# Main_Board.net
KiCad netlist of a schematic drawn in Altium Designer
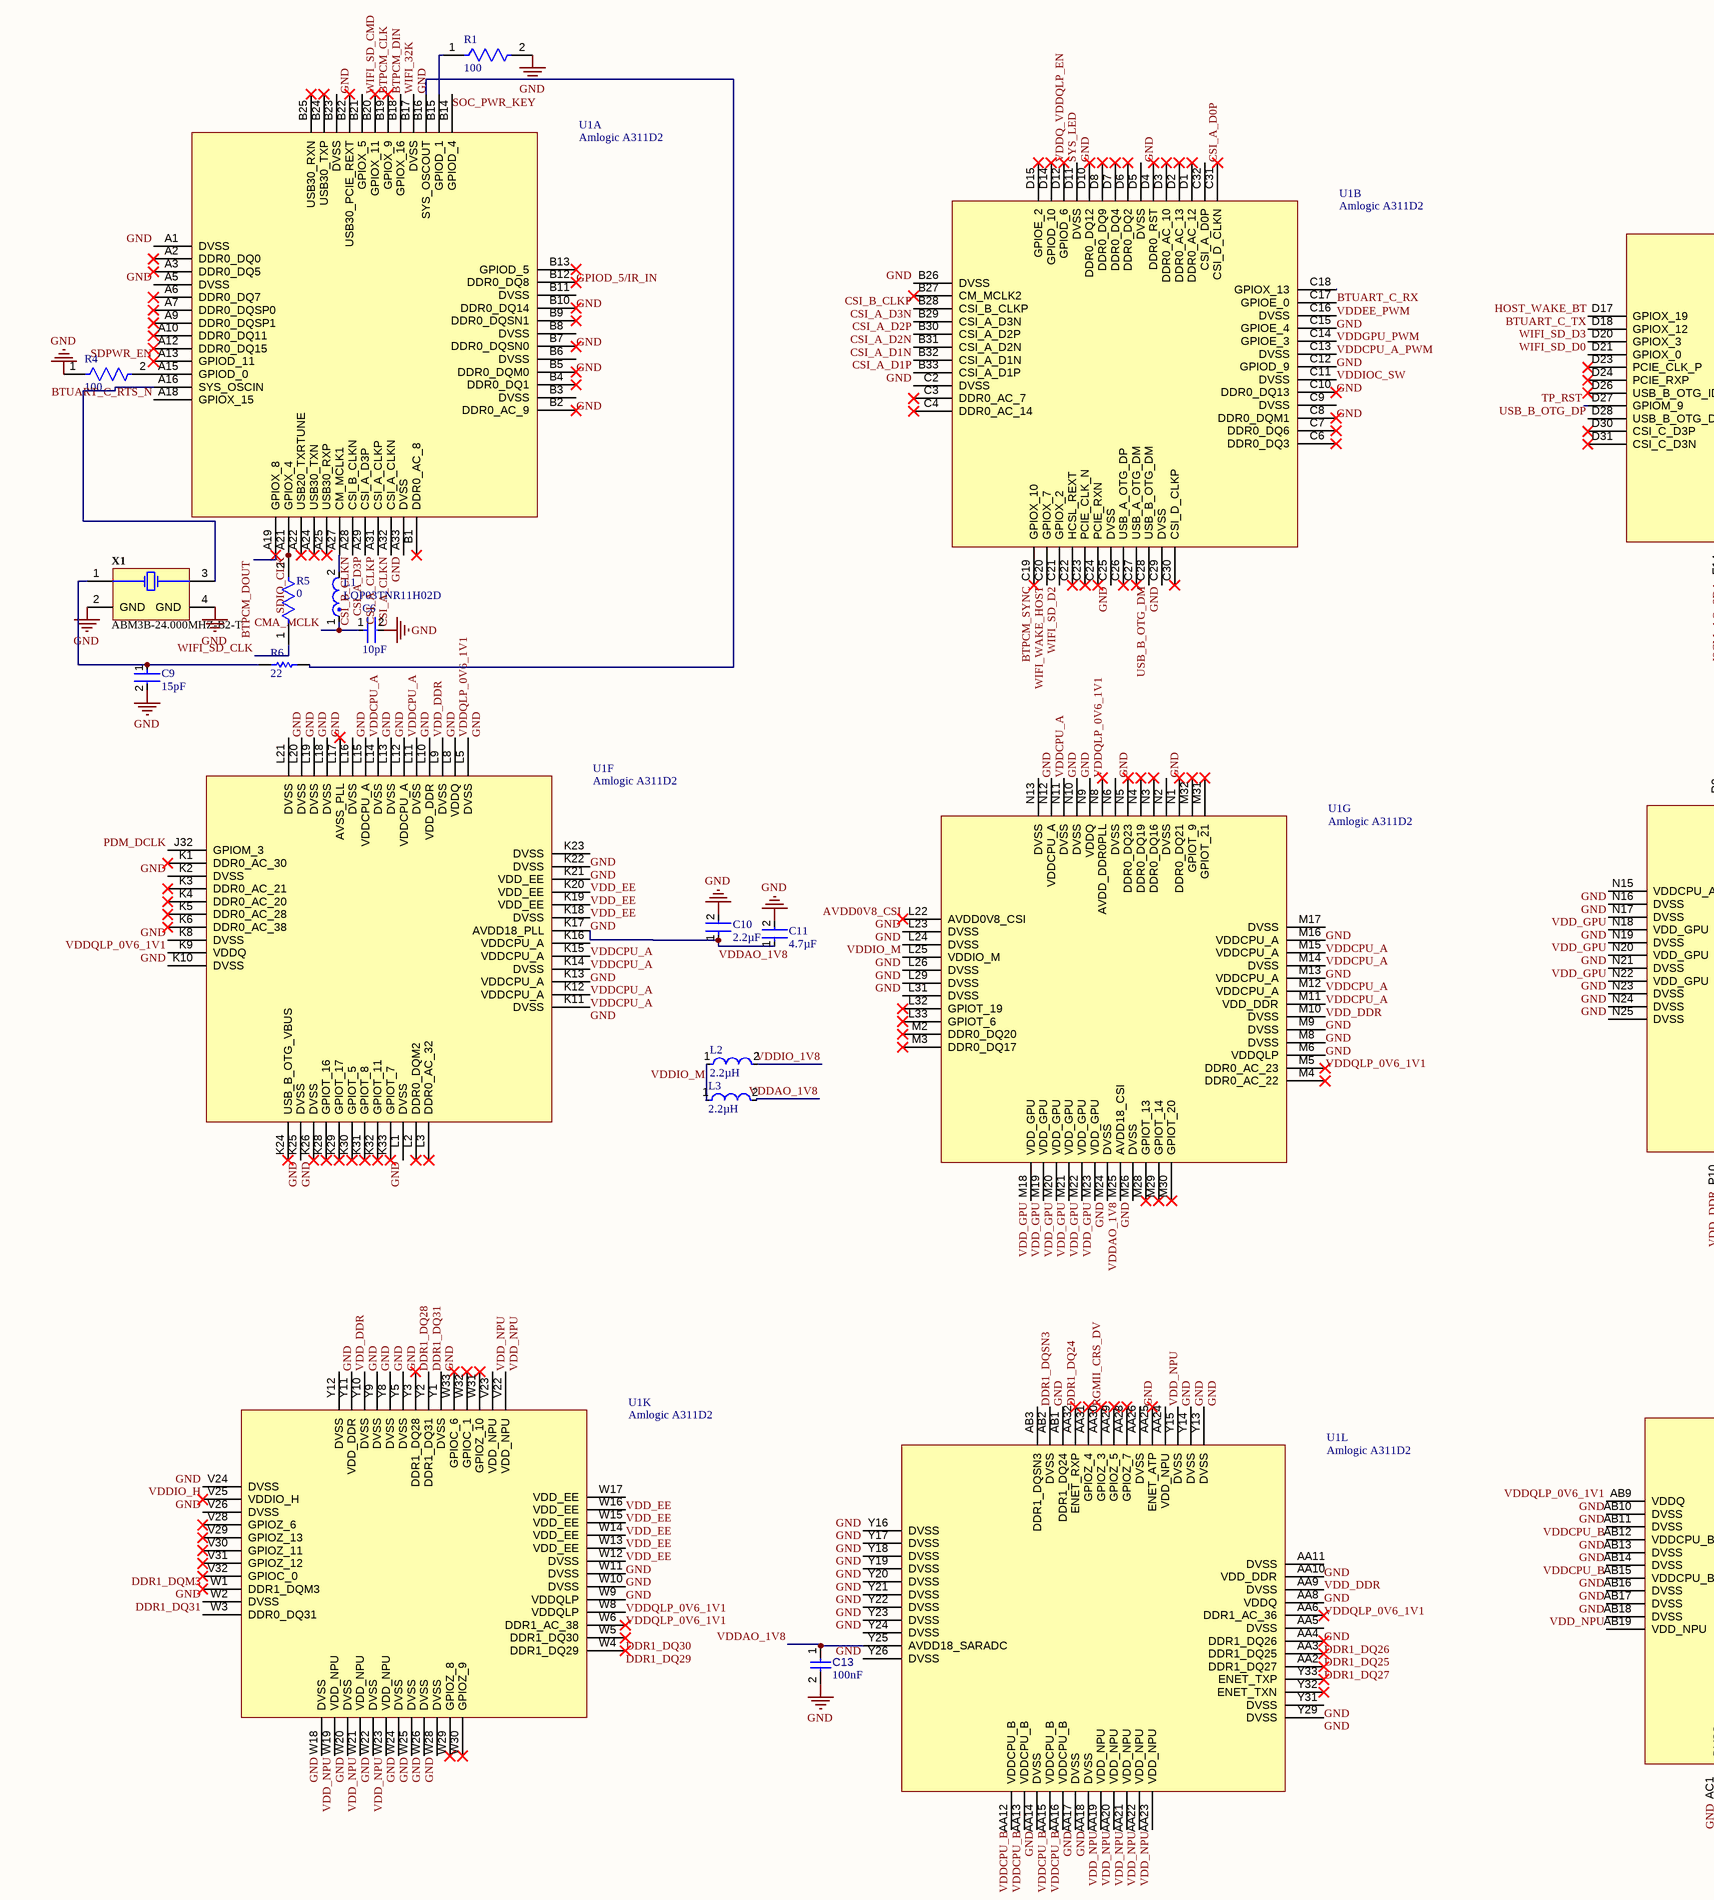
[diagram p0: Main_Board.SchDoc, top left]
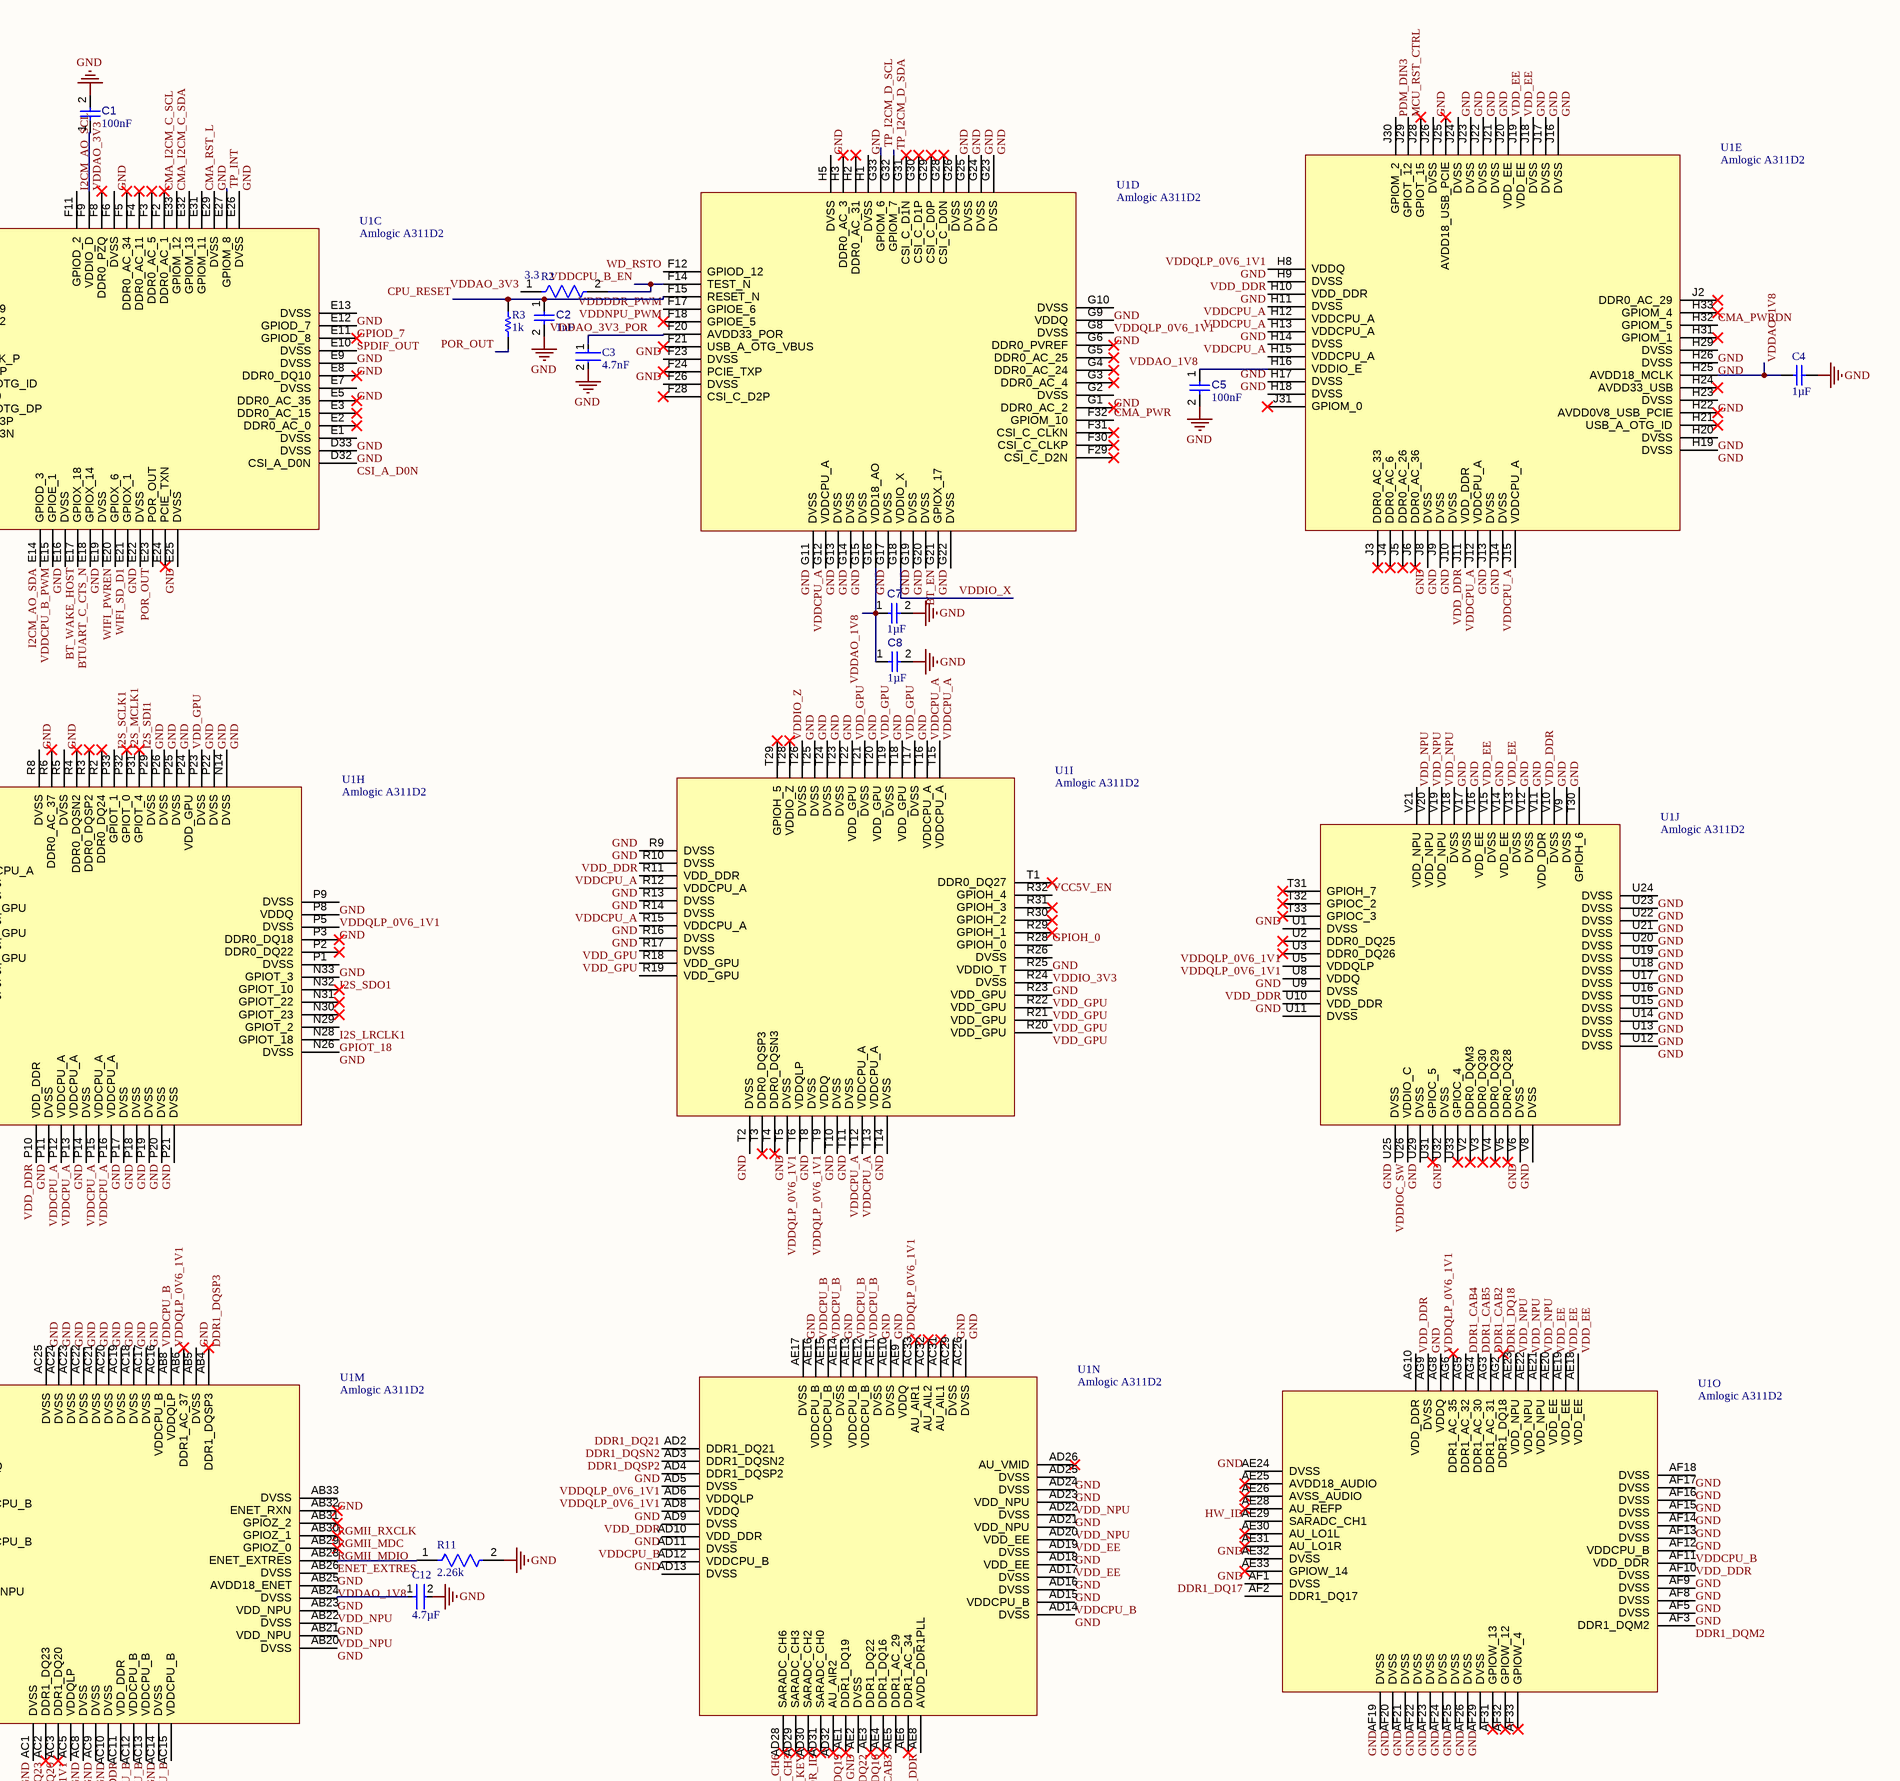
[diagram p1: Main_Board.SchDoc, top right]
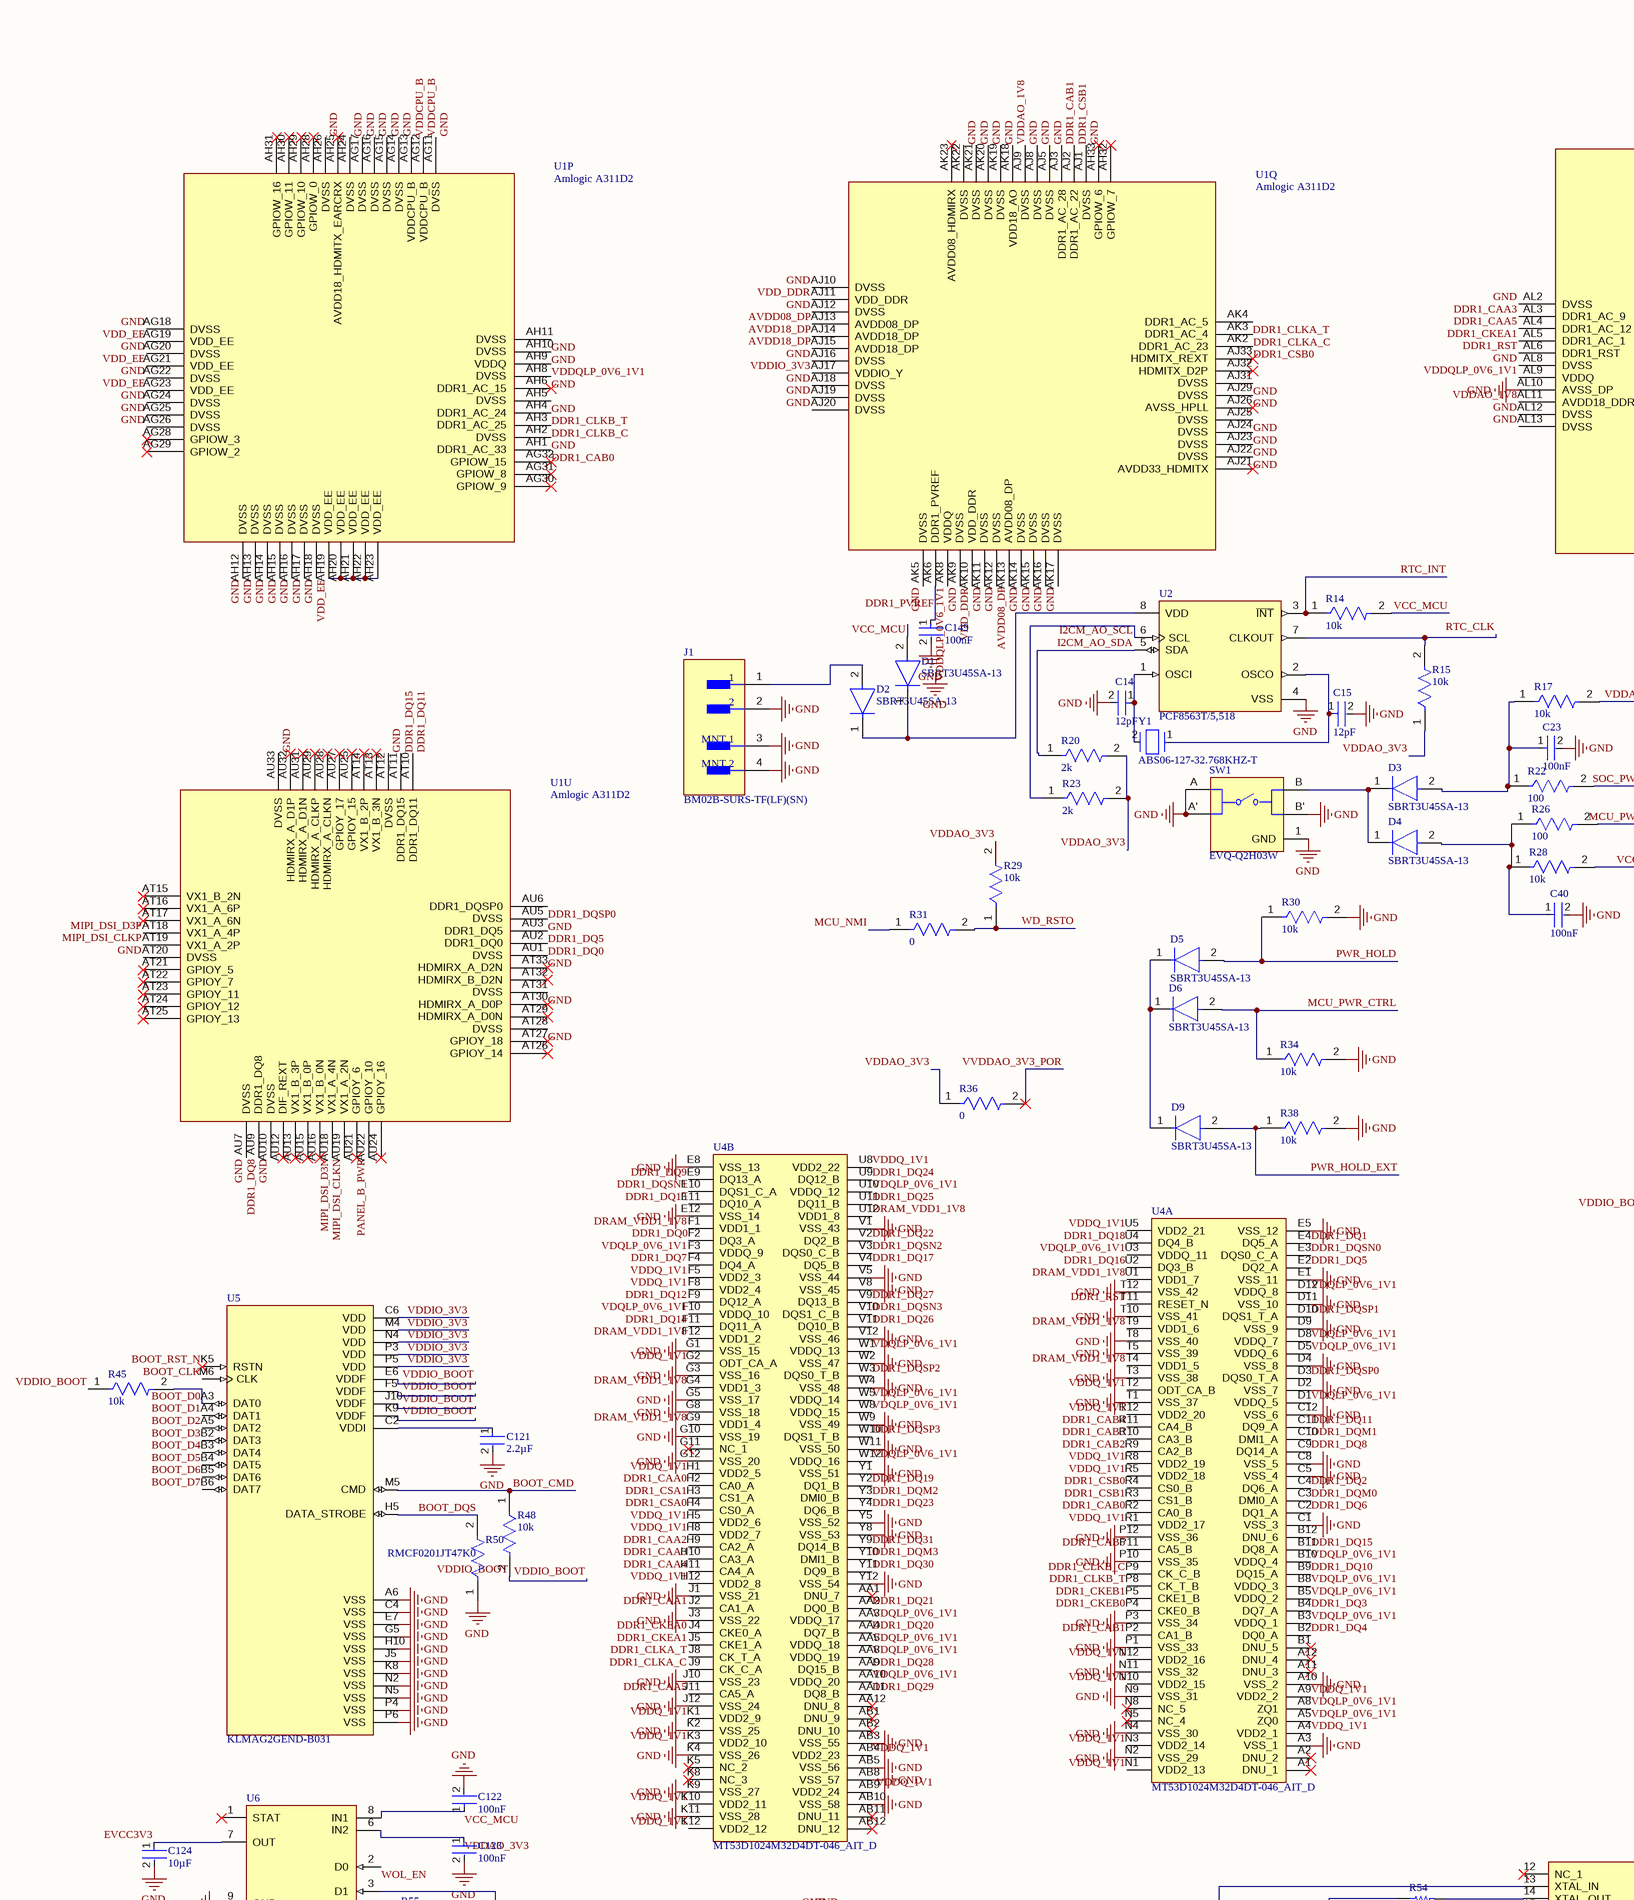
[diagram p2: Main_Board.SchDoc, centre left]
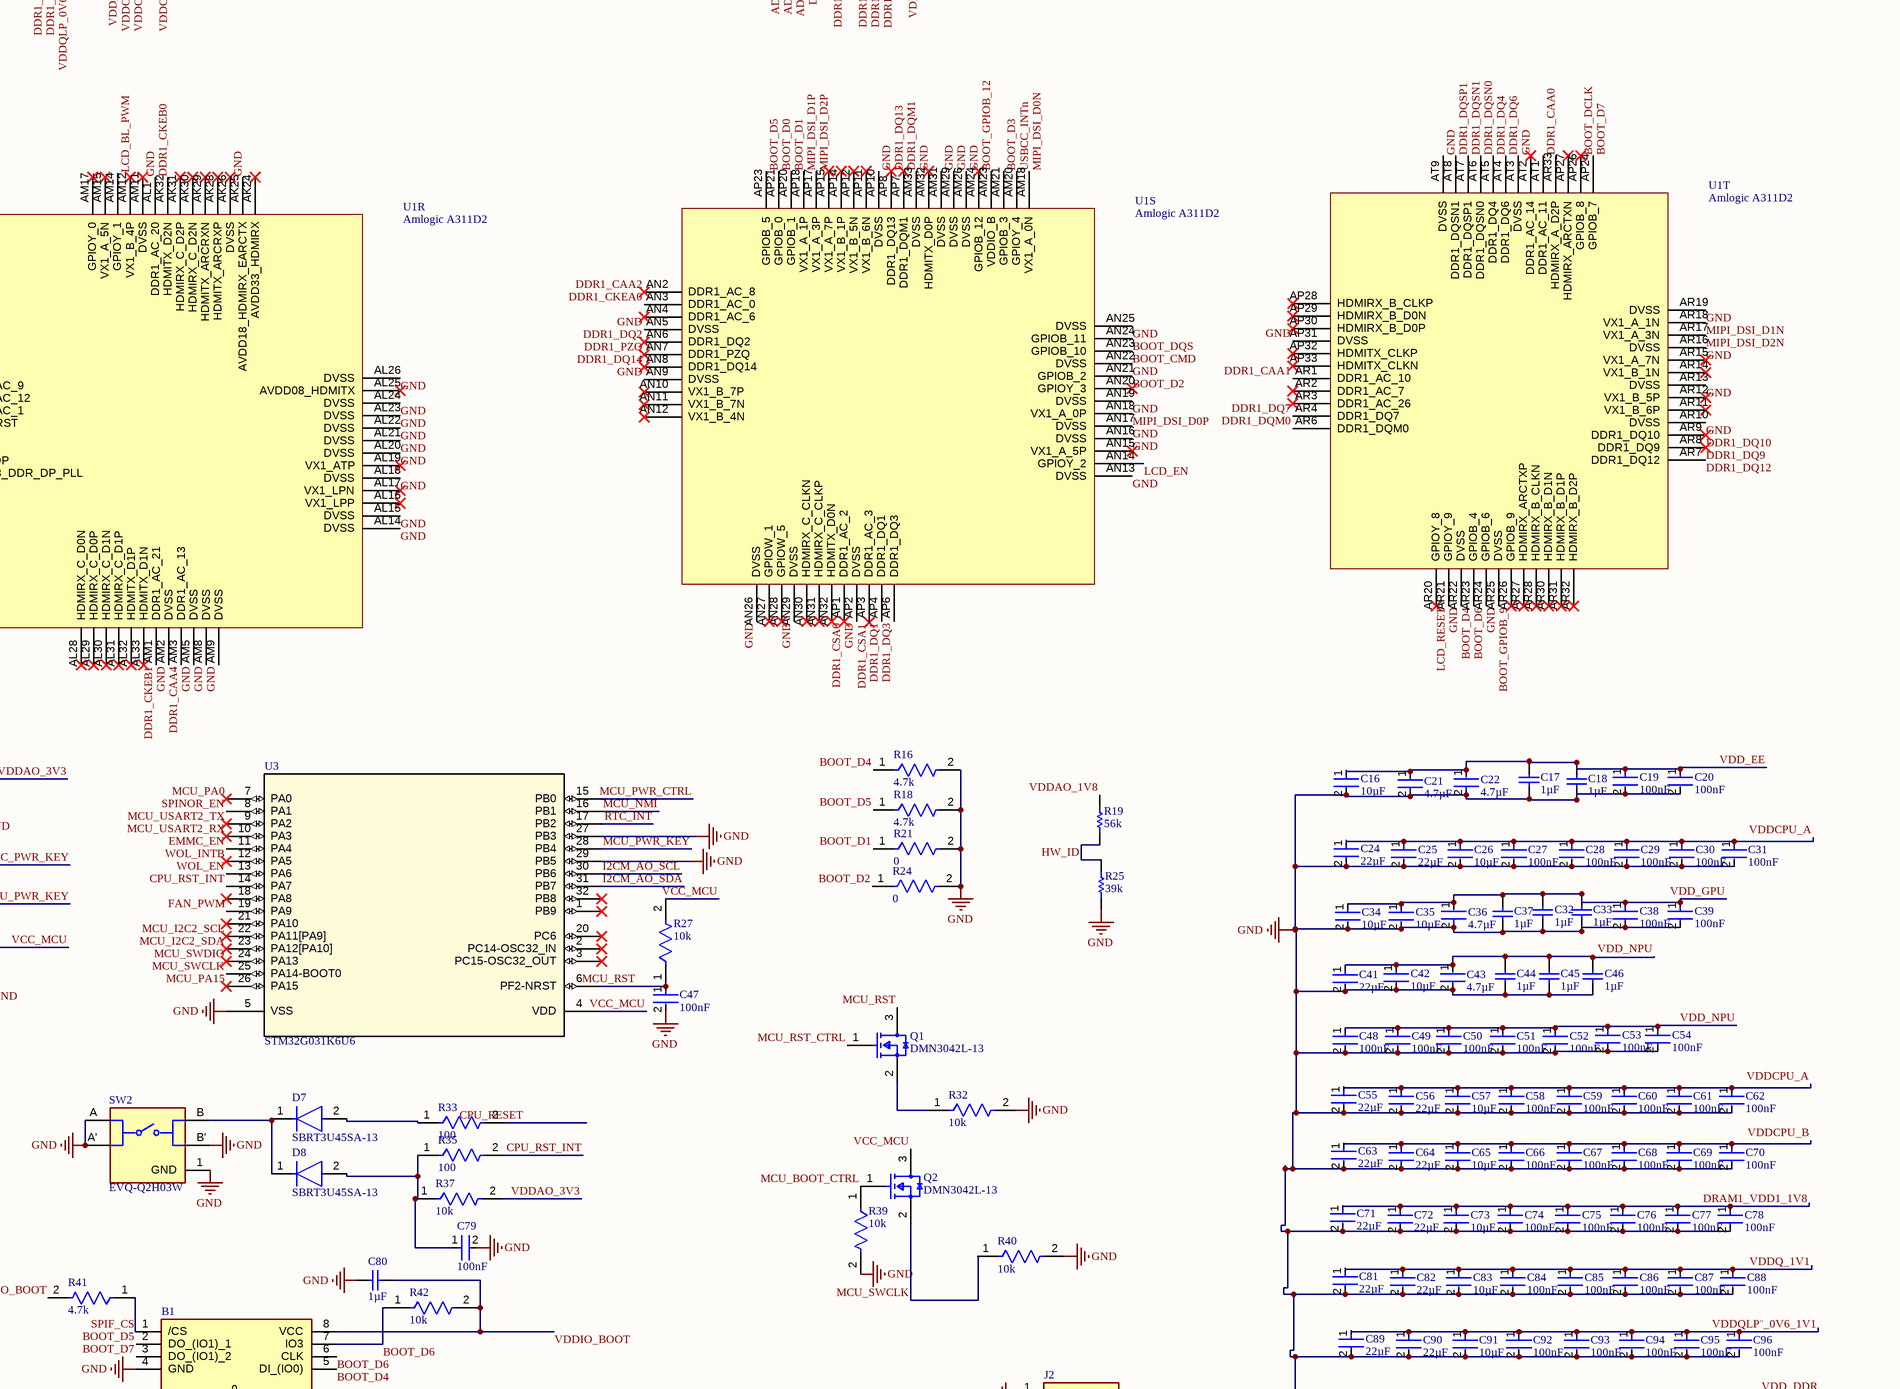
[diagram p3: Main_Board.SchDoc, centre right]
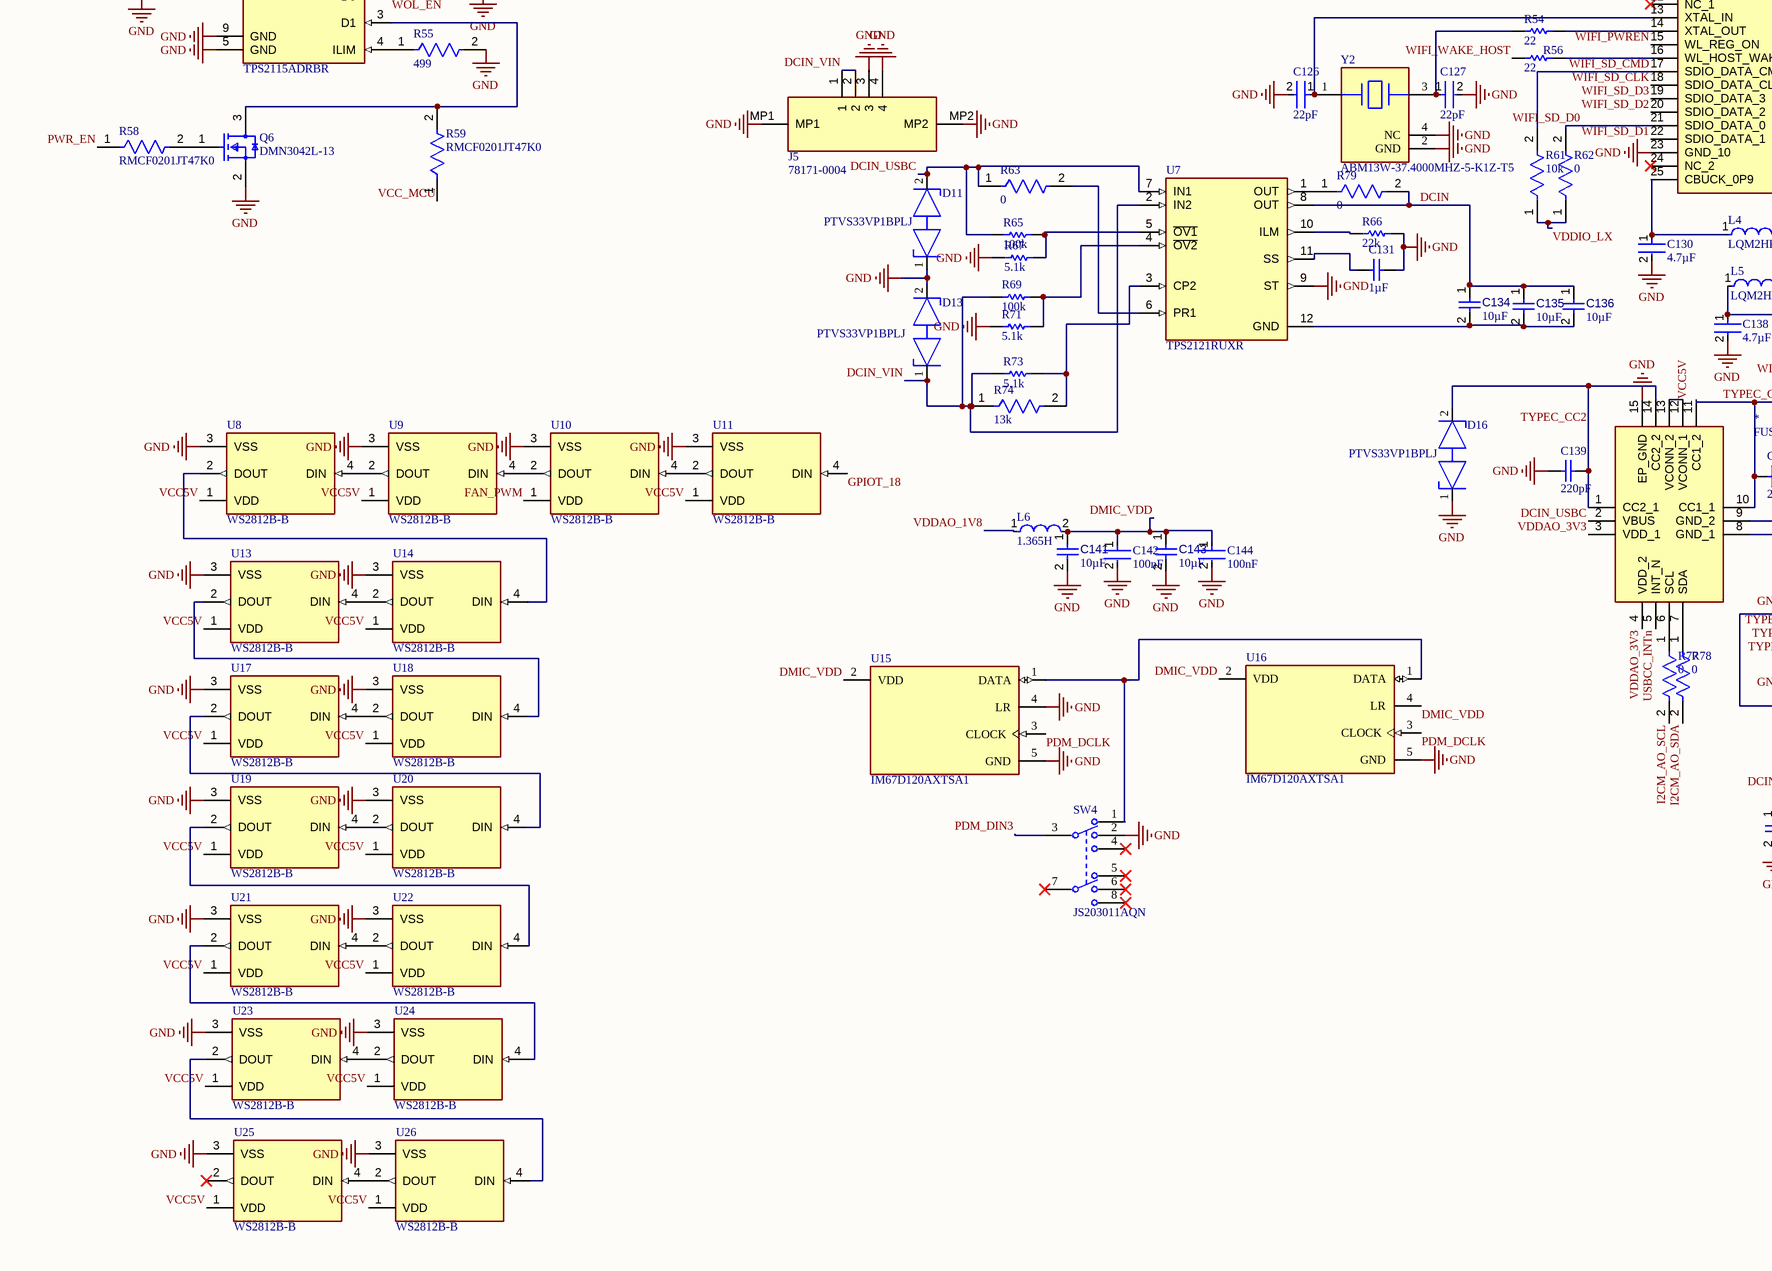
[diagram p4: Main_Board.SchDoc, bottom left]
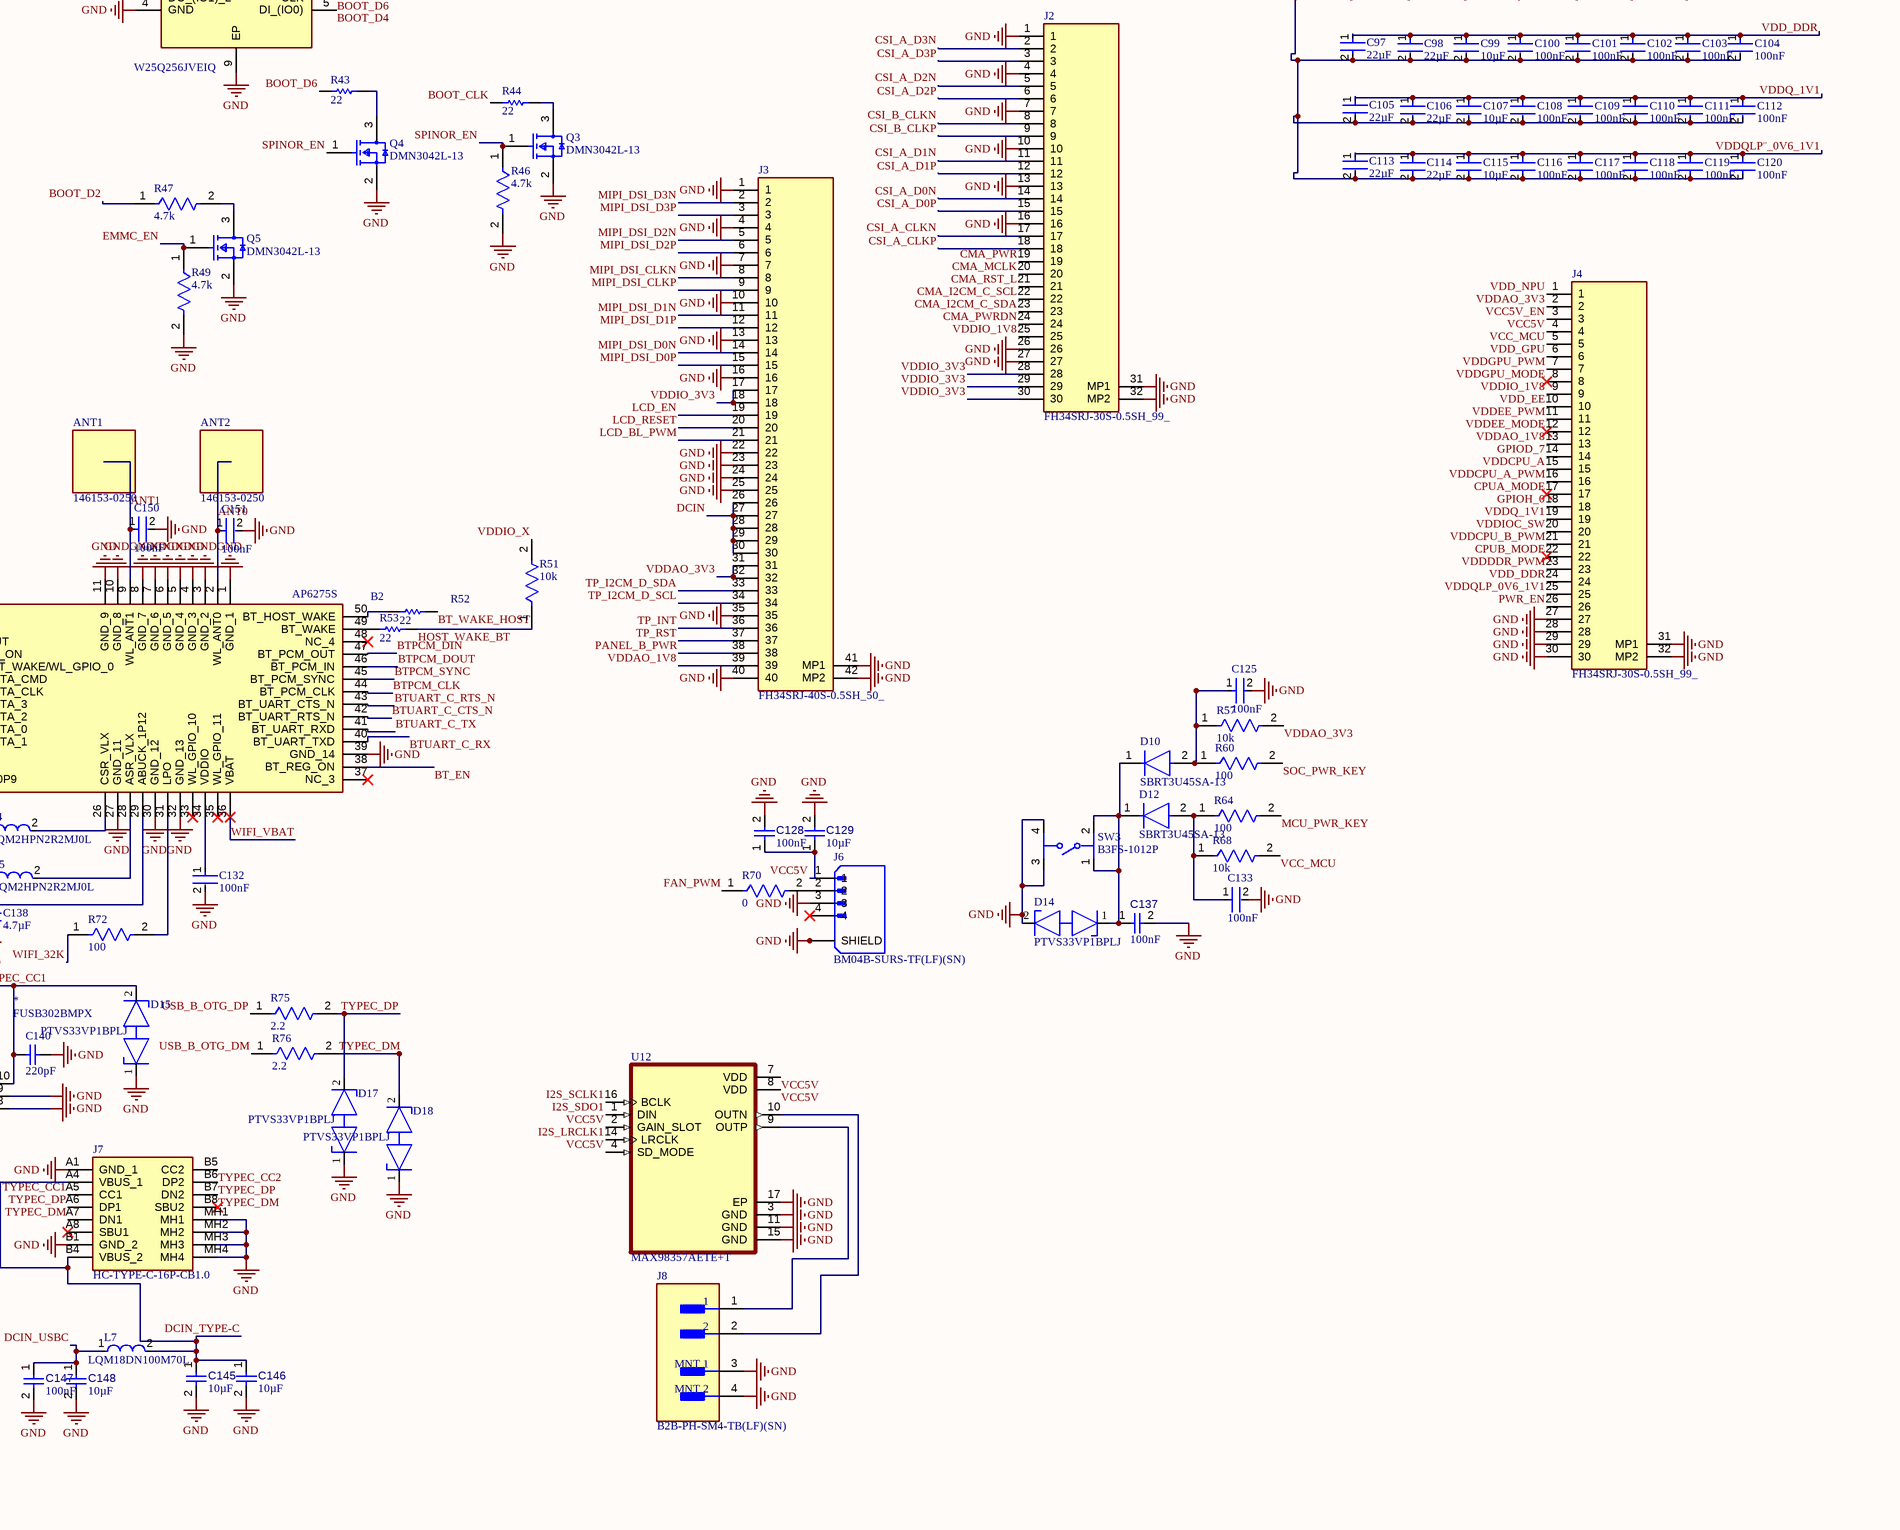
[diagram p5: Main_Board.SchDoc, bottom right]

(export (version "E")
  (design (tool "Eeschema 10.0.6"))
  (components
    (comp (ref "*")
      (value "FUSB302BMPX")
      (footprint "FUSB302BMPX-Footprint-1")
      (description "Full Speed Programmable USB Power Delivery Controller USB 3.1 3.3V T/R 14-Pin WQFN EP")
      (libsource (lib "MIGUEL ANGEL ALVAREZ GUZMAN") (part "FUSB302BMPX-Symbol-1"))
    )
    (comp (ref "ANT1")
      (value "146153-0250")
      (footprint "FP-146153-0250-MFG")
      (description "RF ANT 2.4/5GHZ FLAT PATCH 250MM")
      (fields
        (field (name "OCTOPART") "https://octopart.com/146153-0250-molex-65153393")
        (field (name "MANUFACTURER") "Molex")
      )
      (libsource (lib "Altium Content Vault") (part "87292ac8601c6cf2061292f5bede09e"))
    )
    (comp (ref "ANT2")
      (value "146153-0250")
      (footprint "FP-146153-0250-MFG")
      (description "RF ANT 2.4/5GHZ FLAT PATCH 250MM")
      (fields
        (field (name "OCTOPART") "https://octopart.com/146153-0250-molex-65153393")
        (field (name "MANUFACTURER") "Molex")
      )
      (libsource (lib "Altium Content Vault") (part "87292ac8601c6cf2061292f5bede09e"))
    )
    (comp (ref "B1")
      (value "W25Q256JVEIQ")
      (footprint "SON127P800X600X80-9N-D")
      (description "256M-bit Serial Flash Memory with uniform 4KB sectors and Dual/Quad SPI")
      (fields (field (name "MOUSER PART NUMBER") "454-W25Q256JVEIQ"))
      (libsource (lib "MIGUEL ANGEL ALVAREZ GUZMAN") (part "W25Q256JVEIQ"))
    )
    (comp (ref "B2")
      (value "AP6275S")
      (footprint "AP6275S")
      (description "IEEE 802.11ax/ac/a/b/g/n 2x2 WiFi with Bluetooth5.0 Combo Sip Module")
      (libsource (lib "MIGUEL ANGEL ALVAREZ GUZMAN") (part "AP6275S"))
    )
    (comp (ref "C1")
      (value "100nF")
      (footprint "CAPC0402(1005)60_L")
      (description "Chip Capacitor, 100nF +/-20%, 50V, 0402, Thickness 0.6 mm")
      (fields (field (name "TOLERANCE") "10%") (field (name "Comment") "Capacitor 100nF +/-20% 50V 0402"))
      (libsource (lib "MIGUEL ANGEL ALVAREZ GUZMAN") (part "CAP-NP-2"))
    )
    (comp (ref "C2")
      (value "1nF")
      (footprint "CAPC0402(1005)33_L")
      (description "Chip Capacitor, 1nF +/-20%, 50V, 0402, Thickness 0.33 mm")
      (fields (field (name "TOLERANCE") "10%") (field (name "Comment") "Capacitor 1nF +/-20% 50V 0402"))
      (libsource (lib "MIGUEL ANGEL ALVAREZ GUZMAN") (part "CAP-NP-2"))
    )
    (comp (ref "C3")
      (value "4.7nF")
      (footprint "FP-CC0201-BA-IPC_A")
      (description "Cap Ceramic 0.0047uF 10V X5R 10% Pad SMD 0201 85C Automotive T/R")
      (fields (field (name "TOLERANCE") "10%") (field (name "Comment") "CC0201KRX5R6BB472"))
      (libsource (lib "MIGUEL ANGEL ALVAREZ GUZMAN") (part "11868f565c42a9108669ba33697ecf6"))
    )
    (comp (ref "C4")
      (value "1µF")
      (footprint "CAPC0603X33X15LL03T05")
      (description "10V 1uF X5R ±20% 0201 Multilayer Ceramic Capacitors MLCC - SMD/SMT ROHS")
      (fields (field (name "TOLERANCE") "20%") (field (name "Comment") "0201ZD105MAT2A"))
      (libsource (lib "MIGUEL ANGEL ALVAREZ GUZMAN") (part "CAP"))
    )
    (comp (ref "C5")
      (value "100nF")
      (footprint "CAPC0402(1005)60_L")
      (description "Chip Capacitor, 100nF +/-20%, 10V, 0402, Thickness 0.6 mm")
      (fields (field (name "TOLERANCE") "20%") (field (name "Comment") "Capacitor 100nF +/-20% 10V 0402"))
      (libsource (lib "MIGUEL ANGEL ALVAREZ GUZMAN") (part "CAP-NP-2"))
    )
    (comp (ref "C6")
      (value "10pF")
      (footprint "FP-GRM033-0_03-MFG")
      (description "50V 10pF C0G ±1% 0201 Multilayer Ceramic Capacitors MLCC - SMD/SMT ROHS")
      (fields (field (name "TOLERANCE") "1%") (field (name "Comment") "GRM0335C1H100FA01D"))
      (libsource (lib "MIGUEL ANGEL ALVAREZ GUZMAN") (part "b4654b650e69147ec39a6b967a45e02"))
    )
    (comp (ref "C7")
      (value "1µF")
      (footprint "CAPC0402(1005)60_L")
      (description "Chip Capacitor, 1µF +/-20%, 10V, 0402, Thickness 0.6 mm")
      (fields (field (name "TOLERANCE") "10%") (field (name "Comment") "Capacitor 1µF +/-20% 10V 0402"))
      (libsource (lib "MIGUEL ANGEL ALVAREZ GUZMAN") (part "CAP-NP-2"))
    )
    (comp (ref "C8")
      (value "1µF")
      (footprint "CAPC0402(1005)60_L")
      (description "Chip Capacitor, 1µF +/-20%, 10V, 0402, Thickness 0.6 mm")
      (fields (field (name "TOLERANCE") "10%") (field (name "Comment") "Capacitor 1µF +/-20% 10V 0402"))
      (libsource (lib "MIGUEL ANGEL ALVAREZ GUZMAN") (part "CAP-NP-2"))
    )
    (comp (ref "C9")
      (value "15pF")
      (footprint "FP-C0201-AB-IPC_A")
      (description "0201 (0603METRIC) Ceramic Capacitor SMD Comm C0G 25V 15PF ±5% C0G NP0")
      (fields (field (name "TOLERANCE") "5%") (field (name "Comment") "C0201C150J3GACTU"))
      (libsource (lib "MIGUEL ANGEL ALVAREZ GUZMAN") (part "11868f565c42a9108669ba33697ecf6"))
    )
    (comp (ref "C10")
      (value "2.2µF")
      (footprint "FP-CC0201-BA-IPC_A")
      (description "10V 2.2uF X5R ±20% 0201 Multilayer Ceramic Capacitors MLCC - SMD/SMT ROHS")
      (fields (field (name "Comment") "CC0201MRX5R6BB225"))
      (libsource (lib "MIGUEL ANGEL ALVAREZ GUZMAN") (part "11868f565c42a9108669ba33697ecf6"))
    )
    (comp (ref "C11")
      (value "4.7µF")
      (footprint "FP-GRM035-0_09-IPC_B")
      (description "0201 4.7 uF 6.3 V ±10 % Tolerance X5R SMT Multilayer Ceramic Chip Capacitor")
      (fields (field (name "TOLERANCE") "20%") (field (name "Comment") "GRM035R60J475ME15J"))
      (libsource (lib "MIGUEL ANGEL ALVAREZ GUZMAN") (part "02cd4be3c70576c341d710602a673aa"))
    )
    (comp (ref "C12")
      (value "4.7µF")
      (footprint "FP-GRM035-0_09-IPC_B")
      (description "0201 4.7 uF 6.3 V ±10 % Tolerance X5R SMT Multilayer Ceramic Chip Capacitor")
      (fields (field (name "TOLERANCE") "20%") (field (name "Comment") "GRM035R60J475ME15J"))
      (libsource (lib "MIGUEL ANGEL ALVAREZ GUZMAN") (part "02cd4be3c70576c341d710602a673aa"))
    )
    (comp (ref "C13")
      (value "100nF")
      (footprint "CAPC0402(1005)60_L")
      (description "Chip Capacitor, 100nF +/-20%, 10V, 0402, Thickness 0.6 mm")
      (fields (field (name "TOLERANCE") "20%") (field (name "Comment") "Capacitor 100nF +/-20% 10V 0402"))
      (libsource (lib "MIGUEL ANGEL ALVAREZ GUZMAN") (part "CAP-NP-2"))
    )
    (comp (ref "C14")
      (value "12pF")
      (footprint "FP-GRM033-0_03-MFG")
      (description "CAP CER 12PF 50V C0G/NP0 0201 / 12 pF ±1% 50V Ceramic Capacitor C0G, NP0 0201 (0603 Metric)")
      (fields (field (name "TOLERANCE") "1%") (field (name "Comment") "GRM0335C1H120FA01D"))
      (libsource (lib "MIGUEL ANGEL ALVAREZ GUZMAN") (part "b4654b650e69147ec39a6b967a45e02"))
    )
    (comp (ref "C15")
      (value "12pF")
      (footprint "FP-GRM033-0_03-MFG")
      (description "CAP CER 12PF 50V C0G/NP0 0201 / 12 pF ±1% 50V Ceramic Capacitor C0G, NP0 0201 (0603 Metric)")
      (fields (field (name "TOLERANCE") "1%") (field (name "Comment") "GRM0335C1H120FA01D"))
      (libsource (lib "MIGUEL ANGEL ALVAREZ GUZMAN") (part "b4654b650e69147ec39a6b967a45e02"))
    )
    (comp (ref "C16")
      (value "10µF")
      (footprint "FP-GRM155-0_2-0_1-IPC_C")
      (description "CAP CER 10UF 4V X5R 0402 / 10 µF ±20% 4V Ceramic Capacitor X5R 0402 (1005 Metric)")
      (fields (field (name "TOLERANCE") "20%") (field (name "Comment") "GRM155R60G106ME47D"))
      (libsource (lib "MIGUEL ANGEL ALVAREZ GUZMAN") (part "b4654b650e69147ec39a6b967a45e02"))
    )
    (comp (ref "C17")
      (value "1µF")
      (footprint "CAPC0603X33X15LL03T05")
      (description "10V 1uF X5R ±20% 0201 Multilayer Ceramic Capacitors MLCC - SMD/SMT ROHS")
      (fields (field (name "TOLERANCE") "20%") (field (name "Comment") "0201ZD105MAT2A"))
      (libsource (lib "MIGUEL ANGEL ALVAREZ GUZMAN") (part "CAP"))
    )
    (comp (ref "C18")
      (value "1µF")
      (footprint "CAPC0603X33X15LL03T05")
      (description "10V 1uF X5R ±20% 0201 Multilayer Ceramic Capacitors MLCC - SMD/SMT ROHS")
      (fields (field (name "TOLERANCE") "20%") (field (name "Comment") "0201ZD105MAT2A"))
      (libsource (lib "MIGUEL ANGEL ALVAREZ GUZMAN") (part "CAP"))
    )
    (comp (ref "C19")
      (value "100nF")
      (footprint "FP-CC0201-BA-IPC_A")
      (description "16V 100nF X5R ±10% 0201 Multilayer Ceramic Capacitors MLCC - SMD/SMT ROHS")
      (fields (field (name "TOLERANCE") "10%") (field (name "Comment") "CC0201KRX5R7BB104"))
      (libsource (lib "MIGUEL ANGEL ALVAREZ GUZMAN") (part "11868f565c42a9108669ba33697ecf6"))
    )
    (comp (ref "C20")
      (value "100nF")
      (footprint "FP-CC0201-BA-IPC_A")
      (description "16V 100nF X5R ±10% 0201 Multilayer Ceramic Capacitors MLCC - SMD/SMT ROHS")
      (fields (field (name "TOLERANCE") "10%") (field (name "Comment") "CC0201KRX5R7BB104"))
      (libsource (lib "MIGUEL ANGEL ALVAREZ GUZMAN") (part "11868f565c42a9108669ba33697ecf6"))
    )
    (comp (ref "C21")
      (value "4.7µF")
      (footprint "FP-0402-L_1_0_0_15-W_0_5-IPC_B")
      (description "6.3V 4.7uF X5R ±20% 0402 Multilayer Ceramic Capacitors MLCC - SMD/SMT ROHS")
      (fields (field (name "TOLERANCE") "20%") (field (name "Comment") "JMK105BBJ475MVHF"))
      (libsource (lib "MIGUEL ANGEL ALVAREZ GUZMAN") (part "236180d848d6139a670b325ea6854c9"))
    )
    (comp (ref "C22")
      (value "4.7µF")
      (footprint "FP-0402-L_1_0_0_15-W_0_5-IPC_B")
      (description "6.3V 4.7uF X5R ±20% 0402 Multilayer Ceramic Capacitors MLCC - SMD/SMT ROHS")
      (fields (field (name "TOLERANCE") "20%") (field (name "Comment") "JMK105BBJ475MVHF"))
      (libsource (lib "MIGUEL ANGEL ALVAREZ GUZMAN") (part "236180d848d6139a670b325ea6854c9"))
    )
    (comp (ref "C23")
      (value "100nF")
      (footprint "FP-CC0201-BA-IPC_A")
      (description "16V 100nF X5R ±10% 0201 Multilayer Ceramic Capacitors MLCC - SMD/SMT ROHS")
      (fields (field (name "TOLERANCE") "10%") (field (name "Comment") "CC0201KRX5R7BB104"))
      (libsource (lib "MIGUEL ANGEL ALVAREZ GUZMAN") (part "11868f565c42a9108669ba33697ecf6"))
    )
    (comp (ref "C24")
      (value "22µF")
      (footprint "FP-GRM186-0_2-IPC_A")
      (description "6.3V 22uF X5R ±20% 0603 Multilayer Ceramic Capacitors MLCC - SMD/SMT ROHS")
      (fields (field (name "TOLERANCE") "20%") (field (name "Comment") "GRM186R60J226ME15D"))
      (libsource (lib "MIGUEL ANGEL ALVAREZ GUZMAN") (part "02cd4be3c70576c341d710602a673aa"))
    )
    (comp (ref "C25")
      (value "22µF")
      (footprint "FP-GRM186-0_2-IPC_A")
      (description "6.3V 22uF X5R ±20% 0603 Multilayer Ceramic Capacitors MLCC - SMD/SMT ROHS")
      (fields (field (name "TOLERANCE") "20%") (field (name "Comment") "GRM186R60J226ME15D"))
      (libsource (lib "MIGUEL ANGEL ALVAREZ GUZMAN") (part "02cd4be3c70576c341d710602a673aa"))
    )
    (comp (ref "C26")
      (value "10µF")
      (footprint "FP-GRM155-0_2-0_1-IPC_C")
      (description "CAP CER 10UF 4V X5R 0402 / 10 µF ±20% 4V Ceramic Capacitor X5R 0402 (1005 Metric)")
      (fields (field (name "TOLERANCE") "20%") (field (name "Comment") "GRM155R60G106ME47D"))
      (libsource (lib "MIGUEL ANGEL ALVAREZ GUZMAN") (part "b4654b650e69147ec39a6b967a45e02"))
    )
    (comp (ref "C27")
      (value "100nF")
      (footprint "FP-CC0201-BA-IPC_A")
      (description "16V 100nF X5R ±10% 0201 Multilayer Ceramic Capacitors MLCC - SMD/SMT ROHS")
      (fields (field (name "TOLERANCE") "10%") (field (name "Comment") "CC0201KRX5R7BB104"))
      (libsource (lib "MIGUEL ANGEL ALVAREZ GUZMAN") (part "11868f565c42a9108669ba33697ecf6"))
    )
    (comp (ref "C28")
      (value "100nF")
      (footprint "FP-CC0201-BA-IPC_A")
      (description "16V 100nF X5R ±10% 0201 Multilayer Ceramic Capacitors MLCC - SMD/SMT ROHS")
      (fields (field (name "TOLERANCE") "10%") (field (name "Comment") "CC0201KRX5R7BB104"))
      (libsource (lib "MIGUEL ANGEL ALVAREZ GUZMAN") (part "11868f565c42a9108669ba33697ecf6"))
    )
    (comp (ref "C29")
      (value "100nF")
      (footprint "FP-CC0201-BA-IPC_A")
      (description "16V 100nF X5R ±10% 0201 Multilayer Ceramic Capacitors MLCC - SMD/SMT ROHS")
      (fields (field (name "TOLERANCE") "10%") (field (name "Comment") "CC0201KRX5R7BB104"))
      (libsource (lib "MIGUEL ANGEL ALVAREZ GUZMAN") (part "11868f565c42a9108669ba33697ecf6"))
    )
    (comp (ref "C30")
      (value "100nF")
      (footprint "FP-CC0201-BA-IPC_A")
      (description "16V 100nF X5R ±10% 0201 Multilayer Ceramic Capacitors MLCC - SMD/SMT ROHS")
      (fields (field (name "TOLERANCE") "10%") (field (name "Comment") "CC0201KRX5R7BB104"))
      (libsource (lib "MIGUEL ANGEL ALVAREZ GUZMAN") (part "11868f565c42a9108669ba33697ecf6"))
    )
    (comp (ref "C31")
      (value "100nF")
      (footprint "FP-CC0201-BA-IPC_A")
      (description "16V 100nF X5R ±10% 0201 Multilayer Ceramic Capacitors MLCC - SMD/SMT ROHS")
      (fields (field (name "TOLERANCE") "10%") (field (name "Comment") "CC0201KRX5R7BB104"))
      (libsource (lib "MIGUEL ANGEL ALVAREZ GUZMAN") (part "11868f565c42a9108669ba33697ecf6"))
    )
    (comp (ref "C32")
      (value "1µF")
      (footprint "CAPC0603X33X15LL03T05")
      (description "10V 1uF X5R ±20% 0201 Multilayer Ceramic Capacitors MLCC - SMD/SMT ROHS")
      (fields (field (name "TOLERANCE") "20%") (field (name "Comment") "0201ZD105MAT2A"))
      (libsource (lib "MIGUEL ANGEL ALVAREZ GUZMAN") (part "CAP"))
    )
    (comp (ref "C33")
      (value "1µF")
      (footprint "CAPC0603X33X15LL03T05")
      (description "10V 1uF X5R ±20% 0201 Multilayer Ceramic Capacitors MLCC - SMD/SMT ROHS")
      (fields (field (name "TOLERANCE") "20%") (field (name "Comment") "0201ZD105MAT2A"))
      (libsource (lib "MIGUEL ANGEL ALVAREZ GUZMAN") (part "CAP"))
    )
    (comp (ref "C34")
      (value "10µF")
      (footprint "FP-GRM155-0_2-0_1-IPC_C")
      (description "CAP CER 10UF 4V X5R 0402 / 10 µF ±20% 4V Ceramic Capacitor X5R 0402 (1005 Metric)")
      (fields (field (name "TOLERANCE") "20%") (field (name "Comment") "GRM155R60G106ME47D"))
      (libsource (lib "MIGUEL ANGEL ALVAREZ GUZMAN") (part "b4654b650e69147ec39a6b967a45e02"))
    )
    (comp (ref "C35")
      (value "10µF")
      (footprint "FP-GRM155-0_2-0_1-IPC_C")
      (description "CAP CER 10UF 4V X5R 0402 / 10 µF ±20% 4V Ceramic Capacitor X5R 0402 (1005 Metric)")
      (fields (field (name "TOLERANCE") "20%") (field (name "Comment") "GRM155R60G106ME47D"))
      (libsource (lib "MIGUEL ANGEL ALVAREZ GUZMAN") (part "b4654b650e69147ec39a6b967a45e02"))
    )
    (comp (ref "C36")
      (value "4.7µF")
      (footprint "FP-0402-L_1_0_0_15-W_0_5-IPC_B")
      (description "6.3V 4.7uF X5R ±20% 0402 Multilayer Ceramic Capacitors MLCC - SMD/SMT ROHS")
      (fields (field (name "TOLERANCE") "20%") (field (name "Comment") "JMK105BBJ475MVHF"))
      (libsource (lib "MIGUEL ANGEL ALVAREZ GUZMAN") (part "236180d848d6139a670b325ea6854c9"))
    )
    (comp (ref "C37")
      (value "1µF")
      (footprint "CAPC0603X33X15LL03T05")
      (description "10V 1uF X5R ±20% 0201 Multilayer Ceramic Capacitors MLCC - SMD/SMT ROHS")
      (fields (field (name "TOLERANCE") "20%") (field (name "Comment") "0201ZD105MAT2A"))
      (libsource (lib "MIGUEL ANGEL ALVAREZ GUZMAN") (part "CAP"))
    )
    (comp (ref "C38")
      (value "100nF")
      (footprint "FP-CC0201-BA-IPC_A")
      (description "16V 100nF X5R ±10% 0201 Multilayer Ceramic Capacitors MLCC - SMD/SMT ROHS")
      (fields (field (name "TOLERANCE") "10%") (field (name "Comment") "CC0201KRX5R7BB104"))
      (libsource (lib "MIGUEL ANGEL ALVAREZ GUZMAN") (part "11868f565c42a9108669ba33697ecf6"))
    )
    (comp (ref "C39")
      (value "100nF")
      (footprint "FP-CC0201-BA-IPC_A")
      (description "16V 100nF X5R ±10% 0201 Multilayer Ceramic Capacitors MLCC - SMD/SMT ROHS")
      (fields (field (name "TOLERANCE") "10%") (field (name "Comment") "CC0201KRX5R7BB104"))
      (libsource (lib "MIGUEL ANGEL ALVAREZ GUZMAN") (part "11868f565c42a9108669ba33697ecf6"))
    )
    (comp (ref "C40")
      (value "100nF")
      (footprint "FP-CC0201-BA-IPC_A")
      (description "16V 100nF X5R ±10% 0201 Multilayer Ceramic Capacitors MLCC - SMD/SMT ROHS")
      (fields (field (name "TOLERANCE") "10%") (field (name "Comment") "CC0201KRX5R7BB104"))
      (libsource (lib "MIGUEL ANGEL ALVAREZ GUZMAN") (part "11868f565c42a9108669ba33697ecf6"))
    )
    (comp (ref "C41")
      (value "22µF")
      (footprint "FP-GRM186-0_2-IPC_A")
      (description "6.3V 22uF X5R ±20% 0603 Multilayer Ceramic Capacitors MLCC - SMD/SMT ROHS")
      (fields (field (name "TOLERANCE") "20%") (field (name "Comment") "GRM186R60J226ME15D"))
      (libsource (lib "MIGUEL ANGEL ALVAREZ GUZMAN") (part "02cd4be3c70576c341d710602a673aa"))
    )
    (comp (ref "C42")
      (value "10µF")
      (footprint "FP-GRM155-0_2-0_1-IPC_C")
      (description "CAP CER 10UF 4V X5R 0402 / 10 µF ±20% 4V Ceramic Capacitor X5R 0402 (1005 Metric)")
      (fields (field (name "TOLERANCE") "20%") (field (name "Comment") "GRM155R60G106ME47D"))
      (libsource (lib "MIGUEL ANGEL ALVAREZ GUZMAN") (part "b4654b650e69147ec39a6b967a45e02"))
    )
    (comp (ref "C43")
      (value "4.7µF")
      (footprint "FP-0402-L_1_0_0_15-W_0_5-IPC_B")
      (description "6.3V 4.7uF X5R ±20% 0402 Multilayer Ceramic Capacitors MLCC - SMD/SMT ROHS")
      (fields (field (name "TOLERANCE") "20%") (field (name "Comment") "JMK105BBJ475MVHF"))
      (libsource (lib "MIGUEL ANGEL ALVAREZ GUZMAN") (part "236180d848d6139a670b325ea6854c9"))
    )
    (comp (ref "C44")
      (value "1µF")
      (footprint "CAPC0603X33X15LL03T05")
      (description "10V 1uF X5R ±20% 0201 Multilayer Ceramic Capacitors MLCC - SMD/SMT ROHS")
      (fields (field (name "TOLERANCE") "20%") (field (name "Comment") "0201ZD105MAT2A"))
      (libsource (lib "MIGUEL ANGEL ALVAREZ GUZMAN") (part "CAP"))
    )
    (comp (ref "C45")
      (value "1µF")
      (footprint "CAPC0603X33X15LL03T05")
      (description "10V 1uF X5R ±20% 0201 Multilayer Ceramic Capacitors MLCC - SMD/SMT ROHS")
      (fields (field (name "TOLERANCE") "20%") (field (name "Comment") "0201ZD105MAT2A"))
      (libsource (lib "MIGUEL ANGEL ALVAREZ GUZMAN") (part "CAP"))
    )
    (comp (ref "C46")
      (value "1µF")
      (footprint "CAPC0603X33X15LL03T05")
      (description "10V 1uF X5R ±20% 0201 Multilayer Ceramic Capacitors MLCC - SMD/SMT ROHS")
      (fields (field (name "TOLERANCE") "20%") (field (name "Comment") "0201ZD105MAT2A"))
      (libsource (lib "MIGUEL ANGEL ALVAREZ GUZMAN") (part "CAP"))
    )
    (comp (ref "C47")
      (value "100nF")
      (footprint "FP-CC0201-BA-IPC_A")
      (description "16V 100nF X5R ±10% 0201 Multilayer Ceramic Capacitors MLCC - SMD/SMT ROHS")
      (fields (field (name "TOLERANCE") "10%") (field (name "Comment") "CC0201KRX5R7BB104"))
      (libsource (lib "MIGUEL ANGEL ALVAREZ GUZMAN") (part "11868f565c42a9108669ba33697ecf6"))
    )
    (comp (ref "C48")
      (value "100nF")
      (footprint "FP-CC0201-BA-IPC_A")
      (description "16V 100nF X5R ±10% 0201 Multilayer Ceramic Capacitors MLCC - SMD/SMT ROHS")
      (fields (field (name "TOLERANCE") "10%") (field (name "Comment") "CC0201KRX5R7BB104"))
      (libsource (lib "MIGUEL ANGEL ALVAREZ GUZMAN") (part "11868f565c42a9108669ba33697ecf6"))
    )
    (comp (ref "C49")
      (value "100nF")
      (footprint "FP-CC0201-BA-IPC_A")
      (description "16V 100nF X5R ±10% 0201 Multilayer Ceramic Capacitors MLCC - SMD/SMT ROHS")
      (fields (field (name "TOLERANCE") "10%") (field (name "Comment") "CC0201KRX5R7BB104"))
      (libsource (lib "MIGUEL ANGEL ALVAREZ GUZMAN") (part "11868f565c42a9108669ba33697ecf6"))
    )
    (comp (ref "C50")
      (value "100nF")
      (footprint "FP-CC0201-BA-IPC_A")
      (description "16V 100nF X5R ±10% 0201 Multilayer Ceramic Capacitors MLCC - SMD/SMT ROHS")
      (fields (field (name "TOLERANCE") "10%") (field (name "Comment") "CC0201KRX5R7BB104"))
      (libsource (lib "MIGUEL ANGEL ALVAREZ GUZMAN") (part "11868f565c42a9108669ba33697ecf6"))
    )
    (comp (ref "C51")
      (value "100nF")
      (footprint "FP-CC0201-BA-IPC_A")
      (description "16V 100nF X5R ±10% 0201 Multilayer Ceramic Capacitors MLCC - SMD/SMT ROHS")
      (fields (field (name "TOLERANCE") "10%") (field (name "Comment") "CC0201KRX5R7BB104"))
      (libsource (lib "MIGUEL ANGEL ALVAREZ GUZMAN") (part "11868f565c42a9108669ba33697ecf6"))
    )
    (comp (ref "C52")
      (value "100nF")
      (footprint "FP-CC0201-BA-IPC_A")
      (description "16V 100nF X5R ±10% 0201 Multilayer Ceramic Capacitors MLCC - SMD/SMT ROHS")
      (fields (field (name "TOLERANCE") "10%") (field (name "Comment") "CC0201KRX5R7BB104"))
      (libsource (lib "MIGUEL ANGEL ALVAREZ GUZMAN") (part "11868f565c42a9108669ba33697ecf6"))
    )
    (comp (ref "C53")
      (value "100nF")
      (footprint "FP-CC0201-BA-IPC_A")
      (description "16V 100nF X5R ±10% 0201 Multilayer Ceramic Capacitors MLCC - SMD/SMT ROHS")
      (fields (field (name "TOLERANCE") "10%") (field (name "Comment") "CC0201KRX5R7BB104"))
      (libsource (lib "MIGUEL ANGEL ALVAREZ GUZMAN") (part "11868f565c42a9108669ba33697ecf6"))
    )
    (comp (ref "C54")
      (value "100nF")
      (footprint "FP-CC0201-BA-IPC_A")
      (description "16V 100nF X5R ±10% 0201 Multilayer Ceramic Capacitors MLCC - SMD/SMT ROHS")
      (fields (field (name "TOLERANCE") "10%") (field (name "Comment") "CC0201KRX5R7BB104"))
      (libsource (lib "MIGUEL ANGEL ALVAREZ GUZMAN") (part "11868f565c42a9108669ba33697ecf6"))
    )
    (comp (ref "C55")
      (value "22µF")
      (footprint "FP-GRM186-0_2-IPC_A")
      (description "6.3V 22uF X5R ±20% 0603 Multilayer Ceramic Capacitors MLCC - SMD/SMT ROHS")
      (fields (field (name "TOLERANCE") "20%") (field (name "Comment") "GRM186R60J226ME15D"))
      (libsource (lib "MIGUEL ANGEL ALVAREZ GUZMAN") (part "02cd4be3c70576c341d710602a673aa"))
    )
    (comp (ref "C56")
      (value "22µF")
      (footprint "FP-GRM186-0_2-IPC_A")
      (description "6.3V 22uF X5R ±20% 0603 Multilayer Ceramic Capacitors MLCC - SMD/SMT ROHS")
      (fields (field (name "TOLERANCE") "20%") (field (name "Comment") "GRM186R60J226ME15D"))
      (libsource (lib "MIGUEL ANGEL ALVAREZ GUZMAN") (part "02cd4be3c70576c341d710602a673aa"))
    )
    (comp (ref "C57")
      (value "10µF")
      (footprint "FP-GRM155-0_2-0_1-IPC_C")
      (description "CAP CER 10UF 4V X5R 0402 / 10 µF ±20% 4V Ceramic Capacitor X5R 0402 (1005 Metric)")
      (fields (field (name "TOLERANCE") "20%") (field (name "Comment") "GRM155R60G106ME47D"))
      (libsource (lib "MIGUEL ANGEL ALVAREZ GUZMAN") (part "b4654b650e69147ec39a6b967a45e02"))
    )
    (comp (ref "C58")
      (value "100nF")
      (footprint "FP-CC0201-BA-IPC_A")
      (description "16V 100nF X5R ±10% 0201 Multilayer Ceramic Capacitors MLCC - SMD/SMT ROHS")
      (fields (field (name "TOLERANCE") "10%") (field (name "Comment") "CC0201KRX5R7BB104"))
      (libsource (lib "MIGUEL ANGEL ALVAREZ GUZMAN") (part "11868f565c42a9108669ba33697ecf6"))
    )
    (comp (ref "C59")
      (value "100nF")
      (footprint "FP-CC0201-BA-IPC_A")
      (description "16V 100nF X5R ±10% 0201 Multilayer Ceramic Capacitors MLCC - SMD/SMT ROHS")
      (fields (field (name "TOLERANCE") "10%") (field (name "Comment") "CC0201KRX5R7BB104"))
      (libsource (lib "MIGUEL ANGEL ALVAREZ GUZMAN") (part "11868f565c42a9108669ba33697ecf6"))
    )
    (comp (ref "C60")
      (value "100nF")
      (footprint "FP-CC0201-BA-IPC_A")
      (description "16V 100nF X5R ±10% 0201 Multilayer Ceramic Capacitors MLCC - SMD/SMT ROHS")
      (fields (field (name "TOLERANCE") "10%") (field (name "Comment") "CC0201KRX5R7BB104"))
      (libsource (lib "MIGUEL ANGEL ALVAREZ GUZMAN") (part "11868f565c42a9108669ba33697ecf6"))
    )
    (comp (ref "C61")
      (value "100nF")
      (footprint "FP-CC0201-BA-IPC_A")
      (description "16V 100nF X5R ±10% 0201 Multilayer Ceramic Capacitors MLCC - SMD/SMT ROHS")
      (fields (field (name "TOLERANCE") "10%") (field (name "Comment") "CC0201KRX5R7BB104"))
      (libsource (lib "MIGUEL ANGEL ALVAREZ GUZMAN") (part "11868f565c42a9108669ba33697ecf6"))
    )
    (comp (ref "C62")
      (value "100nF")
      (footprint "FP-CC0201-BA-IPC_A")
      (description "16V 100nF X5R ±10% 0201 Multilayer Ceramic Capacitors MLCC - SMD/SMT ROHS")
      (fields (field (name "TOLERANCE") "10%") (field (name "Comment") "CC0201KRX5R7BB104"))
      (libsource (lib "MIGUEL ANGEL ALVAREZ GUZMAN") (part "11868f565c42a9108669ba33697ecf6"))
    )
    (comp (ref "C63")
      (value "22µF")
      (footprint "FP-GRM186-0_2-IPC_A")
      (description "6.3V 22uF X5R ±20% 0603 Multilayer Ceramic Capacitors MLCC - SMD/SMT ROHS")
      (fields (field (name "TOLERANCE") "20%") (field (name "Comment") "GRM186R60J226ME15D"))
      (libsource (lib "MIGUEL ANGEL ALVAREZ GUZMAN") (part "02cd4be3c70576c341d710602a673aa"))
    )
    (comp (ref "C64")
      (value "22µF")
      (footprint "FP-GRM186-0_2-IPC_A")
      (description "6.3V 22uF X5R ±20% 0603 Multilayer Ceramic Capacitors MLCC - SMD/SMT ROHS")
      (fields (field (name "TOLERANCE") "20%") (field (name "Comment") "GRM186R60J226ME15D"))
      (libsource (lib "MIGUEL ANGEL ALVAREZ GUZMAN") (part "02cd4be3c70576c341d710602a673aa"))
    )
    (comp (ref "C65")
      (value "10µF")
      (footprint "FP-GRM155-0_2-0_1-IPC_C")
      (description "CAP CER 10UF 4V X5R 0402 / 10 µF ±20% 4V Ceramic Capacitor X5R 0402 (1005 Metric)")
      (fields (field (name "TOLERANCE") "20%") (field (name "Comment") "GRM155R60G106ME47D"))
      (libsource (lib "MIGUEL ANGEL ALVAREZ GUZMAN") (part "b4654b650e69147ec39a6b967a45e02"))
    )
    (comp (ref "C66")
      (value "100nF")
      (footprint "FP-CC0201-BA-IPC_A")
      (description "16V 100nF X5R ±10% 0201 Multilayer Ceramic Capacitors MLCC - SMD/SMT ROHS")
      (fields (field (name "TOLERANCE") "10%") (field (name "Comment") "CC0201KRX5R7BB104"))
      (libsource (lib "MIGUEL ANGEL ALVAREZ GUZMAN") (part "11868f565c42a9108669ba33697ecf6"))
    )
    (comp (ref "C67")
      (value "100nF")
      (footprint "FP-CC0201-BA-IPC_A")
      (description "16V 100nF X5R ±10% 0201 Multilayer Ceramic Capacitors MLCC - SMD/SMT ROHS")
      (fields (field (name "TOLERANCE") "10%") (field (name "Comment") "CC0201KRX5R7BB104"))
      (libsource (lib "MIGUEL ANGEL ALVAREZ GUZMAN") (part "11868f565c42a9108669ba33697ecf6"))
    )
    (comp (ref "C68")
      (value "100nF")
      (footprint "FP-CC0201-BA-IPC_A")
      (description "16V 100nF X5R ±10% 0201 Multilayer Ceramic Capacitors MLCC - SMD/SMT ROHS")
      (fields (field (name "TOLERANCE") "10%") (field (name "Comment") "CC0201KRX5R7BB104"))
      (libsource (lib "MIGUEL ANGEL ALVAREZ GUZMAN") (part "11868f565c42a9108669ba33697ecf6"))
    )
    (comp (ref "C69")
      (value "100nF")
      (footprint "FP-CC0201-BA-IPC_A")
      (description "16V 100nF X5R ±10% 0201 Multilayer Ceramic Capacitors MLCC - SMD/SMT ROHS")
      (fields (field (name "TOLERANCE") "10%") (field (name "Comment") "CC0201KRX5R7BB104"))
      (libsource (lib "MIGUEL ANGEL ALVAREZ GUZMAN") (part "11868f565c42a9108669ba33697ecf6"))
    )
    (comp (ref "C70")
      (value "100nF")
      (footprint "FP-CC0201-BA-IPC_A")
      (description "16V 100nF X5R ±10% 0201 Multilayer Ceramic Capacitors MLCC - SMD/SMT ROHS")
      (fields (field (name "TOLERANCE") "10%") (field (name "Comment") "CC0201KRX5R7BB104"))
      (libsource (lib "MIGUEL ANGEL ALVAREZ GUZMAN") (part "11868f565c42a9108669ba33697ecf6"))
    )
    (comp (ref "C71")
      (value "22µF")
      (footprint "FP-GRM186-0_2-IPC_A")
      (description "6.3V 22uF X5R ±20% 0603 Multilayer Ceramic Capacitors MLCC - SMD/SMT ROHS")
      (fields (field (name "TOLERANCE") "20%") (field (name "Comment") "GRM186R60J226ME15D"))
      (libsource (lib "MIGUEL ANGEL ALVAREZ GUZMAN") (part "02cd4be3c70576c341d710602a673aa"))
    )
    (comp (ref "C72")
      (value "22µF")
      (footprint "FP-GRM186-0_2-IPC_A")
      (description "6.3V 22uF X5R ±20% 0603 Multilayer Ceramic Capacitors MLCC - SMD/SMT ROHS")
      (fields (field (name "TOLERANCE") "20%") (field (name "Comment") "GRM186R60J226ME15D"))
      (libsource (lib "MIGUEL ANGEL ALVAREZ GUZMAN") (part "02cd4be3c70576c341d710602a673aa"))
    )
    (comp (ref "C73")
      (value "10µF")
      (footprint "FP-GRM155-0_2-0_1-IPC_C")
      (description "CAP CER 10UF 4V X5R 0402 / 10 µF ±20% 4V Ceramic Capacitor X5R 0402 (1005 Metric)")
      (fields (field (name "TOLERANCE") "20%") (field (name "Comment") "GRM155R60G106ME47D"))
      (libsource (lib "MIGUEL ANGEL ALVAREZ GUZMAN") (part "b4654b650e69147ec39a6b967a45e02"))
    )
    (comp (ref "C74")
      (value "100nF")
      (footprint "FP-CC0201-BA-IPC_A")
      (description "16V 100nF X5R ±10% 0201 Multilayer Ceramic Capacitors MLCC - SMD/SMT ROHS")
      (fields (field (name "TOLERANCE") "10%") (field (name "Comment") "CC0201KRX5R7BB104"))
      (libsource (lib "MIGUEL ANGEL ALVAREZ GUZMAN") (part "11868f565c42a9108669ba33697ecf6"))
    )
    (comp (ref "C75")
      (value "100nF")
      (footprint "FP-CC0201-BA-IPC_A")
      (description "16V 100nF X5R ±10% 0201 Multilayer Ceramic Capacitors MLCC - SMD/SMT ROHS")
      (fields (field (name "TOLERANCE") "10%") (field (name "Comment") "CC0201KRX5R7BB104"))
      (libsource (lib "MIGUEL ANGEL ALVAREZ GUZMAN") (part "11868f565c42a9108669ba33697ecf6"))
    )
    (comp (ref "C76")
      (value "100nF")
      (footprint "FP-CC0201-BA-IPC_A")
      (description "16V 100nF X5R ±10% 0201 Multilayer Ceramic Capacitors MLCC - SMD/SMT ROHS")
      (fields (field (name "TOLERANCE") "10%") (field (name "Comment") "CC0201KRX5R7BB104"))
      (libsource (lib "MIGUEL ANGEL ALVAREZ GUZMAN") (part "11868f565c42a9108669ba33697ecf6"))
    )
    (comp (ref "C77")
      (value "100nF")
      (footprint "FP-CC0201-BA-IPC_A")
      (description "16V 100nF X5R ±10% 0201 Multilayer Ceramic Capacitors MLCC - SMD/SMT ROHS")
      (fields (field (name "TOLERANCE") "10%") (field (name "Comment") "CC0201KRX5R7BB104"))
      (libsource (lib "MIGUEL ANGEL ALVAREZ GUZMAN") (part "11868f565c42a9108669ba33697ecf6"))
    )
    (comp (ref "C78")
      (value "100nF")
      (footprint "FP-CC0201-BA-IPC_A")
      (description "16V 100nF X5R ±10% 0201 Multilayer Ceramic Capacitors MLCC - SMD/SMT ROHS")
      (fields (field (name "TOLERANCE") "10%") (field (name "Comment") "CC0201KRX5R7BB104"))
      (libsource (lib "MIGUEL ANGEL ALVAREZ GUZMAN") (part "11868f565c42a9108669ba33697ecf6"))
    )
    (comp (ref "C79")
      (value "100nF")
      (footprint "FP-CC0201-BA-IPC_A")
      (description "16V 100nF X5R ±10% 0201 Multilayer Ceramic Capacitors MLCC - SMD/SMT ROHS")
      (fields (field (name "TOLERANCE") "10%") (field (name "Comment") "CC0201KRX5R7BB104"))
      (libsource (lib "MIGUEL ANGEL ALVAREZ GUZMAN") (part "11868f565c42a9108669ba33697ecf6"))
    )
    (comp (ref "C80")
      (value "1µF")
      (footprint "CAPC0603X33X15LL03T05")
      (description "10V 1uF X5R ±20% 0201 Multilayer Ceramic Capacitors MLCC - SMD/SMT ROHS")
      (fields (field (name "TOLERANCE") "20%") (field (name "Comment") "0201ZD105MAT2A"))
      (libsource (lib "MIGUEL ANGEL ALVAREZ GUZMAN") (part "CAP"))
    )
    (comp (ref "C81")
      (value "22µF")
      (footprint "FP-GRM186-0_2-IPC_A")
      (description "6.3V 22uF X5R ±20% 0603 Multilayer Ceramic Capacitors MLCC - SMD/SMT ROHS")
      (fields (field (name "TOLERANCE") "20%") (field (name "Comment") "GRM186R60J226ME15D"))
      (libsource (lib "MIGUEL ANGEL ALVAREZ GUZMAN") (part "02cd4be3c70576c341d710602a673aa"))
    )
    (comp (ref "C82")
      (value "22µF")
      (footprint "FP-GRM186-0_2-IPC_A")
      (description "6.3V 22uF X5R ±20% 0603 Multilayer Ceramic Capacitors MLCC - SMD/SMT ROHS")
      (fields (field (name "TOLERANCE") "20%") (field (name "Comment") "GRM186R60J226ME15D"))
      (libsource (lib "MIGUEL ANGEL ALVAREZ GUZMAN") (part "02cd4be3c70576c341d710602a673aa"))
    )
    (comp (ref "C83")
      (value "10µF")
      (footprint "FP-GRM155-0_2-0_1-IPC_C")
      (description "CAP CER 10UF 4V X5R 0402 / 10 µF ±20% 4V Ceramic Capacitor X5R 0402 (1005 Metric)")
      (fields (field (name "TOLERANCE") "20%") (field (name "Comment") "GRM155R60G106ME47D"))
      (libsource (lib "MIGUEL ANGEL ALVAREZ GUZMAN") (part "b4654b650e69147ec39a6b967a45e02"))
    )
    (comp (ref "C84")
      (value "100nF")
      (footprint "FP-CC0201-BA-IPC_A")
      (description "16V 100nF X5R ±10% 0201 Multilayer Ceramic Capacitors MLCC - SMD/SMT ROHS")
      (fields (field (name "TOLERANCE") "10%") (field (name "Comment") "CC0201KRX5R7BB104"))
      (libsource (lib "MIGUEL ANGEL ALVAREZ GUZMAN") (part "11868f565c42a9108669ba33697ecf6"))
    )
    (comp (ref "C85")
      (value "100nF")
      (footprint "FP-CC0201-BA-IPC_A")
      (description "16V 100nF X5R ±10% 0201 Multilayer Ceramic Capacitors MLCC - SMD/SMT ROHS")
      (fields (field (name "TOLERANCE") "10%") (field (name "Comment") "CC0201KRX5R7BB104"))
      (libsource (lib "MIGUEL ANGEL ALVAREZ GUZMAN") (part "11868f565c42a9108669ba33697ecf6"))
    )
    (comp (ref "C86")
      (value "100nF")
      (footprint "FP-CC0201-BA-IPC_A")
      (description "16V 100nF X5R ±10% 0201 Multilayer Ceramic Capacitors MLCC - SMD/SMT ROHS")
      (fields (field (name "TOLERANCE") "10%") (field (name "Comment") "CC0201KRX5R7BB104"))
      (libsource (lib "MIGUEL ANGEL ALVAREZ GUZMAN") (part "11868f565c42a9108669ba33697ecf6"))
    )
    (comp (ref "C87")
      (value "100nF")
      (footprint "FP-CC0201-BA-IPC_A")
      (description "16V 100nF X5R ±10% 0201 Multilayer Ceramic Capacitors MLCC - SMD/SMT ROHS")
      (fields (field (name "TOLERANCE") "10%") (field (name "Comment") "CC0201KRX5R7BB104"))
      (libsource (lib "MIGUEL ANGEL ALVAREZ GUZMAN") (part "11868f565c42a9108669ba33697ecf6"))
    )
    (comp (ref "C88")
      (value "100nF")
      (footprint "FP-CC0201-BA-IPC_A")
      (description "16V 100nF X5R ±10% 0201 Multilayer Ceramic Capacitors MLCC - SMD/SMT ROHS")
      (fields (field (name "TOLERANCE") "10%") (field (name "Comment") "CC0201KRX5R7BB104"))
      (libsource (lib "MIGUEL ANGEL ALVAREZ GUZMAN") (part "11868f565c42a9108669ba33697ecf6"))
    )
    (comp (ref "C89")
      (value "22µF")
      (footprint "FP-GRM186-0_2-IPC_A")
      (description "6.3V 22uF X5R ±20% 0603 Multilayer Ceramic Capacitors MLCC - SMD/SMT ROHS")
      (fields (field (name "TOLERANCE") "20%") (field (name "Comment") "GRM186R60J226ME15D"))
      (libsource (lib "MIGUEL ANGEL ALVAREZ GUZMAN") (part "02cd4be3c70576c341d710602a673aa"))
    )
    (comp (ref "C90")
      (value "22µF")
      (footprint "FP-GRM186-0_2-IPC_A")
      (description "6.3V 22uF X5R ±20% 0603 Multilayer Ceramic Capacitors MLCC - SMD/SMT ROHS")
      (fields (field (name "TOLERANCE") "20%") (field (name "Comment") "GRM186R60J226ME15D"))
      (libsource (lib "MIGUEL ANGEL ALVAREZ GUZMAN") (part "02cd4be3c70576c341d710602a673aa"))
    )
    (comp (ref "C91")
      (value "10µF")
      (footprint "FP-GRM155-0_2-0_1-IPC_C")
      (description "CAP CER 10UF 4V X5R 0402 / 10 µF ±20% 4V Ceramic Capacitor X5R 0402 (1005 Metric)")
      (fields (field (name "TOLERANCE") "20%") (field (name "Comment") "GRM155R60G106ME47D"))
      (libsource (lib "MIGUEL ANGEL ALVAREZ GUZMAN") (part "b4654b650e69147ec39a6b967a45e02"))
    )
    (comp (ref "C92")
      (value "100nF")
      (footprint "FP-CC0201-BA-IPC_A")
      (description "16V 100nF X5R ±10% 0201 Multilayer Ceramic Capacitors MLCC - SMD/SMT ROHS")
      (fields (field (name "TOLERANCE") "10%") (field (name "Comment") "CC0201KRX5R7BB104"))
      (libsource (lib "MIGUEL ANGEL ALVAREZ GUZMAN") (part "11868f565c42a9108669ba33697ecf6"))
    )
    (comp (ref "C93")
      (value "100nF")
      (footprint "FP-CC0201-BA-IPC_A")
      (description "16V 100nF X5R ±10% 0201 Multilayer Ceramic Capacitors MLCC - SMD/SMT ROHS")
      (fields (field (name "TOLERANCE") "10%") (field (name "Comment") "CC0201KRX5R7BB104"))
      (libsource (lib "MIGUEL ANGEL ALVAREZ GUZMAN") (part "11868f565c42a9108669ba33697ecf6"))
    )
    (comp (ref "C94")
      (value "100nF")
      (footprint "FP-CC0201-BA-IPC_A")
      (description "16V 100nF X5R ±10% 0201 Multilayer Ceramic Capacitors MLCC - SMD/SMT ROHS")
      (fields (field (name "TOLERANCE") "10%") (field (name "Comment") "CC0201KRX5R7BB104"))
      (libsource (lib "MIGUEL ANGEL ALVAREZ GUZMAN") (part "11868f565c42a9108669ba33697ecf6"))
    )
    (comp (ref "C95")
      (value "100nF")
      (footprint "FP-CC0201-BA-IPC_A")
      (description "16V 100nF X5R ±10% 0201 Multilayer Ceramic Capacitors MLCC - SMD/SMT ROHS")
      (fields (field (name "TOLERANCE") "10%") (field (name "Comment") "CC0201KRX5R7BB104"))
      (libsource (lib "MIGUEL ANGEL ALVAREZ GUZMAN") (part "11868f565c42a9108669ba33697ecf6"))
    )
    (comp (ref "C96")
      (value "100nF")
      (footprint "FP-CC0201-BA-IPC_A")
      (description "16V 100nF X5R ±10% 0201 Multilayer Ceramic Capacitors MLCC - SMD/SMT ROHS")
      (fields (field (name "TOLERANCE") "10%") (field (name "Comment") "CC0201KRX5R7BB104"))
      (libsource (lib "MIGUEL ANGEL ALVAREZ GUZMAN") (part "11868f565c42a9108669ba33697ecf6"))
    )
    (comp (ref "C97")
      (value "22µF")
      (footprint "FP-GRM186-0_2-IPC_A")
      (description "6.3V 22uF X5R ±20% 0603 Multilayer Ceramic Capacitors MLCC - SMD/SMT ROHS")
      (fields (field (name "TOLERANCE") "20%") (field (name "Comment") "GRM186R60J226ME15D"))
      (libsource (lib "MIGUEL ANGEL ALVAREZ GUZMAN") (part "02cd4be3c70576c341d710602a673aa"))
    )
    (comp (ref "C98")
      (value "22µF")
      (footprint "FP-GRM186-0_2-IPC_A")
      (description "6.3V 22uF X5R ±20% 0603 Multilayer Ceramic Capacitors MLCC - SMD/SMT ROHS")
      (fields (field (name "TOLERANCE") "20%") (field (name "Comment") "GRM186R60J226ME15D"))
      (libsource (lib "MIGUEL ANGEL ALVAREZ GUZMAN") (part "02cd4be3c70576c341d710602a673aa"))
    )
    (comp (ref "C99")
      (value "10µF")
      (footprint "FP-GRM155-0_2-0_1-IPC_C")
      (description "CAP CER 10UF 4V X5R 0402 / 10 µF ±20% 4V Ceramic Capacitor X5R 0402 (1005 Metric)")
      (fields (field (name "TOLERANCE") "20%") (field (name "Comment") "GRM155R60G106ME47D"))
      (libsource (lib "MIGUEL ANGEL ALVAREZ GUZMAN") (part "b4654b650e69147ec39a6b967a45e02"))
    )
    (comp (ref "C100")
      (value "100nF")
      (footprint "FP-CC0201-BA-IPC_A")
      (description "16V 100nF X5R ±10% 0201 Multilayer Ceramic Capacitors MLCC - SMD/SMT ROHS")
      (fields (field (name "TOLERANCE") "10%") (field (name "Comment") "CC0201KRX5R7BB104"))
      (libsource (lib "MIGUEL ANGEL ALVAREZ GUZMAN") (part "11868f565c42a9108669ba33697ecf6"))
    )
    (comp (ref "C101")
      (value "100nF")
      (footprint "FP-CC0201-BA-IPC_A")
      (description "16V 100nF X5R ±10% 0201 Multilayer Ceramic Capacitors MLCC - SMD/SMT ROHS")
      (fields (field (name "TOLERANCE") "10%") (field (name "Comment") "CC0201KRX5R7BB104"))
      (libsource (lib "MIGUEL ANGEL ALVAREZ GUZMAN") (part "11868f565c42a9108669ba33697ecf6"))
    )
    (comp (ref "C102")
      (value "100nF")
      (footprint "FP-CC0201-BA-IPC_A")
      (description "16V 100nF X5R ±10% 0201 Multilayer Ceramic Capacitors MLCC - SMD/SMT ROHS")
      (fields (field (name "TOLERANCE") "10%") (field (name "Comment") "CC0201KRX5R7BB104"))
      (libsource (lib "MIGUEL ANGEL ALVAREZ GUZMAN") (part "11868f565c42a9108669ba33697ecf6"))
    )
    (comp (ref "C103")
      (value "100nF")
      (footprint "FP-CC0201-BA-IPC_A")
      (description "16V 100nF X5R ±10% 0201 Multilayer Ceramic Capacitors MLCC - SMD/SMT ROHS")
      (fields (field (name "TOLERANCE") "10%") (field (name "Comment") "CC0201KRX5R7BB104"))
      (libsource (lib "MIGUEL ANGEL ALVAREZ GUZMAN") (part "11868f565c42a9108669ba33697ecf6"))
    )
    (comp (ref "C104")
      (value "100nF")
      (footprint "FP-CC0201-BA-IPC_A")
      (description "16V 100nF X5R ±10% 0201 Multilayer Ceramic Capacitors MLCC - SMD/SMT ROHS")
      (fields (field (name "TOLERANCE") "10%") (field (name "Comment") "CC0201KRX5R7BB104"))
      (libsource (lib "MIGUEL ANGEL ALVAREZ GUZMAN") (part "11868f565c42a9108669ba33697ecf6"))
    )
    (comp (ref "C105")
      (value "22µF")
      (footprint "FP-GRM186-0_2-IPC_A")
      (description "6.3V 22uF X5R ±20% 0603 Multilayer Ceramic Capacitors MLCC - SMD/SMT ROHS")
      (fields (field (name "TOLERANCE") "20%") (field (name "Comment") "GRM186R60J226ME15D"))
      (libsource (lib "MIGUEL ANGEL ALVAREZ GUZMAN") (part "02cd4be3c70576c341d710602a673aa"))
    )
    (comp (ref "C106")
      (value "22µF")
      (footprint "FP-GRM186-0_2-IPC_A")
      (description "6.3V 22uF X5R ±20% 0603 Multilayer Ceramic Capacitors MLCC - SMD/SMT ROHS")
      (fields (field (name "TOLERANCE") "20%") (field (name "Comment") "GRM186R60J226ME15D"))
      (libsource (lib "MIGUEL ANGEL ALVAREZ GUZMAN") (part "02cd4be3c70576c341d710602a673aa"))
    )
    (comp (ref "C107")
      (value "10µF")
      (footprint "FP-GRM155-0_2-0_1-IPC_C")
      (description "CAP CER 10UF 4V X5R 0402 / 10 µF ±20% 4V Ceramic Capacitor X5R 0402 (1005 Metric)")
      (fields (field (name "TOLERANCE") "20%") (field (name "Comment") "GRM155R60G106ME47D"))
      (libsource (lib "MIGUEL ANGEL ALVAREZ GUZMAN") (part "b4654b650e69147ec39a6b967a45e02"))
    )
    (comp (ref "C108")
      (value "100nF")
      (footprint "FP-CC0201-BA-IPC_A")
      (description "16V 100nF X5R ±10% 0201 Multilayer Ceramic Capacitors MLCC - SMD/SMT ROHS")
      (fields (field (name "TOLERANCE") "10%") (field (name "Comment") "CC0201KRX5R7BB104"))
      (libsource (lib "MIGUEL ANGEL ALVAREZ GUZMAN") (part "11868f565c42a9108669ba33697ecf6"))
    )
    (comp (ref "C109")
      (value "100nF")
      (footprint "FP-CC0201-BA-IPC_A")
      (description "16V 100nF X5R ±10% 0201 Multilayer Ceramic Capacitors MLCC - SMD/SMT ROHS")
      (fields (field (name "TOLERANCE") "10%") (field (name "Comment") "CC0201KRX5R7BB104"))
      (libsource (lib "MIGUEL ANGEL ALVAREZ GUZMAN") (part "11868f565c42a9108669ba33697ecf6"))
    )
    (comp (ref "C110")
      (value "100nF")
      (footprint "FP-CC0201-BA-IPC_A")
      (description "16V 100nF X5R ±10% 0201 Multilayer Ceramic Capacitors MLCC - SMD/SMT ROHS")
      (fields (field (name "TOLERANCE") "10%") (field (name "Comment") "CC0201KRX5R7BB104"))
      (libsource (lib "MIGUEL ANGEL ALVAREZ GUZMAN") (part "11868f565c42a9108669ba33697ecf6"))
    )
    (comp (ref "C111")
      (value "100nF")
      (footprint "FP-CC0201-BA-IPC_A")
      (description "16V 100nF X5R ±10% 0201 Multilayer Ceramic Capacitors MLCC - SMD/SMT ROHS")
      (fields (field (name "TOLERANCE") "10%") (field (name "Comment") "CC0201KRX5R7BB104"))
      (libsource (lib "MIGUEL ANGEL ALVAREZ GUZMAN") (part "11868f565c42a9108669ba33697ecf6"))
    )
    (comp (ref "C112")
      (value "100nF")
      (footprint "FP-CC0201-BA-IPC_A")
      (description "16V 100nF X5R ±10% 0201 Multilayer Ceramic Capacitors MLCC - SMD/SMT ROHS")
      (fields (field (name "TOLERANCE") "10%") (field (name "Comment") "CC0201KRX5R7BB104"))
      (libsource (lib "MIGUEL ANGEL ALVAREZ GUZMAN") (part "11868f565c42a9108669ba33697ecf6"))
    )
    (comp (ref "C113")
      (value "22µF")
      (footprint "FP-GRM186-0_2-IPC_A")
      (description "6.3V 22uF X5R ±20% 0603 Multilayer Ceramic Capacitors MLCC - SMD/SMT ROHS")
      (fields (field (name "TOLERANCE") "20%") (field (name "Comment") "GRM186R60J226ME15D"))
      (libsource (lib "MIGUEL ANGEL ALVAREZ GUZMAN") (part "02cd4be3c70576c341d710602a673aa"))
    )
    (comp (ref "C114")
      (value "22µF")
      (footprint "FP-GRM186-0_2-IPC_A")
      (description "6.3V 22uF X5R ±20% 0603 Multilayer Ceramic Capacitors MLCC - SMD/SMT ROHS")
      (fields (field (name "TOLERANCE") "20%") (field (name "Comment") "GRM186R60J226ME15D"))
      (libsource (lib "MIGUEL ANGEL ALVAREZ GUZMAN") (part "02cd4be3c70576c341d710602a673aa"))
    )
    (comp (ref "C115")
      (value "10µF")
      (footprint "FP-GRM155-0_2-0_1-IPC_C")
      (description "CAP CER 10UF 4V X5R 0402 / 10 µF ±20% 4V Ceramic Capacitor X5R 0402 (1005 Metric)")
      (fields (field (name "TOLERANCE") "20%") (field (name "Comment") "GRM155R60G106ME47D"))
      (libsource (lib "MIGUEL ANGEL ALVAREZ GUZMAN") (part "b4654b650e69147ec39a6b967a45e02"))
    )
    (comp (ref "C116")
      (value "100nF")
      (footprint "FP-CC0201-BA-IPC_A")
      (description "16V 100nF X5R ±10% 0201 Multilayer Ceramic Capacitors MLCC - SMD/SMT ROHS")
      (fields (field (name "TOLERANCE") "10%") (field (name "Comment") "CC0201KRX5R7BB104"))
      (libsource (lib "MIGUEL ANGEL ALVAREZ GUZMAN") (part "11868f565c42a9108669ba33697ecf6"))
    )
    (comp (ref "C117")
      (value "100nF")
      (footprint "FP-CC0201-BA-IPC_A")
      (description "16V 100nF X5R ±10% 0201 Multilayer Ceramic Capacitors MLCC - SMD/SMT ROHS")
      (fields (field (name "TOLERANCE") "10%") (field (name "Comment") "CC0201KRX5R7BB104"))
      (libsource (lib "MIGUEL ANGEL ALVAREZ GUZMAN") (part "11868f565c42a9108669ba33697ecf6"))
    )
    (comp (ref "C118")
      (value "100nF")
      (footprint "FP-CC0201-BA-IPC_A")
      (description "16V 100nF X5R ±10% 0201 Multilayer Ceramic Capacitors MLCC - SMD/SMT ROHS")
      (fields (field (name "TOLERANCE") "10%") (field (name "Comment") "CC0201KRX5R7BB104"))
      (libsource (lib "MIGUEL ANGEL ALVAREZ GUZMAN") (part "11868f565c42a9108669ba33697ecf6"))
    )
    (comp (ref "C119")
      (value "100nF")
      (footprint "FP-CC0201-BA-IPC_A")
      (description "16V 100nF X5R ±10% 0201 Multilayer Ceramic Capacitors MLCC - SMD/SMT ROHS")
      (fields (field (name "TOLERANCE") "10%") (field (name "Comment") "CC0201KRX5R7BB104"))
      (libsource (lib "MIGUEL ANGEL ALVAREZ GUZMAN") (part "11868f565c42a9108669ba33697ecf6"))
    )
    (comp (ref "C120")
      (value "100nF")
      (footprint "FP-CC0201-BA-IPC_A")
      (description "16V 100nF X5R ±10% 0201 Multilayer Ceramic Capacitors MLCC - SMD/SMT ROHS")
      (fields (field (name "TOLERANCE") "10%") (field (name "Comment") "CC0201KRX5R7BB104"))
      (libsource (lib "MIGUEL ANGEL ALVAREZ GUZMAN") (part "11868f565c42a9108669ba33697ecf6"))
    )
    (comp (ref "C121")
      (value "2.2µF")
      (footprint "FP-CC0201-BA-IPC_A")
      (description "10V 2.2uF X5R ±20% 0201 Multilayer Ceramic Capacitors MLCC - SMD/SMT ROHS")
      (fields (field (name "Comment") "CC0201MRX5R6BB225"))
      (libsource (lib "MIGUEL ANGEL ALVAREZ GUZMAN") (part "11868f565c42a9108669ba33697ecf6"))
    )
    (comp (ref "C122")
      (value "100nF")
      (footprint "FP-CC0201-BA-IPC_A")
      (description "16V 100nF X5R ±10% 0201 Multilayer Ceramic Capacitors MLCC - SMD/SMT ROHS")
      (fields (field (name "TOLERANCE") "10%") (field (name "Comment") "CC0201KRX5R7BB104"))
      (libsource (lib "MIGUEL ANGEL ALVAREZ GUZMAN") (part "11868f565c42a9108669ba33697ecf6"))
    )
    (comp (ref "C123")
      (value "100nF")
      (footprint "FP-CC0201-BA-IPC_A")
      (description "16V 100nF X5R ±10% 0201 Multilayer Ceramic Capacitors MLCC - SMD/SMT ROHS")
      (fields (field (name "TOLERANCE") "10%") (field (name "Comment") "CC0201KRX5R7BB104"))
      (libsource (lib "MIGUEL ANGEL ALVAREZ GUZMAN") (part "11868f565c42a9108669ba33697ecf6"))
    )
    (comp (ref "C124")
      (value "10µF")
      (footprint "FP-GRM155-0_2-0_1-IPC_C")
      (description "CAP CER 10UF 4V X5R 0402 / 10 µF ±20% 4V Ceramic Capacitor X5R 0402 (1005 Metric)")
      (fields (field (name "TOLERANCE") "20%") (field (name "Comment") "GRM155R60G106ME47D"))
      (libsource (lib "MIGUEL ANGEL ALVAREZ GUZMAN") (part "b4654b650e69147ec39a6b967a45e02"))
    )
    (comp (ref "C125")
      (value "100nF")
      (footprint "FP-CC0201-BA-IPC_A")
      (description "16V 100nF X5R ±10% 0201 Multilayer Ceramic Capacitors MLCC - SMD/SMT ROHS")
      (fields (field (name "TOLERANCE") "10%") (field (name "Comment") "CC0201KRX5R7BB104"))
      (libsource (lib "MIGUEL ANGEL ALVAREZ GUZMAN") (part "11868f565c42a9108669ba33697ecf6"))
    )
    (comp (ref "C126")
      (value "22pF")
      (footprint "FP-GRM033-0_03-MFG")
      (description "25V 22pF C0G ±1% 0201 Multilayer Ceramic Capacitors MLCC - SMD/SMT ROHS")
      (fields (field (name "TOLERANCE") "1%") (field (name "Comment") "GRM0335C1E220FA01D"))
      (libsource (lib "MIGUEL ANGEL ALVAREZ GUZMAN") (part "b4654b650e69147ec39a6b967a45e02"))
    )
    (comp (ref "C127")
      (value "22pF")
      (footprint "FP-GRM033-0_03-MFG")
      (description "25V 22pF C0G ±1% 0201 Multilayer Ceramic Capacitors MLCC - SMD/SMT ROHS")
      (fields (field (name "TOLERANCE") "1%") (field (name "Comment") "GRM0335C1E220FA01D"))
      (libsource (lib "MIGUEL ANGEL ALVAREZ GUZMAN") (part "b4654b650e69147ec39a6b967a45e02"))
    )
    (comp (ref "C128")
      (value "100nF")
      (footprint "CAPC0402(1005)60_L")
      (description "Chip Capacitor, 100nF +/-20%, 50V, 0402, Thickness 0.6 mm")
      (fields (field (name "TOLERANCE") "10%") (field (name "Comment") "Capacitor 100nF +/-20% 50V 0402"))
      (libsource (lib "MIGUEL ANGEL ALVAREZ GUZMAN") (part "CAP-NP-2"))
    )
    (comp (ref "C129")
      (value "10µF")
      (footprint "CAPC0402(1005)60_L")
      (description "Chip Capacitor, 10µF +/-40%, 6.3V, 0402, Thickness 0.6 mm")
      (fields (field (name "TOLERANCE") "10%") (field (name "Comment") "Capacitor 10µF +/-40% 6.3V 0402"))
      (libsource (lib "MIGUEL ANGEL ALVAREZ GUZMAN") (part "CAP-NP-2"))
    )
    (comp (ref "C130")
      (value "4.7µF")
      (footprint "FP-GRM035-0_09-IPC_B")
      (description "0201 4.7 uF 6.3 V ±10 % Tolerance X5R SMT Multilayer Ceramic Chip Capacitor")
      (fields (field (name "TOLERANCE") "20%") (field (name "Comment") "GRM035R60J475ME15J"))
      (libsource (lib "MIGUEL ANGEL ALVAREZ GUZMAN") (part "02cd4be3c70576c341d710602a673aa"))
    )
    (comp (ref "C131")
      (value "1µF")
      (footprint "CAPC0603X33X15LL03T05")
      (description "10V 1uF X5R ±20% 0201 Multilayer Ceramic Capacitors MLCC - SMD/SMT ROHS")
      (fields (field (name "TOLERANCE") "20%") (field (name "Comment") "0201ZD105MAT2A"))
      (libsource (lib "MIGUEL ANGEL ALVAREZ GUZMAN") (part "CAP"))
    )
    (comp (ref "C132")
      (value "100nF")
      (footprint "FP-CC0201-BA-IPC_A")
      (description "16V 100nF X5R ±10% 0201 Multilayer Ceramic Capacitors MLCC - SMD/SMT ROHS")
      (fields (field (name "TOLERANCE") "10%") (field (name "Comment") "CC0201KRX5R7BB104"))
      (libsource (lib "MIGUEL ANGEL ALVAREZ GUZMAN") (part "11868f565c42a9108669ba33697ecf6"))
    )
    (comp (ref "C133")
      (value "100nF")
      (footprint "FP-CC0201-BA-IPC_A")
      (description "16V 100nF X5R ±10% 0201 Multilayer Ceramic Capacitors MLCC - SMD/SMT ROHS")
      (fields (field (name "TOLERANCE") "10%") (field (name "Comment") "CC0201KRX5R7BB104"))
      (libsource (lib "MIGUEL ANGEL ALVAREZ GUZMAN") (part "11868f565c42a9108669ba33697ecf6"))
    )
    (comp (ref "C134")
      (value "10µF")
      (footprint "CAPC0603(1608)100_L")
      (description "Chip Capacitor, 10µF +/-20%, 10V, 0603, Thickness 1 mm")
      (fields (field (name "TOLERANCE") "10%") (field (name "Comment") "Capacitor 10µF +/-20% 10V 0603"))
      (libsource (lib "MIGUEL ANGEL ALVAREZ GUZMAN") (part "CAP-NP-2"))
    )
    (comp (ref "C135")
      (value "10µF")
      (footprint "CAPC0603(1608)100_L")
      (description "Chip Capacitor, 10µF +/-20%, 10V, 0603, Thickness 1 mm")
      (fields (field (name "TOLERANCE") "10%") (field (name "Comment") "Capacitor 10µF +/-20% 10V 0603"))
      (libsource (lib "MIGUEL ANGEL ALVAREZ GUZMAN") (part "CAP-NP-2"))
    )
    (comp (ref "C136")
      (value "10µF")
      (footprint "CAPC0603(1608)100_L")
      (description "Chip Capacitor, 10µF +/-20%, 10V, 0603, Thickness 1 mm")
      (fields (field (name "TOLERANCE") "10%") (field (name "Comment") "Capacitor 10µF +/-20% 10V 0603"))
      (libsource (lib "MIGUEL ANGEL ALVAREZ GUZMAN") (part "CAP-NP-2"))
    )
    (comp (ref "C137")
      (value "100nF")
      (footprint "CAPC0402(1005)60_L")
      (description "Chip Capacitor, 100nF +/-20%, 50V, 0402, Thickness 0.6 mm")
      (fields (field (name "TOLERANCE") "10%") (field (name "Comment") "Capacitor 100nF +/-20% 50V 0402"))
      (libsource (lib "MIGUEL ANGEL ALVAREZ GUZMAN") (part "CAP-NP-2"))
    )
    (comp (ref "C138")
      (value "4.7µF")
      (footprint "FP-GRM035-0_09-IPC_B")
      (description "0201 4.7 uF 6.3 V ±10 % Tolerance X5R SMT Multilayer Ceramic Chip Capacitor")
      (fields (field (name "TOLERANCE") "20%") (field (name "Comment") "GRM035R60J475ME15J"))
      (libsource (lib "MIGUEL ANGEL ALVAREZ GUZMAN") (part "02cd4be3c70576c341d710602a673aa"))
    )
    (comp (ref "C139")
      (value "220pF")
      (footprint "CAPC0603X33X15LL03T05")
      (description "0201 220 pF 16 V ±10 % Tolerance X7R Surface Mount Multilayer Ceramic Capacitor")
      (fields (field (name "TOLERANCE") "10%") (field (name "Comment") "0201YC221KAT2A"))
      (libsource (lib "MIGUEL ANGEL ALVAREZ GUZMAN") (part "CAP"))
    )
    (comp (ref "C140")
      (value "220pF")
      (footprint "CAPC0603X33X15LL03T05")
      (description "0201 220 pF 16 V ±10 % Tolerance X7R Surface Mount Multilayer Ceramic Capacitor")
      (fields (field (name "TOLERANCE") "10%") (field (name "Comment") "0201YC221KAT2A"))
      (libsource (lib "MIGUEL ANGEL ALVAREZ GUZMAN") (part "CAP"))
    )
    (comp (ref "C141")
      (value "10µF")
      (footprint "CAPC0402(1005)60_L")
      (description "Chip Capacitor, 10µF +/-40%, 6.3V, 0402, Thickness 0.6 mm")
      (fields (field (name "TOLERANCE") "10%") (field (name "Comment") "Capacitor 10µF +/-40% 6.3V 0402"))
      (libsource (lib "MIGUEL ANGEL ALVAREZ GUZMAN") (part "CAP-NP-2"))
    )
    (comp (ref "C142")
      (value "100nF")
      (footprint "FP-CC0201-BA-IPC_A")
      (description "16V 100nF X5R ±10% 0201 Multilayer Ceramic Capacitors MLCC - SMD/SMT ROHS")
      (fields (field (name "TOLERANCE") "10%") (field (name "Comment") "CC0201KRX5R7BB104"))
      (libsource (lib "MIGUEL ANGEL ALVAREZ GUZMAN") (part "11868f565c42a9108669ba33697ecf6"))
    )
    (comp (ref "C143")
      (value "10µF")
      (footprint "CAPC0402(1005)60_L")
      (description "Chip Capacitor, 10µF +/-40%, 6.3V, 0402, Thickness 0.6 mm")
      (fields (field (name "TOLERANCE") "10%") (field (name "Comment") "Capacitor 10µF +/-40% 6.3V 0402"))
      (libsource (lib "MIGUEL ANGEL ALVAREZ GUZMAN") (part "CAP-NP-2"))
    )
    (comp (ref "C144")
      (value "100nF")
      (footprint "FP-CC0201-BA-IPC_A")
      (description "16V 100nF X5R ±10% 0201 Multilayer Ceramic Capacitors MLCC - SMD/SMT ROHS")
      (fields (field (name "TOLERANCE") "10%") (field (name "Comment") "CC0201KRX5R7BB104"))
      (libsource (lib "MIGUEL ANGEL ALVAREZ GUZMAN") (part "11868f565c42a9108669ba33697ecf6"))
    )
    (comp (ref "C145")
      (value "10µF")
      (footprint "CAPC0603(1608)100_L")
      (description "Chip Capacitor, 10µF +/-20%, 10V, 0603, Thickness 1 mm")
      (fields (field (name "TOLERANCE") "10%") (field (name "Comment") "Capacitor 10µF +/-20% 10V 0603"))
      (libsource (lib "MIGUEL ANGEL ALVAREZ GUZMAN") (part "CAP-NP-2"))
    )
    (comp (ref "C146")
      (value "10µF")
      (footprint "CAPC0603(1608)100_L")
      (description "Chip Capacitor, 10µF +/-20%, 10V, 0603, Thickness 1 mm")
      (fields (field (name "TOLERANCE") "10%") (field (name "Comment") "Capacitor 10µF +/-20% 10V 0603"))
      (libsource (lib "MIGUEL ANGEL ALVAREZ GUZMAN") (part "CAP-NP-2"))
    )
    (comp (ref "C147")
      (value "100nF")
      (footprint "CAPC1005X56X25LL10T15")
      (description "Chip Capacitor, 0.1 uF, +/- 5%, 16 V, 0402 (1005 Metric)")
      (fields (field (name "TOLERANCE") "5%") (field (name "Comment") "Capacitor 0.1 uF +/- 5% 16 V 0402"))
      (libsource (lib "MIGUEL ANGEL ALVAREZ GUZMAN") (part "CAP-NP-2"))
    )
    (comp (ref "C148")
      (value "10µF")
      (footprint "CAPC0603(1608)100_L")
      (description "Chip Capacitor, 10µF +/-20%, 10V, 0603, Thickness 1 mm")
      (fields (field (name "TOLERANCE") "10%") (field (name "Comment") "Capacitor 10µF +/-20% 10V 0603"))
      (libsource (lib "MIGUEL ANGEL ALVAREZ GUZMAN") (part "CAP-NP-2"))
    )
    (comp (ref "C149")
      (value "100nF")
      (footprint "FP-CC0201-BA-IPC_A")
      (description "16V 100nF X5R ±10% 0201 Multilayer Ceramic Capacitors MLCC - SMD/SMT ROHS")
      (fields (field (name "TOLERANCE") "10%") (field (name "Comment") "CC0201KRX5R7BB104"))
      (libsource (lib "MIGUEL ANGEL ALVAREZ GUZMAN") (part "11868f565c42a9108669ba33697ecf6"))
    )
    (comp (ref "C150")
      (value "100nF")
      (footprint "FP-CC0201-BA-IPC_A")
      (description "16V 100nF X5R ±10% 0201 Multilayer Ceramic Capacitors MLCC - SMD/SMT ROHS")
      (fields (field (name "TOLERANCE") "10%") (field (name "Comment") "CC0201KRX5R7BB104"))
      (libsource (lib "MIGUEL ANGEL ALVAREZ GUZMAN") (part "11868f565c42a9108669ba33697ecf6"))
    )
    (comp (ref "C151")
      (value "100nF")
      (footprint "FP-CC0201-BA-IPC_A")
      (description "16V 100nF X5R ±10% 0201 Multilayer Ceramic Capacitors MLCC - SMD/SMT ROHS")
      (fields (field (name "TOLERANCE") "10%") (field (name "Comment") "CC0201KRX5R7BB104"))
      (libsource (lib "MIGUEL ANGEL ALVAREZ GUZMAN") (part "11868f565c42a9108669ba33697ecf6"))
    )
    (comp (ref "D1")
      (value "SBRT3U45SA-13")
      (footprint "FP-SMA-MFG")
      (description "DIODE SBR 45V 3A SMA")
      (libsource (lib "Altium Content Vault") (part "d7152d700b627762746794eb795d46e"))
    )
    (comp (ref "D2")
      (value "SBRT3U45SA-13")
      (footprint "FP-SMA-MFG")
      (description "DIODE SBR 45V 3A SMA")
      (libsource (lib "Altium Content Vault") (part "d7152d700b627762746794eb795d46e"))
    )
    (comp (ref "D3")
      (value "SBRT3U45SA-13")
      (footprint "FP-SMA-MFG")
      (description "DIODE SBR 45V 3A SMA")
      (libsource (lib "Altium Content Vault") (part "d7152d700b627762746794eb795d46e"))
    )
    (comp (ref "D4")
      (value "SBRT3U45SA-13")
      (footprint "FP-SMA-MFG")
      (description "DIODE SBR 45V 3A SMA")
      (libsource (lib "Altium Content Vault") (part "d7152d700b627762746794eb795d46e"))
    )
    (comp (ref "D5")
      (value "SBRT3U45SA-13")
      (footprint "FP-SMA-MFG")
      (description "DIODE SBR 45V 3A SMA")
      (libsource (lib "Altium Content Vault") (part "d7152d700b627762746794eb795d46e"))
    )
    (comp (ref "D6")
      (value "SBRT3U45SA-13")
      (footprint "FP-SMA-MFG")
      (description "DIODE SBR 45V 3A SMA")
      (libsource (lib "Altium Content Vault") (part "d7152d700b627762746794eb795d46e"))
    )
    (comp (ref "D7")
      (value "SBRT3U45SA-13")
      (footprint "FP-SMA-MFG")
      (description "DIODE SBR 45V 3A SMA")
      (libsource (lib "Altium Content Vault") (part "d7152d700b627762746794eb795d46e"))
    )
    (comp (ref "D8")
      (value "SBRT3U45SA-13")
      (footprint "FP-SMA-MFG")
      (description "DIODE SBR 45V 3A SMA")
      (libsource (lib "Altium Content Vault") (part "d7152d700b627762746794eb795d46e"))
    )
    (comp (ref "D9")
      (value "SBRT3U45SA-13")
      (footprint "FP-SMA-MFG")
      (description "DIODE SBR 45V 3A SMA")
      (libsource (lib "Altium Content Vault") (part "d7152d700b627762746794eb795d46e"))
    )
    (comp (ref "D10")
      (value "SBRT3U45SA-13")
      (footprint "FP-SMA-MFG")
      (description "DIODE SBR 45V 3A SMA")
      (libsource (lib "Altium Content Vault") (part "d7152d700b627762746794eb795d46e"))
    )
    (comp (ref "D11")
      (value "PTVS33VP1BPLJ")
      (footprint "FP-SOD128FL-1-CA_MFG")
      (description "600 W Transient Voltage Suppressor")
      (libsource (lib "Altium Content Vault") (part "f41379d69cb6a86da362523388cdb92"))
    )
    (comp (ref "D12")
      (value "SBRT3U45SA-13")
      (footprint "FP-SMA-MFG")
      (description "DIODE SBR 45V 3A SMA")
      (libsource (lib "Altium Content Vault") (part "d7152d700b627762746794eb795d46e"))
    )
    (comp (ref "D13")
      (value "PTVS33VP1BPLJ")
      (footprint "FP-SOD128FL-1-CA_MFG")
      (description "600 W Transient Voltage Suppressor")
      (libsource (lib "Altium Content Vault") (part "f41379d69cb6a86da362523388cdb92"))
    )
    (comp (ref "D14")
      (value "PTVS33VP1BPLJ")
      (footprint "FP-SOD128FL-1-CA_MFG")
      (description "600 W Transient Voltage Suppressor")
      (libsource (lib "Altium Content Vault") (part "f41379d69cb6a86da362523388cdb92"))
    )
    (comp (ref "D15")
      (value "PTVS33VP1BPLJ")
      (footprint "FP-SOD128FL-1-CA_MFG")
      (description "600 W Transient Voltage Suppressor")
      (libsource (lib "Altium Content Vault") (part "f41379d69cb6a86da362523388cdb92"))
    )
    (comp (ref "D16")
      (value "PTVS33VP1BPLJ")
      (footprint "FP-SOD128FL-1-CA_MFG")
      (description "600 W Transient Voltage Suppressor")
      (libsource (lib "Altium Content Vault") (part "f41379d69cb6a86da362523388cdb92"))
    )
    (comp (ref "D17")
      (value "PTVS33VP1BPLJ")
      (footprint "FP-SOD128FL-1-CA_MFG")
      (description "600 W Transient Voltage Suppressor")
      (libsource (lib "Altium Content Vault") (part "f41379d69cb6a86da362523388cdb92"))
    )
    (comp (ref "D18")
      (value "PTVS33VP1BPLJ")
      (footprint "FP-SOD128FL-1-CA_MFG")
      (description "600 W Transient Voltage Suppressor")
      (libsource (lib "Altium Content Vault") (part "f41379d69cb6a86da362523388cdb92"))
    )
    (comp (ref "J1")
      (value "BM02B-SURS-TF(LF)(SN)")
      (footprint "FP-BM02B-SURS-TF_LF_SN-MFG")
      (description "CONN HEADER SMD 2POS 0.8MM")
      (libsource (lib "Altium Content Vault") (part "56ec3178a87b3978bdc1b3682cd516a"))
    )
    (comp (ref "J2")
      (value "FH34SRJ-30S-0.5SH_99_")
      (footprint "FH34SRJ30S05SH99")
      (fields
        (field (name "MOUSER PART NUMBER") "798-FH34SRJ30S05SH99")
        (field (name "MANUFACTURER_PART_NUMBER") "FH34SRJ-30S-0.5SH(99)")
      )
      (libsource (lib "MIGUEL ANGEL ALVAREZ GUZMAN") (part "FH34SRJ-30S-0.5SH_99_"))
    )
    (comp (ref "J3")
      (value "FH34SRJ-40S-0.5SH_50_")
      (footprint "FH34SRJ40S05SH50")
      (fields
        (field (name "MANUFACTURER_PART_NUMBER") "FH34SRJ-40S-0.5SH(50)")
        (field (name "MOUSER PART NUMBER") "798-FH34SRJ40S05SH50")
      )
      (libsource (lib "MIGUEL ANGEL ALVAREZ GUZMAN") (part "FH34SRJ-40S-0.5SH_50_"))
    )
    (comp (ref "J4")
      (value "FH34SRJ-30S-0.5SH_99_")
      (footprint "FH34SRJ30S05SH99")
      (fields
        (field (name "MOUSER PART NUMBER") "798-FH34SRJ30S05SH99")
        (field (name "MANUFACTURER_PART_NUMBER") "FH34SRJ-30S-0.5SH(99)")
      )
      (libsource (lib "MIGUEL ANGEL ALVAREZ GUZMAN") (part "FH34SRJ-30S-0.5SH_99_"))
    )
    (comp (ref "J5")
      (value "78171-0004")
      (footprint "781710004")
      (description "Molex PICO-EZMATE 78171, 1.2mm Pitch, 4 Way, 1 Row, Straight PCB Header, Surface Mount")
      (fields (field (name "MOUSER PART NUMBER") "538-78171-0004"))
      (libsource (lib "MIGUEL ANGEL ALVAREZ GUZMAN") (part "78171-0004"))
    )
    (comp (ref "J6")
      (value "BM04B-SURS-TF(LF)(SN)")
      (footprint "JST_BM04B-SURS-TF(LF)(SN)")
      (description "Connector Header Surface Mount 4 position 0.031 (0.80mm)")
      (fields (field (name "MF") "JST Sales America Inc."))
      (libsource (lib "MIGUEL ANGEL ALVAREZ GUZMAN") (part "BM04B-SURS-TF(LF)(SN)"))
    )
    (comp (ref "J7")
      (value "HC-TYPE-C-16P-CB1.0")
      (footprint "HCTYPEC16PCB10")
      (description "3A 1 Sink panel 16P Female -25~+85 Type-C SMD USB Connectors ROHS")
      (libsource (lib "MIGUEL ANGEL ALVAREZ GUZMAN") (part "HC-TYPE-C-16P-CB1.0"))
    )
    (comp (ref "J8")
      (value "B2B-PH-SM4-TB(LF)(SN)")
      (footprint "FP-B2B-PH-SM4-TB_LF_SN-MFG")
      (description "CONN HEADER SMD 2POS 2MM")
      (libsource (lib "Altium Content Vault") (part "56ec3178a87b3978bdc1b3682cd516a"))
    )
    (comp (ref "L1")
      (value "LQP03TNR11H02D")
      (footprint "FP-LQP03PN_02-MFG")
      (description "Film type RF Inductor 110nH ±3% 80mA 12Ω 0201 (0603)")
      (fields (field (name "TOLERANCE") "3%"))
      (libsource (lib "Altium Content Vault") (part "ae3b6ca10b736fc74204ce580bf9b8e"))
    )
    (comp (ref "L2")
      (value "2.2µH")
      (footprint "FP-LQM2HPN_J0-IPC_A")
      (description "Inductor Power Chip Shielded Multi-Layer 2.2uH 20% 1MHz Ferrite 1A 0.15Ohm DCR 1008 T/R")
      (fields (field (name "TOLERANCE") "20%") (field (name "Comment") "LQM2HPN2R2MJ0L"))
      (libsource (lib "MIGUEL ANGEL ALVAREZ GUZMAN") (part "725321dda6339637d4d059423bc1c3c"))
    )
    (comp (ref "L3")
      (value "2.2µH")
      (footprint "FP-LQM2HPN_J0-IPC_A")
      (description "Inductor Power Chip Shielded Multi-Layer 2.2uH 20% 1MHz Ferrite 1A 0.15Ohm DCR 1008 T/R")
      (fields (field (name "TOLERANCE") "20%") (field (name "Comment") "LQM2HPN2R2MJ0L"))
      (libsource (lib "MIGUEL ANGEL ALVAREZ GUZMAN") (part "725321dda6339637d4d059423bc1c3c"))
    )
    (comp (ref "L4")
      (value "LQM2HPN2R2MJ0L")
      (footprint "FP-LQM2HPN_J0-IPC_A")
      (description "Multilayer Type Inductor for Power Lines, 1008 (2520), 2.2μH, 20%, 0.15Ω, 1000mA")
      (fields (field (name "TOLERANCE") "20%"))
      (libsource (lib "Altium Content Vault") (part "725321dda6339637d4d059423bc1c3c"))
    )
    (comp (ref "L5")
      (value "LQM2HPN2R2MJ0L")
      (footprint "FP-LQM2HPN_J0-IPC_A")
      (description "Multilayer Type Inductor for Power Lines, 1008 (2520), 2.2μH, 20%, 0.15Ω, 1000mA")
      (fields (field (name "TOLERANCE") "20%"))
      (libsource (lib "Altium Content Vault") (part "725321dda6339637d4d059423bc1c3c"))
    )
    (comp (ref "L6")
      (value "1.365H")
      (footprint "FP-LQM18DN_70-MFG")
      (description "General Purpose Inductor, 10uH, 20%, 1 Element, Ferrite-Core, Reflow soldering, , 1608/0603")
      (fields (field (name "TOLERANCE") "20%") (field (name "Comment") "LQM18DN100M70L"))
      (libsource (lib "MIGUEL ANGEL ALVAREZ GUZMAN") (part "725321dda6339637d4d059423bc1c3c"))
    )
    (comp (ref "L7")
      (value "LQM18DN100M70L")
      (footprint "FP-LQM18DN_70-IPC_B")
      (description "Multilayer type Inductor for Power Lines 10uH ±20% @1MHz, 300mA, Max DCR 1.365Ω, SRF 32MHz")
      (libsource (lib "Altium Content Vault") (part "725321dda6339637d4d059423bc1c3c"))
    )
    (comp (ref "Q1")
      (value "DMN3042L-13")
      (footprint "FP-SOT23-MFG")
      (description "MOSFET N-CH 30V 5.8A SOT23")
      (fields
        (field (name "OCTOPART") "https://octopart.com/dmn3042l-13-diodes+inc.-57605025")
        (field (name "MANUFACTURER") "Diodes")
      )
      (libsource (lib "Altium Content Vault") (part "3b9c635fedb024a5347a57b145af9cc"))
    )
    (comp (ref "Q2")
      (value "DMN3042L-13")
      (footprint "FP-SOT23-MFG")
      (description "MOSFET N-CH 30V 5.8A SOT23")
      (fields
        (field (name "OCTOPART") "https://octopart.com/dmn3042l-13-diodes+inc.-57605025")
        (field (name "MANUFACTURER") "Diodes")
      )
      (libsource (lib "Altium Content Vault") (part "3b9c635fedb024a5347a57b145af9cc"))
    )
    (comp (ref "Q3")
      (value "DMN3042L-13")
      (footprint "FP-SOT23-MFG")
      (description "720mW(Ta) 12V 1.4V@ 250μA 20nC@ 10 V 1N 30V 26.5mΩ@ 5.8A, 10V 5.8A 860pF@15V SOT-23-3")
      (libsource (lib "MIGUEL ANGEL ALVAREZ GUZMAN") (part "3b9c635fedb024a5347a57b145af9cc"))
    )
    (comp (ref "Q4")
      (value "DMN3042L-13")
      (footprint "FP-SOT23-MFG")
      (description "720mW(Ta) 12V 1.4V@ 250μA 20nC@ 10 V 1N 30V 26.5mΩ@ 5.8A, 10V 5.8A 860pF@15V SOT-23-3")
      (libsource (lib "MIGUEL ANGEL ALVAREZ GUZMAN") (part "3b9c635fedb024a5347a57b145af9cc"))
    )
    (comp (ref "Q5")
      (value "DMN3042L-13")
      (footprint "FP-SOT23-MFG")
      (description "720mW(Ta) 12V 1.4V@ 250μA 20nC@ 10 V 1N 30V 26.5mΩ@ 5.8A, 10V 5.8A 860pF@15V SOT-23-3")
      (libsource (lib "MIGUEL ANGEL ALVAREZ GUZMAN") (part "3b9c635fedb024a5347a57b145af9cc"))
    )
    (comp (ref "Q6")
      (value "DMN3042L-13")
      (footprint "FP-SOT23-MFG")
      (description "720mW(Ta) 12V 1.4V@ 250μA 20nC@ 10 V 1N 30V 26.5mΩ@ 5.8A, 10V 5.8A 860pF@15V SOT-23-3")
      (libsource (lib "MIGUEL ANGEL ALVAREZ GUZMAN") (part "3b9c635fedb024a5347a57b145af9cc"))
    )
    (comp (ref "R1")
      (value "100")
      (footprint "FP-RMCF0201-IPC_A")
      (description "Res Thick Film 0201 100 Ohm 5% 0.05W(1/20W) ±200ppm/C Pad SMD Automotive T/R")
      (fields (field (name "TOLERANCE") "5%") (field (name "Comment") "RMCF0201JT100R"))
      (libsource (lib "MIGUEL ANGEL ALVAREZ GUZMAN") (part "1029c3af85768c4190bb7ad29bc67b5"))
    )
    (comp (ref "R2")
      (value "3.3")
      (footprint "FP-RMCF0201-IPC_A")
      (fields (field (name "TOLERANCE") "5%") (field (name "Comment") "RMCF0201JT3R30"))
      (libsource (lib "MIGUEL ANGEL ALVAREZ GUZMAN") (part "1029c3af85768c4190bb7ad29bc67b5"))
    )
    (comp (ref "R3")
      (value "1k")
      (footprint "RESC0603X26X15NL03T05")
      (description "Res General Purpose Thick Film 0201 1k Ohm 1% 1/20W ±200ppm/°C Molded Paper T/R")
      (fields (field (name "TOLERANCE") "1%") (field (name "Comment") "MCRE000140"))
      (libsource (lib "MIGUEL ANGEL ALVAREZ GUZMAN") (part "RES"))
    )
    (comp (ref "R4")
      (value "100")
      (footprint "FP-RMCF0201-IPC_A")
      (description "Res Thick Film 0201 100 Ohm 5% 0.05W(1/20W) ±200ppm/C Pad SMD Automotive T/R")
      (fields (field (name "TOLERANCE") "5%") (field (name "Comment") "RMCF0201JT100R"))
      (libsource (lib "MIGUEL ANGEL ALVAREZ GUZMAN") (part "1029c3af85768c4190bb7ad29bc67b5"))
    )
    (comp (ref "R5")
      (value "0")
      (footprint "FP-HCJ0201-IPC_C")
      (description "Resistor Jumper Metal Plate 0201 0 Ohm Molded SMD Paper T/R")
      (fields (field (name "Comment") "HCJ0201ZT0R00"))
      (libsource (lib "MIGUEL ANGEL ALVAREZ GUZMAN") (part "1029c3af85768c4190bb7ad29bc67b5"))
    )
    (comp (ref "R6")
      (value "22")
      (footprint "RESC0603X28X15ML05T05")
      (description "Resistor Thick Film 0201 22 Ohm 5% 1/20W 200ppm/C Molded SMD Paper T/R")
      (fields (field (name "TOLERANCE") "5%") (field (name "Comment") "CRCW020122R0JNED"))
      (libsource (lib "MIGUEL ANGEL ALVAREZ GUZMAN") (part "RES"))
    )
    (comp (ref "R11")
      (value "2.26k")
      (footprint "FP-ERJ1GN-IPC_B")
      (description "Res Thick Film 0201 2.26K Ohm 1% 1/20W ±200ppm/°C Molded SMD SMD T/R")
      (fields (field (name "TOLERANCE") "1%") (field (name "Comment") "ERJ-1GNF2261C"))
      (libsource (lib "MIGUEL ANGEL ALVAREZ GUZMAN") (part "1029c3af85768c4190bb7ad29bc67b5"))
    )
    (comp (ref "R14")
      (value "10k")
      (footprint "FP-RT0201-IPC_C")
      (description "Fixed Resistor, Thin Film, 0.05W, 10000ohm, 25V, 0.1% +/-Tol, 50ppm/Cel, Surface Mount, 0201")
      (fields (field (name "TOLERANCE") "0.1%") (field (name "Comment") "RT0201BRE0710KL"))
      (libsource (lib "MIGUEL ANGEL ALVAREZ GUZMAN") (part "1029c3af85768c4190bb7ad29bc67b5"))
    )
    (comp (ref "R15")
      (value "10k")
      (footprint "FP-RT0201-IPC_C")
      (description "Fixed Resistor, Thin Film, 0.05W, 10000ohm, 25V, 0.1% +/-Tol, 50ppm/Cel, Surface Mount, 0201")
      (fields (field (name "TOLERANCE") "0.1%") (field (name "Comment") "RT0201BRE0710KL"))
      (libsource (lib "MIGUEL ANGEL ALVAREZ GUZMAN") (part "1029c3af85768c4190bb7ad29bc67b5"))
    )
    (comp (ref "R16")
      (value "4.7k")
      (footprint "FP-RMCF0201-IPC_A")
      (description "Res Thick Film 0201 4.7K Ohm 5% 0.05W(1/20W) ±200ppm/C Pad SMD Automotive T/R")
      (fields (field (name "TOLERANCE") "5%") (field (name "Comment") "RMCF0201JT4K70"))
      (libsource (lib "MIGUEL ANGEL ALVAREZ GUZMAN") (part "1029c3af85768c4190bb7ad29bc67b5"))
    )
    (comp (ref "R17")
      (value "10k")
      (footprint "FP-RT0201-IPC_C")
      (description "Fixed Resistor, Thin Film, 0.05W, 10000ohm, 25V, 0.1% +/-Tol, 50ppm/Cel, Surface Mount, 0201")
      (fields (field (name "TOLERANCE") "0.1%") (field (name "Comment") "RT0201BRE0710KL"))
      (libsource (lib "MIGUEL ANGEL ALVAREZ GUZMAN") (part "1029c3af85768c4190bb7ad29bc67b5"))
    )
    (comp (ref "R18")
      (value "4.7k")
      (footprint "FP-RMCF0201-IPC_A")
      (description "Res Thick Film 0201 4.7K Ohm 5% 0.05W(1/20W) ±200ppm/C Pad SMD Automotive T/R")
      (fields (field (name "TOLERANCE") "5%") (field (name "Comment") "RMCF0201JT4K70"))
      (libsource (lib "MIGUEL ANGEL ALVAREZ GUZMAN") (part "1029c3af85768c4190bb7ad29bc67b5"))
    )
    (comp (ref "R19")
      (value "56k")
      (footprint "RESC0603X28X15ML05T05")
      (description "CRCW FIXED RESISTOR 0201 (0603Metric) Chip Resistor ±5% ±200ppm/C 56kOhm 0.05W 1/20W")
      (fields (field (name "TOLERANCE") "5%") (field (name "Comment") "CRCW020156K0JNED"))
      (libsource (lib "MIGUEL ANGEL ALVAREZ GUZMAN") (part "RES"))
    )
    (comp (ref "R20")
      (value "2k")
      (footprint "FP-RMCF0201-IPC_A")
      (description "Res Thick Film 0201 2K Ohm 5% 0.05W(1/20W) ±200ppm/C Pad SMD Automotive T/R")
      (fields (field (name "TOLERANCE") "5%") (field (name "Comment") "RMCF0201JT2K00"))
      (libsource (lib "MIGUEL ANGEL ALVAREZ GUZMAN") (part "1029c3af85768c4190bb7ad29bc67b5"))
    )
    (comp (ref "R21")
      (value "0")
      (footprint "FP-HCJ0201-IPC_C")
      (description "Resistor Jumper Metal Plate 0201 0 Ohm Molded SMD Paper T/R")
      (fields (field (name "Comment") "HCJ0201ZT0R00"))
      (libsource (lib "MIGUEL ANGEL ALVAREZ GUZMAN") (part "1029c3af85768c4190bb7ad29bc67b5"))
    )
    (comp (ref "R22")
      (value "100")
      (footprint "FP-RMCF0201-IPC_A")
      (description "Res Thick Film 0201 100 Ohm 5% 0.05W(1/20W) ±200ppm/C Pad SMD Automotive T/R")
      (fields (field (name "TOLERANCE") "5%") (field (name "Comment") "RMCF0201JT100R"))
      (libsource (lib "MIGUEL ANGEL ALVAREZ GUZMAN") (part "1029c3af85768c4190bb7ad29bc67b5"))
    )
    (comp (ref "R23")
      (value "2k")
      (footprint "FP-RMCF0201-IPC_A")
      (description "Res Thick Film 0201 2K Ohm 5% 0.05W(1/20W) ±200ppm/C Pad SMD Automotive T/R")
      (fields (field (name "TOLERANCE") "5%") (field (name "Comment") "RMCF0201JT2K00"))
      (libsource (lib "MIGUEL ANGEL ALVAREZ GUZMAN") (part "1029c3af85768c4190bb7ad29bc67b5"))
    )
    (comp (ref "R24")
      (value "0")
      (footprint "FP-HCJ0201-IPC_C")
      (description "Resistor Jumper Metal Plate 0201 0 Ohm Molded SMD Paper T/R")
      (fields (field (name "Comment") "HCJ0201ZT0R00"))
      (libsource (lib "MIGUEL ANGEL ALVAREZ GUZMAN") (part "1029c3af85768c4190bb7ad29bc67b5"))
    )
    (comp (ref "R25")
      (value "39k")
      (footprint "RESC0603X28X15ML05T05")
      (description "CRCW FIXED RESISTOR 0201 (0603Metric) Chip Resistor ±5% ±200ppm/C 39kOhm 0.05W 1/20W")
      (fields (field (name "TOLERANCE") "5%") (field (name "Comment") "CRCW020139K0JNED"))
      (libsource (lib "MIGUEL ANGEL ALVAREZ GUZMAN") (part "RES"))
    )
    (comp (ref "R26")
      (value "100")
      (footprint "FP-RMCF0201-IPC_A")
      (description "Res Thick Film 0201 100 Ohm 5% 0.05W(1/20W) ±200ppm/C Pad SMD Automotive T/R")
      (fields (field (name "TOLERANCE") "5%") (field (name "Comment") "RMCF0201JT100R"))
      (libsource (lib "MIGUEL ANGEL ALVAREZ GUZMAN") (part "1029c3af85768c4190bb7ad29bc67b5"))
    )
    (comp (ref "R27")
      (value "10k")
      (footprint "FP-RT0201-IPC_C")
      (description "Fixed Resistor, Thin Film, 0.05W, 10000ohm, 25V, 0.1% +/-Tol, 50ppm/Cel, Surface Mount, 0201")
      (fields (field (name "TOLERANCE") "0.1%") (field (name "Comment") "RT0201BRE0710KL"))
      (libsource (lib "MIGUEL ANGEL ALVAREZ GUZMAN") (part "1029c3af85768c4190bb7ad29bc67b5"))
    )
    (comp (ref "R28")
      (value "10k")
      (footprint "FP-RT0201-IPC_C")
      (description "Fixed Resistor, Thin Film, 0.05W, 10000ohm, 25V, 0.1% +/-Tol, 50ppm/Cel, Surface Mount, 0201")
      (fields (field (name "TOLERANCE") "0.1%") (field (name "Comment") "RT0201BRE0710KL"))
      (libsource (lib "MIGUEL ANGEL ALVAREZ GUZMAN") (part "1029c3af85768c4190bb7ad29bc67b5"))
    )
    (comp (ref "R29")
      (value "10k")
      (footprint "FP-RT0201-IPC_C")
      (description "Fixed Resistor, Thin Film, 0.05W, 10000ohm, 25V, 0.1% +/-Tol, 50ppm/Cel, Surface Mount, 0201")
      (fields (field (name "TOLERANCE") "0.1%") (field (name "Comment") "RT0201BRE0710KL"))
      (libsource (lib "MIGUEL ANGEL ALVAREZ GUZMAN") (part "1029c3af85768c4190bb7ad29bc67b5"))
    )
    (comp (ref "R30")
      (value "10k")
      (footprint "FP-RT0201-IPC_C")
      (description "Fixed Resistor, Thin Film, 0.05W, 10000ohm, 25V, 0.1% +/-Tol, 50ppm/Cel, Surface Mount, 0201")
      (fields (field (name "TOLERANCE") "0.1%") (field (name "Comment") "RT0201BRE0710KL"))
      (libsource (lib "MIGUEL ANGEL ALVAREZ GUZMAN") (part "1029c3af85768c4190bb7ad29bc67b5"))
    )
    (comp (ref "R31")
      (value "0")
      (footprint "FP-HCJ0201-IPC_C")
      (description "Resistor Jumper Metal Plate 0201 0 Ohm Molded SMD Paper T/R")
      (fields (field (name "Comment") "HCJ0201ZT0R00"))
      (libsource (lib "MIGUEL ANGEL ALVAREZ GUZMAN") (part "1029c3af85768c4190bb7ad29bc67b5"))
    )
    (comp (ref "R32")
      (value "10k")
      (footprint "FP-RT0201-IPC_C")
      (description "Fixed Resistor, Thin Film, 0.05W, 10000ohm, 25V, 0.1% +/-Tol, 50ppm/Cel, Surface Mount, 0201")
      (fields (field (name "TOLERANCE") "0.1%") (field (name "Comment") "RT0201BRE0710KL"))
      (libsource (lib "MIGUEL ANGEL ALVAREZ GUZMAN") (part "1029c3af85768c4190bb7ad29bc67b5"))
    )
    (comp (ref "R33")
      (value "100")
      (footprint "FP-RMCF0201-IPC_A")
      (description "Res Thick Film 0201 100 Ohm 5% 0.05W(1/20W) ±200ppm/C Pad SMD Automotive T/R")
      (fields (field (name "TOLERANCE") "5%") (field (name "Comment") "RMCF0201JT100R"))
      (libsource (lib "MIGUEL ANGEL ALVAREZ GUZMAN") (part "1029c3af85768c4190bb7ad29bc67b5"))
    )
    (comp (ref "R34")
      (value "10k")
      (footprint "FP-RT0201-IPC_C")
      (description "Fixed Resistor, Thin Film, 0.05W, 10000ohm, 25V, 0.1% +/-Tol, 50ppm/Cel, Surface Mount, 0201")
      (fields (field (name "TOLERANCE") "0.1%") (field (name "Comment") "RT0201BRE0710KL"))
      (libsource (lib "MIGUEL ANGEL ALVAREZ GUZMAN") (part "1029c3af85768c4190bb7ad29bc67b5"))
    )
    (comp (ref "R35")
      (value "100")
      (footprint "FP-RMCF0201-IPC_A")
      (description "Res Thick Film 0201 100 Ohm 5% 0.05W(1/20W) ±200ppm/C Pad SMD Automotive T/R")
      (fields (field (name "TOLERANCE") "5%") (field (name "Comment") "RMCF0201JT100R"))
      (libsource (lib "MIGUEL ANGEL ALVAREZ GUZMAN") (part "1029c3af85768c4190bb7ad29bc67b5"))
    )
    (comp (ref "R36")
      (value "0")
      (footprint "FP-HCJ0201-IPC_C")
      (description "Resistor Jumper Metal Plate 0201 0 Ohm Molded SMD Paper T/R")
      (fields (field (name "Comment") "HCJ0201ZT0R00"))
      (libsource (lib "MIGUEL ANGEL ALVAREZ GUZMAN") (part "1029c3af85768c4190bb7ad29bc67b5"))
    )
    (comp (ref "R37")
      (value "10k")
      (footprint "FP-RT0201-IPC_C")
      (description "Fixed Resistor, Thin Film, 0.05W, 10000ohm, 25V, 0.1% +/-Tol, 50ppm/Cel, Surface Mount, 0201")
      (fields (field (name "TOLERANCE") "0.1%") (field (name "Comment") "RT0201BRE0710KL"))
      (libsource (lib "MIGUEL ANGEL ALVAREZ GUZMAN") (part "1029c3af85768c4190bb7ad29bc67b5"))
    )
    (comp (ref "R38")
      (value "10k")
      (footprint "FP-RT0201-IPC_C")
      (description "Fixed Resistor, Thin Film, 0.05W, 10000ohm, 25V, 0.1% +/-Tol, 50ppm/Cel, Surface Mount, 0201")
      (fields (field (name "TOLERANCE") "0.1%") (field (name "Comment") "RT0201BRE0710KL"))
      (libsource (lib "MIGUEL ANGEL ALVAREZ GUZMAN") (part "1029c3af85768c4190bb7ad29bc67b5"))
    )
    (comp (ref "R39")
      (value "10k")
      (footprint "FP-RT0201-IPC_C")
      (description "Fixed Resistor, Thin Film, 0.05W, 10000ohm, 25V, 0.1% +/-Tol, 50ppm/Cel, Surface Mount, 0201")
      (fields (field (name "TOLERANCE") "0.1%") (field (name "Comment") "RT0201BRE0710KL"))
      (libsource (lib "MIGUEL ANGEL ALVAREZ GUZMAN") (part "1029c3af85768c4190bb7ad29bc67b5"))
    )
    (comp (ref "R40")
      (value "10k")
      (footprint "FP-RT0201-IPC_C")
      (description "Fixed Resistor, Thin Film, 0.05W, 10000ohm, 25V, 0.1% +/-Tol, 50ppm/Cel, Surface Mount, 0201")
      (fields (field (name "TOLERANCE") "0.1%") (field (name "Comment") "RT0201BRE0710KL"))
      (libsource (lib "MIGUEL ANGEL ALVAREZ GUZMAN") (part "1029c3af85768c4190bb7ad29bc67b5"))
    )
    (comp (ref "R41")
      (value "4.7k")
      (footprint "FP-RMCF0201-IPC_A")
      (description "Res Thick Film 0201 4.7K Ohm 5% 0.05W(1/20W) ±200ppm/C Pad SMD Automotive T/R")
      (fields (field (name "TOLERANCE") "5%") (field (name "Comment") "RMCF0201JT4K70"))
      (libsource (lib "MIGUEL ANGEL ALVAREZ GUZMAN") (part "1029c3af85768c4190bb7ad29bc67b5"))
    )
    (comp (ref "R42")
      (value "10k")
      (footprint "FP-RT0201-IPC_C")
      (description "Fixed Resistor, Thin Film, 0.05W, 10000ohm, 25V, 0.1% +/-Tol, 50ppm/Cel, Surface Mount, 0201")
      (fields (field (name "TOLERANCE") "0.1%") (field (name "Comment") "RT0201BRE0710KL"))
      (libsource (lib "MIGUEL ANGEL ALVAREZ GUZMAN") (part "1029c3af85768c4190bb7ad29bc67b5"))
    )
    (comp (ref "R43")
      (value "22")
      (footprint "RESC0603X28X15ML05T05")
      (description "Resistor Thick Film 0201 22 Ohm 5% 1/20W 200ppm/C Molded SMD Paper T/R")
      (fields (field (name "TOLERANCE") "5%") (field (name "Comment") "CRCW020122R0JNED"))
      (libsource (lib "MIGUEL ANGEL ALVAREZ GUZMAN") (part "RES"))
    )
    (comp (ref "R44")
      (value "22")
      (footprint "RESC0603X28X15ML05T05")
      (description "Resistor Thick Film 0201 22 Ohm 5% 1/20W 200ppm/C Molded SMD Paper T/R")
      (fields (field (name "TOLERANCE") "5%") (field (name "Comment") "CRCW020122R0JNED"))
      (libsource (lib "MIGUEL ANGEL ALVAREZ GUZMAN") (part "RES"))
    )
    (comp (ref "R45")
      (value "10k")
      (footprint "FP-RT0201-IPC_C")
      (description "Fixed Resistor, Thin Film, 0.05W, 10000ohm, 25V, 0.1% +/-Tol, 50ppm/Cel, Surface Mount, 0201")
      (fields (field (name "TOLERANCE") "0.1%") (field (name "Comment") "RT0201BRE0710KL"))
      (libsource (lib "MIGUEL ANGEL ALVAREZ GUZMAN") (part "1029c3af85768c4190bb7ad29bc67b5"))
    )
    (comp (ref "R46")
      (value "4.7k")
      (footprint "FP-RMCF0201-IPC_A")
      (description "Res Thick Film 0201 4.7K Ohm 5% 0.05W(1/20W) ±200ppm/C Pad SMD Automotive T/R")
      (fields (field (name "TOLERANCE") "5%") (field (name "Comment") "RMCF0201JT4K70"))
      (libsource (lib "MIGUEL ANGEL ALVAREZ GUZMAN") (part "1029c3af85768c4190bb7ad29bc67b5"))
    )
    (comp (ref "R47")
      (value "4.7k")
      (footprint "FP-RMCF0201-IPC_A")
      (description "Res Thick Film 0201 4.7K Ohm 5% 0.05W(1/20W) ±200ppm/C Pad SMD Automotive T/R")
      (fields (field (name "TOLERANCE") "5%") (field (name "Comment") "RMCF0201JT4K70"))
      (libsource (lib "MIGUEL ANGEL ALVAREZ GUZMAN") (part "1029c3af85768c4190bb7ad29bc67b5"))
    )
    (comp (ref "R48")
      (value "10k")
      (footprint "FP-RT0201-IPC_C")
      (description "Fixed Resistor, Thin Film, 0.05W, 10000ohm, 25V, 0.1% +/-Tol, 50ppm/Cel, Surface Mount, 0201")
      (fields (field (name "TOLERANCE") "0.1%") (field (name "Comment") "RT0201BRE0710KL"))
      (libsource (lib "MIGUEL ANGEL ALVAREZ GUZMAN") (part "1029c3af85768c4190bb7ad29bc67b5"))
    )
    (comp (ref "R49")
      (value "4.7k")
      (footprint "FP-RMCF0201-IPC_A")
      (description "Res Thick Film 0201 4.7K Ohm 5% 0.05W(1/20W) ±200ppm/C Pad SMD Automotive T/R")
      (fields (field (name "TOLERANCE") "5%") (field (name "Comment") "RMCF0201JT4K70"))
      (libsource (lib "MIGUEL ANGEL ALVAREZ GUZMAN") (part "1029c3af85768c4190bb7ad29bc67b5"))
    )
    (comp (ref "R50")
      (value "RMCF0201JT47K0")
      (footprint "FP-RMCF0201-IPC_A")
      (description "Res Thick Film 0201 47K Ohm 5% 0.05W(1/20W) ±200ppm/C Pad SMD Automotive T/R")
      (libsource (lib "MIGUEL ANGEL ALVAREZ GUZMAN") (part "1029c3af85768c4190bb7ad29bc67b5"))
    )
    (comp (ref "R51")
      (value "10k")
      (footprint "FP-RT0201-IPC_C")
      (description "Fixed Resistor, Thin Film, 0.05W, 10000ohm, 25V, 0.1% +/-Tol, 50ppm/Cel, Surface Mount, 0201")
      (fields (field (name "TOLERANCE") "0.1%") (field (name "Comment") "RT0201BRE0710KL"))
      (libsource (lib "MIGUEL ANGEL ALVAREZ GUZMAN") (part "1029c3af85768c4190bb7ad29bc67b5"))
    )
    (comp (ref "R52")
      (value "22")
      (footprint "RESC0603X28X15ML05T05")
      (description "Resistor Thick Film 0201 22 Ohm 5% 1/20W 200ppm/C Molded SMD Paper T/R")
      (fields (field (name "TOLERANCE") "5%") (field (name "Comment") "CRCW020122R0JNED"))
      (libsource (lib "MIGUEL ANGEL ALVAREZ GUZMAN") (part "RES"))
    )
    (comp (ref "R53")
      (value "22")
      (footprint "RESC0603X28X15ML05T05")
      (description "Resistor Thick Film 0201 22 Ohm 5% 1/20W 200ppm/C Molded SMD Paper T/R")
      (fields (field (name "TOLERANCE") "5%") (field (name "Comment") "CRCW020122R0JNED"))
      (libsource (lib "MIGUEL ANGEL ALVAREZ GUZMAN") (part "RES"))
    )
    (comp (ref "R54")
      (value "22")
      (footprint "RESC0603X28X15ML05T05")
      (description "Resistor Thick Film 0201 22 Ohm 5% 1/20W 200ppm/C Molded SMD Paper T/R")
      (fields (field (name "TOLERANCE") "5%") (field (name "Comment") "CRCW020122R0JNED"))
      (libsource (lib "MIGUEL ANGEL ALVAREZ GUZMAN") (part "RES"))
    )
    (comp (ref "R55")
      (value "499")
      (footprint "FP-AF0201-IPC_B")
      (description "50mW Thick Film Resistors ±1% ±200ppm/℃ 499Ω 0201 Chip Resistor - Surface Mount ROHS")
      (fields (field (name "TOLERANCE") "1%") (field (name "Comment") "AF0201FR-07499RL"))
      (libsource (lib "MIGUEL ANGEL ALVAREZ GUZMAN") (part "1029c3af85768c4190bb7ad29bc67b5"))
    )
    (comp (ref "R56")
      (value "22")
      (footprint "RESC0603X28X15ML05T05")
      (description "Resistor Thick Film 0201 22 Ohm 5% 1/20W 200ppm/C Molded SMD Paper T/R")
      (fields (field (name "TOLERANCE") "5%") (field (name "Comment") "CRCW020122R0JNED"))
      (libsource (lib "MIGUEL ANGEL ALVAREZ GUZMAN") (part "RES"))
    )
    (comp (ref "R57")
      (value "10k")
      (footprint "FP-RT0201-IPC_C")
      (description "Fixed Resistor, Thin Film, 0.05W, 10000ohm, 25V, 0.1% +/-Tol, 50ppm/Cel, Surface Mount, 0201")
      (fields (field (name "TOLERANCE") "0.1%") (field (name "Comment") "RT0201BRE0710KL"))
      (libsource (lib "MIGUEL ANGEL ALVAREZ GUZMAN") (part "1029c3af85768c4190bb7ad29bc67b5"))
    )
    (comp (ref "R58")
      (value "RMCF0201JT47K0")
      (footprint "FP-RMCF0201-IPC_A")
      (description "Res Thick Film 0201 47K Ohm 5% 0.05W(1/20W) ±200ppm/C Pad SMD Automotive T/R")
      (libsource (lib "MIGUEL ANGEL ALVAREZ GUZMAN") (part "1029c3af85768c4190bb7ad29bc67b5"))
    )
    (comp (ref "R59")
      (value "RMCF0201JT47K0")
      (footprint "FP-RMCF0201-IPC_A")
      (description "Res Thick Film 0201 47K Ohm 5% 0.05W(1/20W) ±200ppm/C Pad SMD Automotive T/R")
      (libsource (lib "MIGUEL ANGEL ALVAREZ GUZMAN") (part "1029c3af85768c4190bb7ad29bc67b5"))
    )
    (comp (ref "R60")
      (value "100")
      (footprint "FP-RMCF0201-IPC_A")
      (description "Res Thick Film 0201 100 Ohm 5% 0.05W(1/20W) ±200ppm/C Pad SMD Automotive T/R")
      (fields (field (name "TOLERANCE") "5%") (field (name "Comment") "RMCF0201JT100R"))
      (libsource (lib "MIGUEL ANGEL ALVAREZ GUZMAN") (part "1029c3af85768c4190bb7ad29bc67b5"))
    )
    (comp (ref "R61")
      (value "10k")
      (footprint "FP-RT0201-IPC_C")
      (description "Fixed Resistor, Thin Film, 0.05W, 10000ohm, 25V, 0.1% +/-Tol, 50ppm/Cel, Surface Mount, 0201")
      (fields (field (name "TOLERANCE") "0.1%") (field (name "Comment") "RT0201BRE0710KL"))
      (libsource (lib "MIGUEL ANGEL ALVAREZ GUZMAN") (part "1029c3af85768c4190bb7ad29bc67b5"))
    )
    (comp (ref "R62")
      (value "0")
      (footprint "FP-HCJ0201-IPC_C")
      (description "Resistor Jumper Metal Plate 0201 0 Ohm Molded SMD Paper T/R")
      (fields (field (name "Comment") "HCJ0201ZT0R00"))
      (libsource (lib "MIGUEL ANGEL ALVAREZ GUZMAN") (part "1029c3af85768c4190bb7ad29bc67b5"))
    )
    (comp (ref "R63")
      (value "0")
      (footprint "FP-HCJ0201-IPC_C")
      (description "Resistor Jumper Metal Plate 0201 0 Ohm Molded SMD Paper T/R")
      (fields (field (name "Comment") "HCJ0201ZT0R00"))
      (libsource (lib "MIGUEL ANGEL ALVAREZ GUZMAN") (part "1029c3af85768c4190bb7ad29bc67b5"))
    )
    (comp (ref "R64")
      (value "100")
      (footprint "FP-RMCF0201-IPC_A")
      (description "Res Thick Film 0201 100 Ohm 5% 0.05W(1/20W) ±200ppm/C Pad SMD Automotive T/R")
      (fields (field (name "TOLERANCE") "5%") (field (name "Comment") "RMCF0201JT100R"))
      (libsource (lib "MIGUEL ANGEL ALVAREZ GUZMAN") (part "1029c3af85768c4190bb7ad29bc67b5"))
    )
    (comp (ref "R65")
      (value "100k")
      (footprint "RESC0603X26X15NL03T05")
      (description "Res General Purpose Thick Film 0201 100k Ohm 1% 1/20W ±200ppm/°C Molded Paper T/R")
      (fields (field (name "TOLERANCE") "1%") (field (name "Comment") "CRG0201F100K"))
      (libsource (lib "MIGUEL ANGEL ALVAREZ GUZMAN") (part "RES"))
    )
    (comp (ref "R66")
      (value "22k")
      (footprint "RESC0603X28X15ML05T05")
      (description "Res Thick Film 0201 22K Ohm 5% 0.05W(1/20W) ±200ppm/C Pad SMD T/R")
      (fields (field (name "TOLERANCE") "5%") (field (name "Comment") "CRCW020122K0JNED"))
      (libsource (lib "MIGUEL ANGEL ALVAREZ GUZMAN") (part "RES"))
    )
    (comp (ref "R67")
      (value "5.1k")
      (footprint "RESC0603X28X15ML05T05")
      (description "CRCW FIXED RESISTOR 0201 (0603Metric) Chip Resistor ±5% ±200ppm/C 5.1kOhm 0.05W 1/20W")
      (fields (field (name "TOLERANCE") "5%") (field (name "Comment") "CRCW02015K10JNED"))
      (libsource (lib "MIGUEL ANGEL ALVAREZ GUZMAN") (part "RES"))
    )
    (comp (ref "R68")
      (value "10k")
      (footprint "FP-RT0201-IPC_C")
      (description "Fixed Resistor, Thin Film, 0.05W, 10000ohm, 25V, 0.1% +/-Tol, 50ppm/Cel, Surface Mount, 0201")
      (fields (field (name "TOLERANCE") "0.1%") (field (name "Comment") "RT0201BRE0710KL"))
      (libsource (lib "MIGUEL ANGEL ALVAREZ GUZMAN") (part "1029c3af85768c4190bb7ad29bc67b5"))
    )
    (comp (ref "R69")
      (value "100k")
      (footprint "RESC0603X26X15NL03T05")
      (description "Res General Purpose Thick Film 0201 100k Ohm 1% 1/20W ±200ppm/°C Molded Paper T/R")
      (fields (field (name "TOLERANCE") "1%") (field (name "Comment") "CRG0201F100K"))
      (libsource (lib "MIGUEL ANGEL ALVAREZ GUZMAN") (part "RES"))
    )
    (comp (ref "R70")
      (value "0")
      (footprint "FP-HCJ0201-IPC_C")
      (description "Resistor Jumper Metal Plate 0201 0 Ohm Molded SMD Paper T/R")
      (fields (field (name "Comment") "HCJ0201ZT0R00"))
      (libsource (lib "MIGUEL ANGEL ALVAREZ GUZMAN") (part "1029c3af85768c4190bb7ad29bc67b5"))
    )
    (comp (ref "R71")
      (value "5.1k")
      (footprint "RESC0603X28X15ML05T05")
      (description "CRCW FIXED RESISTOR 0201 (0603Metric) Chip Resistor ±5% ±200ppm/C 5.1kOhm 0.05W 1/20W")
      (fields (field (name "TOLERANCE") "5%") (field (name "Comment") "CRCW02015K10JNED"))
      (libsource (lib "MIGUEL ANGEL ALVAREZ GUZMAN") (part "RES"))
    )
    (comp (ref "R72")
      (value "100")
      (footprint "FP-RMCF0201-IPC_A")
      (description "Res Thick Film 0201 100 Ohm 5% 0.05W(1/20W) ±200ppm/C Pad SMD Automotive T/R")
      (fields (field (name "TOLERANCE") "5%") (field (name "Comment") "RMCF0201JT100R"))
      (libsource (lib "MIGUEL ANGEL ALVAREZ GUZMAN") (part "1029c3af85768c4190bb7ad29bc67b5"))
    )
    (comp (ref "R73")
      (value "5.1k")
      (footprint "RESC0603X28X15ML05T05")
      (description "CRCW FIXED RESISTOR 0201 (0603Metric) Chip Resistor ±5% ±200ppm/C 5.1kOhm 0.05W 1/20W")
      (fields (field (name "TOLERANCE") "5%") (field (name "Comment") "CRCW02015K10JNED"))
      (libsource (lib "MIGUEL ANGEL ALVAREZ GUZMAN") (part "RES"))
    )
    (comp (ref "R74")
      (value "13k")
      (footprint "FP-RMCF0201-IPC_A")
      (description "Res Thick Film 0201 13K Ohm 5% 0.05W(1/20W) ±200ppm/C Pad SMD T/R")
      (fields (field (name "TOLERANCE") "5%") (field (name "Comment") "RMCF0201JT13K0"))
      (libsource (lib "MIGUEL ANGEL ALVAREZ GUZMAN") (part "1029c3af85768c4190bb7ad29bc67b5"))
    )
    (comp (ref "R75")
      (value "2.2")
      (footprint "FP-RMCF0201-IPC_A")
      (description "Res Thick Film 0201 2.2 Ohm 5% 0.05W(1/20W) ±400ppm/C Pad SMD T/R Automotive AEC-Q200")
      (fields (field (name "TOLERANCE") "5%") (field (name "Comment") "RMCF0201JT2R20"))
      (libsource (lib "MIGUEL ANGEL ALVAREZ GUZMAN") (part "1029c3af85768c4190bb7ad29bc67b5"))
    )
    (comp (ref "R76")
      (value "2.2")
      (footprint "FP-RMCF0201-IPC_A")
      (description "Res Thick Film 0201 2.2 Ohm 5% 0.05W(1/20W) ±400ppm/C Pad SMD T/R Automotive AEC-Q200")
      (fields (field (name "TOLERANCE") "5%") (field (name "Comment") "RMCF0201JT2R20"))
      (libsource (lib "MIGUEL ANGEL ALVAREZ GUZMAN") (part "1029c3af85768c4190bb7ad29bc67b5"))
    )
    (comp (ref "R77")
      (value "0")
      (footprint "FP-HCJ0201-IPC_C")
      (description "Resistor Jumper Metal Plate 0201 0 Ohm Molded SMD Paper T/R")
      (fields (field (name "Comment") "HCJ0201ZT0R00"))
      (libsource (lib "MIGUEL ANGEL ALVAREZ GUZMAN") (part "1029c3af85768c4190bb7ad29bc67b5"))
    )
    (comp (ref "R78")
      (value "0")
      (footprint "FP-HCJ0201-IPC_C")
      (description "Resistor Jumper Metal Plate 0201 0 Ohm Molded SMD Paper T/R")
      (fields (field (name "Comment") "HCJ0201ZT0R00"))
      (libsource (lib "MIGUEL ANGEL ALVAREZ GUZMAN") (part "1029c3af85768c4190bb7ad29bc67b5"))
    )
    (comp (ref "R79")
      (value "0")
      (footprint "FP-HCJ0201-IPC_C")
      (description "Resistor Jumper Metal Plate 0201 0 Ohm Molded SMD Paper T/R")
      (fields (field (name "Comment") "HCJ0201ZT0R00"))
      (libsource (lib "MIGUEL ANGEL ALVAREZ GUZMAN") (part "1029c3af85768c4190bb7ad29bc67b5"))
    )
    (comp (ref "SW1")
      (value "EVQ-Q2H03W")
      (footprint "FP-EVQ-Q2H03W-MFG")
      (description "SWITCH TACTILE SPST-NO 0.02A 15V")
      (fields
        (field (name "OCTOPART") "https://octopart.com/evq-q2h03w-panasonic-1368538")
        (field (name "MANUFACTURER") "Panasonic Electronic Components")
      )
      (libsource (lib "Altium Content Vault") (part "771f9546cad75bebae6a9b98152ef8d"))
    )
    (comp (ref "SW2")
      (value "EVQ-Q2H03W")
      (footprint "FP-EVQ-Q2H03W-MFG")
      (description "SWITCH TACTILE SPST-NO 0.02A 15V")
      (fields
        (field (name "OCTOPART") "https://octopart.com/evq-q2h03w-panasonic-1368538")
        (field (name "MANUFACTURER") "Panasonic Electronic Components")
      )
      (libsource (lib "Altium Content Vault") (part "771f9546cad75bebae6a9b98152ef8d"))
    )
    (comp (ref "SW3")
      (value "B3FS-1012P")
      (footprint "FP-B3FS-1012P-MFG")
      (description "SWITCH TACTILE SPST-NO 0.05A 24V")
      (libsource (lib "Altium Content Vault") (part "b8895f3f4cefb76e1819d2863dba89b"))
    )
    (comp (ref "SW4")
      (value "JS203011AQN")
      (footprint "FP-JS203011AQN-MFG")
      (description "SWITCH SLIDE DP3T 300MA 6V")
      (libsource (lib "Altium Content Vault") (part "712bc6c3d495507647c343f345dce47"))
    )
    (comp (ref "U1")
      (value "Amlogic A311D2")
      (footprint "BGA1058C40P33X37_1430X1610X110")
      (libsource (lib "MIGUEL ANGEL ALVAREZ GUZMAN") (part "Amlogic A311D2-Symbol-1"))
    )
    (comp (ref "U2")
      (value "PCF8563T/5,518")
      (footprint "FP-SOT96-1-MFG")
      (description "IC RTC CLK/CALENDAR I2C 8-SOIC")
      (fields
        (field (name "OCTOPART") "https://octopart.com/pcf8563t%2F5%2C518-nxp+semiconductors-19647995")
        (field (name "MANUFACTURER") "NXP")
      )
      (libsource (lib "Altium Content Vault") (part "a37bc7bf6ae0839037c7f5583b0f96f"))
    )
    (comp (ref "U3")
      (value "STM32G031K6U6")
      (footprint "UFQFPN-32")
      (fields (field (name "COPYRIGHT") "Copyright (C) 2026 Ultra Librarian. All rights reserved."))
      (libsource (lib "MIGUEL ANGEL ALVAREZ GUZMAN") (part "STM32G031K6U6"))
    )
    (comp (ref "U4")
      (value "MT53D1024M32D4DT-046_AIT_D")
      (footprint "BGA200C65P12X22_1000X1450X95")
      (description "IC DRAM 32GBIT 2133MHZ 200VFBGA")
      (fields
        (field (name "MANUFACTURER_PART_NUMBER") "MT53D1024M32D4DT-046 AIT:D")
        (field (name "MOUSER PART NUMBER") "340-343901-TRAY")
      )
      (libsource (lib "MIGUEL ANGEL ALVAREZ GUZMAN") (part "MT53D1024M32D4DT-046_AIT_D"))
    )
    (comp (ref "U5")
      (value "KLMAG2GEND-B031")
      (footprint "BGA153N50P14X14_1150X1300X80N")
      (description "SAMSUNG e路MMC is an embedded MMC solution designed in a BGA package form")
      (fields (field (name "MF") "Samsung"))
      (libsource (lib "MIGUEL ANGEL ALVAREZ GUZMAN") (part "KLMAG2GEND-B031"))
    )
    (comp (ref "U6")
      (value "TPS2115ADRBR")
      (footprint "FP-DRB0008B-IPC_B")
      (description "IC OR CTRLR SRC SELECT 8SON")
      (libsource (lib "Altium Content Vault") (part "3d7c2aab899432d139fb6cd2415b947"))
    )
    (comp (ref "U7")
      (value "TPS2121RUXR")
      (footprint "FP-RUX0012A-MFG")
      (description "PWR MGMT BATTERY MGMT")
      (fields
        (field (name "MANUFACTURER") "Texas Instruments")
        (field (name "OCTOPART") "https://octopart.com/tps2121ruxr-texas+instruments-95511053")
      )
      (libsource (lib "Altium Content Vault") (part "7e2eec2e55e3eba557c36dfb5d176d9"))
    )
    (comp (ref "U8")
      (value "WS2812B-B")
      (footprint "LED_WS2812B-B")
      (description "Intelligent control LED integrated light source")
      (libsource (lib "MIGUEL ANGEL ALVAREZ GUZMAN") (part "WS2812B-B"))
    )
    (comp (ref "U9")
      (value "WS2812B-B")
      (footprint "LED_WS2812B-B")
      (description "Intelligent control LED integrated light source")
      (libsource (lib "MIGUEL ANGEL ALVAREZ GUZMAN") (part "WS2812B-B"))
    )
    (comp (ref "U10")
      (value "WS2812B-B")
      (footprint "LED_WS2812B-B")
      (description "Intelligent control LED integrated light source")
      (libsource (lib "MIGUEL ANGEL ALVAREZ GUZMAN") (part "WS2812B-B"))
    )
    (comp (ref "U11")
      (value "WS2812B-B")
      (footprint "LED_WS2812B-B")
      (description "Intelligent control LED integrated light source")
      (libsource (lib "MIGUEL ANGEL ALVAREZ GUZMAN") (part "WS2812B-B"))
    )
    (comp (ref "U12")
      (value "MAX98357AETE+T")
      (footprint "QFN50P300X300X80-17N")
      (description "Tiny, Low-Cost, PCM Class D Amplifier with Class AB Performance")
      (fields (field (name "MF") "Analog Devices"))
      (libsource (lib "MIGUEL ANGEL ALVAREZ GUZMAN") (part "MAX98357AETE+T"))
    )
    (comp (ref "U13")
      (value "WS2812B-B")
      (footprint "LED_WS2812B-B")
      (description "Intelligent control LED integrated light source")
      (libsource (lib "MIGUEL ANGEL ALVAREZ GUZMAN") (part "WS2812B-B"))
    )
    (comp (ref "U14")
      (value "WS2812B-B")
      (footprint "LED_WS2812B-B")
      (description "Intelligent control LED integrated light source")
      (libsource (lib "MIGUEL ANGEL ALVAREZ GUZMAN") (part "WS2812B-B"))
    )
    (comp (ref "U15")
      (value "IM67D120AXTSA1")
      (footprint "FP-PG-LLGA-5-MFG")
      (description "IM67D120AXTSA1 MEMS Microphone Omni-Directional -26dB 1.62V to 3.6V 5-Pin LLGA-5-4 Solder Pad T/R")
      (libsource (lib "Altium Content Vault") (part "e59f635e26d4d5ddd5c8e36e97fd548"))
    )
    (comp (ref "U16")
      (value "IM67D120AXTSA1")
      (footprint "FP-PG-LLGA-5-MFG")
      (description "IM67D120AXTSA1 MEMS Microphone Omni-Directional -26dB 1.62V to 3.6V 5-Pin LLGA-5-4 Solder Pad T/R")
      (libsource (lib "Altium Content Vault") (part "e59f635e26d4d5ddd5c8e36e97fd548"))
    )
    (comp (ref "U17")
      (value "WS2812B-B")
      (footprint "LED_WS2812B-B")
      (description "Intelligent control LED integrated light source")
      (libsource (lib "MIGUEL ANGEL ALVAREZ GUZMAN") (part "WS2812B-B"))
    )
    (comp (ref "U18")
      (value "WS2812B-B")
      (footprint "LED_WS2812B-B")
      (description "Intelligent control LED integrated light source")
      (libsource (lib "MIGUEL ANGEL ALVAREZ GUZMAN") (part "WS2812B-B"))
    )
    (comp (ref "U19")
      (value "WS2812B-B")
      (footprint "LED_WS2812B-B")
      (description "Intelligent control LED integrated light source")
      (libsource (lib "MIGUEL ANGEL ALVAREZ GUZMAN") (part "WS2812B-B"))
    )
    (comp (ref "U20")
      (value "WS2812B-B")
      (footprint "LED_WS2812B-B")
      (description "Intelligent control LED integrated light source")
      (libsource (lib "MIGUEL ANGEL ALVAREZ GUZMAN") (part "WS2812B-B"))
    )
    (comp (ref "U21")
      (value "WS2812B-B")
      (footprint "LED_WS2812B-B")
      (description "Intelligent control LED integrated light source")
      (libsource (lib "MIGUEL ANGEL ALVAREZ GUZMAN") (part "WS2812B-B"))
    )
    (comp (ref "U22")
      (value "WS2812B-B")
      (footprint "LED_WS2812B-B")
      (description "Intelligent control LED integrated light source")
      (libsource (lib "MIGUEL ANGEL ALVAREZ GUZMAN") (part "WS2812B-B"))
    )
    (comp (ref "U23")
      (value "WS2812B-B")
      (footprint "LED_WS2812B-B")
      (description "Intelligent control LED integrated light source")
      (libsource (lib "MIGUEL ANGEL ALVAREZ GUZMAN") (part "WS2812B-B"))
    )
    (comp (ref "U24")
      (value "WS2812B-B")
      (footprint "LED_WS2812B-B")
      (description "Intelligent control LED integrated light source")
      (libsource (lib "MIGUEL ANGEL ALVAREZ GUZMAN") (part "WS2812B-B"))
    )
    (comp (ref "U25")
      (value "WS2812B-B")
      (footprint "LED_WS2812B-B")
      (description "Intelligent control LED integrated light source")
      (libsource (lib "MIGUEL ANGEL ALVAREZ GUZMAN") (part "WS2812B-B"))
    )
    (comp (ref "U26")
      (value "WS2812B-B")
      (footprint "LED_WS2812B-B")
      (description "Intelligent control LED integrated light source")
      (libsource (lib "MIGUEL ANGEL ALVAREZ GUZMAN") (part "WS2812B-B"))
    )
    (comp (ref "X1")
      (value "ABM3B-24.000MHZ-B2-T")
      (footprint "ABRA-ABM3B-4_V")
      (description "Ceramic SMD Crystal, 24 MHz, +/- 20 ppm, 18 pF, -20 to 70 degC, 4-Pin SMD, RoHS, Tape and Reel")
      (fields (field (name "TOLERANCE") "20ppm") (field (name "MANUFACTURER") "Abracon"))
      (libsource (lib "MIGUEL ANGEL ALVAREZ GUZMAN") (part "XTAL-1-3-4"))
    )
    (comp (ref "Y1")
      (value "ABS06-127-32.768KHZ-T")
      (footprint "FP-ABS06-MFG")
      (description "Crystal 32.768kHz ±20ppm (Tol) 12.5pF FUND 90kΩ 2-Pin Mini-CSMD T/R")
      (libsource (lib "Altium Content Vault") (part "c23a69dc6c9e2f18f2079038eb95dd1"))
    )
    (comp (ref "Y2")
      (value "ABM13W-37.4000MHZ-5-K1Z-T5")
      (footprint "FP-ABM13W-MFG")
      (description "Crystal 37.4MHz ±10ppm 5pF SMD-4 1.2mm x 1mm")
      (libsource (lib "Altium Content Vault") (part "72fe7d00fcb8bc033e1624bed3d881a"))
    )
  )
  (nets
    (net (code "1") (name "/ADC_CH3") (class "Default")
      (node (ref "U1") (pin "AD29") (pinfunction "SARADC_CH3_AD29") (pintype "passive+no_connect"))
    )
    (net (code "2") (name "/ADC_CH6") (class "Default")
      (node (ref "U1") (pin "AD28") (pinfunction "SARADC_CH6_AD28") (pintype "passive+no_connect"))
    )
    (net (code "3") (name "/ADC_KEY") (class "Default")
      (node (ref "U1") (pin "AD30") (pinfunction "SARADC_CH2_AD30") (pintype "passive+no_connect"))
    )
    (net (code "4") (name "/ANT0") (class "Default")
      (node (ref "B2") (pin "2") (pinfunction "WL_ANT0_2") (pintype "passive"))
      (node (ref "C151") (pin "1") (pinfunction "1_1") (pintype "passive"))
    )
    (net (code "5") (name "/ANT1") (class "Default")
      (node (ref "B2") (pin "9") (pinfunction "WL_ANT1_9") (pintype "passive"))
      (node (ref "C150") (pin "1") (pinfunction "1_1") (pintype "passive"))
    )
    (net (code "6") (name "/AVDD0V8_CSI") (class "Default")
      (node (ref "U1") (pin "L22") (pinfunction "AVDD0V8_CSI_L22") (pintype "passive+no_connect"))
    )
    (net (code "7") (name "/AVDD08_DP") (class "Default")
      (node (ref "U1") (pin "AJ13") (pinfunction "AVDD08_DP_AJ13") (pintype "passive"))
      (node (ref "U1") (pin "AK13") (pinfunction "AVDD08_DP_AK13") (pintype "passive"))
    )
    (net (code "8") (name "/AVDD18_DP") (class "Default")
      (node (ref "U1") (pin "AJ14") (pinfunction "AVDD18_DP_AJ14") (pintype "passive"))
      (node (ref "U1") (pin "AJ15") (pinfunction "AVDD18_DP_AJ15") (pintype "passive"))
    )
    (net (code "9") (name "/BOOT_CLK") (class "Default")
      (node (ref "R44") (pin "1") (pinfunction "1_1") (pintype "passive"))
      (node (ref "U5") (pin "M6") (pinfunction "CLK_M6") (pintype "input"))
    )
    (net (code "10") (name "/BOOT_CMD") (class "Default")
      (node (ref "R48") (pin "1") (pinfunction "1_1") (pintype "passive"))
      (node (ref "U1") (pin "AN23") (pinfunction "GPIOB_10_AN23") (pintype "passive"))
      (node (ref "U5") (pin "M5") (pinfunction "CMD_M5") (pintype "bidirectional"))
    )
    (net (code "11") (name "/BOOT_D0") (class "Default")
      (node (ref "R45") (pin "2") (pinfunction "2_2") (pintype "passive"))
      (node (ref "U1") (pin "AP21") (pinfunction "GPIOB_0_AP21") (pintype "passive"))
      (node (ref "U5") (pin "A3") (pinfunction "DAT0_A3") (pintype "bidirectional"))
    )
    (net (code "12") (name "/BOOT_D1") (class "Default")
      (node (ref "R21") (pin "1") (pinfunction "1_1") (pintype "passive"))
      (node (ref "U1") (pin "AP20") (pinfunction "GPIOB_1_AP20") (pintype "passive"))
      (node (ref "U5") (pin "A4") (pinfunction "DAT1_A4") (pintype "bidirectional"))
    )
    (net (code "13") (name "/BOOT_D2") (class "Default")
      (node (ref "R24") (pin "1") (pinfunction "1_1") (pintype "passive"))
      (node (ref "R47") (pin "1") (pinfunction "1_1") (pintype "passive"))
      (node (ref "U1") (pin "AN21") (pinfunction "GPIOB_2_AN21") (pintype "passive"))
      (node (ref "U5") (pin "A5") (pinfunction "DAT2_A5") (pintype "bidirectional"))
    )
    (net (code "14") (name "/BOOT_D3") (class "Default")
      (node (ref "U1") (pin "AM21") (pinfunction "GPIOB_3_AM21") (pintype "passive"))
      (node (ref "U5") (pin "B2") (pinfunction "DAT3_B2") (pintype "bidirectional"))
    )
    (net (code "15") (name "/BOOT_D4") (class "Default")
      (node (ref "B1") (pin "5") (pinfunction "DI_(IO0)_5") (pintype "passive"))
      (node (ref "R16") (pin "1") (pinfunction "1_1") (pintype "passive"))
      (node (ref "U1") (pin "AR23") (pinfunction "GPIOB_4_AR23") (pintype "passive"))
      (node (ref "U5") (pin "B3") (pinfunction "DAT4_B3") (pintype "bidirectional"))
    )
    (net (code "16") (name "/BOOT_D5") (class "Default")
      (node (ref "B1") (pin "2") (pinfunction "DO_(IO1)_1_2") (pintype "passive"))
      (node (ref "R18") (pin "1") (pinfunction "1_1") (pintype "passive"))
      (node (ref "U1") (pin "AP23") (pinfunction "GPIOB_5_AP23") (pintype "passive"))
      (node (ref "U5") (pin "B4") (pinfunction "DAT5_B4") (pintype "bidirectional"))
    )
    (net (code "17") (name "/BOOT_D6") (class "Default")
      (node (ref "B1") (pin "6") (pinfunction "CLK_6") (pintype "passive"))
      (node (ref "B1") (pin "7") (pinfunction "IO3_7") (pintype "passive"))
      (node (ref "R42") (pin "1") (pinfunction "1_1") (pintype "passive"))
      (node (ref "R43") (pin "1") (pinfunction "1_1") (pintype "passive"))
      (node (ref "U1") (pin "AR24") (pinfunction "GPIOB_6_AR24") (pintype "passive"))
      (node (ref "U5") (pin "B5") (pinfunction "DAT6_B5") (pintype "bidirectional"))
    )
    (net (code "18") (name "/BOOT_D7") (class "Default")
      (node (ref "B1") (pin "3") (pinfunction "DO_(IO1)_2_3") (pintype "passive"))
      (node (ref "U1") (pin "AP24") (pinfunction "GPIOB_7_AP24") (pintype "passive"))
      (node (ref "U5") (pin "B6") (pinfunction "DAT7_B6") (pintype "bidirectional"))
    )
    (net (code "19") (name "/BOOT_DCLK") (class "Default")
      (node (ref "U1") (pin "AP26") (pinfunction "GPIOB_8_AP26") (pintype "passive+no_connect"))
    )
    (net (code "20") (name "/BOOT_DQS") (class "Default")
      (node (ref "R50") (pin "2") (pinfunction "2_2") (pintype "passive"))
      (node (ref "U1") (pin "AN24") (pinfunction "GPIOB_11_AN24") (pintype "passive"))
      (node (ref "U5") (pin "H5") (pinfunction "DATA_STROBE_H5") (pintype "bidirectional"))
    )
    (net (code "21") (name "/BOOT_GPIOB_9") (class "Default")
      (node (ref "U1") (pin "AR26") (pinfunction "GPIOB_9_AR26") (pintype "passive+no_connect"))
    )
    (net (code "22") (name "/BOOT_GPIOB_12") (class "Default")
      (node (ref "U1") (pin "AM24") (pinfunction "GPIOB_12_AM24") (pintype "passive+no_connect"))
    )
    (net (code "23") (name "/BOOT_RST_N") (class "Default")
      (node (ref "U5") (pin "K5") (pinfunction "RSTN_K5") (pintype "input+no_connect"))
    )
    (net (code "24") (name "/BTPCM_CLK") (class "Default")
      (node (ref "B2") (pin "44") (pinfunction "BT_PCM_CLK_44") (pintype "passive"))
      (node (ref "U1") (pin "B20") (pinfunction "GPIOX_11_B20") (pintype "passive"))
    )
    (net (code "25") (name "/BTPCM_DIN") (class "Default")
      (node (ref "B2") (pin "47") (pinfunction "BT_PCM_OUT_47") (pintype "passive"))
      (node (ref "U1") (pin "B19") (pinfunction "GPIOX_9_B19") (pintype "passive"))
    )
    (net (code "26") (name "/BTPCM_DOUT") (class "Default")
      (node (ref "B2") (pin "46") (pinfunction "BT_PCM_IN_46") (pintype "passive"))
      (node (ref "U1") (pin "A19") (pinfunction "GPIOX_8_A19") (pintype "passive"))
    )
    (net (code "27") (name "/BTPCM_SYNC") (class "Default")
      (node (ref "B2") (pin "45") (pinfunction "BT_PCM_SYNC_45") (pintype "passive"))
      (node (ref "U1") (pin "C19") (pinfunction "GPIOX_10_C19") (pintype "passive"))
    )
    (net (code "28") (name "/BTUART_C_CTS_N") (class "Default")
      (node (ref "B2") (pin "42") (pinfunction "BT_UART_RTS_N_42") (pintype "passive"))
      (node (ref "U1") (pin "E18") (pinfunction "GPIOX_14_E18") (pintype "passive"))
    )
    (net (code "29") (name "/BTUART_C_RTS_N") (class "Default")
      (node (ref "B2") (pin "43") (pinfunction "BT_UART_CTS_N_43") (pintype "passive"))
      (node (ref "U1") (pin "A18") (pinfunction "GPIOX_15_A18") (pintype "passive"))
    )
    (net (code "30") (name "/BTUART_C_RX") (class "Default")
      (node (ref "B2") (pin "40") (pinfunction "BT_UART_TXD_40") (pintype "passive"))
      (node (ref "U1") (pin "C18") (pinfunction "GPIOX_13_C18") (pintype "passive"))
    )
    (net (code "31") (name "/BTUART_C_TX") (class "Default")
      (node (ref "B2") (pin "41") (pinfunction "BT_UART_RXD_41") (pintype "passive"))
      (node (ref "U1") (pin "D18") (pinfunction "GPIOX_12_D18") (pintype "passive"))
    )
    (net (code "32") (name "/BT_EN") (class "Default")
      (node (ref "B2") (pin "38") (pinfunction "BT_REG_ON_38") (pintype "passive"))
      (node (ref "U1") (pin "G21") (pinfunction "GPIOX_17_G21") (pintype "passive"))
    )
    (net (code "33") (name "/BT_WAKE_HOST") (class "Default")
      (node (ref "R52") (pin "2") (pinfunction "2_2") (pintype "passive"))
      (node (ref "U1") (pin "E17") (pinfunction "GPIOX_18_E17") (pintype "passive"))
    )
    (net (code "34") (name "/CMA_I2CM_C_SCL") (class "Default")
      (node (ref "J2") (pin "22") (pinfunction "22_22") (pintype "passive"))
      (node (ref "U1") (pin "E33") (pinfunction "GPIOM_12_E33") (pintype "passive"))
    )
    (net (code "35") (name "/CMA_I2CM_C_SDA") (class "Default")
      (node (ref "J2") (pin "23") (pinfunction "23_23") (pintype "passive"))
      (node (ref "U1") (pin "E32") (pinfunction "GPIOM_13_E32") (pintype "passive"))
    )
    (net (code "36") (name "/CMA_MCLK") (class "Default")
      (node (ref "C6") (pin "1") (pinfunction "1_1") (pintype "passive"))
      (node (ref "J2") (pin "20") (pinfunction "20_20") (pintype "passive"))
      (node (ref "L1") (pin "1") (pinfunction "1_1") (pintype "passive"))
    )
    (net (code "37") (name "/CMA_PWR") (class "Default")
      (node (ref "J2") (pin "19") (pinfunction "19_19") (pintype "passive"))
      (node (ref "U1") (pin "F32") (pinfunction "GPIOM_10_F32") (pintype "passive"))
    )
    (net (code "38") (name "/CMA_PWRDN") (class "Default")
      (node (ref "J2") (pin "24") (pinfunction "24_24") (pintype "passive"))
      (node (ref "U1") (pin "H32") (pinfunction "GPIOM_5_H32") (pintype "passive"))
    )
    (net (code "39") (name "/CMA_RST_L") (class "Default")
      (node (ref "J2") (pin "21") (pinfunction "21_21") (pintype "passive"))
      (node (ref "U1") (pin "E31") (pinfunction "GPIOM_11_E31") (pintype "passive"))
    )
    (net (code "40") (name "/CPUA_MODE") (class "Default")
      (node (ref "J4") (pin "17") (pinfunction "17_17") (pintype "passive+no_connect"))
    )
    (net (code "41") (name "/CPUB_MODE") (class "Default")
      (node (ref "J4") (pin "22") (pinfunction "22_22") (pintype "passive+no_connect"))
    )
    (net (code "42") (name "/CPU_RESET") (class "Default")
      (node (ref "C2") (pin "1") (pinfunction "1_1") (pintype "passive"))
      (node (ref "R3") (pin "2") (pinfunction "2_2") (pintype "passive"))
      (node (ref "R33") (pin "2") (pinfunction "2_2") (pintype "passive"))
      (node (ref "U1") (pin "F15") (pinfunction "RESET_N_F15") (pintype "passive"))
    )
    (net (code "43") (name "/CPU_RST_INT") (class "Default")
      (node (ref "R35") (pin "2") (pinfunction "2_2") (pintype "passive"))
      (node (ref "U3") (pin "14") (pinfunction "PA7_14") (pintype "bidirectional"))
    )
    (net (code "44") (name "/CSI_A_CLKN") (class "Default")
      (node (ref "J2") (pin "17") (pinfunction "17_17") (pintype "passive"))
      (node (ref "U1") (pin "A32") (pinfunction "CSI_A_CLKN_A32") (pintype "passive"))
    )
    (net (code "45") (name "/CSI_A_CLKP") (class "Default")
      (node (ref "J2") (pin "18") (pinfunction "18_18") (pintype "passive"))
      (node (ref "U1") (pin "A31") (pinfunction "CSI_A_CLKP_A31") (pintype "passive"))
    )
    (net (code "46") (name "/CSI_A_D0N") (class "Default")
      (node (ref "J2") (pin "14") (pinfunction "14_14") (pintype "passive"))
      (node (ref "U1") (pin "D32") (pinfunction "CSI_A_D0N_D32") (pintype "passive"))
    )
    (net (code "47") (name "/CSI_A_D0P") (class "Default")
      (node (ref "J2") (pin "15") (pinfunction "15_15") (pintype "passive"))
      (node (ref "U1") (pin "C32") (pinfunction "CSI_A_D0P_C32") (pintype "passive"))
    )
    (net (code "48") (name "/CSI_A_D1N") (class "Default")
      (node (ref "J2") (pin "11") (pinfunction "11_11") (pintype "passive"))
      (node (ref "U1") (pin "B32") (pinfunction "CSI_A_D1N_B32") (pintype "passive"))
    )
    (net (code "49") (name "/CSI_A_D1P") (class "Default")
      (node (ref "J2") (pin "12") (pinfunction "12_12") (pintype "passive"))
      (node (ref "U1") (pin "B33") (pinfunction "CSI_A_D1P_B33") (pintype "passive"))
    )
    (net (code "50") (name "/CSI_A_D2N") (class "Default")
      (node (ref "J2") (pin "5") (pinfunction "5_5") (pintype "passive"))
      (node (ref "U1") (pin "B31") (pinfunction "CSI_A_D2N_B31") (pintype "passive"))
    )
    (net (code "51") (name "/CSI_A_D2P") (class "Default")
      (node (ref "J2") (pin "6") (pinfunction "6_6") (pintype "passive"))
      (node (ref "U1") (pin "B30") (pinfunction "CSI_A_D2P_B30") (pintype "passive"))
    )
    (net (code "52") (name "/CSI_A_D3N") (class "Default")
      (node (ref "J2") (pin "2") (pinfunction "2_2") (pintype "passive"))
      (node (ref "U1") (pin "B29") (pinfunction "CSI_A_D3N_B29") (pintype "passive"))
    )
    (net (code "53") (name "/CSI_A_D3P") (class "Default")
      (node (ref "J2") (pin "3") (pinfunction "3_3") (pintype "passive"))
      (node (ref "U1") (pin "A29") (pinfunction "CSI_A_D3P_A29") (pintype "passive"))
    )
    (net (code "54") (name "/CSI_B_CLKN") (class "Default")
      (node (ref "J2") (pin "8") (pinfunction "8_8") (pintype "passive"))
      (node (ref "U1") (pin "A28") (pinfunction "CSI_B_CLKN_A28") (pintype "passive"))
    )
    (net (code "55") (name "/CSI_B_CLKP") (class "Default")
      (node (ref "J2") (pin "9") (pinfunction "9_9") (pintype "passive"))
      (node (ref "U1") (pin "B28") (pinfunction "CSI_B_CLKP_B28") (pintype "passive"))
    )
    (net (code "56") (name "/DCIN") (class "Default")
      (node (ref "C134") (pin "1") (pinfunction "1_1") (pintype "passive"))
      (node (ref "C135") (pin "1") (pinfunction "1_1") (pintype "passive"))
      (node (ref "C136") (pin "1") (pinfunction "1_1") (pintype "passive"))
      (node (ref "J3") (pin "26") (pinfunction "26_26") (pintype "passive"))
      (node (ref "J3") (pin "27") (pinfunction "27_27") (pintype "passive"))
      (node (ref "J3") (pin "28") (pinfunction "28_28") (pintype "passive"))
      (node (ref "J3") (pin "29") (pinfunction "29_29") (pintype "passive"))
      (node (ref "J3") (pin "30") (pinfunction "30_30") (pintype "passive"))
      (node (ref "R79") (pin "2") (pinfunction "2_2") (pintype "passive"))
      (node (ref "U7") (pin "8") (pinfunction "OUT_8") (pintype "output"))
    )
    (net (code "57") (name "/DCIN_TYPE-C") (class "Default")
      (node (ref "C145") (pin "1") (pinfunction "1_1") (pintype "passive"))
      (node (ref "C146") (pin "1") (pinfunction "1_1") (pintype "passive"))
      (node (ref "J7") (pin "A4") (pinfunction "VBUS_1_A4") (pintype "passive"))
      (node (ref "J7") (pin "B4") (pinfunction "VBUS_2_B4") (pintype "passive"))
      (node (ref "L7") (pin "2") (pinfunction "2_2") (pintype "passive"))
    )
    (net (code "58") (name "/DCIN_USBC") (class "Default")
      (node (ref "*") (pin "2") (pinfunction "VBUS_2") (pintype "passive"))
      (node (ref "C147") (pin "1") (pinfunction "1_1") (pintype "passive"))
      (node (ref "C148") (pin "1") (pinfunction "1_1") (pintype "passive"))
      (node (ref "D11") (pin "2") (pinfunction "2_2") (pintype "passive"))
      (node (ref "L7") (pin "1") (pinfunction "1_1") (pintype "passive"))
      (node (ref "R63") (pin "1") (pinfunction "1_1") (pintype "passive"))
      (node (ref "R65") (pin "1") (pinfunction "1_1") (pintype "passive"))
      (node (ref "U7") (pin "7") (pinfunction "IN1_7") (pintype "input"))
    )
    (net (code "59") (name "/DCIN_VIN") (class "Default")
      (node (ref "D13") (pin "1") (pinfunction "1_1") (pintype "passive"))
      (node (ref "J5") (pin "1") (pinfunction "1_1") (pintype "passive"))
      (node (ref "J5") (pin "2") (pinfunction "2_2") (pintype "passive"))
      (node (ref "R69") (pin "1") (pinfunction "1_1") (pintype "passive"))
      (node (ref "R73") (pin "1") (pinfunction "1_1") (pintype "passive"))
      (node (ref "R74") (pin "1") (pinfunction "1_1") (pintype "passive"))
      (node (ref "U7") (pin "2") (pinfunction "IN2_2") (pintype "input"))
    )
    (net (code "60") (name "/DDR1_CAA0") (class "Default")
      (node (ref "U1") (pin "AT1") (pinfunction "DDR1_AC_11_AT1") (pintype "passive"))
      (node (ref "U4") (pin "H2") (pinfunction "CA0_A_H2") (pintype "passive"))
    )
    (net (code "61") (name "/DDR1_CAA1") (class "Default")
      (node (ref "U1") (pin "AR1") (pinfunction "DDR1_AC_10_AR1") (pintype "passive"))
      (node (ref "U4") (pin "J2") (pinfunction "CA1_A_J2") (pintype "passive"))
    )
    (net (code "62") (name "/DDR1_CAA2") (class "Default")
      (node (ref "U1") (pin "AN2") (pinfunction "DDR1_AC_8_AN2") (pintype "passive"))
      (node (ref "U4") (pin "H9") (pinfunction "CA2_A_H9") (pintype "passive"))
    )
    (net (code "63") (name "/DDR1_CAA3") (class "Default")
      (node (ref "U1") (pin "AL3") (pinfunction "DDR1_AC_9_AL3") (pintype "passive"))
      (node (ref "U4") (pin "H10") (pinfunction "CA3_A_H10") (pintype "passive"))
    )
    (net (code "64") (name "/DDR1_CAA4") (class "Default")
      (node (ref "U1") (pin "AM3") (pinfunction "DDR1_AC_13_AM3") (pintype "passive"))
      (node (ref "U4") (pin "H11") (pinfunction "CA4_A_H11") (pintype "passive"))
    )
    (net (code "65") (name "/DDR1_CAA5") (class "Default")
      (node (ref "U1") (pin "AL4") (pinfunction "DDR1_AC_12_AL4") (pintype "passive"))
      (node (ref "U4") (pin "J11") (pinfunction "CA5_A_J11") (pintype "passive"))
    )
    (net (code "66") (name "/DDR1_CAB0") (class "Default")
      (node (ref "U1") (pin "AH1") (pinfunction "DDR1_AC_33_AH1") (pintype "passive"))
      (node (ref "U4") (pin "R2") (pinfunction "CA0_B_R2") (pintype "passive"))
    )
    (net (code "67") (name "/DDR1_CAB1") (class "Default")
      (node (ref "U1") (pin "AJ3") (pinfunction "DDR1_AC_28_AJ3") (pintype "passive"))
      (node (ref "U4") (pin "P2") (pinfunction "CA1_B_P2") (pintype "passive"))
    )
    (net (code "68") (name "/DDR1_CAB2") (class "Default")
      (node (ref "U1") (pin "AG3") (pinfunction "DDR1_AC_31_AG3") (pintype "passive"))
      (node (ref "U4") (pin "R9") (pinfunction "CA2_B_R9") (pintype "passive"))
    )
    (net (code "69") (name "/DDR1_CAB3") (class "Default")
      (node (ref "U1") (pin "AE5") (pinfunction "DDR1_AC_29_AE5") (pintype "passive"))
      (node (ref "U4") (pin "R10") (pinfunction "CA3_B_R10") (pintype "passive"))
    )
    (net (code "70") (name "/DDR1_CAB4") (class "Default")
      (node (ref "U1") (pin "AG5") (pinfunction "DDR1_AC_32_AG5") (pintype "passive"))
      (node (ref "U4") (pin "R11") (pinfunction "CA4_B_R11") (pintype "passive"))
    )
    (net (code "71") (name "/DDR1_CAB5") (class "Default")
      (node (ref "U1") (pin "AG4") (pinfunction "DDR1_AC_30_AG4") (pintype "passive"))
      (node (ref "U4") (pin "P11") (pinfunction "CA5_B_P11") (pintype "passive"))
    )
    (net (code "72") (name "/DDR1_CKEA0") (class "Default")
      (node (ref "U1") (pin "AN3") (pinfunction "DDR1_AC_0_AN3") (pintype "passive"))
      (node (ref "U4") (pin "J4") (pinfunction "CKE0_A_J4") (pintype "passive"))
    )
    (net (code "73") (name "/DDR1_CKEA1") (class "Default")
      (node (ref "U1") (pin "AL5") (pinfunction "DDR1_AC_1_AL5") (pintype "passive"))
      (node (ref "U4") (pin "J5") (pinfunction "CKE1_A_J5") (pintype "passive"))
    )
    (net (code "74") (name "/DDR1_CKEB0") (class "Default")
      (node (ref "U1") (pin "AL1") (pinfunction "DDR1_AC_20_AL1") (pintype "passive"))
      (node (ref "U4") (pin "P4") (pinfunction "CKE0_B_P4") (pintype "passive"))
    )
    (net (code "75") (name "/DDR1_CKEB1") (class "Default")
      (node (ref "U1") (pin "AM1") (pinfunction "DDR1_AC_21_AM1") (pintype "passive"))
      (node (ref "U4") (pin "P5") (pinfunction "CKE1_B_P5") (pintype "passive"))
    )
    (net (code "76") (name "/DDR1_CLKA_C") (class "Default")
      (node (ref "U1") (pin "AK3") (pinfunction "DDR1_AC_4_AK3") (pintype "passive"))
      (node (ref "U4") (pin "J9") (pinfunction "CK_C_A_J9") (pintype "passive"))
    )
    (net (code "77") (name "/DDR1_CLKA_T") (class "Default")
      (node (ref "U1") (pin "AK4") (pinfunction "DDR1_AC_5_AK4") (pintype "passive"))
      (node (ref "U4") (pin "J8") (pinfunction "CK_T_A_J8") (pintype "passive"))
    )
    (net (code "78") (name "/DDR1_CLKB_C") (class "Default")
      (node (ref "U1") (pin "AH3") (pinfunction "DDR1_AC_25_AH3") (pintype "passive"))
      (node (ref "U4") (pin "P9") (pinfunction "CK_C_B_P9") (pintype "passive"))
    )
    (net (code "79") (name "/DDR1_CLKB_T") (class "Default")
      (node (ref "U1") (pin "AH4") (pinfunction "DDR1_AC_24_AH4") (pintype "passive"))
      (node (ref "U4") (pin "P8") (pinfunction "CK_T_B_P8") (pintype "passive"))
    )
    (net (code "80") (name "/DDR1_CSA0") (class "Default")
      (node (ref "U1") (pin "AP1") (pinfunction "DDR1_AC_2_AP1") (pintype "passive"))
      (node (ref "U4") (pin "H4") (pinfunction "CS0_A_H4") (pintype "passive"))
    )
    (net (code "81") (name "/DDR1_CSA1") (class "Default")
      (node (ref "U1") (pin "AP3") (pinfunction "DDR1_AC_3_AP3") (pintype "passive"))
      (node (ref "U4") (pin "H3") (pinfunction "CS1_A_H3") (pintype "passive"))
    )
    (net (code "82") (name "/DDR1_CSB0") (class "Default")
      (node (ref "U1") (pin "AK2") (pinfunction "DDR1_AC_23_AK2") (pintype "passive"))
      (node (ref "U4") (pin "R4") (pinfunction "CS0_B_R4") (pintype "passive"))
    )
    (net (code "83") (name "/DDR1_CSB1") (class "Default")
      (node (ref "U1") (pin "AJ2") (pinfunction "DDR1_AC_22_AJ2") (pintype "passive"))
      (node (ref "U4") (pin "R3") (pinfunction "CS1_B_R3") (pintype "passive"))
    )
    (net (code "84") (name "/DDR1_DQ0") (class "Default")
      (node (ref "U1") (pin "AU2") (pinfunction "DDR1_DQ0_AU2") (pintype "passive"))
      (node (ref "U4") (pin "F2") (pinfunction "DQ3_A_F2") (pintype "passive"))
    )
    (net (code "85") (name "/DDR1_DQ1") (class "Default")
      (node (ref "U1") (pin "AP4") (pinfunction "DDR1_DQ1_AP4") (pintype "passive"))
      (node (ref "U4") (pin "E4") (pinfunction "DQ5_A_E4") (pintype "passive"))
    )
    (net (code "86") (name "/DDR1_DQ2") (class "Default")
      (node (ref "U1") (pin "AN6") (pinfunction "DDR1_DQ2_AN6") (pintype "passive"))
      (node (ref "U4") (pin "C4") (pinfunction "DQ6_A_C4") (pintype "passive"))
    )
    (net (code "87") (name "/DDR1_DQ3") (class "Default")
      (node (ref "U1") (pin "AP6") (pinfunction "DDR1_DQ3_AP6") (pintype "passive"))
      (node (ref "U4") (pin "B4") (pinfunction "DQ7_A_B4") (pintype "passive"))
    )
    (net (code "88") (name "/DDR1_DQ4") (class "Default")
      (node (ref "U1") (pin "AT5") (pinfunction "DDR1_DQ4_AT5") (pintype "passive"))
      (node (ref "U4") (pin "B2") (pinfunction "DQ0_A_B2") (pintype "passive"))
    )
    (net (code "89") (name "/DDR1_DQ5") (class "Default")
      (node (ref "U1") (pin "AU3") (pinfunction "DDR1_DQ5_AU3") (pintype "passive"))
      (node (ref "U4") (pin "E2") (pinfunction "DQ2_A_E2") (pintype "passive"))
    )
    (net (code "90") (name "/DDR1_DQ6") (class "Default")
      (node (ref "U1") (pin "AT4") (pinfunction "DDR1_DQ6_AT4") (pintype "passive"))
      (node (ref "U4") (pin "C2") (pinfunction "DQ1_A_C2") (pintype "passive"))
    )
    (net (code "91") (name "/DDR1_DQ7") (class "Default")
      (node (ref "U1") (pin "AR4") (pinfunction "DDR1_DQ7_AR4") (pintype "passive"))
      (node (ref "U4") (pin "F4") (pinfunction "DQ4_A_F4") (pintype "passive"))
    )
    (net (code "92") (name "/DDR1_DQ8") (class "Default")
      (node (ref "U1") (pin "AU9") (pinfunction "DDR1_DQ8_AU9") (pintype "passive"))
      (node (ref "U4") (pin "C9") (pinfunction "DQ14_A_C9") (pintype "passive"))
    )
    (net (code "93") (name "/DDR1_DQ9") (class "Default")
      (node (ref "U1") (pin "AR8") (pinfunction "DDR1_DQ9_AR8") (pintype "passive"))
      (node (ref "U4") (pin "E9") (pinfunction "DQ13_A_E9") (pintype "passive"))
    )
    (net (code "94") (name "/DDR1_DQ10") (class "Default")
      (node (ref "U1") (pin "AR9") (pinfunction "DDR1_DQ10_AR9") (pintype "passive"))
      (node (ref "U4") (pin "B9") (pinfunction "DQ15_A_B9") (pintype "passive"))
    )
    (net (code "95") (name "/DDR1_DQ11") (class "Default")
      (node (ref "U1") (pin "AT10") (pinfunction "DDR1_DQ11_AT10") (pintype "passive"))
      (node (ref "U4") (pin "C11") (pinfunction "DQ9_A_C11") (pintype "passive"))
    )
    (net (code "96") (name "/DDR1_DQ12") (class "Default")
      (node (ref "U1") (pin "AR7") (pinfunction "DDR1_DQ12_AR7") (pintype "passive"))
      (node (ref "U4") (pin "F9") (pinfunction "DQ12_A_F9") (pintype "passive"))
    )
    (net (code "97") (name "/DDR1_DQ13") (class "Default")
      (node (ref "U1") (pin "AP8") (pinfunction "DDR1_DQ13_AP8") (pintype "passive"))
      (node (ref "U4") (pin "E11") (pinfunction "DQ10_A_E11") (pintype "passive"))
    )
    (net (code "98") (name "/DDR1_DQ14") (class "Default")
      (node (ref "U1") (pin "AN8") (pinfunction "DDR1_DQ14_AN8") (pintype "passive"))
      (node (ref "U4") (pin "F11") (pinfunction "DQ11_A_F11") (pintype "passive"))
    )
    (net (code "99") (name "/DDR1_DQ15") (class "Default")
      (node (ref "U1") (pin "AT11") (pinfunction "DDR1_DQ15_AT11") (pintype "passive"))
      (node (ref "U4") (pin "B11") (pinfunction "DQ8_A_B11") (pintype "passive"))
    )
    (net (code "100") (name "/DDR1_DQ16") (class "Default")
      (node (ref "U1") (pin "AE4") (pinfunction "DDR1_DQ16_AE4") (pintype "passive"))
      (node (ref "U4") (pin "U2") (pinfunction "DQ3_B_U2") (pintype "passive"))
    )
    (net (code "101") (name "/DDR1_DQ17") (class "Default")
      (node (ref "U1") (pin "AF2") (pinfunction "DDR1_DQ17_AF2") (pintype "passive"))
      (node (ref "U4") (pin "V4") (pinfunction "DQ5_B_V4") (pintype "passive"))
    )
    (net (code "102") (name "/DDR1_DQ18") (class "Default")
      (node (ref "U1") (pin "AG2") (pinfunction "DDR1_DQ18_AG2") (pintype "passive"))
      (node (ref "U4") (pin "U4") (pinfunction "DQ4_B_U4") (pintype "passive"))
    )
    (net (code "103") (name "/DDR1_DQ19") (class "Default")
      (node (ref "U1") (pin "AE1") (pinfunction "DDR1_DQ19_AE1") (pintype "passive"))
      (node (ref "U4") (pin "Y2") (pinfunction "DQ1_B_Y2") (pintype "passive"))
    )
    (net (code "104") (name "/DDR1_DQ20") (class "Default")
      (node (ref "U1") (pin "AC3") (pinfunction "DDR1_DQ20_AC3") (pintype "passive"))
      (node (ref "U4") (pin "AA4") (pinfunction "DQ7_B_AA4") (pintype "passive"))
    )
    (net (code "105") (name "/DDR1_DQ21") (class "Default")
      (node (ref "U1") (pin "AD2") (pinfunction "DDR1_DQ21_AD2") (pintype "passive"))
      (node (ref "U4") (pin "AA2") (pinfunction "DQ0_B_AA2") (pintype "passive"))
    )
    (net (code "106") (name "/DDR1_DQ22") (class "Default")
      (node (ref "U1") (pin "AE3") (pinfunction "DDR1_DQ22_AE3") (pintype "passive"))
      (node (ref "U4") (pin "V2") (pinfunction "DQ2_B_V2") (pintype "passive"))
    )
    (net (code "107") (name "/DDR1_DQ23") (class "Default")
      (node (ref "U1") (pin "AC2") (pinfunction "DDR1_DQ23_AC2") (pintype "passive"))
      (node (ref "U4") (pin "Y4") (pinfunction "DQ6_B_Y4") (pintype "passive"))
    )
    (net (code "108") (name "/DDR1_DQ24") (class "Default")
      (node (ref "U1") (pin "AB1") (pinfunction "DDR1_DQ24_AB1") (pintype "passive"))
      (node (ref "U4") (pin "U9") (pinfunction "DQ12_B_U9") (pintype "passive"))
    )
    (net (code "109") (name "/DDR1_DQ25") (class "Default")
      (node (ref "U1") (pin "AA3") (pinfunction "DDR1_DQ25_AA3") (pintype "passive"))
      (node (ref "U4") (pin "U11") (pinfunction "DQ11_B_U11") (pintype "passive"))
    )
    (net (code "110") (name "/DDR1_DQ26") (class "Default")
      (node (ref "U1") (pin "AA4") (pinfunction "DDR1_DQ26_AA4") (pintype "passive"))
      (node (ref "U4") (pin "V11") (pinfunction "DQ10_B_V11") (pintype "passive"))
    )
    (net (code "111") (name "/DDR1_DQ27") (class "Default")
      (node (ref "U1") (pin "AA2") (pinfunction "DDR1_DQ27_AA2") (pintype "passive"))
      (node (ref "U4") (pin "V9") (pinfunction "DQ13_B_V9") (pintype "passive"))
    )
    (net (code "112") (name "/DDR1_DQ28") (class "Default")
      (node (ref "U1") (pin "Y3") (pinfunction "DDR1_DQ28_Y3") (pintype "passive"))
      (node (ref "U4") (pin "AA9") (pinfunction "DQ15_B_AA9") (pintype "passive"))
    )
    (net (code "113") (name "/DDR1_DQ29") (class "Default")
      (node (ref "U1") (pin "W4") (pinfunction "DDR1_DQ29_W4") (pintype "passive"))
      (node (ref "U4") (pin "AA11") (pinfunction "DQ8_B_AA11") (pintype "passive"))
    )
    (net (code "114") (name "/DDR1_DQ30") (class "Default")
      (node (ref "U1") (pin "W5") (pinfunction "DDR1_DQ30_W5") (pintype "passive"))
      (node (ref "U4") (pin "Y11") (pinfunction "DQ9_B_Y11") (pintype "passive"))
    )
    (net (code "115") (name "/DDR1_DQ31") (class "Default")
      (node (ref "U1") (pin "W3") (pinfunction "DDR0_DQ31_W3") (pintype "passive"))
      (node (ref "U1") (pin "Y2") (pinfunction "DDR1_DQ31_Y2") (pintype "passive"))
      (node (ref "U4") (pin "Y9") (pinfunction "DQ14_B_Y9") (pintype "passive"))
    )
    (net (code "116") (name "/DDR1_DQM0") (class "Default")
      (node (ref "U1") (pin "AR6") (pinfunction "DDR1_DQM0_AR6") (pintype "passive"))
      (node (ref "U4") (pin "C3") (pinfunction "DMI0_A_C3") (pintype "passive"))
    )
    (net (code "117") (name "/DDR1_DQM1") (class "Default")
      (node (ref "U1") (pin "AP7") (pinfunction "DDR1_DQM1_AP7") (pintype "passive"))
      (node (ref "U4") (pin "C10") (pinfunction "DMI1_A_C10") (pintype "passive"))
    )
    (net (code "118") (name "/DDR1_DQM2") (class "Default")
      (node (ref "U1") (pin "AF3") (pinfunction "DDR1_DQM2_AF3") (pintype "passive"))
      (node (ref "U4") (pin "Y3") (pinfunction "DMI0_B_Y3") (pintype "passive"))
    )
    (net (code "119") (name "/DDR1_DQM3") (class "Default")
      (node (ref "U1") (pin "W1") (pinfunction "DDR1_DQM3_W1") (pintype "passive"))
      (node (ref "U4") (pin "Y10") (pinfunction "DMI1_B_Y10") (pintype "passive"))
    )
    (net (code "120") (name "/DDR1_DQSN0") (class "Default")
      (node (ref "U1") (pin "AT6") (pinfunction "DDR1_DQSN0_AT6") (pintype "passive"))
      (node (ref "U4") (pin "E3") (pinfunction "DQS0_C_A_E3") (pintype "passive"))
    )
    (net (code "121") (name "/DDR1_DQSN1") (class "Default")
      (node (ref "U1") (pin "AT7") (pinfunction "DDR1_DQSP1_AT7") (pintype "passive"))
      (node (ref "U4") (pin "E10") (pinfunction "DQS1_C_A_E10") (pintype "passive"))
    )
    (net (code "122") (name "/DDR1_DQSN2") (class "Default")
      (node (ref "U1") (pin "AD3") (pinfunction "DDR1_DQSN2_AD3") (pintype "passive"))
      (node (ref "U4") (pin "V3") (pinfunction "DQS0_C_B_V3") (pintype "passive"))
    )
    (net (code "123") (name "/DDR1_DQSN3") (class "Default")
      (node (ref "U1") (pin "AB3") (pinfunction "DDR1_DQSN3_AB3") (pintype "passive"))
      (node (ref "U4") (pin "V10") (pinfunction "DQS1_C_B_V10") (pintype "passive"))
    )
    (net (code "124") (name "/DDR1_DQSP0") (class "Default")
      (node (ref "U1") (pin "AU6") (pinfunction "DDR1_DQSP0_AU6") (pintype "passive"))
      (node (ref "U4") (pin "D3") (pinfunction "DQS0_T_A_D3") (pintype "passive"))
    )
    (net (code "125") (name "/DDR1_DQSP1") (class "Default")
      (node (ref "U1") (pin "AT8") (pinfunction "DDR1_DQSN1_AT8") (pintype "passive"))
      (node (ref "U4") (pin "D10") (pinfunction "DQS1_T_A_D10") (pintype "passive"))
    )
    (net (code "126") (name "/DDR1_DQSP2") (class "Default")
      (node (ref "U1") (pin "AD4") (pinfunction "DDR1_DQSP2_AD4") (pintype "passive"))
      (node (ref "U4") (pin "W3") (pinfunction "DQS0_T_B_W3") (pintype "passive"))
    )
    (net (code "127") (name "/DDR1_DQSP3") (class "Default")
      (node (ref "U1") (pin "AB4") (pinfunction "DDR1_DQSP3_AB4") (pintype "passive"))
      (node (ref "U4") (pin "W10") (pinfunction "DQS1_T_B_W10") (pintype "passive"))
    )
    (net (code "128") (name "/DDR1_PVREF") (class "Default")
      (node (ref "C149") (pin "1") (pinfunction "1_1") (pintype "passive"))
      (node (ref "U1") (pin "AK6") (pinfunction "DDR1_PVREF_AK6") (pintype "passive"))
    )
    (net (code "129") (name "/DDR1_PZQ") (class "Default")
      (node (ref "U1") (pin "AN7") (pinfunction "DDR1_PZQ_AN7") (pintype "passive+no_connect"))
    )
    (net (code "130") (name "/DDR1_RST") (class "Default")
      (node (ref "U1") (pin "AL6") (pinfunction "DDR1_RST_AL6") (pintype "passive"))
      (node (ref "U4") (pin "T11") (pinfunction "RESET_N_T11") (pintype "passive"))
    )
    (net (code "131") (name "/DDR_ID") (class "Default")
      (node (ref "U1") (pin "AD31") (pinfunction "SARADC_CH0_AD31") (pintype "passive+no_connect"))
    )
    (net (code "132") (name "/DMIC_VDD") (class "Default")
      (node (ref "C141") (pin "1") (pinfunction "1_1") (pintype "passive"))
      (node (ref "C142") (pin "1") (pinfunction "1_1") (pintype "passive"))
      (node (ref "C143") (pin "1") (pinfunction "1_1") (pintype "passive"))
      (node (ref "C144") (pin "1") (pinfunction "1_1") (pintype "passive"))
      (node (ref "L6") (pin "2") (pinfunction "2_2") (pintype "passive"))
      (node (ref "U15") (pin "2") (pinfunction "VDD_2") (pintype "power_in"))
      (node (ref "U16") (pin "2") (pinfunction "VDD_2") (pintype "power_in"))
      (node (ref "U16") (pin "4") (pinfunction "LR_4") (pintype "passive"))
    )
    (net (code "133") (name "/DRAM1_VDD1_1V8") (class "Default")
      (node (ref "C71") (pin "1") (pinfunction "1_1") (pintype "passive"))
      (node (ref "C72") (pin "1") (pinfunction "1_1") (pintype "passive"))
      (node (ref "C73") (pin "1") (pinfunction "1_1") (pintype "passive"))
      (node (ref "C74") (pin "1") (pinfunction "1_1") (pintype "passive"))
      (node (ref "C75") (pin "1") (pinfunction "1_1") (pintype "passive"))
      (node (ref "C76") (pin "1") (pinfunction "1_1") (pintype "passive"))
      (node (ref "C77") (pin "1") (pinfunction "1_1") (pintype "passive"))
      (node (ref "C78") (pin "1") (pinfunction "1_1") (pintype "passive"))
    )
    (net (code "134") (name "/DRAM_VDD1_1V8") (class "Default")
      (node (ref "U4") (pin "F1") (pinfunction "VDD1_1_F1") (pintype "passive"))
      (node (ref "U4") (pin "F12") (pinfunction "VDD1_2_F12") (pintype "passive"))
      (node (ref "U4") (pin "G4") (pinfunction "VDD1_3_G4") (pintype "passive"))
      (node (ref "U4") (pin "G9") (pinfunction "VDD1_4_G9") (pintype "passive"))
      (node (ref "U4") (pin "T4") (pinfunction "VDD1_5_T4") (pintype "passive"))
      (node (ref "U4") (pin "T9") (pinfunction "VDD1_6_T9") (pintype "passive"))
      (node (ref "U4") (pin "U1") (pinfunction "VDD1_7_U1") (pintype "passive"))
      (node (ref "U4") (pin "U12") (pinfunction "VDD1_8_U12") (pintype "passive"))
    )
    (net (code "135") (name "/EMMC_EN") (class "Default")
      (node (ref "Q5") (pin "1") (pinfunction "G_1") (pintype "passive"))
      (node (ref "R49") (pin "1") (pinfunction "1_1") (pintype "passive"))
      (node (ref "U3") (pin "11") (pinfunction "PA4_11") (pintype "bidirectional"))
    )
    (net (code "136") (name "/ENET_EXTRES") (class "Default")
      (node (ref "R11") (pin "1") (pinfunction "1_1") (pintype "passive"))
      (node (ref "U1") (pin "AB28") (pinfunction "ENET_EXTRES_AB28") (pintype "passive"))
    )
    (net (code "137") (name "/EVCC3V3") (class "Default")
      (node (ref "C124") (pin "1") (pinfunction "1_1") (pintype "passive"))
      (node (ref "U6") (pin "7") (pinfunction "OUT_7") (pintype "power_in"))
    )
    (net (code "138") (name "/FAN_PWM") (class "Default")
      (node (ref "R70") (pin "1") (pinfunction "1_1") (pintype "passive"))
      (node (ref "U10") (pin "1") (pinfunction "VDD_1") (pintype "power_in"))
      (node (ref "U3") (pin "19") (pinfunction "PA9_19") (pintype "bidirectional"))
    )
    (net (code "139") (name "/GPIOD_5{slash}IR_IN") (class "Default")
      (node (ref "U1") (pin "B13") (pinfunction "GPIOD_5_B13") (pintype "passive+no_connect"))
    )
    (net (code "140") (name "/GPIOD_7") (class "Default")
      (node (ref "J4") (pin "14") (pinfunction "14_14") (pintype "passive"))
      (node (ref "U1") (pin "E12") (pinfunction "GPIOD_7_E12") (pintype "passive"))
    )
    (net (code "141") (name "/GPIOH_0") (class "Default")
      (node (ref "J4") (pin "18") (pinfunction "18_18") (pintype "passive"))
      (node (ref "U1") (pin "R28") (pinfunction "GPIOH_0_R28") (pintype "passive"))
    )
    (net (code "142") (name "/GPIOT_18") (class "Default")
      (node (ref "U1") (pin "N28") (pinfunction "GPIOT_18_N28") (pintype "passive"))
      (node (ref "U11") (pin "4") (pinfunction "DIN_4") (pintype "input"))
    )
    (net (code "143") (name "/HOST_WAKE_BT") (class "Default")
      (node (ref "R51") (pin "1") (pinfunction "1_1") (pintype "passive"))
      (node (ref "R53") (pin "2") (pinfunction "2_2") (pintype "passive"))
      (node (ref "U1") (pin "D17") (pinfunction "GPIOX_19_D17") (pintype "passive"))
    )
    (net (code "144") (name "/HW_ID") (class "Default")
      (node (ref "R19") (pin "1") (pinfunction "1_1") (pintype "passive"))
      (node (ref "R25") (pin "2") (pinfunction "2_2") (pintype "passive"))
      (node (ref "U1") (pin "AE29") (pinfunction "SARADC_CH1_AE29") (pintype "passive"))
    )
    (net (code "145") (name "/I2CM_AO_SCL") (class "Default")
      (node (ref "R23") (pin "1") (pinfunction "1_1") (pintype "passive"))
      (node (ref "R77") (pin "2") (pinfunction "2_2") (pintype "passive"))
      (node (ref "U1") (pin "F11") (pinfunction "GPIOD_2_F11") (pintype "passive"))
      (node (ref "U2") (pin "6") (pinfunction "SCL_6") (pintype "input"))
      (node (ref "U3") (pin "30") (pinfunction "PB6_30") (pintype "bidirectional"))
    )
    (net (code "146") (name "/I2CM_AO_SDA") (class "Default")
      (node (ref "R20") (pin "1") (pinfunction "1_1") (pintype "passive"))
      (node (ref "R78") (pin "2") (pinfunction "2_2") (pintype "passive"))
      (node (ref "U1") (pin "E14") (pinfunction "GPIOD_3_E14") (pintype "passive"))
      (node (ref "U2") (pin "5") (pinfunction "SDA_5") (pintype "bidirectional"))
      (node (ref "U3") (pin "31") (pinfunction "PB7_31") (pintype "bidirectional"))
    )
    (net (code "147") (name "/I2S_LRCLK1") (class "Default")
      (node (ref "U1") (pin "N29") (pinfunction "GPIOT_2_N29") (pintype "passive"))
      (node (ref "U12") (pin "14") (pinfunction "LRCLK_14") (pintype "input"))
    )
    (net (code "148") (name "/I2S_MCLK1") (class "Default")
      (node (ref "U1") (pin "P32") (pinfunction "GPIOT_0_P32") (pintype "passive+no_connect"))
    )
    (net (code "149") (name "/I2S_SCLK1") (class "Default")
      (node (ref "U1") (pin "P33") (pinfunction "GPIOT_1_P33") (pintype "passive"))
      (node (ref "U12") (pin "16") (pinfunction "BCLK_16") (pintype "input"))
    )
    (net (code "150") (name "/I2S_SDI1") (class "Default")
      (node (ref "U1") (pin "P31") (pinfunction "GPIOT_4_P31") (pintype "passive+no_connect"))
    )
    (net (code "151") (name "/I2S_SDO1") (class "Default")
      (node (ref "U1") (pin "N33") (pinfunction "GPIOT_3_N33") (pintype "passive"))
      (node (ref "U12") (pin "1") (pinfunction "DIN_1") (pintype "input"))
    )
    (net (code "152") (name "/LCD_BL_PWM") (class "Default")
      (node (ref "J3") (pin "21") (pinfunction "21_21") (pintype "passive"))
      (node (ref "U1") (pin "AM14") (pinfunction "GPIOY_1_AM14") (pintype "passive"))
    )
    (net (code "153") (name "/LCD_EN") (class "Default")
      (node (ref "J3") (pin "19") (pinfunction "19_19") (pintype "passive"))
      (node (ref "U1") (pin "AN14") (pinfunction "GPIOY_2_AN14") (pintype "passive"))
    )
    (net (code "154") (name "/LCD_RESET") (class "Default")
      (node (ref "J3") (pin "20") (pinfunction "20_20") (pintype "passive"))
      (node (ref "U1") (pin "AR21") (pinfunction "GPIOY_9_AR21") (pintype "passive"))
    )
    (net (code "155") (name "/MCU_BOOT_CTRL") (class "Default")
      (node (ref "Q2") (pin "1") (pinfunction "G_1") (pintype "passive"))
      (node (ref "R39") (pin "1") (pinfunction "1_1") (pintype "passive"))
    )
    (net (code "156") (name "/MCU_I2C2_SCL") (class "Default")
      (node (ref "U3") (pin "22") (pinfunction "PA11[PA9]_22") (pintype "bidirectional+no_connect"))
    )
    (net (code "157") (name "/MCU_I2C2_SDA") (class "Default")
      (node (ref "U3") (pin "23") (pinfunction "PA12[PA10]_23") (pintype "bidirectional+no_connect"))
    )
    (net (code "158") (name "/MCU_NMI") (class "Default")
      (node (ref "R31") (pin "1") (pinfunction "1_1") (pintype "passive"))
      (node (ref "U3") (pin "16") (pinfunction "PB1_16") (pintype "bidirectional"))
    )
    (net (code "159") (name "/MCU_PA0") (class "Default")
      (node (ref "U3") (pin "7") (pinfunction "PA0_7") (pintype "bidirectional+no_connect"))
    )
    (net (code "160") (name "/MCU_PA15") (class "Default")
      (node (ref "U3") (pin "26") (pinfunction "PA15_26") (pintype "bidirectional+no_connect"))
    )
    (net (code "161") (name "/MCU_PWR_CTRL") (class "Default")
      (node (ref "D6") (pin "2") (pinfunction "A_2") (pintype "passive"))
      (node (ref "R34") (pin "1") (pinfunction "1_1") (pintype "passive"))
      (node (ref "U3") (pin "15") (pinfunction "PB0_15") (pintype "bidirectional"))
    )
    (net (code "162") (name "/MCU_PWR_KEY") (class "Default")
      (node (ref "R26") (pin "2") (pinfunction "2_2") (pintype "passive"))
      (node (ref "R64") (pin "2") (pinfunction "2_2") (pintype "passive"))
      (node (ref "U3") (pin "28") (pinfunction "PB4_28") (pintype "bidirectional"))
    )
    (net (code "163") (name "/MCU_RST") (class "Default")
      (node (ref "C47") (pin "1") (pinfunction "1_1") (pintype "passive"))
      (node (ref "Q1") (pin "3") (pinfunction "D_3") (pintype "passive"))
      (node (ref "R27") (pin "1") (pinfunction "1_1") (pintype "passive"))
      (node (ref "U3") (pin "6") (pinfunction "PF2-NRST_6") (pintype "bidirectional"))
    )
    (net (code "164") (name "/MCU_RST_CTRL") (class "Default")
      (node (ref "Q1") (pin "1") (pinfunction "G_1") (pintype "passive"))
      (node (ref "U1") (pin "J29") (pinfunction "GPIOT_12_J29") (pintype "passive"))
    )
    (net (code "165") (name "/MCU_SWCLK") (class "Default")
      (node (ref "Q2") (pin "2") (pinfunction "S_2") (pintype "passive"))
      (node (ref "R40") (pin "1") (pinfunction "1_1") (pintype "passive"))
      (node (ref "U3") (pin "25") (pinfunction "PA14-BOOT0_25") (pintype "bidirectional"))
    )
    (net (code "166") (name "/MCU_SWDIO") (class "Default")
      (node (ref "U3") (pin "24") (pinfunction "PA13_24") (pintype "bidirectional+no_connect"))
    )
    (net (code "167") (name "/MCU_USART2_RX") (class "Default")
      (node (ref "U3") (pin "10") (pinfunction "PA3_10") (pintype "bidirectional+no_connect"))
    )
    (net (code "168") (name "/MCU_USART2_TX") (class "Default")
      (node (ref "U3") (pin "9") (pinfunction "PA2_9") (pintype "bidirectional+no_connect"))
    )
    (net (code "169") (name "/MIPI_DSI_CLKN") (class "Default")
      (node (ref "J3") (pin "8") (pinfunction "8_8") (pintype "passive"))
      (node (ref "U1") (pin "AU19") (pinfunction "VX1_A_2N_AU19") (pintype "passive"))
    )
    (net (code "170") (name "/MIPI_DSI_CLKP") (class "Default")
      (node (ref "J3") (pin "9") (pinfunction "9_9") (pintype "passive"))
      (node (ref "U1") (pin "AT19") (pinfunction "VX1_A_2P_AT19") (pintype "passive"))
    )
    (net (code "171") (name "/MIPI_DSI_D0N") (class "Default")
      (node (ref "J3") (pin "14") (pinfunction "14_14") (pintype "passive"))
      (node (ref "U1") (pin "AM18") (pinfunction "VX1_A_0N_AM18") (pintype "passive"))
    )
    (net (code "172") (name "/MIPI_DSI_D0P") (class "Default")
      (node (ref "J3") (pin "15") (pinfunction "15_15") (pintype "passive"))
      (node (ref "U1") (pin "AN18") (pinfunction "VX1_A_0P_AN18") (pintype "passive"))
    )
    (net (code "173") (name "/MIPI_DSI_D1N") (class "Default")
      (node (ref "J3") (pin "11") (pinfunction "11_11") (pintype "passive"))
      (node (ref "U1") (pin "AR18") (pinfunction "VX1_A_1N_AR18") (pintype "passive"))
    )
    (net (code "174") (name "/MIPI_DSI_D1P") (class "Default")
      (node (ref "J3") (pin "12") (pinfunction "12_12") (pintype "passive"))
      (node (ref "U1") (pin "AP18") (pinfunction "VX1_A_1P_AP18") (pintype "passive"))
    )
    (net (code "175") (name "/MIPI_DSI_D2N") (class "Default")
      (node (ref "J3") (pin "5") (pinfunction "5_5") (pintype "passive"))
      (node (ref "U1") (pin "AR17") (pinfunction "VX1_A_3N_AR17") (pintype "passive"))
    )
    (net (code "176") (name "/MIPI_DSI_D2P") (class "Default")
      (node (ref "J3") (pin "6") (pinfunction "6_6") (pintype "passive"))
      (node (ref "U1") (pin "AP17") (pinfunction "VX1_A_3P_AP17") (pintype "passive"))
    )
    (net (code "177") (name "/MIPI_DSI_D3N") (class "Default")
      (node (ref "J3") (pin "2") (pinfunction "2_2") (pintype "passive"))
      (node (ref "U1") (pin "AU18") (pinfunction "VX1_A_4N_AU18") (pintype "passive"))
    )
    (net (code "178") (name "/MIPI_DSI_D3P") (class "Default")
      (node (ref "J3") (pin "3") (pinfunction "3_3") (pintype "passive"))
      (node (ref "U1") (pin "AT18") (pinfunction "VX1_A_4P_AT18") (pintype "passive"))
    )
    (net (code "179") (name "/PANEL_B_PWR") (class "Default")
      (node (ref "J3") (pin "38") (pinfunction "38_38") (pintype "passive"))
      (node (ref "U1") (pin "AU22") (pinfunction "GPIOY_10_AU22") (pintype "passive"))
    )
    (net (code "180") (name "/PDM_DCLK") (class "Default")
      (node (ref "U1") (pin "J32") (pinfunction "GPIOM_3_J32") (pintype "passive"))
      (node (ref "U15") (pin "3") (pinfunction "CLOCK_3") (pintype "input"))
      (node (ref "U16") (pin "3") (pinfunction "CLOCK_3") (pintype "input"))
    )
    (net (code "181") (name "/PDM_DIN3") (class "Default")
      (node (ref "SW4") (pin "3") (pinfunction "1_C_3") (pintype "passive"))
      (node (ref "U1") (pin "J30") (pinfunction "GPIOM_2_J30") (pintype "passive"))
    )
    (net (code "182") (name "/POR_OUT") (class "Default")
      (node (ref "R3") (pin "1") (pinfunction "1_1") (pintype "passive"))
      (node (ref "U1") (pin "E23") (pinfunction "POR_OUT_E23") (pintype "passive"))
    )
    (net (code "183") (name "/PWR_EN") (class "Default")
      (node (ref "J4") (pin "26") (pinfunction "26_26") (pintype "passive"))
      (node (ref "R58") (pin "1") (pinfunction "1_1") (pintype "passive"))
    )
    (net (code "184") (name "/PWR_HOLD") (class "Default")
      (node (ref "D5") (pin "2") (pinfunction "A_2") (pintype "passive"))
      (node (ref "R30") (pin "1") (pinfunction "1_1") (pintype "passive"))
    )
    (net (code "185") (name "/PWR_HOLD_EXT") (class "Default")
      (node (ref "D9") (pin "2") (pinfunction "A_2") (pintype "passive"))
      (node (ref "R38") (pin "1") (pinfunction "1_1") (pintype "passive"))
    )
    (net (code "186") (name "/RGMII_CRS_DV") (class "Default")
      (node (ref "U1") (pin "AA31") (pinfunction "GPIOZ_4_AA31") (pintype "passive+no_connect"))
    )
    (net (code "187") (name "/RGMII_MDC") (class "Default")
      (node (ref "U1") (pin "AB30") (pinfunction "GPIOZ_1_AB30") (pintype "passive+no_connect"))
    )
    (net (code "188") (name "/RGMII_MDIO") (class "Default")
      (node (ref "U1") (pin "AB29") (pinfunction "GPIOZ_0_AB29") (pintype "passive+no_connect"))
    )
    (net (code "189") (name "/RGMII_RXCLK") (class "Default")
      (node (ref "U1") (pin "AB31") (pinfunction "GPIOZ_2_AB31") (pintype "passive+no_connect"))
    )
    (net (code "190") (name "/RTC_CLK") (class "Default")
      (node (ref "R15") (pin "2") (pinfunction "2_2") (pintype "passive"))
      (node (ref "U2") (pin "7") (pinfunction "CLKOUT_7") (pintype "output"))
    )
    (net (code "191") (name "/RTC_INT") (class "Default")
      (node (ref "R14") (pin "1") (pinfunction "1_1") (pintype "passive"))
      (node (ref "U2") (pin "3") (pinfunction "~{INT}_3") (pintype "output"))
      (node (ref "U3") (pin "17") (pinfunction "PB2_17") (pintype "bidirectional"))
    )
    (net (code "192") (name "/SDIO_CLK") (class "Default")
      (node (ref "R5") (pin "2") (pinfunction "2_2") (pintype "passive"))
      (node (ref "U1") (pin "A21") (pinfunction "GPIOX_4_A21") (pintype "passive"))
    )
    (net (code "193") (name "/SDPWR_EN") (class "Default")
      (node (ref "U1") (pin "A13") (pinfunction "GPIOD_11_A13") (pintype "passive+no_connect"))
    )
    (net (code "194") (name "/SOC_PWR_KEY") (class "Default")
      (node (ref "R22") (pin "2") (pinfunction "2_2") (pintype "passive"))
      (node (ref "R60") (pin "2") (pinfunction "2_2") (pintype "passive"))
      (node (ref "U1") (pin "B14") (pinfunction "GPIOD_4_B14") (pintype "passive"))
    )
    (net (code "195") (name "/SPDIF_OUT") (class "Default")
      (node (ref "U1") (pin "E11") (pinfunction "GPIOD_8_E11") (pintype "passive+no_connect"))
    )
    (net (code "196") (name "/SPIF_CS") (class "Default")
      (node (ref "B1") (pin "1") (pinfunction "/CS_1") (pintype "passive"))
      (node (ref "R41") (pin "1") (pinfunction "1_1") (pintype "passive"))
    )
    (net (code "197") (name "/SPINOR_EN") (class "Default")
      (node (ref "Q3") (pin "1") (pinfunction "G_1") (pintype "passive"))
      (node (ref "Q4") (pin "1") (pinfunction "G_1") (pintype "passive"))
      (node (ref "R46") (pin "1") (pinfunction "1_1") (pintype "passive"))
      (node (ref "U3") (pin "8") (pinfunction "PA1_8") (pintype "bidirectional"))
    )
    (net (code "198") (name "/SYS_LED") (class "Default")
      (node (ref "U1") (pin "D12") (pinfunction "GPIOD_6_D12") (pintype "passive+no_connect"))
    )
    (net (code "199") (name "/TP_I2CM_D_SCL") (class "Default")
      (node (ref "J3") (pin "34") (pinfunction "34_34") (pintype "passive"))
      (node (ref "U1") (pin "G33") (pinfunction "GPIOM_6_G33") (pintype "passive"))
    )
    (net (code "200") (name "/TP_I2CM_D_SDA") (class "Default")
      (node (ref "J3") (pin "33") (pinfunction "33_33") (pintype "passive"))
      (node (ref "U1") (pin "G32") (pinfunction "GPIOM_7_G32") (pintype "passive"))
    )
    (net (code "201") (name "/TP_INT") (class "Default")
      (node (ref "J3") (pin "36") (pinfunction "36_36") (pintype "passive"))
      (node (ref "U1") (pin "E27") (pinfunction "GPIOM_8_E27") (pintype "passive"))
    )
    (net (code "202") (name "/TP_RST") (class "Default")
      (node (ref "J3") (pin "37") (pinfunction "37_37") (pintype "passive"))
      (node (ref "U1") (pin "D27") (pinfunction "GPIOM_9_D27") (pintype "passive"))
    )
    (net (code "203") (name "/TYPEC_CC1") (class "Default")
      (node (ref "*") (pin "10") (pinfunction "CC1_1_10") (pintype "passive"))
      (node (ref "*") (pin "11") (pinfunction "CC1_2_11") (pintype "passive"))
      (node (ref "C140") (pin "1") (pinfunction "1_1") (pintype "passive"))
      (node (ref "D15") (pin "2") (pinfunction "2_2") (pintype "passive"))
      (node (ref "J7") (pin "A5") (pinfunction "CC1_A5") (pintype "passive"))
    )
    (net (code "204") (name "/TYPEC_CC2") (class "Default")
      (node (ref "*") (pin "1") (pinfunction "CC2_1_1") (pintype "passive"))
      (node (ref "*") (pin "14") (pinfunction "CC2_2_14") (pintype "passive"))
      (node (ref "C139") (pin "1") (pinfunction "1_1") (pintype "passive"))
      (node (ref "D16") (pin "2") (pinfunction "2_2") (pintype "passive"))
      (node (ref "J7") (pin "B5") (pinfunction "CC2_B5") (pintype "passive"))
    )
    (net (code "205") (name "/TYPEC_DM") (class "Default")
      (node (ref "D18") (pin "2") (pinfunction "2_2") (pintype "passive"))
      (node (ref "J7") (pin "A7") (pinfunction "DN1_A7") (pintype "passive"))
      (node (ref "J7") (pin "B7") (pinfunction "DN2_B7") (pintype "passive"))
      (node (ref "R76") (pin "2") (pinfunction "2_2") (pintype "passive"))
    )
    (net (code "206") (name "/TYPEC_DP") (class "Default")
      (node (ref "D17") (pin "2") (pinfunction "2_2") (pintype "passive"))
      (node (ref "J7") (pin "A6") (pinfunction "DP1_A6") (pintype "passive"))
      (node (ref "J7") (pin "B6") (pinfunction "DP2_B6") (pintype "passive"))
      (node (ref "R75") (pin "2") (pinfunction "2_2") (pintype "passive"))
    )
    (net (code "207") (name "/USBCC_INTn") (class "Default")
      (node (ref "*") (pin "5") (pinfunction "INT_N_5") (pintype "passive"))
      (node (ref "U1") (pin "AM20") (pinfunction "GPIOY_4_AM20") (pintype "passive"))
    )
    (net (code "208") (name "/USB_B_OTG_DM") (class "Default")
      (node (ref "R76") (pin "1") (pinfunction "1_1") (pintype "passive"))
      (node (ref "U1") (pin "C28") (pinfunction "USB_B_OTG_DM_C28") (pintype "passive"))
    )
    (net (code "209") (name "/USB_B_OTG_DP") (class "Default")
      (node (ref "R75") (pin "1") (pinfunction "1_1") (pintype "passive"))
      (node (ref "U1") (pin "D28") (pinfunction "USB_B_OTG_DP_D28") (pintype "passive"))
    )
    (net (code "210") (name "/VCC5V") (class "Default")
      (node (ref "*") (pin "12") (pinfunction "VCONN_1_12") (pintype "passive"))
      (node (ref "*") (pin "13") (pinfunction "VCONN_2_13") (pintype "passive"))
      (node (ref "C128") (pin "1") (pinfunction "1_1") (pintype "passive"))
      (node (ref "C129") (pin "1") (pinfunction "1_1") (pintype "passive"))
      (node (ref "J4") (pin "4") (pinfunction "4_4") (pintype "passive"))
      (node (ref "J6") (pin "1") (pinfunction "1_1") (pintype "passive"))
      (node (ref "U11") (pin "1") (pinfunction "VDD_1") (pintype "power_in"))
      (node (ref "U12") (pin "2") (pinfunction "GAIN_SLOT_2") (pintype "input"))
      (node (ref "U12") (pin "4") (pinfunction "SD_MODE_4") (pintype "input"))
      (node (ref "U12") (pin "7") (pinfunction "VDD_7") (pintype "power_in"))
      (node (ref "U12") (pin "8") (pinfunction "VDD_8") (pintype "power_in"))
      (node (ref "U13") (pin "1") (pinfunction "VDD_1") (pintype "power_in"))
      (node (ref "U14") (pin "1") (pinfunction "VDD_1") (pintype "power_in"))
      (node (ref "U17") (pin "1") (pinfunction "VDD_1") (pintype "power_in"))
      (node (ref "U18") (pin "1") (pinfunction "VDD_1") (pintype "power_in"))
      (node (ref "U19") (pin "1") (pinfunction "VDD_1") (pintype "power_in"))
      (node (ref "U20") (pin "1") (pinfunction "VDD_1") (pintype "power_in"))
      (node (ref "U21") (pin "1") (pinfunction "VDD_1") (pintype "power_in"))
      (node (ref "U22") (pin "1") (pinfunction "VDD_1") (pintype "power_in"))
      (node (ref "U23") (pin "1") (pinfunction "VDD_1") (pintype "power_in"))
      (node (ref "U24") (pin "1") (pinfunction "VDD_1") (pintype "power_in"))
      (node (ref "U25") (pin "1") (pinfunction "VDD_1") (pintype "power_in"))
      (node (ref "U26") (pin "1") (pinfunction "VDD_1") (pintype "power_in"))
      (node (ref "U8") (pin "1") (pinfunction "VDD_1") (pintype "power_in"))
      (node (ref "U9") (pin "1") (pinfunction "VDD_1") (pintype "power_in"))
    )
    (net (code "211") (name "/VCC5V_EN") (class "Default")
      (node (ref "J4") (pin "3") (pinfunction "3_3") (pintype "passive"))
      (node (ref "U1") (pin "R32") (pinfunction "GPIOH_4_R32") (pintype "passive"))
    )
    (net (code "212") (name "/VCC_MCU") (class "Default")
      (node (ref "C122") (pin "1") (pinfunction "1_1") (pintype "passive"))
      (node (ref "D1") (pin "2") (pinfunction "A_2") (pintype "passive"))
      (node (ref "J4") (pin "5") (pinfunction "5_5") (pintype "passive"))
      (node (ref "Q2") (pin "3") (pinfunction "D_3") (pintype "passive"))
      (node (ref "R14") (pin "2") (pinfunction "2_2") (pintype "passive"))
      (node (ref "R27") (pin "2") (pinfunction "2_2") (pintype "passive"))
      (node (ref "R28") (pin "2") (pinfunction "2_2") (pintype "passive"))
      (node (ref "R59") (pin "1") (pinfunction "1_1") (pintype "passive"))
      (node (ref "R68") (pin "2") (pinfunction "2_2") (pintype "passive"))
      (node (ref "U3") (pin "4") (pinfunction "VDD_4") (pintype "power_in"))
      (node (ref "U6") (pin "8") (pinfunction "IN1_8") (pintype "power_in"))
    )
    (net (code "213") (name "/VDDAO_1V8") (class "Default")
      (node (ref "C10") (pin "1") (pinfunction "1_1") (pintype "passive"))
      (node (ref "C11") (pin "1") (pinfunction "1_1") (pintype "passive"))
      (node (ref "C13") (pin "1") (pinfunction "1_1") (pintype "passive"))
      (node (ref "C4") (pin "1") (pinfunction "1_1") (pintype "passive"))
      (node (ref "C5") (pin "1") (pinfunction "1_1") (pintype "passive"))
      (node (ref "C7") (pin "1") (pinfunction "1_1") (pintype "passive"))
      (node (ref "C8") (pin "1") (pinfunction "1_1") (pintype "passive"))
      (node (ref "J3") (pin "39") (pinfunction "39_39") (pintype "passive"))
      (node (ref "J4") (pin "13") (pinfunction "13_13") (pintype "passive"))
      (node (ref "L3") (pin "2") (pinfunction "2_2") (pintype "passive"))
      (node (ref "L6") (pin "1") (pinfunction "1_1") (pintype "passive"))
      (node (ref "R19") (pin "2") (pinfunction "2_2") (pintype "passive"))
      (node (ref "U1") (pin "AB25") (pinfunction "AVDD18_ENET_AB25") (pintype "passive"))
      (node (ref "U1") (pin "AK18") (pinfunction "VDD18_AO_AK18") (pintype "passive"))
      (node (ref "U1") (pin "AL11") (pinfunction "AVDD18_DDR_DP_PLL_AL11") (pintype "passive"))
      (node (ref "U1") (pin "G16") (pinfunction "VDD18_AO_G16") (pintype "passive"))
      (node (ref "U1") (pin "H16") (pinfunction "VDDIO_E_H16") (pintype "passive"))
      (node (ref "U1") (pin "H25") (pinfunction "AVDD18_MCLK_H25") (pintype "passive"))
      (node (ref "U1") (pin "K17") (pinfunction "AVDD18_PLL_K17") (pintype "passive"))
      (node (ref "U1") (pin "M25") (pinfunction "AVDD18_CSI_M25") (pintype "passive"))
      (node (ref "U1") (pin "Y25") (pinfunction "AVDD18_SARADC_Y25") (pintype "passive"))
    )
    (net (code "214") (name "/VDDAO_3V3") (class "Default")
      (node (ref "*") (pin "3") (pinfunction "VDD_1_3") (pintype "passive"))
      (node (ref "*") (pin "4") (pinfunction "VDD_2_4") (pintype "passive"))
      (node (ref "C1") (pin "1") (pinfunction "1_1") (pintype "passive"))
      (node (ref "C123") (pin "1") (pinfunction "1_1") (pintype "passive"))
      (node (ref "J3") (pin "31") (pinfunction "31_31") (pintype "passive"))
      (node (ref "J3") (pin "32") (pinfunction "32_32") (pintype "passive"))
      (node (ref "J4") (pin "2") (pinfunction "2_2") (pintype "passive"))
      (node (ref "R15") (pin "1") (pinfunction "1_1") (pintype "passive"))
      (node (ref "R17") (pin "2") (pinfunction "2_2") (pintype "passive"))
      (node (ref "R2") (pin "1") (pinfunction "1_1") (pintype "passive"))
      (node (ref "R20") (pin "2") (pinfunction "2_2") (pintype "passive"))
      (node (ref "R23") (pin "2") (pinfunction "2_2") (pintype "passive"))
      (node (ref "R29") (pin "2") (pinfunction "2_2") (pintype "passive"))
      (node (ref "R36") (pin "1") (pinfunction "1_1") (pintype "passive"))
      (node (ref "R37") (pin "2") (pinfunction "2_2") (pintype "passive"))
      (node (ref "R57") (pin "2") (pinfunction "2_2") (pintype "passive"))
      (node (ref "U1") (pin "F9") (pinfunction "VDDIO_D_F9") (pintype "passive"))
      (node (ref "U6") (pin "6") (pinfunction "IN2_6") (pintype "power_in"))
    )
    (net (code "215") (name "/VDDAO_3V3_POR") (class "Default")
      (node (ref "C3") (pin "1") (pinfunction "1_1") (pintype "passive"))
      (node (ref "U1") (pin "F20") (pinfunction "AVDD33_POR_F20") (pintype "passive"))
    )
    (net (code "216") (name "/VDDCPU_A") (class "Default")
      (node (ref "C24") (pin "1") (pinfunction "1_1") (pintype "passive"))
      (node (ref "C25") (pin "1") (pinfunction "1_1") (pintype "passive"))
      (node (ref "C26") (pin "1") (pinfunction "1_1") (pintype "passive"))
      (node (ref "C27") (pin "1") (pinfunction "1_1") (pintype "passive"))
      (node (ref "C28") (pin "1") (pinfunction "1_1") (pintype "passive"))
      (node (ref "C29") (pin "1") (pinfunction "1_1") (pintype "passive"))
      (node (ref "C30") (pin "1") (pinfunction "1_1") (pintype "passive"))
      (node (ref "C31") (pin "1") (pinfunction "1_1") (pintype "passive"))
      (node (ref "C55") (pin "1") (pinfunction "1_1") (pintype "passive"))
      (node (ref "C56") (pin "1") (pinfunction "1_1") (pintype "passive"))
      (node (ref "C57") (pin "1") (pinfunction "1_1") (pintype "passive"))
      (node (ref "C58") (pin "1") (pinfunction "1_1") (pintype "passive"))
      (node (ref "C59") (pin "1") (pinfunction "1_1") (pintype "passive"))
      (node (ref "C60") (pin "1") (pinfunction "1_1") (pintype "passive"))
      (node (ref "C61") (pin "1") (pinfunction "1_1") (pintype "passive"))
      (node (ref "C62") (pin "1") (pinfunction "1_1") (pintype "passive"))
      (node (ref "J4") (pin "15") (pinfunction "15_15") (pintype "passive"))
      (node (ref "U1") (pin "G12") (pinfunction "VDDCPU_A_G12") (pintype "passive"))
      (node (ref "U1") (pin "H12") (pinfunction "VDDCPU_A_H12") (pintype "passive"))
      (node (ref "U1") (pin "H13") (pinfunction "VDDCPU_A_H13") (pintype "passive"))
      (node (ref "U1") (pin "H15") (pinfunction "VDDCPU_A_H15") (pintype "passive"))
      (node (ref "U1") (pin "J12") (pinfunction "VDDCPU_A_J12") (pintype "passive"))
      (node (ref "U1") (pin "J15") (pinfunction "VDDCPU_A_J15") (pintype "passive"))
      (node (ref "U1") (pin "K12") (pinfunction "VDDCPU_A_K12") (pintype "passive"))
      (node (ref "U1") (pin "K13") (pinfunction "VDDCPU_A_K13") (pintype "passive"))
      (node (ref "U1") (pin "K15") (pinfunction "VDDCPU_A_K15") (pintype "passive"))
      (node (ref "U1") (pin "K16") (pinfunction "VDDCPU_A_K16") (pintype "passive"))
      (node (ref "U1") (pin "L12") (pinfunction "VDDCPU_A_L12") (pintype "passive"))
      (node (ref "U1") (pin "L15") (pinfunction "VDDCPU_A_L15") (pintype "passive"))
      (node (ref "U1") (pin "M12") (pinfunction "VDDCPU_A_M12") (pintype "passive"))
      (node (ref "U1") (pin "M13") (pinfunction "VDDCPU_A_M13") (pintype "passive"))
      (node (ref "U1") (pin "M15") (pinfunction "VDDCPU_A_M15") (pintype "passive"))
      (node (ref "U1") (pin "M16") (pinfunction "VDDCPU_A_M16") (pintype "passive"))
      (node (ref "U1") (pin "N12") (pinfunction "VDDCPU_A_N12") (pintype "passive"))
      (node (ref "U1") (pin "P12") (pinfunction "VDDCPU_A_P12") (pintype "passive"))
      (node (ref "U1") (pin "P13") (pinfunction "VDDCPU_A_P13") (pintype "passive"))
      (node (ref "U1") (pin "P15") (pinfunction "VDDCPU_A_P15") (pintype "passive"))
      (node (ref "U1") (pin "P16") (pinfunction "VDDCPU_A_P16") (pintype "passive"))
      (node (ref "U1") (pin "R12") (pinfunction "VDDCPU_A_R12") (pintype "passive"))
      (node (ref "U1") (pin "R15") (pinfunction "VDDCPU_A_R15") (pintype "passive"))
      (node (ref "U1") (pin "T12") (pinfunction "VDDCPU_A_T12") (pintype "passive"))
      (node (ref "U1") (pin "T13") (pinfunction "VDDCPU_A_T13") (pintype "passive"))
      (node (ref "U1") (pin "T15") (pinfunction "VDDCPU_A_T15") (pintype "passive"))
      (node (ref "U1") (pin "T16") (pinfunction "VDDCPU_A_T16") (pintype "passive"))
    )
    (net (code "217") (name "/VDDCPU_A_PWM") (class "Default")
      (node (ref "J4") (pin "16") (pinfunction "16_16") (pintype "passive"))
      (node (ref "U1") (pin "C14") (pinfunction "GPIOE_3_C14") (pintype "passive"))
    )
    (net (code "218") (name "/VDDCPU_B") (class "Default")
      (node (ref "C63") (pin "1") (pinfunction "1_1") (pintype "passive"))
      (node (ref "C64") (pin "1") (pinfunction "1_1") (pintype "passive"))
      (node (ref "C65") (pin "1") (pinfunction "1_1") (pintype "passive"))
      (node (ref "C66") (pin "1") (pinfunction "1_1") (pintype "passive"))
      (node (ref "C67") (pin "1") (pinfunction "1_1") (pintype "passive"))
      (node (ref "C68") (pin "1") (pinfunction "1_1") (pintype "passive"))
      (node (ref "C69") (pin "1") (pinfunction "1_1") (pintype "passive"))
      (node (ref "C70") (pin "1") (pinfunction "1_1") (pintype "passive"))
      (node (ref "U1") (pin "AA12") (pinfunction "VDDCPU_B_AA12") (pintype "passive"))
      (node (ref "U1") (pin "AA13") (pinfunction "VDDCPU_B_AA13") (pintype "passive"))
      (node (ref "U1") (pin "AA15") (pinfunction "VDDCPU_B_AA15") (pintype "passive"))
      (node (ref "U1") (pin "AA16") (pinfunction "VDDCPU_B_AA16") (pintype "passive"))
      (node (ref "U1") (pin "AB12") (pinfunction "VDDCPU_B_AB12") (pintype "passive"))
      (node (ref "U1") (pin "AB15") (pinfunction "VDDCPU_B_AB15") (pintype "passive"))
      (node (ref "U1") (pin "AC12") (pinfunction "VDDCPU_B_AC12") (pintype "passive"))
      (node (ref "U1") (pin "AC13") (pinfunction "VDDCPU_B_AC13") (pintype "passive"))
      (node (ref "U1") (pin "AC15") (pinfunction "VDDCPU_B_AC15") (pintype "passive"))
      (node (ref "U1") (pin "AC16") (pinfunction "VDDCPU_B_AC16") (pintype "passive"))
      (node (ref "U1") (pin "AD12") (pinfunction "VDDCPU_B_AD12") (pintype "passive"))
      (node (ref "U1") (pin "AD15") (pinfunction "VDDCPU_B_AD15") (pintype "passive"))
      (node (ref "U1") (pin "AE12") (pinfunction "VDDCPU_B_AE12") (pintype "passive"))
      (node (ref "U1") (pin "AE13") (pinfunction "VDDCPU_B_AE13") (pintype "passive"))
      (node (ref "U1") (pin "AE15") (pinfunction "VDDCPU_B_AE15") (pintype "passive"))
      (node (ref "U1") (pin "AE16") (pinfunction "VDDCPU_B_AE16") (pintype "passive"))
      (node (ref "U1") (pin "AF12") (pinfunction "VDDCPU_B_AF12") (pintype "passive"))
      (node (ref "U1") (pin "AG12") (pinfunction "VDDCPU_B_AG12") (pintype "passive"))
      (node (ref "U1") (pin "AG13") (pinfunction "VDDCPU_B_AG13") (pintype "passive"))
    )
    (net (code "219") (name "/VDDCPU_B_EN") (class "Default")
      (node (ref "R2") (pin "2") (pinfunction "2_2") (pintype "passive"))
      (node (ref "U1") (pin "F14") (pinfunction "TEST_N_F14") (pintype "passive"))
    )
    (net (code "220") (name "/VDDCPU_B_PWM") (class "Default")
      (node (ref "J4") (pin "21") (pinfunction "21_21") (pintype "passive"))
      (node (ref "U1") (pin "E15") (pinfunction "GPIOE_1_E15") (pintype "passive"))
    )
    (net (code "221") (name "/VDDDDR_PWM") (class "Default")
      (node (ref "J4") (pin "23") (pinfunction "23_23") (pintype "passive"))
      (node (ref "U1") (pin "F17") (pinfunction "GPIOE_6_F17") (pintype "passive"))
    )
    (net (code "222") (name "/VDDEE_MODE") (class "Default")
      (node (ref "J4") (pin "12") (pinfunction "12_12") (pintype "passive+no_connect"))
    )
    (net (code "223") (name "/VDDEE_PWM") (class "Default")
      (node (ref "J4") (pin "11") (pinfunction "11_11") (pintype "passive"))
      (node (ref "U1") (pin "C17") (pinfunction "GPIOE_0_C17") (pintype "passive"))
    )
    (net (code "224") (name "/VDDGPU_MODE") (class "Default")
      (node (ref "J4") (pin "8") (pinfunction "8_8") (pintype "passive+no_connect"))
    )
    (net (code "225") (name "/VDDGPU_PWM") (class "Default")
      (node (ref "J4") (pin "7") (pinfunction "7_7") (pintype "passive"))
      (node (ref "U1") (pin "C15") (pinfunction "GPIOE_4_C15") (pintype "passive"))
    )
    (net (code "226") (name "/VDDIOC_SW") (class "Default")
      (node (ref "J4") (pin "20") (pinfunction "20_20") (pintype "passive"))
      (node (ref "U1") (pin "C12") (pinfunction "GPIOD_9_C12") (pintype "passive"))
      (node (ref "U1") (pin "U26") (pinfunction "VDDIO_C_U26") (pintype "passive"))
    )
    (net (code "227") (name "/VDDIO_1V8") (class "Default")
      (node (ref "J2") (pin "25") (pinfunction "25_25") (pintype "passive"))
      (node (ref "J4") (pin "9") (pinfunction "9_9") (pintype "passive"))
      (node (ref "L2") (pin "2") (pinfunction "2_2") (pintype "passive"))
    )
    (net (code "228") (name "/VDDIO_3V3") (class "Default")
      (node (ref "J2") (pin "28") (pinfunction "28_28") (pintype "passive"))
      (node (ref "J2") (pin "29") (pinfunction "29_29") (pintype "passive"))
      (node (ref "J2") (pin "30") (pinfunction "30_30") (pintype "passive"))
      (node (ref "J3") (pin "17") (pinfunction "17_17") (pintype "passive"))
      (node (ref "J3") (pin "18") (pinfunction "18_18") (pintype "passive"))
      (node (ref "U1") (pin "AJ17") (pinfunction "VDDIO_Y_AJ17") (pintype "passive"))
      (node (ref "U1") (pin "R25") (pinfunction "VDDIO_T_R25") (pintype "passive"))
      (node (ref "U5") (pin "C6") (pinfunction "VDD_C6") (pintype "power_in"))
      (node (ref "U5") (pin "M4") (pinfunction "VDD_M4") (pintype "power_in"))
      (node (ref "U5") (pin "N4") (pinfunction "VDD_N4") (pintype "power_in"))
      (node (ref "U5") (pin "P3") (pinfunction "VDD_P3") (pintype "power_in"))
      (node (ref "U5") (pin "P5") (pinfunction "VDD_P5") (pintype "power_in"))
    )
    (net (code "229") (name "/VDDIO_BOOT") (class "Default")
      (node (ref "B1") (pin "8") (pinfunction "VCC_8") (pintype "passive"))
      (node (ref "C80") (pin "2") (pinfunction "2_2") (pintype "passive"))
      (node (ref "R41") (pin "2") (pinfunction "2_2") (pintype "passive"))
      (node (ref "R42") (pin "2") (pinfunction "2_2") (pintype "passive"))
      (node (ref "R45") (pin "1") (pinfunction "1_1") (pintype "passive"))
      (node (ref "R48") (pin "2") (pinfunction "2_2") (pintype "passive"))
      (node (ref "U5") (pin "E6") (pinfunction "VDDF_E6") (pintype "power_in"))
      (node (ref "U5") (pin "F5") (pinfunction "VDDF_F5") (pintype "power_in"))
      (node (ref "U5") (pin "J10") (pinfunction "VDDF_J10") (pintype "power_in"))
      (node (ref "U5") (pin "K9") (pinfunction "VDDF_K9") (pintype "power_in"))
    )
    (net (code "230") (name "/VDDIO_H") (class "Default")
      (node (ref "U1") (pin "V25") (pinfunction "VDDIO_H_V25") (pintype "passive+no_connect"))
    )
    (net (code "231") (name "/VDDIO_LX") (class "Default")
      (node (ref "R61") (pin "1") (pinfunction "1_1") (pintype "passive"))
      (node (ref "R62") (pin "1") (pinfunction "1_1") (pintype "passive"))
    )
    (net (code "232") (name "/VDDIO_M") (class "Default")
      (node (ref "L2") (pin "1") (pinfunction "1_1") (pintype "passive"))
      (node (ref "L3") (pin "1") (pinfunction "1_1") (pintype "passive"))
      (node (ref "U1") (pin "L25") (pinfunction "VDDIO_M_L25") (pintype "passive"))
    )
    (net (code "233") (name "/VDDIO_X") (class "Default")
      (node (ref "R51") (pin "2") (pinfunction "2_2") (pintype "passive"))
      (node (ref "U1") (pin "G18") (pinfunction "VDDIO_X_G18") (pintype "passive"))
    )
    (net (code "234") (name "/VDDIO_Z") (class "Default")
      (node (ref "U1") (pin "T28") (pinfunction "VDDIO_Z_T28") (pintype "passive+no_connect"))
    )
    (net (code "235") (name "/VDDNPU_PWM") (class "Default")
      (node (ref "U1") (pin "F18") (pinfunction "GPIOE_5_F18") (pintype "passive+no_connect"))
    )
    (net (code "236") (name "/VDDQLP_0V6_1V1") (class "Default")
      (node (ref "J4") (pin "25") (pinfunction "25_25") (pintype "passive"))
      (node (ref "U1") (pin "AA8") (pinfunction "VDDQ_AA8") (pintype "passive"))
      (node (ref "U1") (pin "AB8") (pinfunction "VDDQLP_AB8") (pintype "passive"))
      (node (ref "U1") (pin "AB9") (pinfunction "VDDQ_AB9") (pintype "passive"))
      (node (ref "U1") (pin "AC5") (pinfunction "VDDQLP_AC5") (pintype "passive"))
      (node (ref "U1") (pin "AD6") (pinfunction "VDDQLP_AD6") (pintype "passive"))
      (node (ref "U1") (pin "AD8") (pinfunction "VDDQ_AD8") (pintype "passive"))
      (node (ref "U1") (pin "AE9") (pinfunction "VDDQ_AE9") (pintype "passive"))
      (node (ref "U1") (pin "AG8") (pinfunction "VDDQ_AG8") (pintype "passive"))
      (node (ref "U1") (pin "AH9") (pinfunction "VDDQ_AH9") (pintype "passive"))
      (node (ref "U1") (pin "AK8") (pinfunction "VDDQ_AK8") (pintype "passive"))
      (node (ref "U1") (pin "AL9") (pinfunction "VDDQ_AL9") (pintype "passive"))
      (node (ref "U1") (pin "G9") (pinfunction "VDDQ_G9") (pintype "passive"))
      (node (ref "U1") (pin "H8") (pinfunction "VDDQ_H8") (pintype "passive"))
      (node (ref "U1") (pin "K9") (pinfunction "VDDQ_K9") (pintype "passive"))
      (node (ref "U1") (pin "L8") (pinfunction "VDDQ_L8") (pintype "passive"))
      (node (ref "U1") (pin "M6") (pinfunction "VDDQLP_M6") (pintype "passive"))
      (node (ref "U1") (pin "N9") (pinfunction "VDDQ_N9") (pintype "passive"))
      (node (ref "U1") (pin "P8") (pinfunction "VDDQ_P8") (pintype "passive"))
      (node (ref "U1") (pin "T6") (pinfunction "VDDQLP_T6") (pintype "passive"))
      (node (ref "U1") (pin "T9") (pinfunction "VDDQ_T9") (pintype "passive"))
      (node (ref "U1") (pin "U5") (pinfunction "VDDQLP_U5") (pintype "passive"))
      (node (ref "U1") (pin "U8") (pinfunction "VDDQ_U8") (pintype "passive"))
      (node (ref "U1") (pin "W8") (pinfunction "VDDQLP_W8") (pintype "passive"))
      (node (ref "U1") (pin "W9") (pinfunction "VDDQLP_W9") (pintype "passive"))
    )
    (net (code "237") (name "/VDDQLP¨_0V6_1V1") (class "Default")
      (node (ref "C113") (pin "1") (pinfunction "1_1") (pintype "passive"))
      (node (ref "C114") (pin "1") (pinfunction "1_1") (pintype "passive"))
      (node (ref "C115") (pin "1") (pinfunction "1_1") (pintype "passive"))
      (node (ref "C116") (pin "1") (pinfunction "1_1") (pintype "passive"))
      (node (ref "C117") (pin "1") (pinfunction "1_1") (pintype "passive"))
      (node (ref "C118") (pin "1") (pinfunction "1_1") (pintype "passive"))
      (node (ref "C119") (pin "1") (pinfunction "1_1") (pintype "passive"))
      (node (ref "C120") (pin "1") (pinfunction "1_1") (pintype "passive"))
      (node (ref "C89") (pin "1") (pinfunction "1_1") (pintype "passive"))
      (node (ref "C90") (pin "1") (pinfunction "1_1") (pintype "passive"))
      (node (ref "C91") (pin "1") (pinfunction "1_1") (pintype "passive"))
      (node (ref "C92") (pin "1") (pinfunction "1_1") (pintype "passive"))
      (node (ref "C93") (pin "1") (pinfunction "1_1") (pintype "passive"))
      (node (ref "C94") (pin "1") (pinfunction "1_1") (pintype "passive"))
      (node (ref "C95") (pin "1") (pinfunction "1_1") (pintype "passive"))
      (node (ref "C96") (pin "1") (pinfunction "1_1") (pintype "passive"))
    )
    (net (code "238") (name "/VDDQ_1V1") (class "Default")
      (node (ref "C105") (pin "1") (pinfunction "1_1") (pintype "passive"))
      (node (ref "C106") (pin "1") (pinfunction "1_1") (pintype "passive"))
      (node (ref "C107") (pin "1") (pinfunction "1_1") (pintype "passive"))
      (node (ref "C108") (pin "1") (pinfunction "1_1") (pintype "passive"))
      (node (ref "C109") (pin "1") (pinfunction "1_1") (pintype "passive"))
      (node (ref "C110") (pin "1") (pinfunction "1_1") (pintype "passive"))
      (node (ref "C111") (pin "1") (pinfunction "1_1") (pintype "passive"))
      (node (ref "C112") (pin "1") (pinfunction "1_1") (pintype "passive"))
      (node (ref "C81") (pin "1") (pinfunction "1_1") (pintype "passive"))
      (node (ref "C82") (pin "1") (pinfunction "1_1") (pintype "passive"))
      (node (ref "C83") (pin "1") (pinfunction "1_1") (pintype "passive"))
      (node (ref "C84") (pin "1") (pinfunction "1_1") (pintype "passive"))
      (node (ref "C85") (pin "1") (pinfunction "1_1") (pintype "passive"))
      (node (ref "C86") (pin "1") (pinfunction "1_1") (pintype "passive"))
      (node (ref "C87") (pin "1") (pinfunction "1_1") (pintype "passive"))
      (node (ref "C88") (pin "1") (pinfunction "1_1") (pintype "passive"))
      (node (ref "J4") (pin "19") (pinfunction "19_19") (pintype "passive"))
      (node (ref "U4") (pin "A4") (pinfunction "VDD2_1_A4") (pintype "passive"))
      (node (ref "U4") (pin "A9") (pinfunction "VDD2_2_A9") (pintype "passive"))
      (node (ref "U4") (pin "AB4") (pinfunction "VDD2_23_AB4") (pintype "passive"))
      (node (ref "U4") (pin "F5") (pinfunction "VDD2_3_F5") (pintype "passive"))
      (node (ref "U4") (pin "F8") (pinfunction "VDD2_4_F8") (pintype "passive"))
      (node (ref "U4") (pin "G2") (pinfunction "ODT_CA_A_G2") (pintype "passive"))
      (node (ref "U4") (pin "H1") (pinfunction "VDD2_5_H1") (pintype "passive"))
      (node (ref "U4") (pin "H12") (pinfunction "VDD2_8_H12") (pintype "passive"))
      (node (ref "U4") (pin "H5") (pinfunction "VDD2_6_H5") (pintype "passive"))
      (node (ref "U4") (pin "H8") (pinfunction "VDD2_7_H8") (pintype "passive"))
      (node (ref "U4") (pin "K1") (pinfunction "VDD2_9_K1") (pintype "passive"))
      (node (ref "U4") (pin "K10") (pinfunction "VDD2_11_K10") (pintype "passive"))
      (node (ref "U4") (pin "K12") (pinfunction "VDD2_12_K12") (pintype "passive"))
      (node (ref "U4") (pin "K3") (pinfunction "VDD2_10_K3") (pintype "passive"))
      (node (ref "U4") (pin "N1") (pinfunction "VDD2_13_N1") (pintype "passive"))
      (node (ref "U4") (pin "N10") (pinfunction "VDD2_15_N10") (pintype "passive"))
      (node (ref "U4") (pin "N12") (pinfunction "VDD2_16_N12") (pintype "passive"))
      (node (ref "U4") (pin "N3") (pinfunction "VDD2_14_N3") (pintype "passive"))
      (node (ref "U4") (pin "R1") (pinfunction "VDD2_17_R1") (pintype "passive"))
      (node (ref "U4") (pin "R12") (pinfunction "VDD2_20_R12") (pintype "passive"))
      (node (ref "U4") (pin "R5") (pinfunction "VDD2_18_R5") (pintype "passive"))
      (node (ref "U4") (pin "R8") (pinfunction "VDD2_19_R8") (pintype "passive"))
      (node (ref "U4") (pin "T2") (pinfunction "ODT_CA_B_T2") (pintype "passive"))
      (node (ref "U4") (pin "U5") (pinfunction "VDD2_21_U5") (pintype "passive"))
      (node (ref "U4") (pin "U8") (pinfunction "VDD2_22_U8") (pintype "passive"))
    )
    (net (code "239") (name "/VDDQ_VDDQLP_EN") (class "Default")
      (node (ref "U1") (pin "D14") (pinfunction "GPIOD_10_D14") (pintype "passive+no_connect"))
    )
    (net (code "240") (name "/VDD_DDR") (class "Default")
      (node (ref "C100") (pin "1") (pinfunction "1_1") (pintype "passive"))
      (node (ref "C101") (pin "1") (pinfunction "1_1") (pintype "passive"))
      (node (ref "C102") (pin "1") (pinfunction "1_1") (pintype "passive"))
      (node (ref "C103") (pin "1") (pinfunction "1_1") (pintype "passive"))
      (node (ref "C104") (pin "1") (pinfunction "1_1") (pintype "passive"))
      (node (ref "C97") (pin "1") (pinfunction "1_1") (pintype "passive"))
      (node (ref "C98") (pin "1") (pinfunction "1_1") (pintype "passive"))
      (node (ref "C99") (pin "1") (pinfunction "1_1") (pintype "passive"))
      (node (ref "J4") (pin "24") (pinfunction "24_24") (pintype "passive"))
      (node (ref "U1") (pin "AA10") (pinfunction "VDD_DDR_AA10") (pintype "passive"))
      (node (ref "U1") (pin "AC11") (pinfunction "VDD_DDR_AC11") (pintype "passive"))
      (node (ref "U1") (pin "AD10") (pinfunction "VDD_DDR_AD10") (pintype "passive"))
      (node (ref "U1") (pin "AE8") (pinfunction "AVDD_DDR1PLL_AE8") (pintype "passive"))
      (node (ref "U1") (pin "AF11") (pinfunction "VDD_DDR_AF11") (pintype "passive"))
      (node (ref "U1") (pin "AG10") (pinfunction "VDD_DDR_AG10") (pintype "passive"))
      (node (ref "U1") (pin "AJ11") (pinfunction "VDD_DDR_AJ11") (pintype "passive"))
      (node (ref "U1") (pin "AK10") (pinfunction "VDD_DDR_AK10") (pintype "passive"))
      (node (ref "U1") (pin "H10") (pinfunction "VDD_DDR_H10") (pintype "passive"))
      (node (ref "U1") (pin "J11") (pinfunction "VDD_DDR_J11") (pintype "passive"))
      (node (ref "U1") (pin "L10") (pinfunction "VDD_DDR_L10") (pintype "passive"))
      (node (ref "U1") (pin "M11") (pinfunction "VDD_DDR_M11") (pintype "passive"))
      (node (ref "U1") (pin "P10") (pinfunction "VDD_DDR_P10") (pintype "passive"))
      (node (ref "U1") (pin "R11") (pinfunction "VDD_DDR_R11") (pintype "passive"))
      (node (ref "U1") (pin "U10") (pinfunction "VDD_DDR_U10") (pintype "passive"))
      (node (ref "U1") (pin "V11") (pinfunction "VDD_DDR_V11") (pintype "passive"))
      (node (ref "U1") (pin "Y11") (pinfunction "VDD_DDR_Y11") (pintype "passive"))
    )
    (net (code "241") (name "/VDD_EE") (class "Default")
      (node (ref "C16") (pin "1") (pinfunction "1_1") (pintype "passive"))
      (node (ref "C17") (pin "1") (pinfunction "1_1") (pintype "passive"))
      (node (ref "C18") (pin "1") (pinfunction "1_1") (pintype "passive"))
      (node (ref "C19") (pin "1") (pinfunction "1_1") (pintype "passive"))
      (node (ref "C20") (pin "1") (pinfunction "1_1") (pintype "passive"))
      (node (ref "C21") (pin "1") (pinfunction "1_1") (pintype "passive"))
      (node (ref "C22") (pin "1") (pinfunction "1_1") (pintype "passive"))
      (node (ref "J4") (pin "10") (pinfunction "10_10") (pintype "passive"))
      (node (ref "U1") (pin "AD18") (pinfunction "VDD_EE_AD18") (pintype "passive"))
      (node (ref "U1") (pin "AD20") (pinfunction "VDD_EE_AD20") (pintype "passive"))
      (node (ref "U1") (pin "AE18") (pinfunction "VDD_EE_AE18") (pintype "passive"))
      (node (ref "U1") (pin "AE19") (pinfunction "VDD_EE_AE19") (pintype "passive"))
      (node (ref "U1") (pin "AE20") (pinfunction "VDD_EE_AE20") (pintype "passive"))
      (node (ref "U1") (pin "AG19") (pinfunction "VDD_EE_AG19") (pintype "passive"))
      (node (ref "U1") (pin "AG21") (pinfunction "VDD_EE_AG21") (pintype "passive"))
      (node (ref "U1") (pin "AG23") (pinfunction "VDD_EE_AG23") (pintype "passive"))
      (node (ref "U1") (pin "AH19") (pinfunction "VDD_EE_AH19") (pintype "passive"))
      (node (ref "U1") (pin "AH20") (pinfunction "VDD_EE_AH20") (pintype "passive"))
      (node (ref "U1") (pin "AH21") (pinfunction "VDD_EE_AH21") (pintype "passive"))
      (node (ref "U1") (pin "AH22") (pinfunction "VDD_EE_AH22") (pintype "passive"))
      (node (ref "U1") (pin "AH23") (pinfunction "VDD_EE_AH23") (pintype "passive"))
      (node (ref "U1") (pin "J19") (pinfunction "VDD_EE_J19") (pintype "passive"))
      (node (ref "U1") (pin "J20") (pinfunction "VDD_EE_J20") (pintype "passive"))
      (node (ref "U1") (pin "K19") (pinfunction "VDD_EE_K19") (pintype "passive"))
      (node (ref "U1") (pin "K20") (pinfunction "VDD_EE_K20") (pintype "passive"))
      (node (ref "U1") (pin "K21") (pinfunction "VDD_EE_K21") (pintype "passive"))
      (node (ref "U1") (pin "V14") (pinfunction "VDD_EE_V14") (pintype "passive"))
      (node (ref "U1") (pin "V16") (pinfunction "VDD_EE_V16") (pintype "passive"))
      (node (ref "U1") (pin "W13") (pinfunction "VDD_EE_W13") (pintype "passive"))
      (node (ref "U1") (pin "W14") (pinfunction "VDD_EE_W14") (pintype "passive"))
      (node (ref "U1") (pin "W15") (pinfunction "VDD_EE_W15") (pintype "passive"))
      (node (ref "U1") (pin "W16") (pinfunction "VDD_EE_W16") (pintype "passive"))
      (node (ref "U1") (pin "W17") (pinfunction "VDD_EE_W17") (pintype "passive"))
    )
    (net (code "242") (name "/VDD_GPU") (class "Default")
      (node (ref "C32") (pin "1") (pinfunction "1_1") (pintype "passive"))
      (node (ref "C33") (pin "1") (pinfunction "1_1") (pintype "passive"))
      (node (ref "C34") (pin "1") (pinfunction "1_1") (pintype "passive"))
      (node (ref "C35") (pin "1") (pinfunction "1_1") (pintype "passive"))
      (node (ref "C36") (pin "1") (pinfunction "1_1") (pintype "passive"))
      (node (ref "C37") (pin "1") (pinfunction "1_1") (pintype "passive"))
      (node (ref "C38") (pin "1") (pinfunction "1_1") (pintype "passive"))
      (node (ref "C39") (pin "1") (pinfunction "1_1") (pintype "passive"))
      (node (ref "J4") (pin "6") (pinfunction "6_6") (pintype "passive"))
      (node (ref "U1") (pin "M18") (pinfunction "VDD_GPU_M18") (pintype "passive"))
      (node (ref "U1") (pin "M19") (pinfunction "VDD_GPU_M19") (pintype "passive"))
      (node (ref "U1") (pin "M20") (pinfunction "VDD_GPU_M20") (pintype "passive"))
      (node (ref "U1") (pin "M21") (pinfunction "VDD_GPU_M21") (pintype "passive"))
      (node (ref "U1") (pin "M22") (pinfunction "VDD_GPU_M22") (pintype "passive"))
      (node (ref "U1") (pin "M23") (pinfunction "VDD_GPU_M23") (pintype "passive"))
      (node (ref "U1") (pin "N18") (pinfunction "VDD_GPU_N18") (pintype "passive"))
      (node (ref "U1") (pin "N20") (pinfunction "VDD_GPU_N20") (pintype "passive"))
      (node (ref "U1") (pin "N22") (pinfunction "VDD_GPU_N22") (pintype "passive"))
      (node (ref "U1") (pin "P24") (pinfunction "VDD_GPU_P24") (pintype "passive"))
      (node (ref "U1") (pin "R18") (pinfunction "VDD_GPU_R18") (pintype "passive"))
      (node (ref "U1") (pin "R19") (pinfunction "VDD_GPU_R19") (pintype "passive"))
      (node (ref "U1") (pin "R20") (pinfunction "VDD_GPU_R20") (pintype "passive"))
      (node (ref "U1") (pin "R21") (pinfunction "VDD_GPU_R21") (pintype "passive"))
      (node (ref "U1") (pin "R22") (pinfunction "VDD_GPU_R22") (pintype "passive"))
      (node (ref "U1") (pin "R23") (pinfunction "VDD_GPU_R23") (pintype "passive"))
      (node (ref "U1") (pin "T18") (pinfunction "VDD_GPU_T18") (pintype "passive"))
      (node (ref "U1") (pin "T20") (pinfunction "VDD_GPU_T20") (pintype "passive"))
      (node (ref "U1") (pin "T22") (pinfunction "VDD_GPU_T22") (pintype "passive"))
    )
    (net (code "243") (name "/VDD_NPU") (class "Default")
      (node (ref "C41") (pin "1") (pinfunction "1_1") (pintype "passive"))
      (node (ref "C42") (pin "1") (pinfunction "1_1") (pintype "passive"))
      (node (ref "C43") (pin "1") (pinfunction "1_1") (pintype "passive"))
      (node (ref "C44") (pin "1") (pinfunction "1_1") (pintype "passive"))
      (node (ref "C45") (pin "1") (pinfunction "1_1") (pintype "passive"))
      (node (ref "C46") (pin "1") (pinfunction "1_1") (pintype "passive"))
      (node (ref "C48") (pin "1") (pinfunction "1_1") (pintype "passive"))
      (node (ref "C49") (pin "1") (pinfunction "1_1") (pintype "passive"))
      (node (ref "C50") (pin "1") (pinfunction "1_1") (pintype "passive"))
      (node (ref "C51") (pin "1") (pinfunction "1_1") (pintype "passive"))
      (node (ref "C52") (pin "1") (pinfunction "1_1") (pintype "passive"))
      (node (ref "C53") (pin "1") (pinfunction "1_1") (pintype "passive"))
      (node (ref "C54") (pin "1") (pinfunction "1_1") (pintype "passive"))
      (node (ref "J4") (pin "1") (pinfunction "1_1") (pintype "passive"))
      (node (ref "U1") (pin "AA19") (pinfunction "VDD_NPU_AA19") (pintype "passive"))
      (node (ref "U1") (pin "AA20") (pinfunction "VDD_NPU_AA20") (pintype "passive"))
      (node (ref "U1") (pin "AA21") (pinfunction "VDD_NPU_AA21") (pintype "passive"))
      (node (ref "U1") (pin "AA22") (pinfunction "VDD_NPU_AA22") (pintype "passive"))
      (node (ref "U1") (pin "AA23") (pinfunction "VDD_NPU_AA23") (pintype "passive"))
      (node (ref "U1") (pin "AA24") (pinfunction "VDD_NPU_AA24") (pintype "passive"))
      (node (ref "U1") (pin "AB19") (pinfunction "VDD_NPU_AB19") (pintype "passive"))
      (node (ref "U1") (pin "AB21") (pinfunction "VDD_NPU_AB21") (pintype "passive"))
      (node (ref "U1") (pin "AB23") (pinfunction "VDD_NPU_AB23") (pintype "passive"))
      (node (ref "U1") (pin "AD21") (pinfunction "VDD_NPU_AD21") (pintype "passive"))
      (node (ref "U1") (pin "AD23") (pinfunction "VDD_NPU_AD23") (pintype "passive"))
      (node (ref "U1") (pin "AE21") (pinfunction "VDD_NPU_AE21") (pintype "passive"))
      (node (ref "U1") (pin "AE22") (pinfunction "VDD_NPU_AE22") (pintype "passive"))
      (node (ref "U1") (pin "AE23") (pinfunction "VDD_NPU_AE23") (pintype "passive"))
      (node (ref "U1") (pin "V19") (pinfunction "VDD_NPU_V19") (pintype "passive"))
      (node (ref "U1") (pin "V20") (pinfunction "VDD_NPU_V20") (pintype "passive"))
      (node (ref "U1") (pin "V21") (pinfunction "VDD_NPU_V21") (pintype "passive"))
      (node (ref "U1") (pin "V22") (pinfunction "VDD_NPU_V22") (pintype "passive"))
      (node (ref "U1") (pin "V23") (pinfunction "VDD_NPU_V23") (pintype "passive"))
      (node (ref "U1") (pin "W19") (pinfunction "VDD_NPU_W19") (pintype "passive"))
      (node (ref "U1") (pin "W21") (pinfunction "VDD_NPU_W21") (pintype "passive"))
      (node (ref "U1") (pin "W23") (pinfunction "VDD_NPU_W23") (pintype "passive"))
    )
    (net (code "244") (name "/VDQLP_0V6_1V1") (class "Default")
      (node (ref "U4") (pin "A5") (pinfunction "ZQ0_A5") (pintype "passive"))
      (node (ref "U4") (pin "A8") (pinfunction "ZQ1_A8") (pintype "passive"))
      (node (ref "U4") (pin "AA10") (pinfunction "VDDQ_20_AA10") (pintype "passive"))
      (node (ref "U4") (pin "AA3") (pinfunction "VDDQ_17_AA3") (pintype "passive"))
      (node (ref "U4") (pin "AA5") (pinfunction "VDDQ_18_AA5") (pintype "passive"))
      (node (ref "U4") (pin "AA8") (pinfunction "VDDQ_19_AA8") (pintype "passive"))
      (node (ref "U4") (pin "B10") (pinfunction "VDDQ_4_B10") (pintype "passive"))
      (node (ref "U4") (pin "B3") (pinfunction "VDDQ_1_B3") (pintype "passive"))
      (node (ref "U4") (pin "B5") (pinfunction "VDDQ_2_B5") (pintype "passive"))
      (node (ref "U4") (pin "B8") (pinfunction "VDDQ_3_B8") (pintype "passive"))
      (node (ref "U4") (pin "D1") (pinfunction "VDDQ_5_D1") (pintype "passive"))
      (node (ref "U4") (pin "D12") (pinfunction "VDDQ_8_D12") (pintype "passive"))
      (node (ref "U4") (pin "D5") (pinfunction "VDDQ_6_D5") (pintype "passive"))
      (node (ref "U4") (pin "D8") (pinfunction "VDDQ_7_D8") (pintype "passive"))
      (node (ref "U4") (pin "F10") (pinfunction "VDDQ_10_F10") (pintype "passive"))
      (node (ref "U4") (pin "F3") (pinfunction "VDDQ_9_F3") (pintype "passive"))
      (node (ref "U4") (pin "U10") (pinfunction "VDDQ_12_U10") (pintype "passive"))
      (node (ref "U4") (pin "U3") (pinfunction "VDDQ_11_U3") (pintype "passive"))
      (node (ref "U4") (pin "W1") (pinfunction "VDDQ_13_W1") (pintype "passive"))
      (node (ref "U4") (pin "W12") (pinfunction "VDDQ_16_W12") (pintype "passive"))
      (node (ref "U4") (pin "W5") (pinfunction "VDDQ_14_W5") (pintype "passive"))
      (node (ref "U4") (pin "W8") (pinfunction "VDDQ_15_W8") (pintype "passive"))
    )
    (net (code "245") (name "/VVDDAO_3V3_POR") (class "Default")
      (node (ref "R36") (pin "2") (pinfunction "2_2") (pintype "passive+no_connect"))
    )
    (net (code "246") (name "/WD_RSTO") (class "Default")
      (node (ref "R29") (pin "1") (pinfunction "1_1") (pintype "passive"))
      (node (ref "R31") (pin "2") (pinfunction "2_2") (pintype "passive"))
      (node (ref "U1") (pin "F12") (pinfunction "GPIOD_12_F12") (pintype "passive"))
    )
    (net (code "247") (name "/WIFI_32K") (class "Default")
      (node (ref "R72") (pin "1") (pinfunction "1_1") (pintype "passive"))
      (node (ref "U1") (pin "B18") (pinfunction "GPIOX_16_B18") (pintype "passive"))
    )
    (net (code "248") (name "/WIFI_PWREN") (class "Default")
      (node (ref "B2") (pin "15") (pinfunction "WL_REG_ON_15") (pintype "passive"))
      (node (ref "U1") (pin "E20") (pinfunction "GPIOX_6_E20") (pintype "passive"))
    )
    (net (code "249") (name "/WIFI_SD_CLK") (class "Default")
      (node (ref "B2") (pin "18") (pinfunction "SDIO_DATA_CLK_18") (pintype "passive"))
      (node (ref "R5") (pin "1") (pinfunction "1_1") (pintype "passive"))
    )
    (net (code "250") (name "/WIFI_SD_CMD") (class "Default")
      (node (ref "B2") (pin "17") (pinfunction "SDIO_DATA_CMD_17") (pintype "passive"))
      (node (ref "R61") (pin "2") (pinfunction "2_2") (pintype "passive"))
      (node (ref "U1") (pin "B21") (pinfunction "GPIOX_5_B21") (pintype "passive"))
    )
    (net (code "251") (name "/WIFI_SD_D0") (class "Default")
      (node (ref "B2") (pin "21") (pinfunction "SDIO_DATA_0_21") (pintype "passive"))
      (node (ref "R62") (pin "2") (pinfunction "2_2") (pintype "passive"))
      (node (ref "U1") (pin "D21") (pinfunction "GPIOX_0_D21") (pintype "passive"))
    )
    (net (code "252") (name "/WIFI_SD_D1") (class "Default")
      (node (ref "B2") (pin "22") (pinfunction "SDIO_DATA_1_22") (pintype "passive"))
      (node (ref "U1") (pin "E21") (pinfunction "GPIOX_1_E21") (pintype "passive"))
    )
    (net (code "253") (name "/WIFI_SD_D2") (class "Default")
      (node (ref "B2") (pin "20") (pinfunction "SDIO_DATA_2_20") (pintype "passive"))
      (node (ref "U1") (pin "C21") (pinfunction "GPIOX_2_C21") (pintype "passive"))
    )
    (net (code "254") (name "/WIFI_SD_D3") (class "Default")
      (node (ref "B2") (pin "19") (pinfunction "SDIO_DATA_3_19") (pintype "passive"))
      (node (ref "U1") (pin "D20") (pinfunction "GPIOX_3_D20") (pintype "passive"))
    )
    (net (code "255") (name "/WIFI_VBAT") (class "Default")
      (node (ref "B2") (pin "36") (pinfunction "VBAT_36") (pintype "passive+no_connect"))
    )
    (net (code "256") (name "/WIFI_WAKE_HOST") (class "Default")
      (node (ref "R56") (pin "1") (pinfunction "1_1") (pintype "passive"))
      (node (ref "U1") (pin "C20") (pinfunction "GPIOX_7_C20") (pintype "passive"))
    )
    (net (code "257") (name "/WOL_EN") (class "Default")
      (node (ref "U3") (pin "13") (pinfunction "PA6_13") (pintype "bidirectional"))
      (node (ref "U6") (pin "2") (pinfunction "D0_2") (pintype "input"))
    )
    (net (code "258") (name "/WOL_INTB") (class "Default")
      (node (ref "U3") (pin "12") (pinfunction "PA5_12") (pintype "bidirectional+no_connect"))
    )
    (net (code "259") (name "GND") (class "Default")
      (node (ref "*") (pin "15") (pinfunction "EP_GND_15") (pintype "passive"))
      (node (ref "*") (pin "8") (pinfunction "GND_1_8") (pintype "passive"))
      (node (ref "*") (pin "9") (pinfunction "GND_2_9") (pintype "passive"))
      (node (ref "B1") (pin "4") (pinfunction "GND_4") (pintype "passive"))
      (node (ref "B1") (pin "9") (pinfunction "EP_9") (pintype "passive"))
      (node (ref "B2") (pin "1") (pinfunction "GND_1_1") (pintype "passive"))
      (node (ref "B2") (pin "10") (pinfunction "GND_8_10") (pintype "passive"))
      (node (ref "B2") (pin "11") (pinfunction "GND_9_11") (pintype "passive"))
      (node (ref "B2") (pin "23") (pinfunction "GND_10_23") (pintype "passive"))
      (node (ref "B2") (pin "27") (pinfunction "GND_11_27") (pintype "passive"))
      (node (ref "B2") (pin "3") (pinfunction "GND_2_3") (pintype "passive"))
      (node (ref "B2") (pin "30") (pinfunction "GND_12_30") (pintype "passive"))
      (node (ref "B2") (pin "32") (pinfunction "GND_13_32") (pintype "passive"))
      (node (ref "B2") (pin "39") (pinfunction "GND_14_39") (pintype "passive"))
      (node (ref "B2") (pin "4") (pinfunction "GND_3_4") (pintype "passive"))
      (node (ref "B2") (pin "5") (pinfunction "GND_4_5") (pintype "passive"))
      (node (ref "B2") (pin "6") (pinfunction "GND_5_6") (pintype "passive"))
      (node (ref "B2") (pin "7") (pinfunction "GND_6_7") (pintype "passive"))
      (node (ref "B2") (pin "8") (pinfunction "GND_7_8") (pintype "passive"))
      (node (ref "C1") (pin "2") (pinfunction "2_2") (pintype "passive"))
      (node (ref "C10") (pin "2") (pinfunction "2_2") (pintype "passive"))
      (node (ref "C100") (pin "2") (pinfunction "2_2") (pintype "passive"))
      (node (ref "C101") (pin "2") (pinfunction "2_2") (pintype "passive"))
      (node (ref "C102") (pin "2") (pinfunction "2_2") (pintype "passive"))
      (node (ref "C103") (pin "2") (pinfunction "2_2") (pintype "passive"))
      (node (ref "C104") (pin "2") (pinfunction "2_2") (pintype "passive"))
      (node (ref "C105") (pin "2") (pinfunction "2_2") (pintype "passive"))
      (node (ref "C106") (pin "2") (pinfunction "2_2") (pintype "passive"))
      (node (ref "C107") (pin "2") (pinfunction "2_2") (pintype "passive"))
      (node (ref "C108") (pin "2") (pinfunction "2_2") (pintype "passive"))
      (node (ref "C109") (pin "2") (pinfunction "2_2") (pintype "passive"))
      (node (ref "C11") (pin "2") (pinfunction "2_2") (pintype "passive"))
      (node (ref "C110") (pin "2") (pinfunction "2_2") (pintype "passive"))
      (node (ref "C111") (pin "2") (pinfunction "2_2") (pintype "passive"))
      (node (ref "C112") (pin "2") (pinfunction "2_2") (pintype "passive"))
      (node (ref "C113") (pin "2") (pinfunction "2_2") (pintype "passive"))
      (node (ref "C114") (pin "2") (pinfunction "2_2") (pintype "passive"))
      (node (ref "C115") (pin "2") (pinfunction "2_2") (pintype "passive"))
      (node (ref "C116") (pin "2") (pinfunction "2_2") (pintype "passive"))
      (node (ref "C117") (pin "2") (pinfunction "2_2") (pintype "passive"))
      (node (ref "C118") (pin "2") (pinfunction "2_2") (pintype "passive"))
      (node (ref "C119") (pin "2") (pinfunction "2_2") (pintype "passive"))
      (node (ref "C12") (pin "1") (pinfunction "1_1") (pintype "passive"))
      (node (ref "C12") (pin "2") (pinfunction "2_2") (pintype "passive"))
      (node (ref "C120") (pin "2") (pinfunction "2_2") (pintype "passive"))
      (node (ref "C121") (pin "2") (pinfunction "2_2") (pintype "passive"))
      (node (ref "C122") (pin "2") (pinfunction "2_2") (pintype "passive"))
      (node (ref "C123") (pin "2") (pinfunction "2_2") (pintype "passive"))
      (node (ref "C124") (pin "2") (pinfunction "2_2") (pintype "passive"))
      (node (ref "C125") (pin "2") (pinfunction "2_2") (pintype "passive"))
      (node (ref "C126") (pin "2") (pinfunction "2_2") (pintype "passive"))
      (node (ref "C127") (pin "2") (pinfunction "2_2") (pintype "passive"))
      (node (ref "C128") (pin "2") (pinfunction "2_2") (pintype "passive"))
      (node (ref "C129") (pin "2") (pinfunction "2_2") (pintype "passive"))
      (node (ref "C13") (pin "2") (pinfunction "2_2") (pintype "passive"))
      (node (ref "C130") (pin "2") (pinfunction "2_2") (pintype "passive"))
      (node (ref "C131") (pin "2") (pinfunction "2_2") (pintype "passive"))
      (node (ref "C132") (pin "2") (pinfunction "2_2") (pintype "passive"))
      (node (ref "C133") (pin "2") (pinfunction "2_2") (pintype "passive"))
      (node (ref "C137") (pin "2") (pinfunction "2_2") (pintype "passive"))
      (node (ref "C138") (pin "2") (pinfunction "2_2") (pintype "passive"))
      (node (ref "C139") (pin "2") (pinfunction "2_2") (pintype "passive"))
      (node (ref "C14") (pin "2") (pinfunction "2_2") (pintype "passive"))
      (node (ref "C140") (pin "2") (pinfunction "2_2") (pintype "passive"))
      (node (ref "C141") (pin "2") (pinfunction "2_2") (pintype "passive"))
      (node (ref "C142") (pin "2") (pinfunction "2_2") (pintype "passive"))
      (node (ref "C143") (pin "2") (pinfunction "2_2") (pintype "passive"))
      (node (ref "C144") (pin "2") (pinfunction "2_2") (pintype "passive"))
      (node (ref "C145") (pin "2") (pinfunction "2_2") (pintype "passive"))
      (node (ref "C146") (pin "2") (pinfunction "2_2") (pintype "passive"))
      (node (ref "C147") (pin "2") (pinfunction "2_2") (pintype "passive"))
      (node (ref "C148") (pin "2") (pinfunction "2_2") (pintype "passive"))
      (node (ref "C149") (pin "2") (pinfunction "2_2") (pintype "passive"))
      (node (ref "C15") (pin "2") (pinfunction "2_2") (pintype "passive"))
      (node (ref "C150") (pin "2") (pinfunction "2_2") (pintype "passive"))
      (node (ref "C151") (pin "2") (pinfunction "2_2") (pintype "passive"))
      (node (ref "C16") (pin "2") (pinfunction "2_2") (pintype "passive"))
      (node (ref "C17") (pin "2") (pinfunction "2_2") (pintype "passive"))
      (node (ref "C18") (pin "2") (pinfunction "2_2") (pintype "passive"))
      (node (ref "C19") (pin "2") (pinfunction "2_2") (pintype "passive"))
      (node (ref "C2") (pin "2") (pinfunction "2_2") (pintype "passive"))
      (node (ref "C20") (pin "2") (pinfunction "2_2") (pintype "passive"))
      (node (ref "C21") (pin "2") (pinfunction "2_2") (pintype "passive"))
      (node (ref "C22") (pin "2") (pinfunction "2_2") (pintype "passive"))
      (node (ref "C23") (pin "2") (pinfunction "2_2") (pintype "passive"))
      (node (ref "C24") (pin "2") (pinfunction "2_2") (pintype "passive"))
      (node (ref "C25") (pin "2") (pinfunction "2_2") (pintype "passive"))
      (node (ref "C26") (pin "2") (pinfunction "2_2") (pintype "passive"))
      (node (ref "C27") (pin "2") (pinfunction "2_2") (pintype "passive"))
      (node (ref "C28") (pin "2") (pinfunction "2_2") (pintype "passive"))
      (node (ref "C29") (pin "2") (pinfunction "2_2") (pintype "passive"))
      (node (ref "C3") (pin "2") (pinfunction "2_2") (pintype "passive"))
      (node (ref "C30") (pin "2") (pinfunction "2_2") (pintype "passive"))
      (node (ref "C31") (pin "2") (pinfunction "2_2") (pintype "passive"))
      (node (ref "C32") (pin "2") (pinfunction "2_2") (pintype "passive"))
      (node (ref "C33") (pin "2") (pinfunction "2_2") (pintype "passive"))
      (node (ref "C34") (pin "2") (pinfunction "2_2") (pintype "passive"))
      (node (ref "C35") (pin "2") (pinfunction "2_2") (pintype "passive"))
      (node (ref "C36") (pin "2") (pinfunction "2_2") (pintype "passive"))
      (node (ref "C37") (pin "2") (pinfunction "2_2") (pintype "passive"))
      (node (ref "C38") (pin "2") (pinfunction "2_2") (pintype "passive"))
      (node (ref "C39") (pin "2") (pinfunction "2_2") (pintype "passive"))
      (node (ref "C4") (pin "2") (pinfunction "2_2") (pintype "passive"))
      (node (ref "C40") (pin "2") (pinfunction "2_2") (pintype "passive"))
      (node (ref "C41") (pin "2") (pinfunction "2_2") (pintype "passive"))
      (node (ref "C42") (pin "2") (pinfunction "2_2") (pintype "passive"))
      (node (ref "C43") (pin "2") (pinfunction "2_2") (pintype "passive"))
      (node (ref "C44") (pin "2") (pinfunction "2_2") (pintype "passive"))
      (node (ref "C45") (pin "2") (pinfunction "2_2") (pintype "passive"))
      (node (ref "C46") (pin "2") (pinfunction "2_2") (pintype "passive"))
      (node (ref "C47") (pin "2") (pinfunction "2_2") (pintype "passive"))
      (node (ref "C48") (pin "2") (pinfunction "2_2") (pintype "passive"))
      (node (ref "C49") (pin "2") (pinfunction "2_2") (pintype "passive"))
      (node (ref "C5") (pin "2") (pinfunction "2_2") (pintype "passive"))
      (node (ref "C50") (pin "2") (pinfunction "2_2") (pintype "passive"))
      (node (ref "C51") (pin "2") (pinfunction "2_2") (pintype "passive"))
      (node (ref "C52") (pin "2") (pinfunction "2_2") (pintype "passive"))
      (node (ref "C53") (pin "2") (pinfunction "2_2") (pintype "passive"))
      (node (ref "C54") (pin "2") (pinfunction "2_2") (pintype "passive"))
      (node (ref "C55") (pin "2") (pinfunction "2_2") (pintype "passive"))
      (node (ref "C56") (pin "2") (pinfunction "2_2") (pintype "passive"))
      (node (ref "C57") (pin "2") (pinfunction "2_2") (pintype "passive"))
      (node (ref "C58") (pin "2") (pinfunction "2_2") (pintype "passive"))
      (node (ref "C59") (pin "2") (pinfunction "2_2") (pintype "passive"))
      (node (ref "C6") (pin "2") (pinfunction "2_2") (pintype "passive"))
      (node (ref "C60") (pin "2") (pinfunction "2_2") (pintype "passive"))
      (node (ref "C61") (pin "2") (pinfunction "2_2") (pintype "passive"))
      (node (ref "C62") (pin "2") (pinfunction "2_2") (pintype "passive"))
      (node (ref "C63") (pin "2") (pinfunction "2_2") (pintype "passive"))
      (node (ref "C64") (pin "2") (pinfunction "2_2") (pintype "passive"))
      (node (ref "C65") (pin "2") (pinfunction "2_2") (pintype "passive"))
      (node (ref "C66") (pin "2") (pinfunction "2_2") (pintype "passive"))
      (node (ref "C67") (pin "2") (pinfunction "2_2") (pintype "passive"))
      (node (ref "C68") (pin "2") (pinfunction "2_2") (pintype "passive"))
      (node (ref "C69") (pin "2") (pinfunction "2_2") (pintype "passive"))
      (node (ref "C7") (pin "2") (pinfunction "2_2") (pintype "passive"))
      (node (ref "C70") (pin "2") (pinfunction "2_2") (pintype "passive"))
      (node (ref "C71") (pin "2") (pinfunction "2_2") (pintype "passive"))
      (node (ref "C72") (pin "2") (pinfunction "2_2") (pintype "passive"))
      (node (ref "C73") (pin "2") (pinfunction "2_2") (pintype "passive"))
      (node (ref "C74") (pin "2") (pinfunction "2_2") (pintype "passive"))
      (node (ref "C75") (pin "2") (pinfunction "2_2") (pintype "passive"))
      (node (ref "C76") (pin "2") (pinfunction "2_2") (pintype "passive"))
      (node (ref "C77") (pin "2") (pinfunction "2_2") (pintype "passive"))
      (node (ref "C78") (pin "2") (pinfunction "2_2") (pintype "passive"))
      (node (ref "C79") (pin "2") (pinfunction "2_2") (pintype "passive"))
      (node (ref "C8") (pin "2") (pinfunction "2_2") (pintype "passive"))
      (node (ref "C80") (pin "1") (pinfunction "1_1") (pintype "passive"))
      (node (ref "C81") (pin "2") (pinfunction "2_2") (pintype "passive"))
      (node (ref "C82") (pin "2") (pinfunction "2_2") (pintype "passive"))
      (node (ref "C83") (pin "2") (pinfunction "2_2") (pintype "passive"))
      (node (ref "C84") (pin "2") (pinfunction "2_2") (pintype "passive"))
      (node (ref "C85") (pin "2") (pinfunction "2_2") (pintype "passive"))
      (node (ref "C86") (pin "2") (pinfunction "2_2") (pintype "passive"))
      (node (ref "C87") (pin "2") (pinfunction "2_2") (pintype "passive"))
      (node (ref "C88") (pin "2") (pinfunction "2_2") (pintype "passive"))
      (node (ref "C89") (pin "2") (pinfunction "2_2") (pintype "passive"))
      (node (ref "C9") (pin "2") (pinfunction "2_2") (pintype "passive"))
      (node (ref "C90") (pin "2") (pinfunction "2_2") (pintype "passive"))
      (node (ref "C91") (pin "2") (pinfunction "2_2") (pintype "passive"))
      (node (ref "C92") (pin "2") (pinfunction "2_2") (pintype "passive"))
      (node (ref "C93") (pin "2") (pinfunction "2_2") (pintype "passive"))
      (node (ref "C94") (pin "2") (pinfunction "2_2") (pintype "passive"))
      (node (ref "C95") (pin "2") (pinfunction "2_2") (pintype "passive"))
      (node (ref "C96") (pin "2") (pinfunction "2_2") (pintype "passive"))
      (node (ref "C97") (pin "2") (pinfunction "2_2") (pintype "passive"))
      (node (ref "C98") (pin "2") (pinfunction "2_2") (pintype "passive"))
      (node (ref "C99") (pin "2") (pinfunction "2_2") (pintype "passive"))
      (node (ref "D11") (pin "1") (pinfunction "1_1") (pintype "passive"))
      (node (ref "D13") (pin "2") (pinfunction "2_2") (pintype "passive"))
      (node (ref "D14") (pin "2") (pinfunction "2_2") (pintype "passive"))
      (node (ref "D15") (pin "1") (pinfunction "1_1") (pintype "passive"))
      (node (ref "D16") (pin "1") (pinfunction "1_1") (pintype "passive"))
      (node (ref "D17") (pin "1") (pinfunction "1_1") (pintype "passive"))
      (node (ref "D18") (pin "1") (pinfunction "1_1") (pintype "passive"))
      (node (ref "J1") (pin "2") (pinfunction "2_2") (pintype "passive"))
      (node (ref "J1") (pin "3") (pinfunction "MNT_1_3") (pintype "passive"))
      (node (ref "J1") (pin "4") (pinfunction "MNT_2_4") (pintype "passive"))
      (node (ref "J2") (pin "1") (pinfunction "1_1") (pintype "passive"))
      (node (ref "J2") (pin "10") (pinfunction "10_10") (pintype "passive"))
      (node (ref "J2") (pin "13") (pinfunction "13_13") (pintype "passive"))
      (node (ref "J2") (pin "16") (pinfunction "16_16") (pintype "passive"))
      (node (ref "J2") (pin "26") (pinfunction "26_26") (pintype "passive"))
      (node (ref "J2") (pin "27") (pinfunction "27_27") (pintype "passive"))
      (node (ref "J2") (pin "31") (pinfunction "MP1_31") (pintype "passive"))
      (node (ref "J2") (pin "32") (pinfunction "MP2_32") (pintype "passive"))
      (node (ref "J2") (pin "4") (pinfunction "4_4") (pintype "passive"))
      (node (ref "J2") (pin "7") (pinfunction "7_7") (pintype "passive"))
      (node (ref "J3") (pin "1") (pinfunction "1_1") (pintype "passive"))
      (node (ref "J3") (pin "10") (pinfunction "10_10") (pintype "passive"))
      (node (ref "J3") (pin "13") (pinfunction "13_13") (pintype "passive"))
      (node (ref "J3") (pin "16") (pinfunction "16_16") (pintype "passive"))
      (node (ref "J3") (pin "22") (pinfunction "22_22") (pintype "passive"))
      (node (ref "J3") (pin "23") (pinfunction "23_23") (pintype "passive"))
      (node (ref "J3") (pin "24") (pinfunction "24_24") (pintype "passive"))
      (node (ref "J3") (pin "25") (pinfunction "25_25") (pintype "passive"))
      (node (ref "J3") (pin "35") (pinfunction "35_35") (pintype "passive"))
      (node (ref "J3") (pin "4") (pinfunction "4_4") (pintype "passive"))
      (node (ref "J3") (pin "40") (pinfunction "40_40") (pintype "passive"))
      (node (ref "J3") (pin "41") (pinfunction "MP1_41") (pintype "passive"))
      (node (ref "J3") (pin "42") (pinfunction "MP2_42") (pintype "passive"))
      (node (ref "J3") (pin "7") (pinfunction "7_7") (pintype "passive"))
      (node (ref "J4") (pin "27") (pinfunction "27_27") (pintype "passive"))
      (node (ref "J4") (pin "28") (pinfunction "28_28") (pintype "passive"))
      (node (ref "J4") (pin "29") (pinfunction "29_29") (pintype "passive"))
      (node (ref "J4") (pin "30") (pinfunction "30_30") (pintype "passive"))
      (node (ref "J4") (pin "31") (pinfunction "MP1_31") (pintype "passive"))
      (node (ref "J4") (pin "32") (pinfunction "MP2_32") (pintype "passive"))
      (node (ref "J5") (pin "3") (pinfunction "3_3") (pintype "passive"))
      (node (ref "J5") (pin "4") (pinfunction "4_4") (pintype "passive"))
      (node (ref "J5") (pin "MP1") (pinfunction "MP1_MP1") (pintype "passive"))
      (node (ref "J5") (pin "MP2") (pinfunction "MP2_MP2") (pintype "passive"))
      (node (ref "J6") (pin "3") (pinfunction "3_3") (pintype "passive"))
      (node (ref "J6") (pin "S1") (pinfunction "SHIELD_S1") (pintype "passive"))
      (node (ref "J6") (pin "S2") (pinfunction "SHIELD_S2") (pintype "passive"))
      (node (ref "J7") (pin "A1") (pinfunction "GND_1_A1") (pintype "passive"))
      (node (ref "J7") (pin "B1") (pinfunction "GND_2_B1") (pintype "passive"))
      (node (ref "J7") (pin "MH1") (pinfunction "MH1_MH1") (pintype "passive"))
      (node (ref "J7") (pin "MH2") (pinfunction "MH2_MH2") (pintype "passive"))
      (node (ref "J7") (pin "MH3") (pinfunction "MH3_MH3") (pintype "passive"))
      (node (ref "J7") (pin "MH4") (pinfunction "MH4_MH4") (pintype "passive"))
      (node (ref "J8") (pin "3") (pinfunction "MNT_1_3") (pintype "passive"))
      (node (ref "J8") (pin "4") (pinfunction "MNT_2_4") (pintype "passive"))
      (node (ref "Q3") (pin "2") (pinfunction "S_2") (pintype "passive"))
      (node (ref "Q4") (pin "2") (pinfunction "S_2") (pintype "passive"))
      (node (ref "Q5") (pin "2") (pinfunction "S_2") (pintype "passive"))
      (node (ref "Q6") (pin "2") (pinfunction "S_2") (pintype "passive"))
      (node (ref "R1") (pin "2") (pinfunction "2_2") (pintype "passive"))
      (node (ref "R11") (pin "2") (pinfunction "2_2") (pintype "passive"))
      (node (ref "R16") (pin "2") (pinfunction "2_2") (pintype "passive"))
      (node (ref "R18") (pin "2") (pinfunction "2_2") (pintype "passive"))
      (node (ref "R21") (pin "2") (pinfunction "2_2") (pintype "passive"))
      (node (ref "R24") (pin "2") (pinfunction "2_2") (pintype "passive"))
      (node (ref "R25") (pin "1") (pinfunction "1_1") (pintype "passive"))
      (node (ref "R30") (pin "2") (pinfunction "2_2") (pintype "passive"))
      (node (ref "R32") (pin "2") (pinfunction "2_2") (pintype "passive"))
      (node (ref "R34") (pin "2") (pinfunction "2_2") (pintype "passive"))
      (node (ref "R38") (pin "2") (pinfunction "2_2") (pintype "passive"))
      (node (ref "R39") (pin "2") (pinfunction "2_2") (pintype "passive"))
      (node (ref "R4") (pin "1") (pinfunction "1_1") (pintype "passive"))
      (node (ref "R40") (pin "2") (pinfunction "2_2") (pintype "passive"))
      (node (ref "R46") (pin "2") (pinfunction "2_2") (pintype "passive"))
      (node (ref "R49") (pin "2") (pinfunction "2_2") (pintype "passive"))
      (node (ref "R50") (pin "1") (pinfunction "1_1") (pintype "passive"))
      (node (ref "R55") (pin "2") (pinfunction "2_2") (pintype "passive"))
      (node (ref "R66") (pin "2") (pinfunction "2_2") (pintype "passive"))
      (node (ref "R67") (pin "1") (pinfunction "1_1") (pintype "passive"))
      (node (ref "R71") (pin "1") (pinfunction "1_1") (pintype "passive"))
      (node (ref "SW1") (pin "1") (pinfunction "GND_1") (pintype "power_in"))
      (node (ref "SW1") (pin "A") (pinfunction "A_A") (pintype "passive"))
      (node (ref "SW1") (pin "A'") (pinfunction "A'_A'") (pintype "passive"))
      (node (ref "SW1") (pin "B'") (pinfunction "B'_B'") (pintype "passive"))
      (node (ref "SW2") (pin "1") (pinfunction "GND_1") (pintype "power_in"))
      (node (ref "SW2") (pin "A") (pinfunction "A_A") (pintype "passive"))
      (node (ref "SW2") (pin "A'") (pinfunction "A'_A'") (pintype "passive"))
      (node (ref "SW2") (pin "B'") (pinfunction "B'_B'") (pintype "passive"))
      (node (ref "SW3") (pin "3") (pinfunction "3_3") (pintype "passive"))
      (node (ref "SW3") (pin "4") (pinfunction "4_4") (pintype "passive"))
      (node (ref "SW4") (pin "2") (pinfunction "2_2") (pintype "passive"))
      (node (ref "U1") (pin "A1") (pinfunction "DVSS_A1") (pintype "passive"))
      (node (ref "U1") (pin "A33") (pinfunction "DVSS_A33") (pintype "passive"))
      (node (ref "U1") (pin "A5") (pinfunction "DVSS_A5") (pintype "passive"))
      (node (ref "U1") (pin "AA11") (pinfunction "DVSS_AA11") (pintype "passive"))
      (node (ref "U1") (pin "AA14") (pinfunction "DVSS_AA14") (pintype "passive"))
      (node (ref "U1") (pin "AA17") (pinfunction "DVSS_AA17") (pintype "passive"))
      (node (ref "U1") (pin "AA18") (pinfunction "DVSS_AA18") (pintype "passive"))
      (node (ref "U1") (pin "AA26") (pinfunction "DVSS_AA26") (pintype "passive"))
      (node (ref "U1") (pin "AA5") (pinfunction "DVSS_AA5") (pintype "passive"))
      (node (ref "U1") (pin "AA9") (pinfunction "DVSS_AA9") (pintype "passive"))
      (node (ref "U1") (pin "AB10") (pinfunction "DVSS_AB10") (pintype "passive"))
      (node (ref "U1") (pin "AB11") (pinfunction "DVSS_AB11") (pintype "passive"))
      (node (ref "U1") (pin "AB13") (pinfunction "DVSS_AB13") (pintype "passive"))
      (node (ref "U1") (pin "AB14") (pinfunction "DVSS_AB14") (pintype "passive"))
      (node (ref "U1") (pin "AB16") (pinfunction "DVSS_AB16") (pintype "passive"))
      (node (ref "U1") (pin "AB17") (pinfunction "DVSS_AB17") (pintype "passive"))
      (node (ref "U1") (pin "AB18") (pinfunction "DVSS_AB18") (pintype "passive"))
      (node (ref "U1") (pin "AB2") (pinfunction "DVSS_AB2") (pintype "passive"))
      (node (ref "U1") (pin "AB20") (pinfunction "DVSS_AB20") (pintype "passive"))
      (node (ref "U1") (pin "AB22") (pinfunction "DVSS_AB22") (pintype "passive"))
      (node (ref "U1") (pin "AB24") (pinfunction "DVSS_AB24") (pintype "passive"))
      (node (ref "U1") (pin "AB26") (pinfunction "DVSS_AB26") (pintype "passive"))
      (node (ref "U1") (pin "AB33") (pinfunction "DVSS_AB33") (pintype "passive"))
      (node (ref "U1") (pin "AB5") (pinfunction "DVSS_AB5") (pintype "passive"))
      (node (ref "U1") (pin "AC1") (pinfunction "DVSS_AC1") (pintype "passive"))
      (node (ref "U1") (pin "AC10") (pinfunction "DVSS_AC10") (pintype "passive"))
      (node (ref "U1") (pin "AC14") (pinfunction "DVSS_AC14") (pintype "passive"))
      (node (ref "U1") (pin "AC17") (pinfunction "DVSS_AC17") (pintype "passive"))
      (node (ref "U1") (pin "AC18") (pinfunction "DVSS_AC18") (pintype "passive"))
      (node (ref "U1") (pin "AC19") (pinfunction "DVSS_AC19") (pintype "passive"))
      (node (ref "U1") (pin "AC20") (pinfunction "DVSS_AC20") (pintype "passive"))
      (node (ref "U1") (pin "AC21") (pinfunction "DVSS_AC21") (pintype "passive"))
      (node (ref "U1") (pin "AC22") (pinfunction "DVSS_AC22") (pintype "passive"))
      (node (ref "U1") (pin "AC23") (pinfunction "DVSS_AC23") (pintype "passive"))
      (node (ref "U1") (pin "AC24") (pinfunction "DVSS_AC24") (pintype "passive"))
      (node (ref "U1") (pin "AC25") (pinfunction "DVSS_AC25") (pintype "passive"))
      (node (ref "U1") (pin "AC26") (pinfunction "DVSS_AC26") (pintype "passive"))
      (node (ref "U1") (pin "AC29") (pinfunction "DVSS_AC29") (pintype "passive"))
      (node (ref "U1") (pin "AC8") (pinfunction "DVSS_AC8") (pintype "passive"))
      (node (ref "U1") (pin "AC9") (pinfunction "DVSS_AC9") (pintype "passive"))
      (node (ref "U1") (pin "AD11") (pinfunction "DVSS_AD11") (pintype "passive"))
      (node (ref "U1") (pin "AD13") (pinfunction "DVSS_AD13") (pintype "passive"))
      (node (ref "U1") (pin "AD14") (pinfunction "DVSS_AD14") (pintype "passive"))
      (node (ref "U1") (pin "AD16") (pinfunction "DVSS_AD16") (pintype "passive"))
      (node (ref "U1") (pin "AD17") (pinfunction "DVSS_AD17") (pintype "passive"))
      (node (ref "U1") (pin "AD19") (pinfunction "DVSS_AD19") (pintype "passive"))
      (node (ref "U1") (pin "AD22") (pinfunction "DVSS_AD22") (pintype "passive"))
      (node (ref "U1") (pin "AD24") (pinfunction "DVSS_AD24") (pintype "passive"))
      (node (ref "U1") (pin "AD25") (pinfunction "DVSS_AD25") (pintype "passive"))
      (node (ref "U1") (pin "AD5") (pinfunction "DVSS_AD5") (pintype "passive"))
      (node (ref "U1") (pin "AD9") (pinfunction "DVSS_AD9") (pintype "passive"))
      (node (ref "U1") (pin "AE10") (pinfunction "DVSS_AE10") (pintype "passive"))
      (node (ref "U1") (pin "AE11") (pinfunction "DVSS_AE11") (pintype "passive"))
      (node (ref "U1") (pin "AE14") (pinfunction "DVSS_AE14") (pintype "passive"))
      (node (ref "U1") (pin "AE17") (pinfunction "DVSS_AE17") (pintype "passive"))
      (node (ref "U1") (pin "AE2") (pinfunction "DVSS_AE2") (pintype "passive"))
      (node (ref "U1") (pin "AE24") (pinfunction "DVSS_AE24") (pintype "passive"))
      (node (ref "U1") (pin "AE32") (pinfunction "DVSS_AE32") (pintype "passive"))
      (node (ref "U1") (pin "AF1") (pinfunction "DVSS_AF1") (pintype "passive"))
      (node (ref "U1") (pin "AF10") (pinfunction "DVSS_AF10") (pintype "passive"))
      (node (ref "U1") (pin "AF13") (pinfunction "DVSS_AF13") (pintype "passive"))
      (node (ref "U1") (pin "AF14") (pinfunction "DVSS_AF14") (pintype "passive"))
      (node (ref "U1") (pin "AF15") (pinfunction "DVSS_AF15") (pintype "passive"))
      (node (ref "U1") (pin "AF16") (pinfunction "DVSS_AF16") (pintype "passive"))
      (node (ref "U1") (pin "AF17") (pinfunction "DVSS_AF17") (pintype "passive"))
      (node (ref "U1") (pin "AF18") (pinfunction "DVSS_AF18") (pintype "passive"))
      (node (ref "U1") (pin "AF19") (pinfunction "DVSS_AF19") (pintype "passive"))
      (node (ref "U1") (pin "AF20") (pinfunction "DVSS_AF20") (pintype "passive"))
      (node (ref "U1") (pin "AF21") (pinfunction "DVSS_AF21") (pintype "passive"))
      (node (ref "U1") (pin "AF22") (pinfunction "DVSS_AF22") (pintype "passive"))
      (node (ref "U1") (pin "AF23") (pinfunction "DVSS_AF23") (pintype "passive"))
      (node (ref "U1") (pin "AF24") (pinfunction "DVSS_AF24") (pintype "passive"))
      (node (ref "U1") (pin "AF25") (pinfunction "DVSS_AF25") (pintype "passive"))
      (node (ref "U1") (pin "AF26") (pinfunction "DVSS_AF26") (pintype "passive"))
      (node (ref "U1") (pin "AF29") (pinfunction "DVSS_AF29") (pintype "passive"))
      (node (ref "U1") (pin "AF5") (pinfunction "DVSS_AF5") (pintype "passive"))
      (node (ref "U1") (pin "AF8") (pinfunction "DVSS_AF8") (pintype "passive"))
      (node (ref "U1") (pin "AF9") (pinfunction "DVSS_AF9") (pintype "passive"))
      (node (ref "U1") (pin "AG11") (pinfunction "DVSS_AG11") (pintype "passive"))
      (node (ref "U1") (pin "AG14") (pinfunction "DVSS_AG14") (pintype "passive"))
      (node (ref "U1") (pin "AG15") (pinfunction "DVSS_AG15") (pintype "passive"))
      (node (ref "U1") (pin "AG16") (pinfunction "DVSS_AG16") (pintype "passive"))
      (node (ref "U1") (pin "AG17") (pinfunction "DVSS_AG17") (pintype "passive"))
      (node (ref "U1") (pin "AG18") (pinfunction "DVSS_AG18") (pintype "passive"))
      (node (ref "U1") (pin "AG20") (pinfunction "DVSS_AG20") (pintype "passive"))
      (node (ref "U1") (pin "AG22") (pinfunction "DVSS_AG22") (pintype "passive"))
      (node (ref "U1") (pin "AG24") (pinfunction "DVSS_AG24") (pintype "passive"))
      (node (ref "U1") (pin "AG25") (pinfunction "DVSS_AG25") (pintype "passive"))
      (node (ref "U1") (pin "AG26") (pinfunction "DVSS_AG26") (pintype "passive"))
      (node (ref "U1") (pin "AG9") (pinfunction "DVSS_AG9") (pintype "passive"))
      (node (ref "U1") (pin "AH10") (pinfunction "DVSS_AH10") (pintype "passive"))
      (node (ref "U1") (pin "AH11") (pinfunction "DVSS_AH11") (pintype "passive"))
      (node (ref "U1") (pin "AH12") (pinfunction "DVSS_AH12") (pintype "passive"))
      (node (ref "U1") (pin "AH13") (pinfunction "DVSS_AH13") (pintype "passive"))
      (node (ref "U1") (pin "AH14") (pinfunction "DVSS_AH14") (pintype "passive"))
      (node (ref "U1") (pin "AH15") (pinfunction "DVSS_AH15") (pintype "passive"))
      (node (ref "U1") (pin "AH16") (pinfunction "DVSS_AH16") (pintype "passive"))
      (node (ref "U1") (pin "AH17") (pinfunction "DVSS_AH17") (pintype "passive"))
      (node (ref "U1") (pin "AH18") (pinfunction "DVSS_AH18") (pintype "passive"))
      (node (ref "U1") (pin "AH2") (pinfunction "DVSS_AH2") (pintype "passive"))
      (node (ref "U1") (pin "AH24") (pinfunction "DVSS_AH24") (pintype "passive"))
      (node (ref "U1") (pin "AH26") (pinfunction "DVSS_AH26") (pintype "passive"))
      (node (ref "U1") (pin "AH5") (pinfunction "DVSS_AH5") (pintype "passive"))
      (node (ref "U1") (pin "AH8") (pinfunction "DVSS_AH8") (pintype "passive"))
      (node (ref "U1") (pin "AJ1") (pinfunction "DVSS_AJ1") (pintype "passive"))
      (node (ref "U1") (pin "AJ10") (pinfunction "DVSS_AJ10") (pintype "passive"))
      (node (ref "U1") (pin "AJ12") (pinfunction "DVSS_AJ12") (pintype "passive"))
      (node (ref "U1") (pin "AJ16") (pinfunction "DVSS_AJ16") (pintype "passive"))
      (node (ref "U1") (pin "AJ18") (pinfunction "DVSS_AJ18") (pintype "passive"))
      (node (ref "U1") (pin "AJ19") (pinfunction "DVSS_AJ19") (pintype "passive"))
      (node (ref "U1") (pin "AJ20") (pinfunction "DVSS_AJ20") (pintype "passive"))
      (node (ref "U1") (pin "AJ22") (pinfunction "DVSS_AJ22") (pintype "passive"))
      (node (ref "U1") (pin "AJ23") (pinfunction "DVSS_AJ23") (pintype "passive"))
      (node (ref "U1") (pin "AJ24") (pinfunction "DVSS_AJ24") (pintype "passive"))
      (node (ref "U1") (pin "AJ25") (pinfunction "DVSS_AJ25") (pintype "passive"))
      (node (ref "U1") (pin "AJ29") (pinfunction "DVSS_AJ29") (pintype "passive"))
      (node (ref "U1") (pin "AJ31") (pinfunction "DVSS_AJ31") (pintype "passive"))
      (node (ref "U1") (pin "AJ5") (pinfunction "DVSS_AJ5") (pintype "passive"))
      (node (ref "U1") (pin "AJ8") (pinfunction "DVSS_AJ8") (pintype "passive"))
      (node (ref "U1") (pin "AJ9") (pinfunction "DVSS_AJ9") (pintype "passive"))
      (node (ref "U1") (pin "AK11") (pinfunction "DVSS_AK11") (pintype "passive"))
      (node (ref "U1") (pin "AK12") (pinfunction "DVSS_AK12") (pintype "passive"))
      (node (ref "U1") (pin "AK14") (pinfunction "DVSS_AK14") (pintype "passive"))
      (node (ref "U1") (pin "AK15") (pinfunction "DVSS_AK15") (pintype "passive"))
      (node (ref "U1") (pin "AK16") (pinfunction "DVSS_AK16") (pintype "passive"))
      (node (ref "U1") (pin "AK17") (pinfunction "DVSS_AK17") (pintype "passive"))
      (node (ref "U1") (pin "AK19") (pinfunction "DVSS_AK19") (pintype "passive"))
      (node (ref "U1") (pin "AK20") (pinfunction "DVSS_AK20") (pintype "passive"))
      (node (ref "U1") (pin "AK21") (pinfunction "DVSS_AK21") (pintype "passive"))
      (node (ref "U1") (pin "AK22") (pinfunction "DVSS_AK22") (pintype "passive"))
      (node (ref "U1") (pin "AK26") (pinfunction "DVSS_AK26") (pintype "passive"))
      (node (ref "U1") (pin "AK5") (pinfunction "DVSS_AK5") (pintype "passive"))
      (node (ref "U1") (pin "AK9") (pinfunction "DVSS_AK9") (pintype "passive"))
      (node (ref "U1") (pin "AL10") (pinfunction "AVSS_DP_AL10") (pintype "passive"))
      (node (ref "U1") (pin "AL12") (pinfunction "DVSS_AL12") (pintype "passive"))
      (node (ref "U1") (pin "AL13") (pinfunction "DVSS_AL13") (pintype "passive"))
      (node (ref "U1") (pin "AL14") (pinfunction "DVSS_AL14") (pintype "passive"))
      (node (ref "U1") (pin "AL15") (pinfunction "DVSS_AL15") (pintype "passive"))
      (node (ref "U1") (pin "AL18") (pinfunction "DVSS_AL18") (pintype "passive"))
      (node (ref "U1") (pin "AL2") (pinfunction "DVSS_AL2") (pintype "passive"))
      (node (ref "U1") (pin "AL20") (pinfunction "DVSS_AL20") (pintype "passive"))
      (node (ref "U1") (pin "AL21") (pinfunction "DVSS_AL21") (pintype "passive"))
      (node (ref "U1") (pin "AL22") (pinfunction "DVSS_AL22") (pintype "passive"))
      (node (ref "U1") (pin "AL23") (pinfunction "DVSS_AL23") (pintype "passive"))
      (node (ref "U1") (pin "AL24") (pinfunction "DVSS_AL24") (pintype "passive"))
      (node (ref "U1") (pin "AL26") (pinfunction "DVSS_AL26") (pintype "passive"))
      (node (ref "U1") (pin "AL8") (pinfunction "DVSS_AL8") (pintype "passive"))
      (node (ref "U1") (pin "AM11") (pinfunction "DVSS_AM11") (pintype "passive"))
      (node (ref "U1") (pin "AM2") (pinfunction "DVSS_AM2") (pintype "passive"))
      (node (ref "U1") (pin "AM26") (pinfunction "DVSS_AM26") (pintype "passive"))
      (node (ref "U1") (pin "AM29") (pinfunction "DVSS_AM29") (pintype "passive"))
      (node (ref "U1") (pin "AM31") (pinfunction "DVSS_AM31") (pintype "passive"))
      (node (ref "U1") (pin "AM33") (pinfunction "DVSS_AM33") (pintype "passive"))
      (node (ref "U1") (pin "AM5") (pinfunction "DVSS_AM5") (pintype "passive"))
      (node (ref "U1") (pin "AM8") (pinfunction "DVSS_AM8") (pintype "passive"))
      (node (ref "U1") (pin "AM9") (pinfunction "DVSS_AM9") (pintype "passive"))
      (node (ref "U1") (pin "AN13") (pinfunction "DVSS_AN13") (pintype "passive"))
      (node (ref "U1") (pin "AN16") (pinfunction "DVSS_AN16") (pintype "passive"))
      (node (ref "U1") (pin "AN17") (pinfunction "DVSS_AN17") (pintype "passive"))
      (node (ref "U1") (pin "AN19") (pinfunction "DVSS_AN19") (pintype "passive"))
      (node (ref "U1") (pin "AN22") (pinfunction "DVSS_AN22") (pintype "passive"))
      (node (ref "U1") (pin "AN25") (pinfunction "DVSS_AN25") (pintype "passive"))
      (node (ref "U1") (pin "AN26") (pinfunction "DVSS_AN26") (pintype "passive"))
      (node (ref "U1") (pin "AN29") (pinfunction "DVSS_AN29") (pintype "passive"))
      (node (ref "U1") (pin "AN5") (pinfunction "DVSS_AN5") (pintype "passive"))
      (node (ref "U1") (pin "AN9") (pinfunction "DVSS_AN9") (pintype "passive"))
      (node (ref "U1") (pin "AP10") (pinfunction "DVSS_AP10") (pintype "passive"))
      (node (ref "U1") (pin "AP2") (pinfunction "DVSS_AP2") (pintype "passive"))
      (node (ref "U1") (pin "AP31") (pinfunction "DVSS_AP31") (pintype "passive"))
      (node (ref "U1") (pin "AR10") (pinfunction "DVSS_AR10") (pintype "passive"))
      (node (ref "U1") (pin "AR13") (pinfunction "DVSS_AR13") (pintype "passive"))
      (node (ref "U1") (pin "AR16") (pinfunction "DVSS_AR16") (pintype "passive"))
      (node (ref "U1") (pin "AR19") (pinfunction "DVSS_AR19") (pintype "passive"))
      (node (ref "U1") (pin "AR22") (pinfunction "DVSS_AR22") (pintype "passive"))
      (node (ref "U1") (pin "AR25") (pinfunction "DVSS_AR25") (pintype "passive"))
      (node (ref "U1") (pin "AT12") (pinfunction "DVSS_AT12") (pintype "passive"))
      (node (ref "U1") (pin "AT20") (pinfunction "DVSS_AT20") (pintype "passive"))
      (node (ref "U1") (pin "AT28") (pinfunction "DVSS_AT28") (pintype "passive"))
      (node (ref "U1") (pin "AT3") (pinfunction "DVSS_AT3") (pintype "passive"))
      (node (ref "U1") (pin "AT31") (pinfunction "DVSS_AT31") (pintype "passive"))
      (node (ref "U1") (pin "AT9") (pinfunction "DVSS_AT9") (pintype "passive"))
      (node (ref "U1") (pin "AU1") (pinfunction "DVSS_AU1") (pintype "passive"))
      (node (ref "U1") (pin "AU10") (pinfunction "DVSS_AU10") (pintype "passive"))
      (node (ref "U1") (pin "AU33") (pinfunction "DVSS_AU33") (pintype "passive"))
      (node (ref "U1") (pin "AU5") (pinfunction "DVSS_AU5") (pintype "passive"))
      (node (ref "U1") (pin "AU7") (pinfunction "DVSS_AU7") (pintype "passive"))
      (node (ref "U1") (pin "B11") (pinfunction "DVSS_B11") (pintype "passive"))
      (node (ref "U1") (pin "B17") (pinfunction "DVSS_B17") (pintype "passive"))
      (node (ref "U1") (pin "B23") (pinfunction "DVSS_B23") (pintype "passive"))
      (node (ref "U1") (pin "B26") (pinfunction "DVSS_B26") (pintype "passive"))
      (node (ref "U1") (pin "B3") (pinfunction "DVSS_B3") (pintype "passive"))
      (node (ref "U1") (pin "B6") (pinfunction "DVSS_B6") (pintype "passive"))
      (node (ref "U1") (pin "B8") (pinfunction "DVSS_B8") (pintype "passive"))
      (node (ref "U1") (pin "C11") (pinfunction "DVSS_C11") (pintype "passive"))
      (node (ref "U1") (pin "C13") (pinfunction "DVSS_C13") (pintype "passive"))
      (node (ref "U1") (pin "C16") (pinfunction "DVSS_C16") (pintype "passive"))
      (node (ref "U1") (pin "C2") (pinfunction "DVSS_C2") (pintype "passive"))
      (node (ref "U1") (pin "C25") (pinfunction "DVSS_C25") (pintype "passive"))
      (node (ref "U1") (pin "C29") (pinfunction "DVSS_C29") (pintype "passive"))
      (node (ref "U1") (pin "C9") (pinfunction "DVSS_C9") (pintype "passive"))
      (node (ref "U1") (pin "D11") (pinfunction "DVSS_D11") (pintype "passive"))
      (node (ref "U1") (pin "D33") (pinfunction "DVSS_D33") (pintype "passive"))
      (node (ref "U1") (pin "D5") (pinfunction "DVSS_D5") (pintype "passive"))
      (node (ref "U1") (pin "E1") (pinfunction "DVSS_E1") (pintype "passive"))
      (node (ref "U1") (pin "E10") (pinfunction "DVSS_E10") (pintype "passive"))
      (node (ref "U1") (pin "E13") (pinfunction "DVSS_E13") (pintype "passive"))
      (node (ref "U1") (pin "E16") (pinfunction "DVSS_E16") (pintype "passive"))
      (node (ref "U1") (pin "E19") (pinfunction "DVSS_E19") (pintype "passive"))
      (node (ref "U1") (pin "E22") (pinfunction "DVSS_E22") (pintype "passive"))
      (node (ref "U1") (pin "E25") (pinfunction "DVSS_E25") (pintype "passive"))
      (node (ref "U1") (pin "E26") (pinfunction "DVSS_E26") (pintype "passive"))
      (node (ref "U1") (pin "E29") (pinfunction "DVSS_E29") (pintype "passive"))
      (node (ref "U1") (pin "E7") (pinfunction "DVSS_E7") (pintype "passive"))
      (node (ref "U1") (pin "E9") (pinfunction "DVSS_E9") (pintype "passive"))
      (node (ref "U1") (pin "F23") (pinfunction "DVSS_F23") (pintype "passive"))
      (node (ref "U1") (pin "F26") (pinfunction "DVSS_F26") (pintype "passive"))
      (node (ref "U1") (pin "F6") (pinfunction "DVSS_F6") (pintype "passive"))
      (node (ref "U1") (pin "G10") (pinfunction "DVSS_G10") (pintype "passive"))
      (node (ref "U1") (pin "G11") (pinfunction "DVSS_G11") (pintype "passive"))
      (node (ref "U1") (pin "G13") (pinfunction "DVSS_G13") (pintype "passive"))
      (node (ref "U1") (pin "G14") (pinfunction "DVSS_G14") (pintype "passive"))
      (node (ref "U1") (pin "G15") (pinfunction "DVSS_G15") (pintype "passive"))
      (node (ref "U1") (pin "G17") (pinfunction "DVSS_G17") (pintype "passive"))
      (node (ref "U1") (pin "G19") (pinfunction "DVSS_G19") (pintype "passive"))
      (node (ref "U1") (pin "G2") (pinfunction "DVSS_G2") (pintype "passive"))
      (node (ref "U1") (pin "G20") (pinfunction "DVSS_G20") (pintype "passive"))
      (node (ref "U1") (pin "G22") (pinfunction "DVSS_G22") (pintype "passive"))
      (node (ref "U1") (pin "G23") (pinfunction "DVSS_G23") (pintype "passive"))
      (node (ref "U1") (pin "G24") (pinfunction "DVSS_G24") (pintype "passive"))
      (node (ref "U1") (pin "G25") (pinfunction "DVSS_G25") (pintype "passive"))
      (node (ref "U1") (pin "G26") (pinfunction "DVSS_G26") (pintype "passive"))
      (node (ref "U1") (pin "G8") (pinfunction "DVSS_G8") (pintype "passive"))
      (node (ref "U1") (pin "H1") (pinfunction "DVSS_H1") (pintype "passive"))
      (node (ref "U1") (pin "H11") (pinfunction "DVSS_H11") (pintype "passive"))
      (node (ref "U1") (pin "H14") (pinfunction "DVSS_H14") (pintype "passive"))
      (node (ref "U1") (pin "H17") (pinfunction "DVSS_H17") (pintype "passive"))
      (node (ref "U1") (pin "H18") (pinfunction "DVSS_H18") (pintype "passive"))
      (node (ref "U1") (pin "H19") (pinfunction "DVSS_H19") (pintype "passive"))
      (node (ref "U1") (pin "H20") (pinfunction "DVSS_H20") (pintype "passive"))
      (node (ref "U1") (pin "H23") (pinfunction "DVSS_H23") (pintype "passive"))
      (node (ref "U1") (pin "H26") (pinfunction "DVSS_H26") (pintype "passive"))
      (node (ref "U1") (pin "H29") (pinfunction "DVSS_H29") (pintype "passive"))
      (node (ref "U1") (pin "H5") (pinfunction "DVSS_H5") (pintype "passive"))
      (node (ref "U1") (pin "H9") (pinfunction "DVSS_H9") (pintype "passive"))
      (node (ref "U1") (pin "J10") (pinfunction "DVSS_J10") (pintype "passive"))
      (node (ref "U1") (pin "J13") (pinfunction "DVSS_J13") (pintype "passive"))
      (node (ref "U1") (pin "J14") (pinfunction "DVSS_J14") (pintype "passive"))
      (node (ref "U1") (pin "J16") (pinfunction "DVSS_J16") (pintype "passive"))
      (node (ref "U1") (pin "J17") (pinfunction "DVSS_J17") (pintype "passive"))
      (node (ref "U1") (pin "J18") (pinfunction "DVSS_J18") (pintype "passive"))
      (node (ref "U1") (pin "J21") (pinfunction "DVSS_J21") (pintype "passive"))
      (node (ref "U1") (pin "J22") (pinfunction "DVSS_J22") (pintype "passive"))
      (node (ref "U1") (pin "J23") (pinfunction "DVSS_J23") (pintype "passive"))
      (node (ref "U1") (pin "J24") (pinfunction "DVSS_J24") (pintype "passive"))
      (node (ref "U1") (pin "J26") (pinfunction "DVSS_J26") (pintype "passive"))
      (node (ref "U1") (pin "J8") (pinfunction "DVSS_J8") (pintype "passive"))
      (node (ref "U1") (pin "J9") (pinfunction "DVSS_J9") (pintype "passive"))
      (node (ref "U1") (pin "K10") (pinfunction "DVSS_K10") (pintype "passive"))
      (node (ref "U1") (pin "K11") (pinfunction "DVSS_K11") (pintype "passive"))
      (node (ref "U1") (pin "K14") (pinfunction "DVSS_K14") (pintype "passive"))
      (node (ref "U1") (pin "K18") (pinfunction "DVSS_K18") (pintype "passive"))
      (node (ref "U1") (pin "K2") (pinfunction "DVSS_K2") (pintype "passive"))
      (node (ref "U1") (pin "K22") (pinfunction "DVSS_K22") (pintype "passive"))
      (node (ref "U1") (pin "K23") (pinfunction "DVSS_K23") (pintype "passive"))
      (node (ref "U1") (pin "K25") (pinfunction "DVSS_K25") (pintype "passive"))
      (node (ref "U1") (pin "K26") (pinfunction "DVSS_K26") (pintype "passive"))
      (node (ref "U1") (pin "K8") (pinfunction "DVSS_K8") (pintype "passive"))
      (node (ref "U1") (pin "L1") (pinfunction "DVSS_L1") (pintype "passive"))
      (node (ref "U1") (pin "L11") (pinfunction "DVSS_L11") (pintype "passive"))
      (node (ref "U1") (pin "L13") (pinfunction "DVSS_L13") (pintype "passive"))
      (node (ref "U1") (pin "L14") (pinfunction "DVSS_L14") (pintype "passive"))
      (node (ref "U1") (pin "L16") (pinfunction "DVSS_L16") (pintype "passive"))
      (node (ref "U1") (pin "L18") (pinfunction "DVSS_L18") (pintype "passive"))
      (node (ref "U1") (pin "L19") (pinfunction "DVSS_L19") (pintype "passive"))
      (node (ref "U1") (pin "L20") (pinfunction "DVSS_L20") (pintype "passive"))
      (node (ref "U1") (pin "L21") (pinfunction "DVSS_L21") (pintype "passive"))
      (node (ref "U1") (pin "L23") (pinfunction "DVSS_L23") (pintype "passive"))
      (node (ref "U1") (pin "L24") (pinfunction "DVSS_L24") (pintype "passive"))
      (node (ref "U1") (pin "L26") (pinfunction "DVSS_L26") (pintype "passive"))
      (node (ref "U1") (pin "L29") (pinfunction "DVSS_L29") (pintype "passive"))
      (node (ref "U1") (pin "L31") (pinfunction "DVSS_L31") (pintype "passive"))
      (node (ref "U1") (pin "L5") (pinfunction "DVSS_L5") (pintype "passive"))
      (node (ref "U1") (pin "L9") (pinfunction "DVSS_L9") (pintype "passive"))
      (node (ref "U1") (pin "M10") (pinfunction "DVSS_M10") (pintype "passive"))
      (node (ref "U1") (pin "M14") (pinfunction "DVSS_M14") (pintype "passive"))
      (node (ref "U1") (pin "M17") (pinfunction "DVSS_M17") (pintype "passive"))
      (node (ref "U1") (pin "M24") (pinfunction "DVSS_M24") (pintype "passive"))
      (node (ref "U1") (pin "M26") (pinfunction "DVSS_M26") (pintype "passive"))
      (node (ref "U1") (pin "M8") (pinfunction "DVSS_M8") (pintype "passive"))
      (node (ref "U1") (pin "M9") (pinfunction "DVSS_M9") (pintype "passive"))
      (node (ref "U1") (pin "N10") (pinfunction "DVSS_N10") (pintype "passive"))
      (node (ref "U1") (pin "N11") (pinfunction "DVSS_N11") (pintype "passive"))
      (node (ref "U1") (pin "N13") (pinfunction "DVSS_N13") (pintype "passive"))
      (node (ref "U1") (pin "N14") (pinfunction "DVSS_N14") (pintype "passive"))
      (node (ref "U1") (pin "N16") (pinfunction "DVSS_N16") (pintype "passive"))
      (node (ref "U1") (pin "N17") (pinfunction "DVSS_N17") (pintype "passive"))
      (node (ref "U1") (pin "N19") (pinfunction "DVSS_N19") (pintype "passive"))
      (node (ref "U1") (pin "N2") (pinfunction "DVSS_N2") (pintype "passive"))
      (node (ref "U1") (pin "N21") (pinfunction "DVSS_N21") (pintype "passive"))
      (node (ref "U1") (pin "N23") (pinfunction "DVSS_N23") (pintype "passive"))
      (node (ref "U1") (pin "N24") (pinfunction "DVSS_N24") (pintype "passive"))
      (node (ref "U1") (pin "N25") (pinfunction "DVSS_N25") (pintype "passive"))
      (node (ref "U1") (pin "N26") (pinfunction "DVSS_N26") (pintype "passive"))
      (node (ref "U1") (pin "N6") (pinfunction "DVSS_N6") (pintype "passive"))
      (node (ref "U1") (pin "P1") (pinfunction "DVSS_P1") (pintype "passive"))
      (node (ref "U1") (pin "P11") (pinfunction "DVSS_P11") (pintype "passive"))
      (node (ref "U1") (pin "P14") (pinfunction "DVSS_P14") (pintype "passive"))
      (node (ref "U1") (pin "P17") (pinfunction "DVSS_P17") (pintype "passive"))
      (node (ref "U1") (pin "P18") (pinfunction "DVSS_P18") (pintype "passive"))
      (node (ref "U1") (pin "P19") (pinfunction "DVSS_P19") (pintype "passive"))
      (node (ref "U1") (pin "P20") (pinfunction "DVSS_P20") (pintype "passive"))
      (node (ref "U1") (pin "P21") (pinfunction "DVSS_P21") (pintype "passive"))
      (node (ref "U1") (pin "P22") (pinfunction "DVSS_P22") (pintype "passive"))
      (node (ref "U1") (pin "P23") (pinfunction "DVSS_P23") (pintype "passive"))
      (node (ref "U1") (pin "P25") (pinfunction "DVSS_P25") (pintype "passive"))
      (node (ref "U1") (pin "P26") (pinfunction "DVSS_P26") (pintype "passive"))
      (node (ref "U1") (pin "P29") (pinfunction "DVSS_P29") (pintype "passive"))
      (node (ref "U1") (pin "P5") (pinfunction "DVSS_P5") (pintype "passive"))
      (node (ref "U1") (pin "P9") (pinfunction "DVSS_P9") (pintype "passive"))
      (node (ref "U1") (pin "R10") (pinfunction "DVSS_R10") (pintype "passive"))
      (node (ref "U1") (pin "R13") (pinfunction "DVSS_R13") (pintype "passive"))
      (node (ref "U1") (pin "R14") (pinfunction "DVSS_R14") (pintype "passive"))
      (node (ref "U1") (pin "R16") (pinfunction "DVSS_R16") (pintype "passive"))
      (node (ref "U1") (pin "R17") (pinfunction "DVSS_R17") (pintype "passive"))
      (node (ref "U1") (pin "R24") (pinfunction "DVSS_R24") (pintype "passive"))
      (node (ref "U1") (pin "R26") (pinfunction "DVSS_R26") (pintype "passive"))
      (node (ref "U1") (pin "R5") (pinfunction "DVSS_R5") (pintype "passive"))
      (node (ref "U1") (pin "R8") (pinfunction "DVSS_R8") (pintype "passive"))
      (node (ref "U1") (pin "R9") (pinfunction "DVSS_R9") (pintype "passive"))
      (node (ref "U1") (pin "T10") (pinfunction "DVSS_T10") (pintype "passive"))
      (node (ref "U1") (pin "T11") (pinfunction "DVSS_T11") (pintype "passive"))
      (node (ref "U1") (pin "T14") (pinfunction "DVSS_T14") (pintype "passive"))
      (node (ref "U1") (pin "T17") (pinfunction "DVSS_T17") (pintype "passive"))
      (node (ref "U1") (pin "T19") (pinfunction "DVSS_T19") (pintype "passive"))
      (node (ref "U1") (pin "T2") (pinfunction "DVSS_T2") (pintype "passive"))
      (node (ref "U1") (pin "T21") (pinfunction "DVSS_T21") (pintype "passive"))
      (node (ref "U1") (pin "T23") (pinfunction "DVSS_T23") (pintype "passive"))
      (node (ref "U1") (pin "T24") (pinfunction "DVSS_T24") (pintype "passive"))
      (node (ref "U1") (pin "T25") (pinfunction "DVSS_T25") (pintype "passive"))
      (node (ref "U1") (pin "T26") (pinfunction "DVSS_T26") (pintype "passive"))
      (node (ref "U1") (pin "T5") (pinfunction "DVSS_T5") (pintype "passive"))
      (node (ref "U1") (pin "T8") (pinfunction "DVSS_T8") (pintype "passive"))
      (node (ref "U1") (pin "U1") (pinfunction "DVSS_U1") (pintype "passive"))
      (node (ref "U1") (pin "U11") (pinfunction "DVSS_U11") (pintype "passive"))
      (node (ref "U1") (pin "U12") (pinfunction "DVSS_U12") (pintype "passive"))
      (node (ref "U1") (pin "U13") (pinfunction "DVSS_U13") (pintype "passive"))
      (node (ref "U1") (pin "U14") (pinfunction "DVSS_U14") (pintype "passive"))
      (node (ref "U1") (pin "U15") (pinfunction "DVSS_U15") (pintype "passive"))
      (node (ref "U1") (pin "U16") (pinfunction "DVSS_U16") (pintype "passive"))
      (node (ref "U1") (pin "U17") (pinfunction "DVSS_U17") (pintype "passive"))
      (node (ref "U1") (pin "U18") (pinfunction "DVSS_U18") (pintype "passive"))
      (node (ref "U1") (pin "U19") (pinfunction "DVSS_U19") (pintype "passive"))
      (node (ref "U1") (pin "U20") (pinfunction "DVSS_U20") (pintype "passive"))
      (node (ref "U1") (pin "U21") (pinfunction "DVSS_U21") (pintype "passive"))
      (node (ref "U1") (pin "U22") (pinfunction "DVSS_U22") (pintype "passive"))
      (node (ref "U1") (pin "U23") (pinfunction "DVSS_U23") (pintype "passive"))
      (node (ref "U1") (pin "U24") (pinfunction "DVSS_U24") (pintype "passive"))
      (node (ref "U1") (pin "U25") (pinfunction "DVSS_U25") (pintype "passive"))
      (node (ref "U1") (pin "U29") (pinfunction "DVSS_U29") (pintype "passive"))
      (node (ref "U1") (pin "U32") (pinfunction "DVSS_U32") (pintype "passive"))
      (node (ref "U1") (pin "U9") (pinfunction "DVSS_U9") (pintype "passive"))
      (node (ref "U1") (pin "V10") (pinfunction "DVSS_V10") (pintype "passive"))
      (node (ref "U1") (pin "V12") (pinfunction "DVSS_V12") (pintype "passive"))
      (node (ref "U1") (pin "V13") (pinfunction "DVSS_V13") (pintype "passive"))
      (node (ref "U1") (pin "V15") (pinfunction "DVSS_V15") (pintype "passive"))
      (node (ref "U1") (pin "V17") (pinfunction "DVSS_V17") (pintype "passive"))
      (node (ref "U1") (pin "V18") (pinfunction "DVSS_V18") (pintype "passive"))
      (node (ref "U1") (pin "V24") (pinfunction "DVSS_V24") (pintype "passive"))
      (node (ref "U1") (pin "V26") (pinfunction "DVSS_V26") (pintype "passive"))
      (node (ref "U1") (pin "V6") (pinfunction "DVSS_V6") (pintype "passive"))
      (node (ref "U1") (pin "V8") (pinfunction "DVSS_V8") (pintype "passive"))
      (node (ref "U1") (pin "V9") (pinfunction "DVSS_V9") (pintype "passive"))
      (node (ref "U1") (pin "W10") (pinfunction "DVSS_W10") (pintype "passive"))
      (node (ref "U1") (pin "W11") (pinfunction "DVSS_W11") (pintype "passive"))
      (node (ref "U1") (pin "W12") (pinfunction "DVSS_W12") (pintype "passive"))
      (node (ref "U1") (pin "W18") (pinfunction "DVSS_W18") (pintype "passive"))
      (node (ref "U1") (pin "W2") (pinfunction "DVSS_W2") (pintype "passive"))
      (node (ref "U1") (pin "W20") (pinfunction "DVSS_W20") (pintype "passive"))
      (node (ref "U1") (pin "W22") (pinfunction "DVSS_W22") (pintype "passive"))
      (node (ref "U1") (pin "W24") (pinfunction "DVSS_W24") (pintype "passive"))
      (node (ref "U1") (pin "W25") (pinfunction "DVSS_W25") (pintype "passive"))
      (node (ref "U1") (pin "W26") (pinfunction "DVSS_W26") (pintype "passive"))
      (node (ref "U1") (pin "W28") (pinfunction "DVSS_W28") (pintype "passive"))
      (node (ref "U1") (pin "Y1") (pinfunction "DVSS_Y1") (pintype "passive"))
      (node (ref "U1") (pin "Y10") (pinfunction "DVSS_Y10") (pintype "passive"))
      (node (ref "U1") (pin "Y12") (pinfunction "DVSS_Y12") (pintype "passive"))
      (node (ref "U1") (pin "Y13") (pinfunction "DVSS_Y13") (pintype "passive"))
      (node (ref "U1") (pin "Y14") (pinfunction "DVSS_Y14") (pintype "passive"))
      (node (ref "U1") (pin "Y15") (pinfunction "DVSS_Y15") (pintype "passive"))
      (node (ref "U1") (pin "Y16") (pinfunction "DVSS_Y16") (pintype "passive"))
      (node (ref "U1") (pin "Y17") (pinfunction "DVSS_Y17") (pintype "passive"))
      (node (ref "U1") (pin "Y18") (pinfunction "DVSS_Y18") (pintype "passive"))
      (node (ref "U1") (pin "Y19") (pinfunction "DVSS_Y19") (pintype "passive"))
      (node (ref "U1") (pin "Y20") (pinfunction "DVSS_Y20") (pintype "passive"))
      (node (ref "U1") (pin "Y21") (pinfunction "DVSS_Y21") (pintype "passive"))
      (node (ref "U1") (pin "Y22") (pinfunction "DVSS_Y22") (pintype "passive"))
      (node (ref "U1") (pin "Y23") (pinfunction "DVSS_Y23") (pintype "passive"))
      (node (ref "U1") (pin "Y24") (pinfunction "DVSS_Y24") (pintype "passive"))
      (node (ref "U1") (pin "Y26") (pinfunction "DVSS_Y26") (pintype "passive"))
      (node (ref "U1") (pin "Y29") (pinfunction "DVSS_Y29") (pintype "passive"))
      (node (ref "U1") (pin "Y31") (pinfunction "DVSS_Y31") (pintype "passive"))
      (node (ref "U1") (pin "Y5") (pinfunction "DVSS_Y5") (pintype "passive"))
      (node (ref "U1") (pin "Y8") (pinfunction "DVSS_Y8") (pintype "passive"))
      (node (ref "U1") (pin "Y9") (pinfunction "DVSS_Y9") (pintype "passive"))
      (node (ref "U10") (pin "3") (pinfunction "VSS_3") (pintype "power_in"))
      (node (ref "U11") (pin "3") (pinfunction "VSS_3") (pintype "power_in"))
      (node (ref "U12") (pin "11") (pinfunction "GND_11") (pintype "power_in"))
      (node (ref "U12") (pin "15") (pinfunction "GND_15") (pintype "power_in"))
      (node (ref "U12") (pin "17") (pinfunction "EP_17") (pintype "power_in"))
      (node (ref "U12") (pin "3") (pinfunction "GND_3") (pintype "power_in"))
      (node (ref "U13") (pin "3") (pinfunction "VSS_3") (pintype "power_in"))
      (node (ref "U14") (pin "3") (pinfunction "VSS_3") (pintype "power_in"))
      (node (ref "U15") (pin "4") (pinfunction "LR_4") (pintype "passive"))
      (node (ref "U15") (pin "5") (pinfunction "GND_5") (pintype "power_in"))
      (node (ref "U16") (pin "5") (pinfunction "GND_5") (pintype "power_in"))
      (node (ref "U17") (pin "3") (pinfunction "VSS_3") (pintype "power_in"))
      (node (ref "U18") (pin "3") (pinfunction "VSS_3") (pintype "power_in"))
      (node (ref "U19") (pin "3") (pinfunction "VSS_3") (pintype "power_in"))
      (node (ref "U2") (pin "4") (pinfunction "VSS_4") (pintype "power_in"))
      (node (ref "U20") (pin "3") (pinfunction "VSS_3") (pintype "power_in"))
      (node (ref "U21") (pin "3") (pinfunction "VSS_3") (pintype "power_in"))
      (node (ref "U22") (pin "3") (pinfunction "VSS_3") (pintype "power_in"))
      (node (ref "U23") (pin "3") (pinfunction "VSS_3") (pintype "power_in"))
      (node (ref "U24") (pin "3") (pinfunction "VSS_3") (pintype "power_in"))
      (node (ref "U25") (pin "3") (pinfunction "VSS_3") (pintype "power_in"))
      (node (ref "U26") (pin "3") (pinfunction "VSS_3") (pintype "power_in"))
      (node (ref "U3") (pin "27") (pinfunction "PB3_27") (pintype "bidirectional"))
      (node (ref "U3") (pin "29") (pinfunction "PB5_29") (pintype "bidirectional"))
      (node (ref "U3") (pin "5") (pinfunction "VSS_5") (pintype "power_in"))
      (node (ref "U4") (pin "A10") (pinfunction "VSS_2_A10") (pintype "passive"))
      (node (ref "U4") (pin "A3") (pinfunction "VSS_1_A3") (pintype "passive"))
      (node (ref "U4") (pin "AB10") (pinfunction "VSS_58_AB10") (pintype "passive"))
      (node (ref "U4") (pin "AB3") (pinfunction "VSS_55_AB3") (pintype "passive"))
      (node (ref "U4") (pin "AB5") (pinfunction "VSS_56_AB5") (pintype "passive"))
      (node (ref "U4") (pin "AB8") (pinfunction "VSS_57_AB8") (pintype "passive"))
      (node (ref "U4") (pin "C1") (pinfunction "VSS_3_C1") (pintype "passive"))
      (node (ref "U4") (pin "C12") (pinfunction "VSS_6_C12") (pintype "passive"))
      (node (ref "U4") (pin "C5") (pinfunction "VSS_4_C5") (pintype "passive"))
      (node (ref "U4") (pin "C8") (pinfunction "VSS_5_C8") (pintype "passive"))
      (node (ref "U4") (pin "D11") (pinfunction "VSS_10_D11") (pintype "passive"))
      (node (ref "U4") (pin "D2") (pinfunction "VSS_7_D2") (pintype "passive"))
      (node (ref "U4") (pin "D4") (pinfunction "VSS_8_D4") (pintype "passive"))
      (node (ref "U4") (pin "D9") (pinfunction "VSS_9_D9") (pintype "passive"))
      (node (ref "U4") (pin "E1") (pinfunction "VSS_11_E1") (pintype "passive"))
      (node (ref "U4") (pin "E12") (pinfunction "VSS_14_E12") (pintype "passive"))
      (node (ref "U4") (pin "E5") (pinfunction "VSS_12_E5") (pintype "passive"))
      (node (ref "U4") (pin "E8") (pinfunction "VSS_13_E8") (pintype "passive"))
      (node (ref "U4") (pin "G1") (pinfunction "VSS_15_G1") (pintype "passive"))
      (node (ref "U4") (pin "G10") (pinfunction "VSS_19_G10") (pintype "passive"))
      (node (ref "U4") (pin "G12") (pinfunction "VSS_20_G12") (pintype "passive"))
      (node (ref "U4") (pin "G3") (pinfunction "VSS_16_G3") (pintype "passive"))
      (node (ref "U4") (pin "G5") (pinfunction "VSS_17_G5") (pintype "passive"))
      (node (ref "U4") (pin "G8") (pinfunction "VSS_18_G8") (pintype "passive"))
      (node (ref "U4") (pin "J1") (pinfunction "VSS_21_J1") (pintype "passive"))
      (node (ref "U4") (pin "J10") (pinfunction "VSS_23_J10") (pintype "passive"))
      (node (ref "U4") (pin "J12") (pinfunction "VSS_24_J12") (pintype "passive"))
      (node (ref "U4") (pin "J3") (pinfunction "VSS_22_J3") (pintype "passive"))
      (node (ref "U4") (pin "K11") (pinfunction "VSS_28_K11") (pintype "passive"))
      (node (ref "U4") (pin "K2") (pinfunction "VSS_25_K2") (pintype "passive"))
      (node (ref "U4") (pin "K4") (pinfunction "VSS_26_K4") (pintype "passive"))
      (node (ref "U4") (pin "K9") (pinfunction "VSS_27_K9") (pintype "passive"))
      (node (ref "U4") (pin "N11") (pinfunction "VSS_32_N11") (pintype "passive"))
      (node (ref "U4") (pin "N2") (pinfunction "VSS_29_N2") (pintype "passive"))
      (node (ref "U4") (pin "N4") (pinfunction "VSS_30_N4") (pintype "passive"))
      (node (ref "U4") (pin "N9") (pinfunction "VSS_31_N9") (pintype "passive"))
      (node (ref "U4") (pin "P1") (pinfunction "VSS_33_P1") (pintype "passive"))
      (node (ref "U4") (pin "P10") (pinfunction "VSS_35_P10") (pintype "passive"))
      (node (ref "U4") (pin "P12") (pinfunction "VSS_36_P12") (pintype "passive"))
      (node (ref "U4") (pin "P3") (pinfunction "VSS_34_P3") (pintype "passive"))
      (node (ref "U4") (pin "T1") (pinfunction "VSS_37_T1") (pintype "passive"))
      (node (ref "U4") (pin "T10") (pinfunction "VSS_41_T10") (pintype "passive"))
      (node (ref "U4") (pin "T12") (pinfunction "VSS_42_T12") (pintype "passive"))
      (node (ref "U4") (pin "T3") (pinfunction "VSS_38_T3") (pintype "passive"))
      (node (ref "U4") (pin "T5") (pinfunction "VSS_39_T5") (pintype "passive"))
      (node (ref "U4") (pin "T8") (pinfunction "VSS_40_T8") (pintype "passive"))
      (node (ref "U4") (pin "V1") (pinfunction "VSS_43_V1") (pintype "passive"))
      (node (ref "U4") (pin "V12") (pinfunction "VSS_46_V12") (pintype "passive"))
      (node (ref "U4") (pin "V5") (pinfunction "VSS_44_V5") (pintype "passive"))
      (node (ref "U4") (pin "V8") (pinfunction "VSS_45_V8") (pintype "passive"))
      (node (ref "U4") (pin "W11") (pinfunction "VSS_50_W11") (pintype "passive"))
      (node (ref "U4") (pin "W2") (pinfunction "VSS_47_W2") (pintype "passive"))
      (node (ref "U4") (pin "W4") (pinfunction "VSS_48_W4") (pintype "passive"))
      (node (ref "U4") (pin "W9") (pinfunction "VSS_49_W9") (pintype "passive"))
      (node (ref "U4") (pin "Y1") (pinfunction "VSS_51_Y1") (pintype "passive"))
      (node (ref "U4") (pin "Y12") (pinfunction "VSS_54_Y12") (pintype "passive"))
      (node (ref "U4") (pin "Y5") (pinfunction "VSS_52_Y5") (pintype "passive"))
      (node (ref "U4") (pin "Y8") (pinfunction "VSS_53_Y8") (pintype "passive"))
      (node (ref "U5") (pin "A6") (pinfunction "VSS_A6") (pintype "power_in"))
      (node (ref "U5") (pin "C4") (pinfunction "VSS_C4") (pintype "power_in"))
      (node (ref "U5") (pin "E7") (pinfunction "VSS_E7") (pintype "power_in"))
      (node (ref "U5") (pin "G5") (pinfunction "VSS_G5") (pintype "power_in"))
      (node (ref "U5") (pin "H10") (pinfunction "VSS_H10") (pintype "power_in"))
      (node (ref "U5") (pin "J5") (pinfunction "VSS_J5") (pintype "power_in"))
      (node (ref "U5") (pin "K8") (pinfunction "VSS_K8") (pintype "power_in"))
      (node (ref "U5") (pin "N2") (pinfunction "VSS_N2") (pintype "power_in"))
      (node (ref "U5") (pin "N5") (pinfunction "VSS_N5") (pintype "power_in"))
      (node (ref "U5") (pin "P4") (pinfunction "VSS_P4") (pintype "power_in"))
      (node (ref "U5") (pin "P6") (pinfunction "VSS_P6") (pintype "power_in"))
      (node (ref "U6") (pin "5") (pinfunction "GND_5") (pintype "power_in"))
      (node (ref "U6") (pin "9") (pinfunction "GND_9") (pintype "power_in"))
      (node (ref "U7") (pin "9") (pinfunction "ST_9") (pintype "output"))
      (node (ref "U8") (pin "3") (pinfunction "VSS_3") (pintype "power_in"))
      (node (ref "U9") (pin "3") (pinfunction "VSS_3") (pintype "power_in"))
      (node (ref "X1") (pin "2") (pinfunction "GND_2") (pintype "power_in"))
      (node (ref "X1") (pin "4") (pinfunction "GND_4") (pintype "power_in"))
      (node (ref "Y2") (pin "2") (pinfunction "GND_2") (pintype "power_in"))
      (node (ref "Y2") (pin "4") (pinfunction "NC_4") (pintype "passive"))
    )
    (net (code "260") (name "Net-(*-SCL)") (class "Default")
      (node (ref "*") (pin "6") (pinfunction "SCL_6") (pintype "passive"))
      (node (ref "R77") (pin "1") (pinfunction "1_1") (pintype "passive"))
    )
    (net (code "261") (name "Net-(*-SDA)") (class "Default")
      (node (ref "*") (pin "7") (pinfunction "SDA_7") (pintype "passive"))
      (node (ref "R78") (pin "1") (pinfunction "1_1") (pintype "passive"))
    )
    (net (code "262") (name "Net-(B2-ABUCK_1P12)") (class "Default")
      (node (ref "B2") (pin "29") (pinfunction "ABUCK_1P12_29") (pintype "passive"))
      (node (ref "C138") (pin "1") (pinfunction "1_1") (pintype "passive"))
      (node (ref "L5") (pin "1") (pinfunction "1_1") (pintype "passive"))
    )
    (net (code "263") (name "Net-(B2-ASR_VLX)") (class "Default")
      (node (ref "B2") (pin "28") (pinfunction "ASR_VLX_28") (pintype "passive"))
      (node (ref "L5") (pin "2") (pinfunction "2_2") (pintype "passive"))
    )
    (net (code "264") (name "Net-(B2-BT_HOST_WAKE)") (class "Default")
      (node (ref "B2") (pin "50") (pinfunction "BT_HOST_WAKE_50") (pintype "passive"))
      (node (ref "R52") (pin "1") (pinfunction "1_1") (pintype "passive"))
    )
    (net (code "265") (name "Net-(B2-BT_WAKE)") (class "Default")
      (node (ref "B2") (pin "49") (pinfunction "BT_WAKE_49") (pintype "passive"))
      (node (ref "R53") (pin "1") (pinfunction "1_1") (pintype "passive"))
    )
    (net (code "266") (name "Net-(B2-CBUCK_0P9)") (class "Default")
      (node (ref "B2") (pin "25") (pinfunction "CBUCK_0P9_25") (pintype "passive"))
      (node (ref "C130") (pin "1") (pinfunction "1_1") (pintype "passive"))
      (node (ref "L4") (pin "1") (pinfunction "1_1") (pintype "passive"))
    )
    (net (code "267") (name "Net-(B2-CSR_VLX)") (class "Default")
      (node (ref "B2") (pin "26") (pinfunction "CSR_VLX_26") (pintype "passive"))
      (node (ref "L4") (pin "2") (pinfunction "2_2") (pintype "passive"))
    )
    (net (code "268") (name "Net-(B2-LPO)") (class "Default")
      (node (ref "B2") (pin "31") (pinfunction "LPO_31") (pintype "passive"))
      (node (ref "R72") (pin "2") (pinfunction "2_2") (pintype "passive"))
    )
    (net (code "269") (name "Net-(B2-VDDIO)") (class "Default")
      (node (ref "B2") (pin "34") (pinfunction "VDDIO_34") (pintype "passive"))
      (node (ref "C132") (pin "1") (pinfunction "1_1") (pintype "passive"))
    )
    (net (code "270") (name "Net-(B2-WL_HOST_WAKE{slash}WL_GPIO_0)") (class "Default")
      (node (ref "B2") (pin "16") (pinfunction "WL_HOST_WAKE/WL_GPIO_0_16") (pintype "passive"))
      (node (ref "R56") (pin "2") (pinfunction "2_2") (pintype "passive"))
    )
    (net (code "271") (name "Net-(B2-XTAL_IN)") (class "Default")
      (node (ref "B2") (pin "13") (pinfunction "XTAL_IN_13") (pintype "passive"))
      (node (ref "C126") (pin "1") (pinfunction "1_1") (pintype "passive"))
      (node (ref "Y2") (pin "1") (pinfunction "1_1") (pintype "passive"))
    )
    (net (code "272") (name "Net-(B2-XTAL_OUT)") (class "Default")
      (node (ref "B2") (pin "14") (pinfunction "XTAL_OUT_14") (pintype "passive"))
      (node (ref "R54") (pin "2") (pinfunction "2_2") (pintype "passive"))
    )
    (net (code "273") (name "Net-(C127-Pad1)") (class "Default")
      (node (ref "C127") (pin "1") (pinfunction "1_1") (pintype "passive"))
      (node (ref "R54") (pin "1") (pinfunction "1_1") (pintype "passive"))
      (node (ref "Y2") (pin "3") (pinfunction "3_3") (pintype "passive"))
    )
    (net (code "274") (name "Net-(D1-C)") (class "Default")
      (node (ref "D1") (pin "1") (pinfunction "C_1") (pintype "passive"))
      (node (ref "D2") (pin "1") (pinfunction "C_1") (pintype "passive"))
      (node (ref "U2") (pin "8") (pinfunction "VDD_8") (pintype "power_in"))
    )
    (net (code "275") (name "Net-(D2-A)") (class "Default")
      (node (ref "D2") (pin "2") (pinfunction "A_2") (pintype "passive"))
      (node (ref "J1") (pin "1") (pinfunction "1_1") (pintype "passive"))
    )
    (net (code "276") (name "Net-(D3-A)") (class "Default")
      (node (ref "C23") (pin "1") (pinfunction "1_1") (pintype "passive"))
      (node (ref "D3") (pin "2") (pinfunction "A_2") (pintype "passive"))
      (node (ref "R17") (pin "1") (pinfunction "1_1") (pintype "passive"))
      (node (ref "R22") (pin "1") (pinfunction "1_1") (pintype "passive"))
    )
    (net (code "277") (name "Net-(D3-C)") (class "Default")
      (node (ref "D3") (pin "1") (pinfunction "C_1") (pintype "passive"))
      (node (ref "D4") (pin "1") (pinfunction "C_1") (pintype "passive"))
      (node (ref "SW1") (pin "B") (pinfunction "B_B") (pintype "passive"))
    )
    (net (code "278") (name "Net-(D4-A)") (class "Default")
      (node (ref "C40") (pin "1") (pinfunction "1_1") (pintype "passive"))
      (node (ref "D4") (pin "2") (pinfunction "A_2") (pintype "passive"))
      (node (ref "R26") (pin "1") (pinfunction "1_1") (pintype "passive"))
      (node (ref "R28") (pin "1") (pinfunction "1_1") (pintype "passive"))
    )
    (net (code "279") (name "Net-(D5-C)") (class "Default")
      (node (ref "D5") (pin "1") (pinfunction "C_1") (pintype "passive"))
      (node (ref "D6") (pin "1") (pinfunction "C_1") (pintype "passive"))
      (node (ref "D9") (pin "1") (pinfunction "C_1") (pintype "passive"))
    )
    (net (code "280") (name "Net-(D7-A)") (class "Default")
      (node (ref "D7") (pin "2") (pinfunction "A_2") (pintype "passive"))
      (node (ref "R33") (pin "1") (pinfunction "1_1") (pintype "passive"))
    )
    (net (code "281") (name "Net-(D7-C)") (class "Default")
      (node (ref "D7") (pin "1") (pinfunction "C_1") (pintype "passive"))
      (node (ref "D8") (pin "1") (pinfunction "C_1") (pintype "passive"))
      (node (ref "SW2") (pin "B") (pinfunction "B_B") (pintype "passive"))
    )
    (net (code "282") (name "Net-(D8-A)") (class "Default")
      (node (ref "C79") (pin "1") (pinfunction "1_1") (pintype "passive"))
      (node (ref "D8") (pin "2") (pinfunction "A_2") (pintype "passive"))
      (node (ref "R35") (pin "1") (pinfunction "1_1") (pintype "passive"))
      (node (ref "R37") (pin "1") (pinfunction "1_1") (pintype "passive"))
    )
    (net (code "283") (name "Net-(D10-A)") (class "Default")
      (node (ref "C125") (pin "1") (pinfunction "1_1") (pintype "passive"))
      (node (ref "D10") (pin "2") (pinfunction "A_2") (pintype "passive"))
      (node (ref "R57") (pin "1") (pinfunction "1_1") (pintype "passive"))
      (node (ref "R60") (pin "1") (pinfunction "1_1") (pintype "passive"))
    )
    (net (code "284") (name "Net-(D10-C)") (class "Default")
      (node (ref "C137") (pin "1") (pinfunction "1_1") (pintype "passive"))
      (node (ref "D10") (pin "1") (pinfunction "C_1") (pintype "passive"))
      (node (ref "D12") (pin "1") (pinfunction "C_1") (pintype "passive"))
      (node (ref "D14") (pin "1") (pinfunction "1_1") (pintype "passive"))
      (node (ref "SW3") (pin "1") (pinfunction "1_1") (pintype "passive"))
      (node (ref "SW3") (pin "2") (pinfunction "2_2") (pintype "passive"))
    )
    (net (code "285") (name "Net-(D12-A)") (class "Default")
      (node (ref "C133") (pin "1") (pinfunction "1_1") (pintype "passive"))
      (node (ref "D12") (pin "2") (pinfunction "A_2") (pintype "passive"))
      (node (ref "R64") (pin "1") (pinfunction "1_1") (pintype "passive"))
      (node (ref "R68") (pin "1") (pinfunction "1_1") (pintype "passive"))
    )
    (net (code "286") (name "Net-(J6-Pad2)") (class "Default")
      (node (ref "J6") (pin "2") (pinfunction "2_2") (pintype "passive"))
      (node (ref "R70") (pin "2") (pinfunction "2_2") (pintype "passive"))
    )
    (net (code "287") (name "Net-(Q1-S)") (class "Default")
      (node (ref "Q1") (pin "2") (pinfunction "S_2") (pintype "passive"))
      (node (ref "R32") (pin "1") (pinfunction "1_1") (pintype "passive"))
    )
    (net (code "288") (name "Net-(Q3-D)") (class "Default")
      (node (ref "Q3") (pin "3") (pinfunction "D_3") (pintype "passive"))
      (node (ref "R44") (pin "2") (pinfunction "2_2") (pintype "passive"))
    )
    (net (code "289") (name "Net-(Q4-D)") (class "Default")
      (node (ref "Q4") (pin "3") (pinfunction "D_3") (pintype "passive"))
      (node (ref "R43") (pin "2") (pinfunction "2_2") (pintype "passive"))
    )
    (net (code "290") (name "Net-(Q5-D)") (class "Default")
      (node (ref "Q5") (pin "3") (pinfunction "D_3") (pintype "passive"))
      (node (ref "R47") (pin "2") (pinfunction "2_2") (pintype "passive"))
    )
    (net (code "291") (name "Net-(Q6-D)") (class "Default")
      (node (ref "Q6") (pin "3") (pinfunction "D_3") (pintype "passive"))
      (node (ref "R59") (pin "2") (pinfunction "2_2") (pintype "passive"))
      (node (ref "U6") (pin "3") (pinfunction "D1_3") (pintype "input"))
    )
    (net (code "292") (name "Net-(Q6-G)") (class "Default")
      (node (ref "Q6") (pin "1") (pinfunction "G_1") (pintype "passive"))
      (node (ref "R58") (pin "2") (pinfunction "2_2") (pintype "passive"))
    )
    (net (code "293") (name "Net-(R79-Pad1)") (class "Default")
      (node (ref "R79") (pin "1") (pinfunction "1_1") (pintype "passive"))
      (node (ref "U7") (pin "1") (pinfunction "OUT_1") (pintype "output"))
    )
    (net (code "294") (name "Net-(U1A-CM_MCLK1)") (class "Default")
      (node (ref "L1") (pin "2") (pinfunction "2_2") (pintype "passive"))
      (node (ref "U1") (pin "A27") (pinfunction "CM_MCLK1_A27") (pintype "passive"))
    )
    (net (code "295") (name "Net-(U1A-GPIOD_0)") (class "Default")
      (node (ref "R4") (pin "2") (pinfunction "2_2") (pintype "passive"))
      (node (ref "U1") (pin "A15") (pinfunction "GPIOD_0_A15") (pintype "passive"))
    )
    (net (code "296") (name "Net-(U1A-GPIOD_1)") (class "Default")
      (node (ref "R1") (pin "1") (pinfunction "1_1") (pintype "passive"))
      (node (ref "U1") (pin "B15") (pinfunction "GPIOD_1_B15") (pintype "passive"))
    )
    (net (code "297") (name "Net-(U1A-SYS_OSCIN)") (class "Default")
      (node (ref "U1") (pin "A16") (pinfunction "SYS_OSCIN_A16") (pintype "passive"))
      (node (ref "X1") (pin "3") (pinfunction "X2_3") (pintype "passive"))
    )
    (net (code "298") (name "Net-(U1A-SYS_OSCOUT)") (class "Default")
      (node (ref "R6") (pin "2") (pinfunction "2_2") (pintype "passive"))
      (node (ref "U1") (pin "B16") (pinfunction "SYS_OSCOUT_B16") (pintype "passive"))
    )
    (net (code "299") (name "Net-(U2-OSCI)") (class "Default")
      (node (ref "C14") (pin "1") (pinfunction "1_1") (pintype "passive"))
      (node (ref "U2") (pin "1") (pinfunction "OSCI_1") (pintype "input"))
      (node (ref "Y1") (pin "2") (pinfunction "2_2") (pintype "passive"))
    )
    (net (code "300") (name "Net-(U2-OSCO)") (class "Default")
      (node (ref "C15") (pin "1") (pinfunction "1_1") (pintype "passive"))
      (node (ref "U2") (pin "2") (pinfunction "OSCO_2") (pintype "output"))
      (node (ref "Y1") (pin "1") (pinfunction "1_1") (pintype "passive"))
    )
    (net (code "301") (name "Net-(U5-VDDI)") (class "Default")
      (node (ref "C121") (pin "1") (pinfunction "1_1") (pintype "passive"))
      (node (ref "U5") (pin "C2") (pinfunction "VDDI_C2") (pintype "power_in"))
    )
    (net (code "302") (name "Net-(U6-ILIM)") (class "Default")
      (node (ref "R55") (pin "1") (pinfunction "1_1") (pintype "passive"))
      (node (ref "U6") (pin "4") (pinfunction "ILIM_4") (pintype "input"))
    )
    (net (code "303") (name "Net-(U7-CP2)") (class "Default")
      (node (ref "R73") (pin "2") (pinfunction "2_2") (pintype "passive"))
      (node (ref "R74") (pin "2") (pinfunction "2_2") (pintype "passive"))
      (node (ref "U7") (pin "3") (pinfunction "CP2_3") (pintype "input"))
    )
    (net (code "304") (name "Net-(U7-GND)") (class "Default")
      (node (ref "C134") (pin "2") (pinfunction "2_2") (pintype "passive"))
      (node (ref "C135") (pin "2") (pinfunction "2_2") (pintype "passive"))
      (node (ref "C136") (pin "2") (pinfunction "2_2") (pintype "passive"))
      (node (ref "U7") (pin "12") (pinfunction "GND_12") (pintype "power_in"))
    )
    (net (code "305") (name "Net-(U7-ILM)") (class "Default")
      (node (ref "R66") (pin "1") (pinfunction "1_1") (pintype "passive"))
      (node (ref "U7") (pin "10") (pinfunction "ILM_10") (pintype "output"))
    )
    (net (code "306") (name "Net-(U7-PR1)") (class "Default")
      (node (ref "R63") (pin "2") (pinfunction "2_2") (pintype "passive"))
      (node (ref "U7") (pin "6") (pinfunction "PR1_6") (pintype "input"))
    )
    (net (code "307") (name "Net-(U7-SS)") (class "Default")
      (node (ref "C131") (pin "1") (pinfunction "1_1") (pintype "passive"))
      (node (ref "U7") (pin "11") (pinfunction "SS_11") (pintype "output"))
    )
    (net (code "308") (name "Net-(U7-~{OV1})") (class "Default")
      (node (ref "R65") (pin "2") (pinfunction "2_2") (pintype "passive"))
      (node (ref "R67") (pin "2") (pinfunction "2_2") (pintype "passive"))
      (node (ref "U7") (pin "5") (pinfunction "~{OV1}_5") (pintype "input"))
    )
    (net (code "309") (name "Net-(U7-~{OV2})") (class "Default")
      (node (ref "R69") (pin "2") (pinfunction "2_2") (pintype "passive"))
      (node (ref "R71") (pin "2") (pinfunction "2_2") (pintype "passive"))
      (node (ref "U7") (pin "4") (pinfunction "~{OV2}_4") (pintype "input"))
    )
    (net (code "310") (name "Net-(U8-DIN)") (class "Default")
      (node (ref "U8") (pin "4") (pinfunction "DIN_4") (pintype "input"))
      (node (ref "U9") (pin "2") (pinfunction "DOUT_2") (pintype "output"))
    )
    (net (code "311") (name "Net-(U10-DIN)") (class "Default")
      (node (ref "U10") (pin "4") (pinfunction "DIN_4") (pintype "input"))
      (node (ref "U11") (pin "2") (pinfunction "DOUT_2") (pintype "output"))
    )
    (net (code "312") (name "Net-(U10-DOUT)") (class "Default")
      (node (ref "U10") (pin "2") (pinfunction "DOUT_2") (pintype "output"))
      (node (ref "U9") (pin "4") (pinfunction "DIN_4") (pintype "input"))
    )
    (net (code "313") (name "Net-(U12-OUTN)") (class "Default")
      (node (ref "J8") (pin "2") (pinfunction "2_2") (pintype "passive"))
      (node (ref "U12") (pin "10") (pinfunction "OUTN_10") (pintype "output"))
    )
    (net (code "314") (name "Net-(U12-OUTP)") (class "Default")
      (node (ref "J8") (pin "1") (pinfunction "1_1") (pintype "passive"))
      (node (ref "U12") (pin "9") (pinfunction "OUTP_9") (pintype "output"))
    )
    (net (code "315") (name "Net-(U13-DIN)") (class "Default")
      (node (ref "U13") (pin "4") (pinfunction "DIN_4") (pintype "input"))
      (node (ref "U14") (pin "2") (pinfunction "DOUT_2") (pintype "output"))
    )
    (net (code "316") (name "Net-(U13-DOUT)") (class "Default")
      (node (ref "U13") (pin "2") (pinfunction "DOUT_2") (pintype "output"))
      (node (ref "U18") (pin "4") (pinfunction "DIN_4") (pintype "input"))
    )
    (net (code "317") (name "Net-(U14-DIN)") (class "Default")
      (node (ref "U14") (pin "4") (pinfunction "DIN_4") (pintype "input"))
      (node (ref "U8") (pin "2") (pinfunction "DOUT_2") (pintype "output"))
    )
    (net (code "318") (name "Net-(U15-DATA)") (class "Default")
      (node (ref "SW4") (pin "1") (pinfunction "1_1") (pintype "passive"))
      (node (ref "U15") (pin "1") (pinfunction "DATA_1") (pintype "bidirectional"))
      (node (ref "U16") (pin "1") (pinfunction "DATA_1") (pintype "bidirectional"))
    )
    (net (code "319") (name "Net-(U17-DIN)") (class "Default")
      (node (ref "U17") (pin "4") (pinfunction "DIN_4") (pintype "input"))
      (node (ref "U18") (pin "2") (pinfunction "DOUT_2") (pintype "output"))
    )
    (net (code "320") (name "Net-(U17-DOUT)") (class "Default")
      (node (ref "U17") (pin "2") (pinfunction "DOUT_2") (pintype "output"))
      (node (ref "U20") (pin "4") (pinfunction "DIN_4") (pintype "input"))
    )
    (net (code "321") (name "Net-(U19-DIN)") (class "Default")
      (node (ref "U19") (pin "4") (pinfunction "DIN_4") (pintype "input"))
      (node (ref "U20") (pin "2") (pinfunction "DOUT_2") (pintype "output"))
    )
    (net (code "322") (name "Net-(U19-DOUT)") (class "Default")
      (node (ref "U19") (pin "2") (pinfunction "DOUT_2") (pintype "output"))
      (node (ref "U22") (pin "4") (pinfunction "DIN_4") (pintype "input"))
    )
    (net (code "323") (name "Net-(U21-DIN)") (class "Default")
      (node (ref "U21") (pin "4") (pinfunction "DIN_4") (pintype "input"))
      (node (ref "U22") (pin "2") (pinfunction "DOUT_2") (pintype "output"))
    )
    (net (code "324") (name "Net-(U21-DOUT)") (class "Default")
      (node (ref "U21") (pin "2") (pinfunction "DOUT_2") (pintype "output"))
      (node (ref "U24") (pin "4") (pinfunction "DIN_4") (pintype "input"))
    )
    (net (code "325") (name "Net-(U23-DIN)") (class "Default")
      (node (ref "U23") (pin "4") (pinfunction "DIN_4") (pintype "input"))
      (node (ref "U24") (pin "2") (pinfunction "DOUT_2") (pintype "output"))
    )
    (net (code "326") (name "Net-(U23-DOUT)") (class "Default")
      (node (ref "U23") (pin "2") (pinfunction "DOUT_2") (pintype "output"))
      (node (ref "U26") (pin "4") (pinfunction "DIN_4") (pintype "input"))
    )
    (net (code "327") (name "Net-(U25-DIN)") (class "Default")
      (node (ref "U25") (pin "4") (pinfunction "DIN_4") (pintype "input"))
      (node (ref "U26") (pin "2") (pinfunction "DOUT_2") (pintype "output"))
    )
    (net (code "328") (name "Net-(X1-X1)") (class "Default")
      (node (ref "C9") (pin "1") (pinfunction "1_1") (pintype "passive"))
      (node (ref "R6") (pin "1") (pinfunction "1_1") (pintype "passive"))
      (node (ref "X1") (pin "1") (pinfunction "X1_1") (pintype "passive"))
    )
    (net (code "329") (name "unconnected-(B2-NC_1-Pad12)") (class "Default")
      (node (ref "B2") (pin "12") (pinfunction "NC_1_12") (pintype "passive+no_connect"))
    )
    (net (code "330") (name "unconnected-(B2-NC_2-Pad24)") (class "Default")
      (node (ref "B2") (pin "24") (pinfunction "NC_2_24") (pintype "passive+no_connect"))
    )
    (net (code "331") (name "unconnected-(B2-NC_3-Pad37)") (class "Default")
      (node (ref "B2") (pin "37") (pinfunction "NC_3_37") (pintype "passive+no_connect"))
    )
    (net (code "332") (name "unconnected-(B2-NC_4-Pad48)") (class "Default")
      (node (ref "B2") (pin "48") (pinfunction "NC_4_48") (pintype "passive+no_connect"))
    )
    (net (code "333") (name "unconnected-(B2-WL_GPIO_10-Pad33)") (class "Default")
      (node (ref "B2") (pin "33") (pinfunction "WL_GPIO_10_33") (pintype "passive+no_connect"))
    )
    (net (code "334") (name "unconnected-(B2-WL_GPIO_11-Pad35)") (class "Default")
      (node (ref "B2") (pin "35") (pinfunction "WL_GPIO_11_35") (pintype "passive+no_connect"))
    )
    (net (code "335") (name "unconnected-(J6-Pad4)") (class "Default")
      (node (ref "J6") (pin "4") (pinfunction "4_4") (pintype "passive+no_connect"))
    )
    (net (code "336") (name "unconnected-(J7-SBU1-PadA8)") (class "Default")
      (node (ref "J7") (pin "A8") (pinfunction "SBU1_A8") (pintype "passive+no_connect"))
    )
    (net (code "337") (name "unconnected-(J7-SBU2-PadB8)") (class "Default")
      (node (ref "J7") (pin "B8") (pinfunction "SBU2_B8") (pintype "passive+no_connect"))
    )
    (net (code "338") (name "unconnected-(SW4-2_C-Pad7)") (class "Default")
      (node (ref "SW4") (pin "7") (pinfunction "2_C_7") (pintype "passive+no_connect"))
    )
    (net (code "339") (name "unconnected-(SW4-Pad4)") (class "Default")
      (node (ref "SW4") (pin "4") (pinfunction "4_4") (pintype "passive+no_connect"))
    )
    (net (code "340") (name "unconnected-(SW4-Pad5)") (class "Default")
      (node (ref "SW4") (pin "5") (pinfunction "5_5") (pintype "passive+no_connect"))
    )
    (net (code "341") (name "unconnected-(SW4-Pad6)") (class "Default")
      (node (ref "SW4") (pin "6") (pinfunction "6_6") (pintype "passive+no_connect"))
    )
    (net (code "342") (name "unconnected-(SW4-Pad8)") (class "Default")
      (node (ref "SW4") (pin "8") (pinfunction "8_8") (pintype "passive+no_connect"))
    )
    (net (code "343") (name "unconnected-(U1A-DDR0_AC_8-PadB1)") (class "Default")
      (node (ref "U1") (pin "B1") (pinfunction "DDR0_AC_8_B1") (pintype "passive+no_connect"))
    )
    (net (code "344") (name "unconnected-(U1A-DDR0_AC_9-PadB2)") (class "Default")
      (node (ref "U1") (pin "B2") (pinfunction "DDR0_AC_9_B2") (pintype "passive+no_connect"))
    )
    (net (code "345") (name "unconnected-(U1A-DDR0_DQ0-PadA2)") (class "Default")
      (node (ref "U1") (pin "A2") (pinfunction "DDR0_DQ0_A2") (pintype "passive+no_connect"))
    )
    (net (code "346") (name "unconnected-(U1A-DDR0_DQ1-PadB4)") (class "Default")
      (node (ref "U1") (pin "B4") (pinfunction "DDR0_DQ1_B4") (pintype "passive+no_connect"))
    )
    (net (code "347") (name "unconnected-(U1A-DDR0_DQ5-PadA3)") (class "Default")
      (node (ref "U1") (pin "A3") (pinfunction "DDR0_DQ5_A3") (pintype "passive+no_connect"))
    )
    (net (code "348") (name "unconnected-(U1A-DDR0_DQ7-PadA6)") (class "Default")
      (node (ref "U1") (pin "A6") (pinfunction "DDR0_DQ7_A6") (pintype "passive+no_connect"))
    )
    (net (code "349") (name "unconnected-(U1A-DDR0_DQ8-PadB12)") (class "Default")
      (node (ref "U1") (pin "B12") (pinfunction "DDR0_DQ8_B12") (pintype "passive+no_connect"))
    )
    (net (code "350") (name "unconnected-(U1A-DDR0_DQ11-PadA10)") (class "Default")
      (node (ref "U1") (pin "A10") (pinfunction "DDR0_DQ11_A10") (pintype "passive+no_connect"))
    )
    (net (code "351") (name "unconnected-(U1A-DDR0_DQ14-PadB10)") (class "Default")
      (node (ref "U1") (pin "B10") (pinfunction "DDR0_DQ14_B10") (pintype "passive+no_connect"))
    )
    (net (code "352") (name "unconnected-(U1A-DDR0_DQ15-PadA12)") (class "Default")
      (node (ref "U1") (pin "A12") (pinfunction "DDR0_DQ15_A12") (pintype "passive+no_connect"))
    )
    (net (code "353") (name "unconnected-(U1A-DDR0_DQM0-PadB5)") (class "Default")
      (node (ref "U1") (pin "B5") (pinfunction "DDR0_DQM0_B5") (pintype "passive+no_connect"))
    )
    (net (code "354") (name "unconnected-(U1A-DDR0_DQSN0-PadB7)") (class "Default")
      (node (ref "U1") (pin "B7") (pinfunction "DDR0_DQSN0_B7") (pintype "passive+no_connect"))
    )
    (net (code "355") (name "unconnected-(U1A-DDR0_DQSN1-PadB9)") (class "Default")
      (node (ref "U1") (pin "B9") (pinfunction "DDR0_DQSN1_B9") (pintype "passive+no_connect"))
    )
    (net (code "356") (name "unconnected-(U1A-DDR0_DQSP0-PadA7)") (class "Default")
      (node (ref "U1") (pin "A7") (pinfunction "DDR0_DQSP0_A7") (pintype "passive+no_connect"))
    )
    (net (code "357") (name "unconnected-(U1A-DDR0_DQSP1-PadA9)") (class "Default")
      (node (ref "U1") (pin "A9") (pinfunction "DDR0_DQSP1_A9") (pintype "passive+no_connect"))
    )
    (net (code "358") (name "unconnected-(U1A-USB20_TXRTUNE-PadA22)") (class "Default")
      (node (ref "U1") (pin "A22") (pinfunction "USB20_TXRTUNE_A22") (pintype "passive+no_connect"))
    )
    (net (code "359") (name "unconnected-(U1A-USB30_PCIE_REXT-PadB22)") (class "Default")
      (node (ref "U1") (pin "B22") (pinfunction "USB30_PCIE_REXT_B22") (pintype "passive+no_connect"))
    )
    (net (code "360") (name "unconnected-(U1A-USB30_RXN-PadB25)") (class "Default")
      (node (ref "U1") (pin "B25") (pinfunction "USB30_RXN_B25") (pintype "passive+no_connect"))
    )
    (net (code "361") (name "unconnected-(U1A-USB30_RXP-PadA25)") (class "Default")
      (node (ref "U1") (pin "A25") (pinfunction "USB30_RXP_A25") (pintype "passive+no_connect"))
    )
    (net (code "362") (name "unconnected-(U1A-USB30_TXN-PadA24)") (class "Default")
      (node (ref "U1") (pin "A24") (pinfunction "USB30_TXN_A24") (pintype "passive+no_connect"))
    )
    (net (code "363") (name "unconnected-(U1A-USB30_TXP-PadB24)") (class "Default")
      (node (ref "U1") (pin "B24") (pinfunction "USB30_TXP_B24") (pintype "passive+no_connect"))
    )
    (net (code "364") (name "unconnected-(U1B-CM_MCLK2-PadB27)") (class "Default")
      (node (ref "U1") (pin "B27") (pinfunction "CM_MCLK2_B27") (pintype "passive+no_connect"))
    )
    (net (code "365") (name "unconnected-(U1B-CSI_D_CLKN-PadC31)") (class "Default")
      (node (ref "U1") (pin "C31") (pinfunction "CSI_D_CLKN_C31") (pintype "passive+no_connect"))
    )
    (net (code "366") (name "unconnected-(U1B-CSI_D_CLKP-PadC30)") (class "Default")
      (node (ref "U1") (pin "C30") (pinfunction "CSI_D_CLKP_C30") (pintype "passive+no_connect"))
    )
    (net (code "367") (name "unconnected-(U1B-DDR0_AC_7-PadC3)") (class "Default")
      (node (ref "U1") (pin "C3") (pinfunction "DDR0_AC_7_C3") (pintype "passive+no_connect"))
    )
    (net (code "368") (name "unconnected-(U1B-DDR0_AC_10-PadD3)") (class "Default")
      (node (ref "U1") (pin "D3") (pinfunction "DDR0_AC_10_D3") (pintype "passive+no_connect"))
    )
    (net (code "369") (name "unconnected-(U1B-DDR0_AC_12-PadD1)") (class "Default")
      (node (ref "U1") (pin "D1") (pinfunction "DDR0_AC_12_D1") (pintype "passive+no_connect"))
    )
    (net (code "370") (name "unconnected-(U1B-DDR0_AC_13-PadD2)") (class "Default")
      (node (ref "U1") (pin "D2") (pinfunction "DDR0_AC_13_D2") (pintype "passive+no_connect"))
    )
    (net (code "371") (name "unconnected-(U1B-DDR0_AC_14-PadC4)") (class "Default")
      (node (ref "U1") (pin "C4") (pinfunction "DDR0_AC_14_C4") (pintype "passive+no_connect"))
    )
    (net (code "372") (name "unconnected-(U1B-DDR0_DQ2-PadD6)") (class "Default")
      (node (ref "U1") (pin "D6") (pinfunction "DDR0_DQ2_D6") (pintype "passive+no_connect"))
    )
    (net (code "373") (name "unconnected-(U1B-DDR0_DQ3-PadC6)") (class "Default")
      (node (ref "U1") (pin "C6") (pinfunction "DDR0_DQ3_C6") (pintype "passive+no_connect"))
    )
    (net (code "374") (name "unconnected-(U1B-DDR0_DQ4-PadD7)") (class "Default")
      (node (ref "U1") (pin "D7") (pinfunction "DDR0_DQ4_D7") (pintype "passive+no_connect"))
    )
    (net (code "375") (name "unconnected-(U1B-DDR0_DQ6-PadC7)") (class "Default")
      (node (ref "U1") (pin "C7") (pinfunction "DDR0_DQ6_C7") (pintype "passive+no_connect"))
    )
    (net (code "376") (name "unconnected-(U1B-DDR0_DQ9-PadD8)") (class "Default")
      (node (ref "U1") (pin "D8") (pinfunction "DDR0_DQ9_D8") (pintype "passive+no_connect"))
    )
    (net (code "377") (name "unconnected-(U1B-DDR0_DQ12-PadD10)") (class "Default")
      (node (ref "U1") (pin "D10") (pinfunction "DDR0_DQ12_D10") (pintype "passive+no_connect"))
    )
    (net (code "378") (name "unconnected-(U1B-DDR0_DQ13-PadC10)") (class "Default")
      (node (ref "U1") (pin "C10") (pinfunction "DDR0_DQ13_C10") (pintype "passive+no_connect"))
    )
    (net (code "379") (name "unconnected-(U1B-DDR0_DQM1-PadC8)") (class "Default")
      (node (ref "U1") (pin "C8") (pinfunction "DDR0_DQM1_C8") (pintype "passive+no_connect"))
    )
    (net (code "380") (name "unconnected-(U1B-DDR0_RST-PadD4)") (class "Default")
      (node (ref "U1") (pin "D4") (pinfunction "DDR0_RST_D4") (pintype "passive+no_connect"))
    )
    (net (code "381") (name "unconnected-(U1B-GPIOE_2-PadD15)") (class "Default")
      (node (ref "U1") (pin "D15") (pinfunction "GPIOE_2_D15") (pintype "passive+no_connect"))
    )
    (net (code "382") (name "unconnected-(U1B-HCSL_REXT-PadC22)") (class "Default")
      (node (ref "U1") (pin "C22") (pinfunction "HCSL_REXT_C22") (pintype "passive+no_connect"))
    )
    (net (code "383") (name "unconnected-(U1B-PCIE_CLK_N-PadC23)") (class "Default")
      (node (ref "U1") (pin "C23") (pinfunction "PCIE_CLK_N_C23") (pintype "passive+no_connect"))
    )
    (net (code "384") (name "unconnected-(U1B-PCIE_RXN-PadC24)") (class "Default")
      (node (ref "U1") (pin "C24") (pinfunction "PCIE_RXN_C24") (pintype "passive+no_connect"))
    )
    (net (code "385") (name "unconnected-(U1B-USB_A_OTG_DM-PadC27)") (class "Default")
      (node (ref "U1") (pin "C27") (pinfunction "USB_A_OTG_DM_C27") (pintype "passive+no_connect"))
    )
    (net (code "386") (name "unconnected-(U1B-USB_A_OTG_DP-PadC26)") (class "Default")
      (node (ref "U1") (pin "C26") (pinfunction "USB_A_OTG_DP_C26") (pintype "passive+no_connect"))
    )
    (net (code "387") (name "unconnected-(U1C-CSI_C_D3N-PadD31)") (class "Default")
      (node (ref "U1") (pin "D31") (pinfunction "CSI_C_D3N_D31") (pintype "passive+no_connect"))
    )
    (net (code "388") (name "unconnected-(U1C-CSI_C_D3P-PadD30)") (class "Default")
      (node (ref "U1") (pin "D30") (pinfunction "CSI_C_D3P_D30") (pintype "passive+no_connect"))
    )
    (net (code "389") (name "unconnected-(U1C-DDR0_AC_0-PadE2)") (class "Default")
      (node (ref "U1") (pin "E2") (pinfunction "DDR0_AC_0_E2") (pintype "passive+no_connect"))
    )
    (net (code "390") (name "unconnected-(U1C-DDR0_AC_1-PadF2)") (class "Default")
      (node (ref "U1") (pin "F2") (pinfunction "DDR0_AC_1_F2") (pintype "passive+no_connect"))
    )
    (net (code "391") (name "unconnected-(U1C-DDR0_AC_5-PadF3)") (class "Default")
      (node (ref "U1") (pin "F3") (pinfunction "DDR0_AC_5_F3") (pintype "passive+no_connect"))
    )
    (net (code "392") (name "unconnected-(U1C-DDR0_AC_11-PadF4)") (class "Default")
      (node (ref "U1") (pin "F4") (pinfunction "DDR0_AC_11_F4") (pintype "passive+no_connect"))
    )
    (net (code "393") (name "unconnected-(U1C-DDR0_AC_15-PadE3)") (class "Default")
      (node (ref "U1") (pin "E3") (pinfunction "DDR0_AC_15_E3") (pintype "passive+no_connect"))
    )
    (net (code "394") (name "unconnected-(U1C-DDR0_AC_34-PadF5)") (class "Default")
      (node (ref "U1") (pin "F5") (pinfunction "DDR0_AC_34_F5") (pintype "passive+no_connect"))
    )
    (net (code "395") (name "unconnected-(U1C-DDR0_AC_35-PadE5)") (class "Default")
      (node (ref "U1") (pin "E5") (pinfunction "DDR0_AC_35_E5") (pintype "passive+no_connect"))
    )
    (net (code "396") (name "unconnected-(U1C-DDR0_DQ10-PadE8)") (class "Default")
      (node (ref "U1") (pin "E8") (pinfunction "DDR0_DQ10_E8") (pintype "passive+no_connect"))
    )
    (net (code "397") (name "unconnected-(U1C-DDR0_PZQ-PadF8)") (class "Default")
      (node (ref "U1") (pin "F8") (pinfunction "DDR0_PZQ_F8") (pintype "passive+no_connect"))
    )
    (net (code "398") (name "unconnected-(U1C-PCIE_CLK_P-PadD23)") (class "Default")
      (node (ref "U1") (pin "D23") (pinfunction "PCIE_CLK_P_D23") (pintype "passive+no_connect"))
    )
    (net (code "399") (name "unconnected-(U1C-PCIE_RXP-PadD24)") (class "Default")
      (node (ref "U1") (pin "D24") (pinfunction "PCIE_RXP_D24") (pintype "passive+no_connect"))
    )
    (net (code "400") (name "unconnected-(U1C-PCIE_TXN-PadE24)") (class "Default")
      (node (ref "U1") (pin "E24") (pinfunction "PCIE_TXN_E24") (pintype "passive+no_connect"))
    )
    (net (code "401") (name "unconnected-(U1C-USB_B_OTG_ID-PadD26)") (class "Default")
      (node (ref "U1") (pin "D26") (pinfunction "USB_B_OTG_ID_D26") (pintype "passive+no_connect"))
    )
    (net (code "402") (name "unconnected-(U1D-CSI_C_CLKN-PadF31)") (class "Default")
      (node (ref "U1") (pin "F31") (pinfunction "CSI_C_CLKN_F31") (pintype "passive+no_connect"))
    )
    (net (code "403") (name "unconnected-(U1D-CSI_C_CLKP-PadF30)") (class "Default")
      (node (ref "U1") (pin "F30") (pinfunction "CSI_C_CLKP_F30") (pintype "passive+no_connect"))
    )
    (net (code "404") (name "unconnected-(U1D-CSI_C_D0N-PadG28)") (class "Default")
      (node (ref "U1") (pin "G28") (pinfunction "CSI_C_D0N_G28") (pintype "passive+no_connect"))
    )
    (net (code "405") (name "unconnected-(U1D-CSI_C_D0P-PadG29)") (class "Default")
      (node (ref "U1") (pin "G29") (pinfunction "CSI_C_D0P_G29") (pintype "passive+no_connect"))
    )
    (net (code "406") (name "unconnected-(U1D-CSI_C_D1N-PadG31)") (class "Default")
      (node (ref "U1") (pin "G31") (pinfunction "CSI_C_D1N_G31") (pintype "passive+no_connect"))
    )
    (net (code "407") (name "unconnected-(U1D-CSI_C_D1P-PadG30)") (class "Default")
      (node (ref "U1") (pin "G30") (pinfunction "CSI_C_D1P_G30") (pintype "passive+no_connect"))
    )
    (net (code "408") (name "unconnected-(U1D-CSI_C_D2N-PadF29)") (class "Default")
      (node (ref "U1") (pin "F29") (pinfunction "CSI_C_D2N_F29") (pintype "passive+no_connect"))
    )
    (net (code "409") (name "unconnected-(U1D-CSI_C_D2P-PadF28)") (class "Default")
      (node (ref "U1") (pin "F28") (pinfunction "CSI_C_D2P_F28") (pintype "passive+no_connect"))
    )
    (net (code "410") (name "unconnected-(U1D-DDR0_AC_2-PadG1)") (class "Default")
      (node (ref "U1") (pin "G1") (pinfunction "DDR0_AC_2_G1") (pintype "passive+no_connect"))
    )
    (net (code "411") (name "unconnected-(U1D-DDR0_AC_3-PadH3)") (class "Default")
      (node (ref "U1") (pin "H3") (pinfunction "DDR0_AC_3_H3") (pintype "passive+no_connect"))
    )
    (net (code "412") (name "unconnected-(U1D-DDR0_AC_4-PadG3)") (class "Default")
      (node (ref "U1") (pin "G3") (pinfunction "DDR0_AC_4_G3") (pintype "passive+no_connect"))
    )
    (net (code "413") (name "unconnected-(U1D-DDR0_AC_24-PadG4)") (class "Default")
      (node (ref "U1") (pin "G4") (pinfunction "DDR0_AC_24_G4") (pintype "passive+no_connect"))
    )
    (net (code "414") (name "unconnected-(U1D-DDR0_AC_25-PadG5)") (class "Default")
      (node (ref "U1") (pin "G5") (pinfunction "DDR0_AC_25_G5") (pintype "passive+no_connect"))
    )
    (net (code "415") (name "unconnected-(U1D-DDR0_AC_31-PadH2)") (class "Default")
      (node (ref "U1") (pin "H2") (pinfunction "DDR0_AC_31_H2") (pintype "passive+no_connect"))
    )
    (net (code "416") (name "unconnected-(U1D-DDR0_PVREF-PadG6)") (class "Default")
      (node (ref "U1") (pin "G6") (pinfunction "DDR0_PVREF_G6") (pintype "passive+no_connect"))
    )
    (net (code "417") (name "unconnected-(U1D-PCIE_TXP-PadF24)") (class "Default")
      (node (ref "U1") (pin "F24") (pinfunction "PCIE_TXP_F24") (pintype "passive+no_connect"))
    )
    (net (code "418") (name "unconnected-(U1D-USB_A_OTG_VBUS-PadF21)") (class "Default")
      (node (ref "U1") (pin "F21") (pinfunction "USB_A_OTG_VBUS_F21") (pintype "passive+no_connect"))
    )
    (net (code "419") (name "unconnected-(U1E-AVDD0V8_USB_PCIE-PadH22)") (class "Default")
      (node (ref "U1") (pin "H22") (pinfunction "AVDD0V8_USB_PCIE_H22") (pintype "passive+no_connect"))
    )
    (net (code "420") (name "unconnected-(U1E-AVDD18_USB_PCIE-PadJ25)") (class "Default")
      (node (ref "U1") (pin "J25") (pinfunction "AVDD18_USB_PCIE_J25") (pintype "passive+no_connect"))
    )
    (net (code "421") (name "unconnected-(U1E-AVDD33_USB-PadH24)") (class "Default")
      (node (ref "U1") (pin "H24") (pinfunction "AVDD33_USB_H24") (pintype "passive+no_connect"))
    )
    (net (code "422") (name "unconnected-(U1E-DDR0_AC_6-PadJ4)") (class "Default")
      (node (ref "U1") (pin "J4") (pinfunction "DDR0_AC_6_J4") (pintype "passive+no_connect"))
    )
    (net (code "423") (name "unconnected-(U1E-DDR0_AC_26-PadJ5)") (class "Default")
      (node (ref "U1") (pin "J5") (pinfunction "DDR0_AC_26_J5") (pintype "passive+no_connect"))
    )
    (net (code "424") (name "unconnected-(U1E-DDR0_AC_29-PadJ2)") (class "Default")
      (node (ref "U1") (pin "J2") (pinfunction "DDR0_AC_29_J2") (pintype "passive+no_connect"))
    )
    (net (code "425") (name "unconnected-(U1E-DDR0_AC_33-PadJ3)") (class "Default")
      (node (ref "U1") (pin "J3") (pinfunction "DDR0_AC_33_J3") (pintype "passive+no_connect"))
    )
    (net (code "426") (name "unconnected-(U1E-DDR0_AC_36-PadJ6)") (class "Default")
      (node (ref "U1") (pin "J6") (pinfunction "DDR0_AC_36_J6") (pintype "passive+no_connect"))
    )
    (net (code "427") (name "unconnected-(U1E-GPIOM_0-PadJ31)") (class "Default")
      (node (ref "U1") (pin "J31") (pinfunction "GPIOM_0_J31") (pintype "passive+no_connect"))
    )
    (net (code "428") (name "unconnected-(U1E-GPIOM_1-PadH31)") (class "Default")
      (node (ref "U1") (pin "H31") (pinfunction "GPIOM_1_H31") (pintype "passive+no_connect"))
    )
    (net (code "429") (name "unconnected-(U1E-GPIOM_4-PadH33)") (class "Default")
      (node (ref "U1") (pin "H33") (pinfunction "GPIOM_4_H33") (pintype "passive+no_connect"))
    )
    (net (code "430") (name "unconnected-(U1E-GPIOT_15-PadJ28)") (class "Default")
      (node (ref "U1") (pin "J28") (pinfunction "GPIOT_15_J28") (pintype "passive+no_connect"))
    )
    (net (code "431") (name "unconnected-(U1E-USB_A_OTG_ID-PadH21)") (class "Default")
      (node (ref "U1") (pin "H21") (pinfunction "USB_A_OTG_ID_H21") (pintype "passive+no_connect"))
    )
    (net (code "432") (name "unconnected-(U1F-AVSS_PLL-PadL17)") (class "Default")
      (node (ref "U1") (pin "L17") (pinfunction "AVSS_PLL_L17") (pintype "passive+no_connect"))
    )
    (net (code "433") (name "unconnected-(U1F-DDR0_AC_20-PadK4)") (class "Default")
      (node (ref "U1") (pin "K4") (pinfunction "DDR0_AC_20_K4") (pintype "passive+no_connect"))
    )
    (net (code "434") (name "unconnected-(U1F-DDR0_AC_21-PadK3)") (class "Default")
      (node (ref "U1") (pin "K3") (pinfunction "DDR0_AC_21_K3") (pintype "passive+no_connect"))
    )
    (net (code "435") (name "unconnected-(U1F-DDR0_AC_28-PadK5)") (class "Default")
      (node (ref "U1") (pin "K5") (pinfunction "DDR0_AC_28_K5") (pintype "passive+no_connect"))
    )
    (net (code "436") (name "unconnected-(U1F-DDR0_AC_30-PadK1)") (class "Default")
      (node (ref "U1") (pin "K1") (pinfunction "DDR0_AC_30_K1") (pintype "passive+no_connect"))
    )
    (net (code "437") (name "unconnected-(U1F-DDR0_AC_32-PadL3)") (class "Default")
      (node (ref "U1") (pin "L3") (pinfunction "DDR0_AC_32_L3") (pintype "passive+no_connect"))
    )
    (net (code "438") (name "unconnected-(U1F-DDR0_AC_38-PadK6)") (class "Default")
      (node (ref "U1") (pin "K6") (pinfunction "DDR0_AC_38_K6") (pintype "passive+no_connect"))
    )
    (net (code "439") (name "unconnected-(U1F-DDR0_DQM2-PadL2)") (class "Default")
      (node (ref "U1") (pin "L2") (pinfunction "DDR0_DQM2_L2") (pintype "passive+no_connect"))
    )
    (net (code "440") (name "unconnected-(U1F-GPIOT_5-PadK30)") (class "Default")
      (node (ref "U1") (pin "K30") (pinfunction "GPIOT_5_K30") (pintype "passive+no_connect"))
    )
    (net (code "441") (name "unconnected-(U1F-GPIOT_7-PadK33)") (class "Default")
      (node (ref "U1") (pin "K33") (pinfunction "GPIOT_7_K33") (pintype "passive+no_connect"))
    )
    (net (code "442") (name "unconnected-(U1F-GPIOT_8-PadK31)") (class "Default")
      (node (ref "U1") (pin "K31") (pinfunction "GPIOT_8_K31") (pintype "passive+no_connect"))
    )
    (net (code "443") (name "unconnected-(U1F-GPIOT_11-PadK32)") (class "Default")
      (node (ref "U1") (pin "K32") (pinfunction "GPIOT_11_K32") (pintype "passive+no_connect"))
    )
    (net (code "444") (name "unconnected-(U1F-GPIOT_16-PadK28)") (class "Default")
      (node (ref "U1") (pin "K28") (pinfunction "GPIOT_16_K28") (pintype "passive+no_connect"))
    )
    (net (code "445") (name "unconnected-(U1F-GPIOT_17-PadK29)") (class "Default")
      (node (ref "U1") (pin "K29") (pinfunction "GPIOT_17_K29") (pintype "passive+no_connect"))
    )
    (net (code "446") (name "unconnected-(U1F-USB_B_OTG_VBUS-PadK24)") (class "Default")
      (node (ref "U1") (pin "K24") (pinfunction "USB_B_OTG_VBUS_K24") (pintype "passive+no_connect"))
    )
    (net (code "447") (name "unconnected-(U1G-AVDD_DDR0PLL-PadN8)") (class "Default")
      (node (ref "U1") (pin "N8") (pinfunction "AVDD_DDR0PLL_N8") (pintype "passive+no_connect"))
    )
    (net (code "448") (name "unconnected-(U1G-DDR0_AC_22-PadM4)") (class "Default")
      (node (ref "U1") (pin "M4") (pinfunction "DDR0_AC_22_M4") (pintype "passive+no_connect"))
    )
    (net (code "449") (name "unconnected-(U1G-DDR0_AC_23-PadM5)") (class "Default")
      (node (ref "U1") (pin "M5") (pinfunction "DDR0_AC_23_M5") (pintype "passive+no_connect"))
    )
    (net (code "450") (name "unconnected-(U1G-DDR0_DQ16-PadN3)") (class "Default")
      (node (ref "U1") (pin "N3") (pinfunction "DDR0_DQ16_N3") (pintype "passive+no_connect"))
    )
    (net (code "451") (name "unconnected-(U1G-DDR0_DQ17-PadM3)") (class "Default")
      (node (ref "U1") (pin "M3") (pinfunction "DDR0_DQ17_M3") (pintype "passive+no_connect"))
    )
    (net (code "452") (name "unconnected-(U1G-DDR0_DQ19-PadN4)") (class "Default")
      (node (ref "U1") (pin "N4") (pinfunction "DDR0_DQ19_N4") (pintype "passive+no_connect"))
    )
    (net (code "453") (name "unconnected-(U1G-DDR0_DQ20-PadM2)") (class "Default")
      (node (ref "U1") (pin "M2") (pinfunction "DDR0_DQ20_M2") (pintype "passive+no_connect"))
    )
    (net (code "454") (name "unconnected-(U1G-DDR0_DQ21-PadN1)") (class "Default")
      (node (ref "U1") (pin "N1") (pinfunction "DDR0_DQ21_N1") (pintype "passive+no_connect"))
    )
    (net (code "455") (name "unconnected-(U1G-DDR0_DQ23-PadN5)") (class "Default")
      (node (ref "U1") (pin "N5") (pinfunction "DDR0_DQ23_N5") (pintype "passive+no_connect"))
    )
    (net (code "456") (name "unconnected-(U1G-GPIOT_6-PadL33)") (class "Default")
      (node (ref "U1") (pin "L33") (pinfunction "GPIOT_6_L33") (pintype "passive+no_connect"))
    )
    (net (code "457") (name "unconnected-(U1G-GPIOT_9-PadM32)") (class "Default")
      (node (ref "U1") (pin "M32") (pinfunction "GPIOT_9_M32") (pintype "passive+no_connect"))
    )
    (net (code "458") (name "unconnected-(U1G-GPIOT_13-PadM28)") (class "Default")
      (node (ref "U1") (pin "M28") (pinfunction "GPIOT_13_M28") (pintype "passive+no_connect"))
    )
    (net (code "459") (name "unconnected-(U1G-GPIOT_14-PadM29)") (class "Default")
      (node (ref "U1") (pin "M29") (pinfunction "GPIOT_14_M29") (pintype "passive+no_connect"))
    )
    (net (code "460") (name "unconnected-(U1G-GPIOT_19-PadL32)") (class "Default")
      (node (ref "U1") (pin "L32") (pinfunction "GPIOT_19_L32") (pintype "passive+no_connect"))
    )
    (net (code "461") (name "unconnected-(U1G-GPIOT_20-PadM30)") (class "Default")
      (node (ref "U1") (pin "M30") (pinfunction "GPIOT_20_M30") (pintype "passive+no_connect"))
    )
    (net (code "462") (name "unconnected-(U1G-GPIOT_21-PadM31)") (class "Default")
      (node (ref "U1") (pin "M31") (pinfunction "GPIOT_21_M31") (pintype "passive+no_connect"))
    )
    (net (code "463") (name "unconnected-(U1H-DDR0_AC_37-PadR6)") (class "Default")
      (node (ref "U1") (pin "R6") (pinfunction "DDR0_AC_37_R6") (pintype "passive+no_connect"))
    )
    (net (code "464") (name "unconnected-(U1H-DDR0_DQ18-PadP3)") (class "Default")
      (node (ref "U1") (pin "P3") (pinfunction "DDR0_DQ18_P3") (pintype "passive+no_connect"))
    )
    (net (code "465") (name "unconnected-(U1H-DDR0_DQ22-PadP2)") (class "Default")
      (node (ref "U1") (pin "P2") (pinfunction "DDR0_DQ22_P2") (pintype "passive+no_connect"))
    )
    (net (code "466") (name "unconnected-(U1H-DDR0_DQ24-PadR2)") (class "Default")
      (node (ref "U1") (pin "R2") (pinfunction "DDR0_DQ24_R2") (pintype "passive+no_connect"))
    )
    (net (code "467") (name "unconnected-(U1H-DDR0_DQSN2-PadR4)") (class "Default")
      (node (ref "U1") (pin "R4") (pinfunction "DDR0_DQSN2_R4") (pintype "passive+no_connect"))
    )
    (net (code "468") (name "unconnected-(U1H-DDR0_DQSP2-PadR3)") (class "Default")
      (node (ref "U1") (pin "R3") (pinfunction "DDR0_DQSP2_R3") (pintype "passive+no_connect"))
    )
    (net (code "469") (name "unconnected-(U1H-GPIOT_10-PadN32)") (class "Default")
      (node (ref "U1") (pin "N32") (pinfunction "GPIOT_10_N32") (pintype "passive+no_connect"))
    )
    (net (code "470") (name "unconnected-(U1H-GPIOT_22-PadN31)") (class "Default")
      (node (ref "U1") (pin "N31") (pinfunction "GPIOT_22_N31") (pintype "passive+no_connect"))
    )
    (net (code "471") (name "unconnected-(U1H-GPIOT_23-PadN30)") (class "Default")
      (node (ref "U1") (pin "N30") (pinfunction "GPIOT_23_N30") (pintype "passive+no_connect"))
    )
    (net (code "472") (name "unconnected-(U1H-VDDCPU_A-PadN15)") (class "Default")
      (node (ref "U1") (pin "N15") (pinfunction "VDDCPU_A_N15") (pintype "passive"))
    )
    (net (code "473") (name "unconnected-(U1I-DDR0_DQ27-PadT1)") (class "Default")
      (node (ref "U1") (pin "T1") (pinfunction "DDR0_DQ27_T1") (pintype "passive+no_connect"))
    )
    (net (code "474") (name "unconnected-(U1I-DDR0_DQSN3-PadT4)") (class "Default")
      (node (ref "U1") (pin "T4") (pinfunction "DDR0_DQSN3_T4") (pintype "passive+no_connect"))
    )
    (net (code "475") (name "unconnected-(U1I-DDR0_DQSP3-PadT3)") (class "Default")
      (node (ref "U1") (pin "T3") (pinfunction "DDR0_DQSP3_T3") (pintype "passive+no_connect"))
    )
    (net (code "476") (name "unconnected-(U1I-GPIOH_1-PadR29)") (class "Default")
      (node (ref "U1") (pin "R29") (pinfunction "GPIOH_1_R29") (pintype "passive+no_connect"))
    )
    (net (code "477") (name "unconnected-(U1I-GPIOH_2-PadR30)") (class "Default")
      (node (ref "U1") (pin "R30") (pinfunction "GPIOH_2_R30") (pintype "passive+no_connect"))
    )
    (net (code "478") (name "unconnected-(U1I-GPIOH_3-PadR31)") (class "Default")
      (node (ref "U1") (pin "R31") (pinfunction "GPIOH_3_R31") (pintype "passive+no_connect"))
    )
    (net (code "479") (name "unconnected-(U1I-GPIOH_5-PadT29)") (class "Default")
      (node (ref "U1") (pin "T29") (pinfunction "GPIOH_5_T29") (pintype "passive+no_connect"))
    )
    (net (code "480") (name "unconnected-(U1J-DDR0_DQ25-PadU2)") (class "Default")
      (node (ref "U1") (pin "U2") (pinfunction "DDR0_DQ25_U2") (pintype "passive+no_connect"))
    )
    (net (code "481") (name "unconnected-(U1J-DDR0_DQ26-PadU3)") (class "Default")
      (node (ref "U1") (pin "U3") (pinfunction "DDR0_DQ26_U3") (pintype "passive+no_connect"))
    )
    (net (code "482") (name "unconnected-(U1J-DDR0_DQ28-PadV5)") (class "Default")
      (node (ref "U1") (pin "V5") (pinfunction "DDR0_DQ28_V5") (pintype "passive+no_connect"))
    )
    (net (code "483") (name "unconnected-(U1J-DDR0_DQ29-PadV4)") (class "Default")
      (node (ref "U1") (pin "V4") (pinfunction "DDR0_DQ29_V4") (pintype "passive+no_connect"))
    )
    (net (code "484") (name "unconnected-(U1J-DDR0_DQ30-PadV3)") (class "Default")
      (node (ref "U1") (pin "V3") (pinfunction "DDR0_DQ30_V3") (pintype "passive+no_connect"))
    )
    (net (code "485") (name "unconnected-(U1J-DDR0_DQM3-PadV2)") (class "Default")
      (node (ref "U1") (pin "V2") (pinfunction "DDR0_DQM3_V2") (pintype "passive+no_connect"))
    )
    (net (code "486") (name "unconnected-(U1J-GPIOC_2-PadT32)") (class "Default")
      (node (ref "U1") (pin "T32") (pinfunction "GPIOC_2_T32") (pintype "passive+no_connect"))
    )
    (net (code "487") (name "unconnected-(U1J-GPIOC_3-PadT33)") (class "Default")
      (node (ref "U1") (pin "T33") (pinfunction "GPIOC_3_T33") (pintype "passive+no_connect"))
    )
    (net (code "488") (name "unconnected-(U1J-GPIOC_4-PadU33)") (class "Default")
      (node (ref "U1") (pin "U33") (pinfunction "GPIOC_4_U33") (pintype "passive+no_connect"))
    )
    (net (code "489") (name "unconnected-(U1J-GPIOC_5-PadU31)") (class "Default")
      (node (ref "U1") (pin "U31") (pinfunction "GPIOC_5_U31") (pintype "passive+no_connect"))
    )
    (net (code "490") (name "unconnected-(U1J-GPIOH_6-PadT30)") (class "Default")
      (node (ref "U1") (pin "T30") (pinfunction "GPIOH_6_T30") (pintype "passive"))
    )
    (net (code "491") (name "unconnected-(U1J-GPIOH_7-PadT31)") (class "Default")
      (node (ref "U1") (pin "T31") (pinfunction "GPIOH_7_T31") (pintype "passive+no_connect"))
    )
    (net (code "492") (name "unconnected-(U1K-DDR1_AC_38-PadW6)") (class "Default")
      (node (ref "U1") (pin "W6") (pinfunction "DDR1_AC_38_W6") (pintype "passive+no_connect"))
    )
    (net (code "493") (name "unconnected-(U1K-GPIOC_0-PadV32)") (class "Default")
      (node (ref "U1") (pin "V32") (pinfunction "GPIOC_0_V32") (pintype "passive+no_connect"))
    )
    (net (code "494") (name "unconnected-(U1K-GPIOC_1-PadW32)") (class "Default")
      (node (ref "U1") (pin "W32") (pinfunction "GPIOC_1_W32") (pintype "passive+no_connect"))
    )
    (net (code "495") (name "unconnected-(U1K-GPIOC_6-PadW33)") (class "Default")
      (node (ref "U1") (pin "W33") (pinfunction "GPIOC_6_W33") (pintype "passive+no_connect"))
    )
    (net (code "496") (name "unconnected-(U1K-GPIOZ_6-PadV28)") (class "Default")
      (node (ref "U1") (pin "V28") (pinfunction "GPIOZ_6_V28") (pintype "passive+no_connect"))
    )
    (net (code "497") (name "unconnected-(U1K-GPIOZ_8-PadW29)") (class "Default")
      (node (ref "U1") (pin "W29") (pinfunction "GPIOZ_8_W29") (pintype "passive+no_connect"))
    )
    (net (code "498") (name "unconnected-(U1K-GPIOZ_9-PadW30)") (class "Default")
      (node (ref "U1") (pin "W30") (pinfunction "GPIOZ_9_W30") (pintype "passive+no_connect"))
    )
    (net (code "499") (name "unconnected-(U1K-GPIOZ_10-PadW31)") (class "Default")
      (node (ref "U1") (pin "W31") (pinfunction "GPIOZ_10_W31") (pintype "passive+no_connect"))
    )
    (net (code "500") (name "unconnected-(U1K-GPIOZ_11-PadV30)") (class "Default")
      (node (ref "U1") (pin "V30") (pinfunction "GPIOZ_11_V30") (pintype "passive+no_connect"))
    )
    (net (code "501") (name "unconnected-(U1K-GPIOZ_12-PadV31)") (class "Default")
      (node (ref "U1") (pin "V31") (pinfunction "GPIOZ_12_V31") (pintype "passive+no_connect"))
    )
    (net (code "502") (name "unconnected-(U1K-GPIOZ_13-PadV29)") (class "Default")
      (node (ref "U1") (pin "V29") (pinfunction "GPIOZ_13_V29") (pintype "passive+no_connect"))
    )
    (net (code "503") (name "unconnected-(U1L-DDR1_AC_36-PadAA6)") (class "Default")
      (node (ref "U1") (pin "AA6") (pinfunction "DDR1_AC_36_AA6") (pintype "passive+no_connect"))
    )
    (net (code "504") (name "unconnected-(U1L-ENET_ATP-PadAA25)") (class "Default")
      (node (ref "U1") (pin "AA25") (pinfunction "ENET_ATP_AA25") (pintype "passive+no_connect"))
    )
    (net (code "505") (name "unconnected-(U1L-ENET_RXP-PadAA32)") (class "Default")
      (node (ref "U1") (pin "AA32") (pinfunction "ENET_RXP_AA32") (pintype "passive+no_connect"))
    )
    (net (code "506") (name "unconnected-(U1L-ENET_TXN-PadY32)") (class "Default")
      (node (ref "U1") (pin "Y32") (pinfunction "ENET_TXN_Y32") (pintype "passive+no_connect"))
    )
    (net (code "507") (name "unconnected-(U1L-ENET_TXP-PadY33)") (class "Default")
      (node (ref "U1") (pin "Y33") (pinfunction "ENET_TXP_Y33") (pintype "passive+no_connect"))
    )
    (net (code "508") (name "unconnected-(U1L-GPIOZ_3-PadAA30)") (class "Default")
      (node (ref "U1") (pin "AA30") (pinfunction "GPIOZ_3_AA30") (pintype "passive+no_connect"))
    )
    (net (code "509") (name "unconnected-(U1L-GPIOZ_5-PadAA29)") (class "Default")
      (node (ref "U1") (pin "AA29") (pinfunction "GPIOZ_5_AA29") (pintype "passive+no_connect"))
    )
    (net (code "510") (name "unconnected-(U1L-GPIOZ_7-PadAA28)") (class "Default")
      (node (ref "U1") (pin "AA28") (pinfunction "GPIOZ_7_AA28") (pintype "passive+no_connect"))
    )
    (net (code "511") (name "unconnected-(U1M-DDR1_AC_37-PadAB6)") (class "Default")
      (node (ref "U1") (pin "AB6") (pinfunction "DDR1_AC_37_AB6") (pintype "passive+no_connect"))
    )
    (net (code "512") (name "unconnected-(U1M-ENET_RXN-PadAB32)") (class "Default")
      (node (ref "U1") (pin "AB32") (pinfunction "ENET_RXN_AB32") (pintype "passive+no_connect"))
    )
    (net (code "513") (name "unconnected-(U1N-AU_AIL1-PadAC31)") (class "Default")
      (node (ref "U1") (pin "AC31") (pinfunction "AU_AIL1_AC31") (pintype "passive+no_connect"))
    )
    (net (code "514") (name "unconnected-(U1N-AU_AIL2-PadAC32)") (class "Default")
      (node (ref "U1") (pin "AC32") (pinfunction "AU_AIL2_AC32") (pintype "passive+no_connect"))
    )
    (net (code "515") (name "unconnected-(U1N-AU_AIR1-PadAC33)") (class "Default")
      (node (ref "U1") (pin "AC33") (pinfunction "AU_AIR1_AC33") (pintype "passive+no_connect"))
    )
    (net (code "516") (name "unconnected-(U1N-AU_AIR2-PadAD32)") (class "Default")
      (node (ref "U1") (pin "AD32") (pinfunction "AU_AIR2_AD32") (pintype "passive+no_connect"))
    )
    (net (code "517") (name "unconnected-(U1N-AU_VMID-PadAD26)") (class "Default")
      (node (ref "U1") (pin "AD26") (pinfunction "AU_VMID_AD26") (pintype "passive+no_connect"))
    )
    (net (code "518") (name "unconnected-(U1N-DDR1_AC_34-PadAE6)") (class "Default")
      (node (ref "U1") (pin "AE6") (pinfunction "DDR1_AC_34_AE6") (pintype "passive+no_connect"))
    )
    (net (code "519") (name "unconnected-(U1O-AU_LO1L-PadAE30)") (class "Default")
      (node (ref "U1") (pin "AE30") (pinfunction "AU_LO1L_AE30") (pintype "passive+no_connect"))
    )
    (net (code "520") (name "unconnected-(U1O-AU_LO1R-PadAE31)") (class "Default")
      (node (ref "U1") (pin "AE31") (pinfunction "AU_LO1R_AE31") (pintype "passive+no_connect"))
    )
    (net (code "521") (name "unconnected-(U1O-AU_REFP-PadAE28)") (class "Default")
      (node (ref "U1") (pin "AE28") (pinfunction "AU_REFP_AE28") (pintype "passive+no_connect"))
    )
    (net (code "522") (name "unconnected-(U1O-AVDD18_AUDIO-PadAE25)") (class "Default")
      (node (ref "U1") (pin "AE25") (pinfunction "AVDD18_AUDIO_AE25") (pintype "passive+no_connect"))
    )
    (net (code "523") (name "unconnected-(U1O-AVSS_AUDIO-PadAE26)") (class "Default")
      (node (ref "U1") (pin "AE26") (pinfunction "AVSS_AUDIO_AE26") (pintype "passive+no_connect"))
    )
    (net (code "524") (name "unconnected-(U1O-DDR1_AC_35-PadAG6)") (class "Default")
      (node (ref "U1") (pin "AG6") (pinfunction "DDR1_AC_35_AG6") (pintype "passive+no_connect"))
    )
    (net (code "525") (name "unconnected-(U1O-GPIOW_4-PadAF33)") (class "Default")
      (node (ref "U1") (pin "AF33") (pinfunction "GPIOW_4_AF33") (pintype "passive+no_connect"))
    )
    (net (code "526") (name "unconnected-(U1O-GPIOW_12-PadAF32)") (class "Default")
      (node (ref "U1") (pin "AF32") (pinfunction "GPIOW_12_AF32") (pintype "passive+no_connect"))
    )
    (net (code "527") (name "unconnected-(U1O-GPIOW_13-PadAF31)") (class "Default")
      (node (ref "U1") (pin "AF31") (pinfunction "GPIOW_13_AF31") (pintype "passive+no_connect"))
    )
    (net (code "528") (name "unconnected-(U1O-GPIOW_14-PadAE33)") (class "Default")
      (node (ref "U1") (pin "AE33") (pinfunction "GPIOW_14_AE33") (pintype "passive+no_connect"))
    )
    (net (code "529") (name "unconnected-(U1P-AVDD18_HDMITX_EARCRX-PadAH25)") (class "Default")
      (node (ref "U1") (pin "AH25") (pinfunction "AVDD18_HDMITX_EARCRX_AH25") (pintype "passive+no_connect"))
    )
    (net (code "530") (name "unconnected-(U1P-DDR1_AC_15-PadAH6)") (class "Default")
      (node (ref "U1") (pin "AH6") (pinfunction "DDR1_AC_15_AH6") (pintype "passive+no_connect"))
    )
    (net (code "531") (name "unconnected-(U1P-GPIOW_0-PadAH28)") (class "Default")
      (node (ref "U1") (pin "AH28") (pinfunction "GPIOW_0_AH28") (pintype "passive+no_connect"))
    )
    (net (code "532") (name "unconnected-(U1P-GPIOW_2-PadAG29)") (class "Default")
      (node (ref "U1") (pin "AG29") (pinfunction "GPIOW_2_AG29") (pintype "passive+no_connect"))
    )
    (net (code "533") (name "unconnected-(U1P-GPIOW_3-PadAG28)") (class "Default")
      (node (ref "U1") (pin "AG28") (pinfunction "GPIOW_3_AG28") (pintype "passive+no_connect"))
    )
    (net (code "534") (name "unconnected-(U1P-GPIOW_8-PadAG31)") (class "Default")
      (node (ref "U1") (pin "AG31") (pinfunction "GPIOW_8_AG31") (pintype "passive+no_connect"))
    )
    (net (code "535") (name "unconnected-(U1P-GPIOW_9-PadAG30)") (class "Default")
      (node (ref "U1") (pin "AG30") (pinfunction "GPIOW_9_AG30") (pintype "passive+no_connect"))
    )
    (net (code "536") (name "unconnected-(U1P-GPIOW_10-PadAH29)") (class "Default")
      (node (ref "U1") (pin "AH29") (pinfunction "GPIOW_10_AH29") (pintype "passive+no_connect"))
    )
    (net (code "537") (name "unconnected-(U1P-GPIOW_11-PadAH30)") (class "Default")
      (node (ref "U1") (pin "AH30") (pinfunction "GPIOW_11_AH30") (pintype "passive+no_connect"))
    )
    (net (code "538") (name "unconnected-(U1P-GPIOW_15-PadAG32)") (class "Default")
      (node (ref "U1") (pin "AG32") (pinfunction "GPIOW_15_AG32") (pintype "passive+no_connect"))
    )
    (net (code "539") (name "unconnected-(U1P-GPIOW_16-PadAH31)") (class "Default")
      (node (ref "U1") (pin "AH31") (pinfunction "GPIOW_16_AH31") (pintype "passive+no_connect"))
    )
    (net (code "540") (name "unconnected-(U1Q-AVDD08_HDMIRX-PadAK23)") (class "Default")
      (node (ref "U1") (pin "AK23") (pinfunction "AVDD08_HDMIRX_AK23") (pintype "passive+no_connect"))
    )
    (net (code "541") (name "unconnected-(U1Q-AVDD33_HDMITX-PadAJ21)") (class "Default")
      (node (ref "U1") (pin "AJ21") (pinfunction "AVDD33_HDMITX_AJ21") (pintype "passive+no_connect"))
    )
    (net (code "542") (name "unconnected-(U1Q-AVSS_HPLL-PadAJ26)") (class "Default")
      (node (ref "U1") (pin "AJ26") (pinfunction "AVSS_HPLL_AJ26") (pintype "passive+no_connect"))
    )
    (net (code "543") (name "unconnected-(U1Q-GPIOW_6-PadAH33)") (class "Default")
      (node (ref "U1") (pin "AH33") (pinfunction "GPIOW_6_AH33") (pintype "passive+no_connect"))
    )
    (net (code "544") (name "unconnected-(U1Q-GPIOW_7-PadAH32)") (class "Default")
      (node (ref "U1") (pin "AH32") (pinfunction "GPIOW_7_AH32") (pintype "passive+no_connect"))
    )
    (net (code "545") (name "unconnected-(U1Q-HDMITX_D2P-PadAJ32)") (class "Default")
      (node (ref "U1") (pin "AJ32") (pinfunction "HDMITX_D2P_AJ32") (pintype "passive+no_connect"))
    )
    (net (code "546") (name "unconnected-(U1Q-HDMITX_REXT-PadAJ33)") (class "Default")
      (node (ref "U1") (pin "AJ33") (pinfunction "HDMITX_REXT_AJ33") (pintype "passive+no_connect"))
    )
    (net (code "547") (name "unconnected-(U1R-AVDD08_HDMITX-PadAL25)") (class "Default")
      (node (ref "U1") (pin "AL25") (pinfunction "AVDD08_HDMITX_AL25") (pintype "passive+no_connect"))
    )
    (net (code "548") (name "unconnected-(U1R-AVDD18_HDMIRX_EARCTX-PadAK25)") (class "Default")
      (node (ref "U1") (pin "AK25") (pinfunction "AVDD18_HDMIRX_EARCTX_AK25") (pintype "passive"))
    )
    (net (code "549") (name "unconnected-(U1R-AVDD33_HDMIRX-PadAK24)") (class "Default")
      (node (ref "U1") (pin "AK24") (pinfunction "AVDD33_HDMIRX_AK24") (pintype "passive+no_connect"))
    )
    (net (code "550") (name "unconnected-(U1R-GPIOY_0-PadAM17)") (class "Default")
      (node (ref "U1") (pin "AM17") (pinfunction "GPIOY_0_AM17") (pintype "passive+no_connect"))
    )
    (net (code "551") (name "unconnected-(U1R-HDMIRX_C_D0N-PadAL28)") (class "Default")
      (node (ref "U1") (pin "AL28") (pinfunction "HDMIRX_C_D0N_AL28") (pintype "passive+no_connect"))
    )
    (net (code "552") (name "unconnected-(U1R-HDMIRX_C_D0P-PadAL29)") (class "Default")
      (node (ref "U1") (pin "AL29") (pinfunction "HDMIRX_C_D0P_AL29") (pintype "passive+no_connect"))
    )
    (net (code "553") (name "unconnected-(U1R-HDMIRX_C_D1N-PadAL30)") (class "Default")
      (node (ref "U1") (pin "AL30") (pinfunction "HDMIRX_C_D1N_AL30") (pintype "passive+no_connect"))
    )
    (net (code "554") (name "unconnected-(U1R-HDMIRX_C_D1P-PadAL31)") (class "Default")
      (node (ref "U1") (pin "AL31") (pinfunction "HDMIRX_C_D1P_AL31") (pintype "passive+no_connect"))
    )
    (net (code "555") (name "unconnected-(U1R-HDMIRX_C_D2N-PadAK30)") (class "Default")
      (node (ref "U1") (pin "AK30") (pinfunction "HDMIRX_C_D2N_AK30") (pintype "passive+no_connect"))
    )
    (net (code "556") (name "unconnected-(U1R-HDMIRX_C_D2P-PadAK31)") (class "Default")
      (node (ref "U1") (pin "AK31") (pinfunction "HDMIRX_C_D2P_AK31") (pintype "passive+no_connect"))
    )
    (net (code "557") (name "unconnected-(U1R-HDMITX_ARCRXN-PadAK29)") (class "Default")
      (node (ref "U1") (pin "AK29") (pinfunction "HDMITX_ARCRXN_AK29") (pintype "passive+no_connect"))
    )
    (net (code "558") (name "unconnected-(U1R-HDMITX_ARCRXP-PadAK28)") (class "Default")
      (node (ref "U1") (pin "AK28") (pinfunction "HDMITX_ARCRXP_AK28") (pintype "passive+no_connect"))
    )
    (net (code "559") (name "unconnected-(U1R-HDMITX_D1N-PadAL33)") (class "Default")
      (node (ref "U1") (pin "AL33") (pinfunction "HDMITX_D1N_AL33") (pintype "passive+no_connect"))
    )
    (net (code "560") (name "unconnected-(U1R-HDMITX_D1P-PadAL32)") (class "Default")
      (node (ref "U1") (pin "AL32") (pinfunction "HDMITX_D1P_AL32") (pintype "passive+no_connect"))
    )
    (net (code "561") (name "unconnected-(U1R-HDMITX_D2N-PadAK32)") (class "Default")
      (node (ref "U1") (pin "AK32") (pinfunction "HDMITX_D2N_AK32") (pintype "passive"))
    )
    (net (code "562") (name "unconnected-(U1R-VX1_ATP-PadAL19)") (class "Default")
      (node (ref "U1") (pin "AL19") (pinfunction "VX1_ATP_AL19") (pintype "passive+no_connect"))
    )
    (net (code "563") (name "unconnected-(U1R-VX1_A_5N-PadAM15)") (class "Default")
      (node (ref "U1") (pin "AM15") (pinfunction "VX1_A_5N_AM15") (pintype "passive+no_connect"))
    )
    (net (code "564") (name "unconnected-(U1R-VX1_B_4P-PadAM12)") (class "Default")
      (node (ref "U1") (pin "AM12") (pinfunction "VX1_B_4P_AM12") (pintype "passive+no_connect"))
    )
    (net (code "565") (name "unconnected-(U1R-VX1_LPN-PadAL17)") (class "Default")
      (node (ref "U1") (pin "AL17") (pinfunction "VX1_LPN_AL17") (pintype "passive+no_connect"))
    )
    (net (code "566") (name "unconnected-(U1R-VX1_LPP-PadAL16)") (class "Default")
      (node (ref "U1") (pin "AL16") (pinfunction "VX1_LPP_AL16") (pintype "passive+no_connect"))
    )
    (net (code "567") (name "unconnected-(U1S-DDR1_AC_6-PadAN4)") (class "Default")
      (node (ref "U1") (pin "AN4") (pinfunction "DDR1_AC_6_AN4") (pintype "passive+no_connect"))
    )
    (net (code "568") (name "unconnected-(U1S-GPIOW_1-PadAN27)") (class "Default")
      (node (ref "U1") (pin "AN27") (pinfunction "GPIOW_1_AN27") (pintype "passive+no_connect"))
    )
    (net (code "569") (name "unconnected-(U1S-GPIOW_5-PadAN28)") (class "Default")
      (node (ref "U1") (pin "AN28") (pinfunction "GPIOW_5_AN28") (pintype "passive+no_connect"))
    )
    (net (code "570") (name "unconnected-(U1S-GPIOY_3-PadAN20)") (class "Default")
      (node (ref "U1") (pin "AN20") (pinfunction "GPIOY_3_AN20") (pintype "passive+no_connect"))
    )
    (net (code "571") (name "unconnected-(U1S-HDMIRX_C_CLKN-PadAN30)") (class "Default")
      (node (ref "U1") (pin "AN30") (pinfunction "HDMIRX_C_CLKN_AN30") (pintype "passive+no_connect"))
    )
    (net (code "572") (name "unconnected-(U1S-HDMIRX_C_CLKP-PadAN31)") (class "Default")
      (node (ref "U1") (pin "AN31") (pinfunction "HDMIRX_C_CLKP_AN31") (pintype "passive+no_connect"))
    )
    (net (code "573") (name "unconnected-(U1S-HDMITX_D0N-PadAN32)") (class "Default")
      (node (ref "U1") (pin "AN32") (pinfunction "HDMITX_D0N_AN32") (pintype "passive+no_connect"))
    )
    (net (code "574") (name "unconnected-(U1S-HDMITX_D0P-PadAM32)") (class "Default")
      (node (ref "U1") (pin "AM32") (pinfunction "HDMITX_D0P_AM32") (pintype "passive+no_connect"))
    )
    (net (code "575") (name "unconnected-(U1S-VDDIO_B-PadAM23)") (class "Default")
      (node (ref "U1") (pin "AM23") (pinfunction "VDDIO_B_AM23") (pintype "passive"))
    )
    (net (code "576") (name "unconnected-(U1S-VX1_A_5P-PadAN15)") (class "Default")
      (node (ref "U1") (pin "AN15") (pinfunction "VX1_A_5P_AN15") (pintype "passive+no_connect"))
    )
    (net (code "577") (name "unconnected-(U1S-VX1_A_7P-PadAP15)") (class "Default")
      (node (ref "U1") (pin "AP15") (pinfunction "VX1_A_7P_AP15") (pintype "passive+no_connect"))
    )
    (net (code "578") (name "unconnected-(U1S-VX1_B_1P-PadAP14)") (class "Default")
      (node (ref "U1") (pin "AP14") (pinfunction "VX1_B_1P_AP14") (pintype "passive+no_connect"))
    )
    (net (code "579") (name "unconnected-(U1S-VX1_B_4N-PadAN12)") (class "Default")
      (node (ref "U1") (pin "AN12") (pinfunction "VX1_B_4N_AN12") (pintype "passive+no_connect"))
    )
    (net (code "580") (name "unconnected-(U1S-VX1_B_5N-PadAP12)") (class "Default")
      (node (ref "U1") (pin "AP12") (pinfunction "VX1_B_5N_AP12") (pintype "passive+no_connect"))
    )
    (net (code "581") (name "unconnected-(U1S-VX1_B_6N-PadAP11)") (class "Default")
      (node (ref "U1") (pin "AP11") (pinfunction "VX1_B_6N_AP11") (pintype "passive+no_connect"))
    )
    (net (code "582") (name "unconnected-(U1S-VX1_B_7N-PadAN11)") (class "Default")
      (node (ref "U1") (pin "AN11") (pinfunction "VX1_B_7N_AN11") (pintype "passive+no_connect"))
    )
    (net (code "583") (name "unconnected-(U1S-VX1_B_7P-PadAN10)") (class "Default")
      (node (ref "U1") (pin "AN10") (pinfunction "VX1_B_7P_AN10") (pintype "passive+no_connect"))
    )
    (net (code "584") (name "unconnected-(U1T-DDR1_AC_7-PadAR2)") (class "Default")
      (node (ref "U1") (pin "AR2") (pinfunction "DDR1_AC_7_AR2") (pintype "passive+no_connect"))
    )
    (net (code "585") (name "unconnected-(U1T-DDR1_AC_14-PadAT2)") (class "Default")
      (node (ref "U1") (pin "AT2") (pinfunction "DDR1_AC_14_AT2") (pintype "passive+no_connect"))
    )
    (net (code "586") (name "unconnected-(U1T-DDR1_AC_26-PadAR3)") (class "Default")
      (node (ref "U1") (pin "AR3") (pinfunction "DDR1_AC_26_AR3") (pintype "passive+no_connect"))
    )
    (net (code "587") (name "unconnected-(U1T-GPIOY_8-PadAR20)") (class "Default")
      (node (ref "U1") (pin "AR20") (pinfunction "GPIOY_8_AR20") (pintype "passive+no_connect"))
    )
    (net (code "588") (name "unconnected-(U1T-HDMIRX_ARCTXN-PadAP27)") (class "Default")
      (node (ref "U1") (pin "AP27") (pinfunction "HDMIRX_ARCTXN_AP27") (pintype "passive+no_connect"))
    )
    (net (code "589") (name "unconnected-(U1T-HDMIRX_ARCTXP-PadAR27)") (class "Default")
      (node (ref "U1") (pin "AR27") (pinfunction "HDMIRX_ARCTXP_AR27") (pintype "passive+no_connect"))
    )
    (net (code "590") (name "unconnected-(U1T-HDMIRX_A_D2P-PadAR33)") (class "Default")
      (node (ref "U1") (pin "AR33") (pinfunction "HDMIRX_A_D2P_AR33") (pintype "passive"))
    )
    (net (code "591") (name "unconnected-(U1T-HDMIRX_B_CLKN-PadAR28)") (class "Default")
      (node (ref "U1") (pin "AR28") (pinfunction "HDMIRX_B_CLKN_AR28") (pintype "passive+no_connect"))
    )
    (net (code "592") (name "unconnected-(U1T-HDMIRX_B_CLKP-PadAP28)") (class "Default")
      (node (ref "U1") (pin "AP28") (pinfunction "HDMIRX_B_CLKP_AP28") (pintype "passive+no_connect"))
    )
    (net (code "593") (name "unconnected-(U1T-HDMIRX_B_D0N-PadAP29)") (class "Default")
      (node (ref "U1") (pin "AP29") (pinfunction "HDMIRX_B_D0N_AP29") (pintype "passive+no_connect"))
    )
    (net (code "594") (name "unconnected-(U1T-HDMIRX_B_D0P-PadAP30)") (class "Default")
      (node (ref "U1") (pin "AP30") (pinfunction "HDMIRX_B_D0P_AP30") (pintype "passive+no_connect"))
    )
    (net (code "595") (name "unconnected-(U1T-HDMIRX_B_D1N-PadAR30)") (class "Default")
      (node (ref "U1") (pin "AR30") (pinfunction "HDMIRX_B_D1N_AR30") (pintype "passive+no_connect"))
    )
    (net (code "596") (name "unconnected-(U1T-HDMIRX_B_D1P-PadAR31)") (class "Default")
      (node (ref "U1") (pin "AR31") (pinfunction "HDMIRX_B_D1P_AR31") (pintype "passive+no_connect"))
    )
    (net (code "597") (name "unconnected-(U1T-HDMIRX_B_D2P-PadAR32)") (class "Default")
      (node (ref "U1") (pin "AR32") (pinfunction "HDMIRX_B_D2P_AR32") (pintype "passive+no_connect"))
    )
    (net (code "598") (name "unconnected-(U1T-HDMITX_CLKN-PadAP33)") (class "Default")
      (node (ref "U1") (pin "AP33") (pinfunction "HDMITX_CLKN_AP33") (pintype "passive+no_connect"))
    )
    (net (code "599") (name "unconnected-(U1T-HDMITX_CLKP-PadAP32)") (class "Default")
      (node (ref "U1") (pin "AP32") (pinfunction "HDMITX_CLKP_AP32") (pintype "passive+no_connect"))
    )
    (net (code "600") (name "unconnected-(U1T-VX1_A_7N-PadAR15)") (class "Default")
      (node (ref "U1") (pin "AR15") (pinfunction "VX1_A_7N_AR15") (pintype "passive+no_connect"))
    )
    (net (code "601") (name "unconnected-(U1T-VX1_B_1N-PadAR14)") (class "Default")
      (node (ref "U1") (pin "AR14") (pinfunction "VX1_B_1N_AR14") (pintype "passive+no_connect"))
    )
    (net (code "602") (name "unconnected-(U1T-VX1_B_5P-PadAR12)") (class "Default")
      (node (ref "U1") (pin "AR12") (pinfunction "VX1_B_5P_AR12") (pintype "passive+no_connect"))
    )
    (net (code "603") (name "unconnected-(U1T-VX1_B_6P-PadAR11)") (class "Default")
      (node (ref "U1") (pin "AR11") (pinfunction "VX1_B_6P_AR11") (pintype "passive+no_connect"))
    )
    (net (code "604") (name "unconnected-(U1U-DIF_REXT-PadAU12)") (class "Default")
      (node (ref "U1") (pin "AU12") (pinfunction "DIF_REXT_AU12") (pintype "passive+no_connect"))
    )
    (net (code "605") (name "unconnected-(U1U-GPIOY_5-PadAT21)") (class "Default")
      (node (ref "U1") (pin "AT21") (pinfunction "GPIOY_5_AT21") (pintype "passive+no_connect"))
    )
    (net (code "606") (name "unconnected-(U1U-GPIOY_6-PadAU21)") (class "Default")
      (node (ref "U1") (pin "AU21") (pinfunction "GPIOY_6_AU21") (pintype "passive+no_connect"))
    )
    (net (code "607") (name "unconnected-(U1U-GPIOY_7-PadAT22)") (class "Default")
      (node (ref "U1") (pin "AT22") (pinfunction "GPIOY_7_AT22") (pintype "passive+no_connect"))
    )
    (net (code "608") (name "unconnected-(U1U-GPIOY_11-PadAT23)") (class "Default")
      (node (ref "U1") (pin "AT23") (pinfunction "GPIOY_11_AT23") (pintype "passive+no_connect"))
    )
    (net (code "609") (name "unconnected-(U1U-GPIOY_12-PadAT24)") (class "Default")
      (node (ref "U1") (pin "AT24") (pinfunction "GPIOY_12_AT24") (pintype "passive+no_connect"))
    )
    (net (code "610") (name "unconnected-(U1U-GPIOY_13-PadAT25)") (class "Default")
      (node (ref "U1") (pin "AT25") (pinfunction "GPIOY_13_AT25") (pintype "passive+no_connect"))
    )
    (net (code "611") (name "unconnected-(U1U-GPIOY_14-PadAT26)") (class "Default")
      (node (ref "U1") (pin "AT26") (pinfunction "GPIOY_14_AT26") (pintype "passive+no_connect"))
    )
    (net (code "612") (name "unconnected-(U1U-GPIOY_15-PadAU25)") (class "Default")
      (node (ref "U1") (pin "AU25") (pinfunction "GPIOY_15_AU25") (pintype "passive+no_connect"))
    )
    (net (code "613") (name "unconnected-(U1U-GPIOY_16-PadAU24)") (class "Default")
      (node (ref "U1") (pin "AU24") (pinfunction "GPIOY_16_AU24") (pintype "passive+no_connect"))
    )
    (net (code "614") (name "unconnected-(U1U-GPIOY_17-PadAU27)") (class "Default")
      (node (ref "U1") (pin "AU27") (pinfunction "GPIOY_17_AU27") (pintype "passive+no_connect"))
    )
    (net (code "615") (name "unconnected-(U1U-GPIOY_18-PadAT27)") (class "Default")
      (node (ref "U1") (pin "AT27") (pinfunction "GPIOY_18_AT27") (pintype "passive+no_connect"))
    )
    (net (code "616") (name "unconnected-(U1U-HDMIRX_A_CLKN-PadAU28)") (class "Default")
      (node (ref "U1") (pin "AU28") (pinfunction "HDMIRX_A_CLKN_AU28") (pintype "passive+no_connect"))
    )
    (net (code "617") (name "unconnected-(U1U-HDMIRX_A_CLKP-PadAU29)") (class "Default")
      (node (ref "U1") (pin "AU29") (pinfunction "HDMIRX_A_CLKP_AU29") (pintype "passive+no_connect"))
    )
    (net (code "618") (name "unconnected-(U1U-HDMIRX_A_D0N-PadAT29)") (class "Default")
      (node (ref "U1") (pin "AT29") (pinfunction "HDMIRX_A_D0N_AT29") (pintype "passive+no_connect"))
    )
    (net (code "619") (name "unconnected-(U1U-HDMIRX_A_D0P-PadAT30)") (class "Default")
      (node (ref "U1") (pin "AT30") (pinfunction "HDMIRX_A_D0P_AT30") (pintype "passive+no_connect"))
    )
    (net (code "620") (name "unconnected-(U1U-HDMIRX_A_D1N-PadAU31)") (class "Default")
      (node (ref "U1") (pin "AU31") (pinfunction "HDMIRX_A_D1N_AU31") (pintype "passive+no_connect"))
    )
    (net (code "621") (name "unconnected-(U1U-HDMIRX_A_D1P-PadAU32)") (class "Default")
      (node (ref "U1") (pin "AU32") (pinfunction "HDMIRX_A_D1P_AU32") (pintype "passive+no_connect"))
    )
    (net (code "622") (name "unconnected-(U1U-HDMIRX_A_D2N-PadAT33)") (class "Default")
      (node (ref "U1") (pin "AT33") (pinfunction "HDMIRX_A_D2N_AT33") (pintype "passive+no_connect"))
    )
    (net (code "623") (name "unconnected-(U1U-HDMIRX_B_D2N-PadAT32)") (class "Default")
      (node (ref "U1") (pin "AT32") (pinfunction "HDMIRX_B_D2N_AT32") (pintype "passive+no_connect"))
    )
    (net (code "624") (name "unconnected-(U1U-VX1_A_6N-PadAT17)") (class "Default")
      (node (ref "U1") (pin "AT17") (pinfunction "VX1_A_6N_AT17") (pintype "passive+no_connect"))
    )
    (net (code "625") (name "unconnected-(U1U-VX1_A_6P-PadAT16)") (class "Default")
      (node (ref "U1") (pin "AT16") (pinfunction "VX1_A_6P_AT16") (pintype "passive+no_connect"))
    )
    (net (code "626") (name "unconnected-(U1U-VX1_B_0N-PadAU16)") (class "Default")
      (node (ref "U1") (pin "AU16") (pinfunction "VX1_B_0N_AU16") (pintype "passive+no_connect"))
    )
    (net (code "627") (name "unconnected-(U1U-VX1_B_0P-PadAU15)") (class "Default")
      (node (ref "U1") (pin "AU15") (pinfunction "VX1_B_0P_AU15") (pintype "passive+no_connect"))
    )
    (net (code "628") (name "unconnected-(U1U-VX1_B_2N-PadAT15)") (class "Default")
      (node (ref "U1") (pin "AT15") (pinfunction "VX1_B_2N_AT15") (pintype "passive+no_connect"))
    )
    (net (code "629") (name "unconnected-(U1U-VX1_B_2P-PadAT14)") (class "Default")
      (node (ref "U1") (pin "AT14") (pinfunction "VX1_B_2P_AT14") (pintype "passive+no_connect"))
    )
    (net (code "630") (name "unconnected-(U1U-VX1_B_3N-PadAT13)") (class "Default")
      (node (ref "U1") (pin "AT13") (pinfunction "VX1_B_3N_AT13") (pintype "passive+no_connect"))
    )
    (net (code "631") (name "unconnected-(U1U-VX1_B_3P-PadAU13)") (class "Default")
      (node (ref "U1") (pin "AU13") (pinfunction "VX1_B_3P_AU13") (pintype "passive+no_connect"))
    )
    (net (code "632") (name "unconnected-(U3-PA8-Pad18)") (class "Default")
      (node (ref "U3") (pin "18") (pinfunction "PA8_18") (pintype "bidirectional+no_connect"))
    )
    (net (code "633") (name "unconnected-(U3-PA10-Pad21)") (class "Default")
      (node (ref "U3") (pin "21") (pinfunction "PA10_21") (pintype "bidirectional+no_connect"))
    )
    (net (code "634") (name "unconnected-(U3-PB8-Pad32)") (class "Default")
      (node (ref "U3") (pin "32") (pinfunction "PB8_32") (pintype "bidirectional+no_connect"))
    )
    (net (code "635") (name "unconnected-(U3-PB9-Pad1)") (class "Default")
      (node (ref "U3") (pin "1") (pinfunction "PB9_1") (pintype "bidirectional+no_connect"))
    )
    (net (code "636") (name "unconnected-(U3-PC6-Pad20)") (class "Default")
      (node (ref "U3") (pin "20") (pinfunction "PC6_20") (pintype "bidirectional+no_connect"))
    )
    (net (code "637") (name "unconnected-(U3-PC14-OSC32_IN-Pad2)") (class "Default")
      (node (ref "U3") (pin "2") (pinfunction "PC14-OSC32_IN_2") (pintype "bidirectional+no_connect"))
    )
    (net (code "638") (name "unconnected-(U3-PC15-OSC32_OUT-Pad3)") (class "Default")
      (node (ref "U3") (pin "3") (pinfunction "PC15-OSC32_OUT_3") (pintype "bidirectional+no_connect"))
    )
    (net (code "639") (name "unconnected-(U4A-DNU_1-PadA1)") (class "Default")
      (node (ref "U4") (pin "A1") (pinfunction "DNU_1_A1") (pintype "passive+no_connect"))
    )
    (net (code "640") (name "unconnected-(U4A-DNU_2-PadA2)") (class "Default")
      (node (ref "U4") (pin "A2") (pinfunction "DNU_2_A2") (pintype "passive+no_connect"))
    )
    (net (code "641") (name "unconnected-(U4A-DNU_3-PadA11)") (class "Default")
      (node (ref "U4") (pin "A11") (pinfunction "DNU_3_A11") (pintype "passive+no_connect"))
    )
    (net (code "642") (name "unconnected-(U4A-DNU_4-PadA12)") (class "Default")
      (node (ref "U4") (pin "A12") (pinfunction "DNU_4_A12") (pintype "passive+no_connect"))
    )
    (net (code "643") (name "unconnected-(U4A-DNU_5-PadB1)") (class "Default")
      (node (ref "U4") (pin "B1") (pinfunction "DNU_5_B1") (pintype "passive+no_connect"))
    )
    (net (code "644") (name "unconnected-(U4A-DNU_6-PadB12)") (class "Default")
      (node (ref "U4") (pin "B12") (pinfunction "DNU_6_B12") (pintype "passive"))
    )
    (net (code "645") (name "unconnected-(U4A-NC_4-PadN5)") (class "Default")
      (node (ref "U4") (pin "N5") (pinfunction "NC_4_N5") (pintype "passive+no_connect"))
    )
    (net (code "646") (name "unconnected-(U4A-NC_5-PadN8)") (class "Default")
      (node (ref "U4") (pin "N8") (pinfunction "NC_5_N8") (pintype "passive+no_connect"))
    )
    (net (code "647") (name "unconnected-(U4B-DNU_7-PadAA1)") (class "Default")
      (node (ref "U4") (pin "AA1") (pinfunction "DNU_7_AA1") (pintype "passive+no_connect"))
    )
    (net (code "648") (name "unconnected-(U4B-DNU_8-PadAA12)") (class "Default")
      (node (ref "U4") (pin "AA12") (pinfunction "DNU_8_AA12") (pintype "passive+no_connect"))
    )
    (net (code "649") (name "unconnected-(U4B-DNU_9-PadAB1)") (class "Default")
      (node (ref "U4") (pin "AB1") (pinfunction "DNU_9_AB1") (pintype "passive+no_connect"))
    )
    (net (code "650") (name "unconnected-(U4B-DNU_10-PadAB2)") (class "Default")
      (node (ref "U4") (pin "AB2") (pinfunction "DNU_10_AB2") (pintype "passive+no_connect"))
    )
    (net (code "651") (name "unconnected-(U4B-DNU_11-PadAB11)") (class "Default")
      (node (ref "U4") (pin "AB11") (pinfunction "DNU_11_AB11") (pintype "passive+no_connect"))
    )
    (net (code "652") (name "unconnected-(U4B-DNU_12-PadAB12)") (class "Default")
      (node (ref "U4") (pin "AB12") (pinfunction "DNU_12_AB12") (pintype "passive+no_connect"))
    )
    (net (code "653") (name "unconnected-(U4B-NC_1-PadG11)") (class "Default")
      (node (ref "U4") (pin "G11") (pinfunction "NC_1_G11") (pintype "passive+no_connect"))
    )
    (net (code "654") (name "unconnected-(U4B-NC_2-PadK5)") (class "Default")
      (node (ref "U4") (pin "K5") (pinfunction "NC_2_K5") (pintype "passive+no_connect"))
    )
    (net (code "655") (name "unconnected-(U4B-NC_3-PadK8)") (class "Default")
      (node (ref "U4") (pin "K8") (pinfunction "NC_3_K8") (pintype "passive+no_connect"))
    )
    (net (code "656") (name "unconnected-(U4B-VDD2_24-PadAB9)") (class "Default")
      (node (ref "U4") (pin "AB9") (pinfunction "VDD2_24_AB9") (pintype "passive"))
    )
    (net (code "657") (name "unconnected-(U6-STAT-Pad1)") (class "Default")
      (node (ref "U6") (pin "1") (pinfunction "STAT_1") (pintype "open_collector+no_connect"))
    )
    (net (code "658") (name "unconnected-(U25-DOUT-Pad2)") (class "Default")
      (node (ref "U25") (pin "2") (pinfunction "DOUT_2") (pintype "output+no_connect"))
    )
  )
)
